# DMFX-1_v1_2.net
KiCad netlist of a schematic drawn in EAGLE
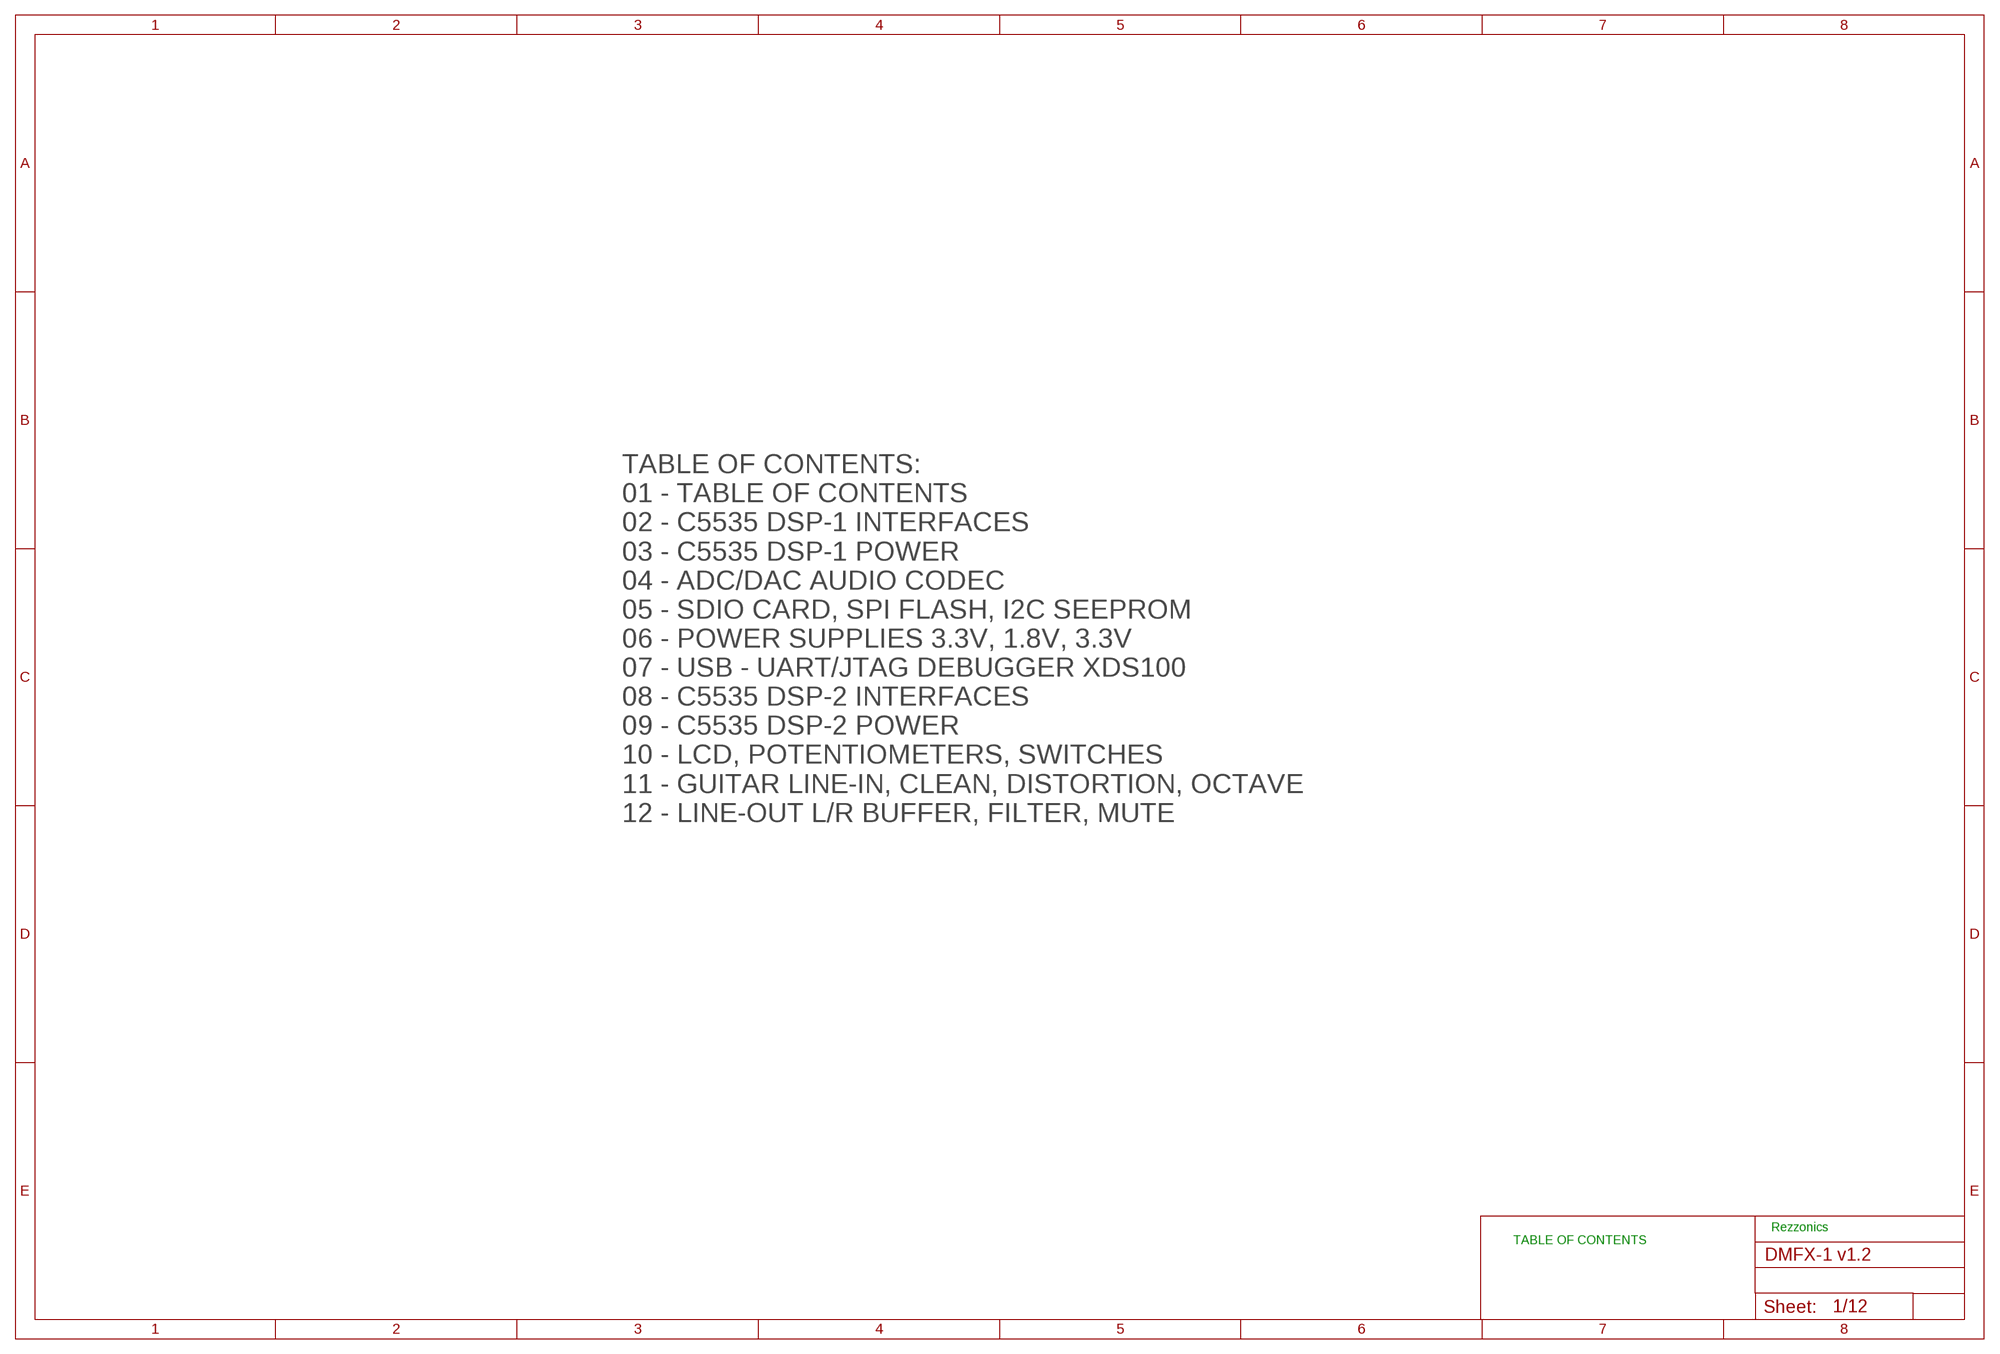
[diagram p0: schematic, sheet 1]
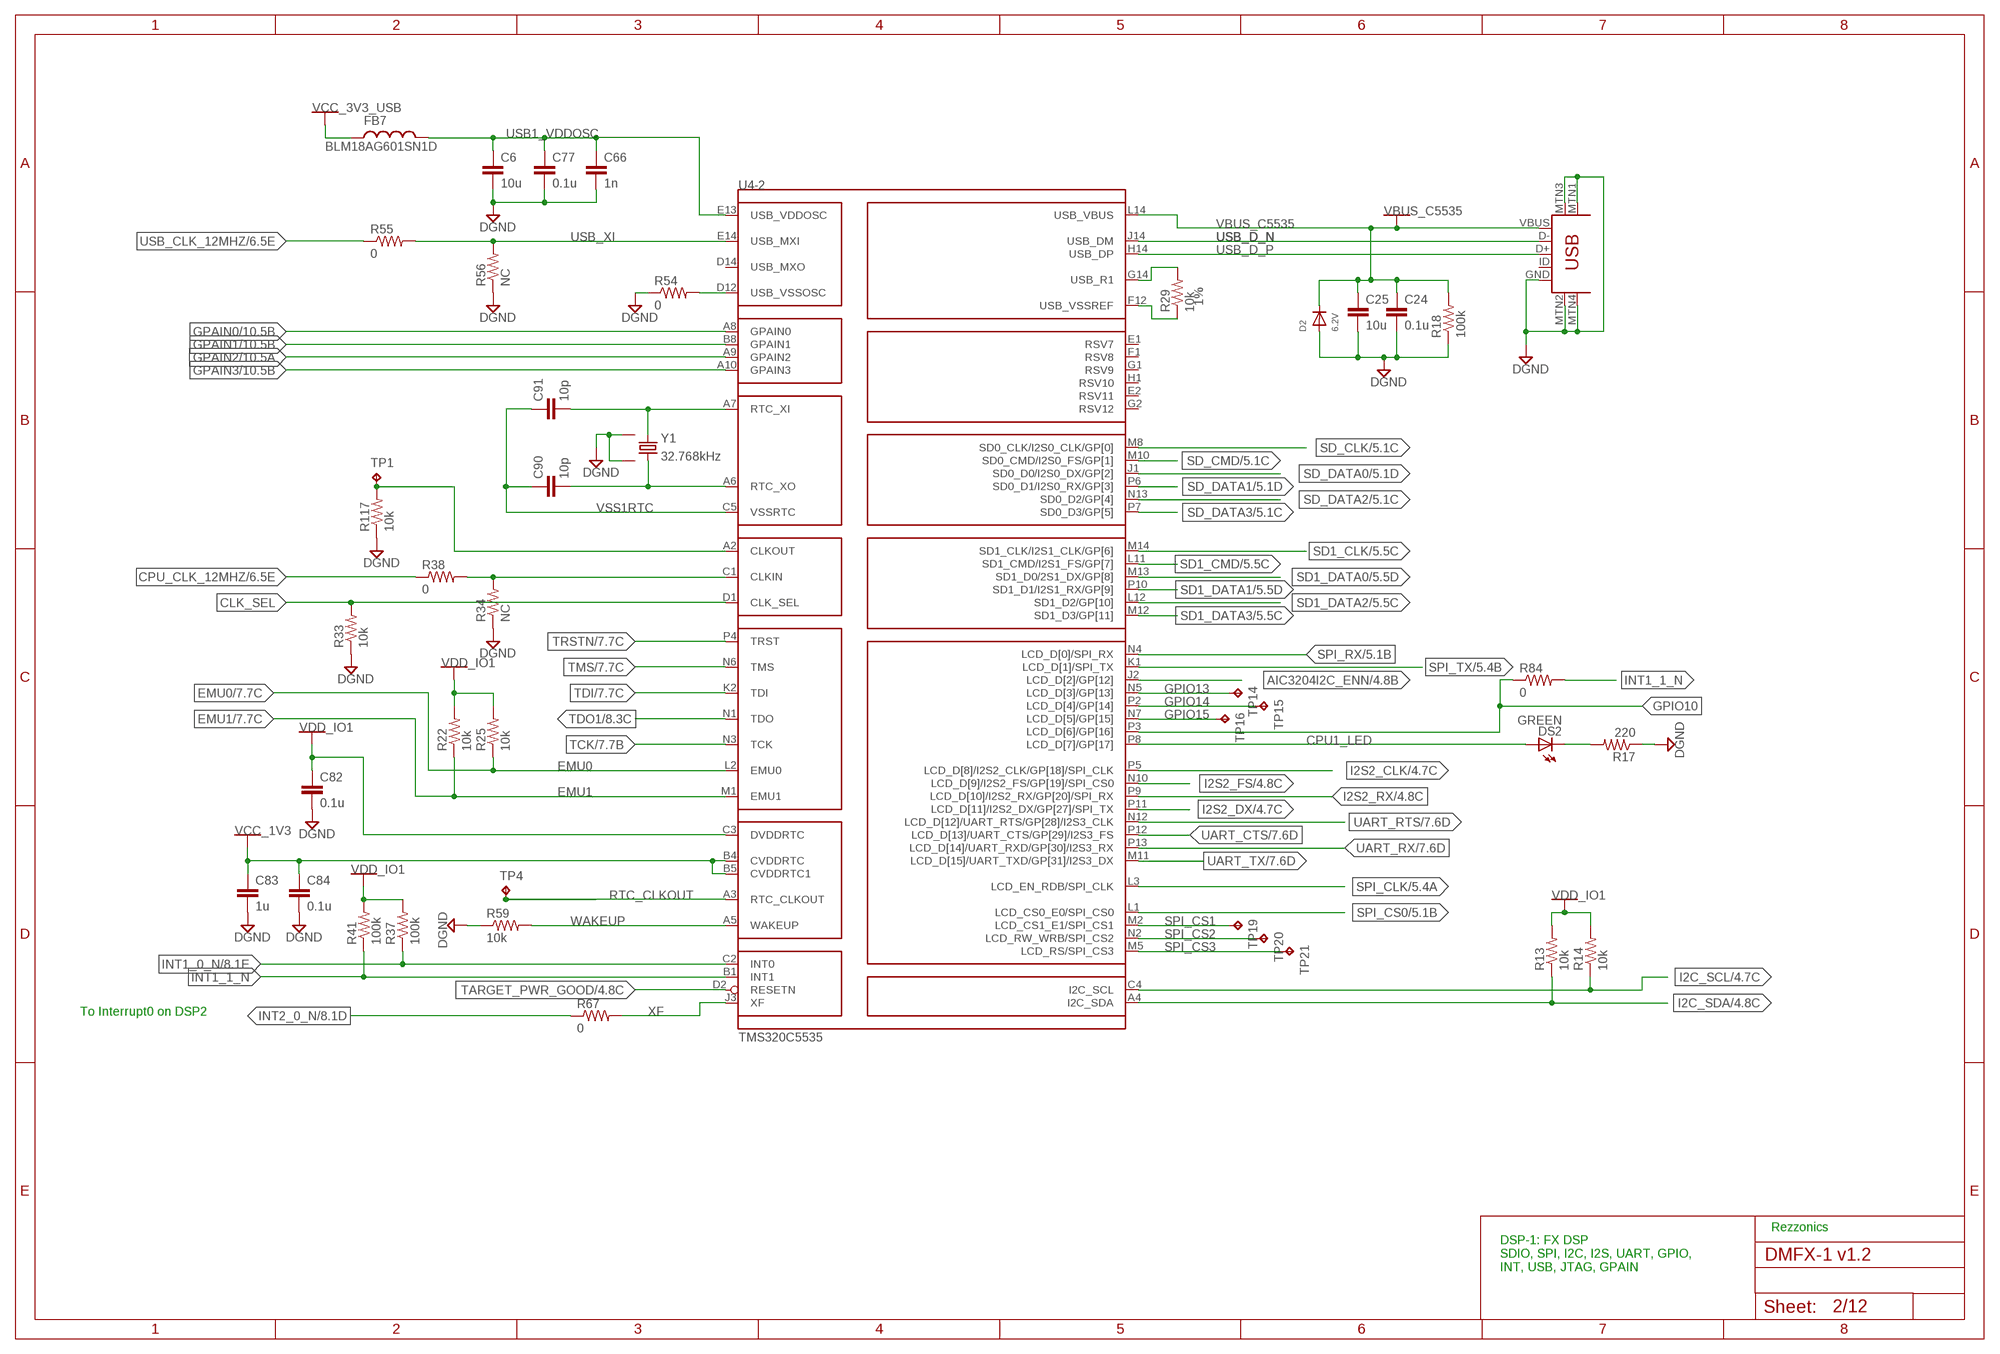
[diagram p1: schematic, sheet 2]
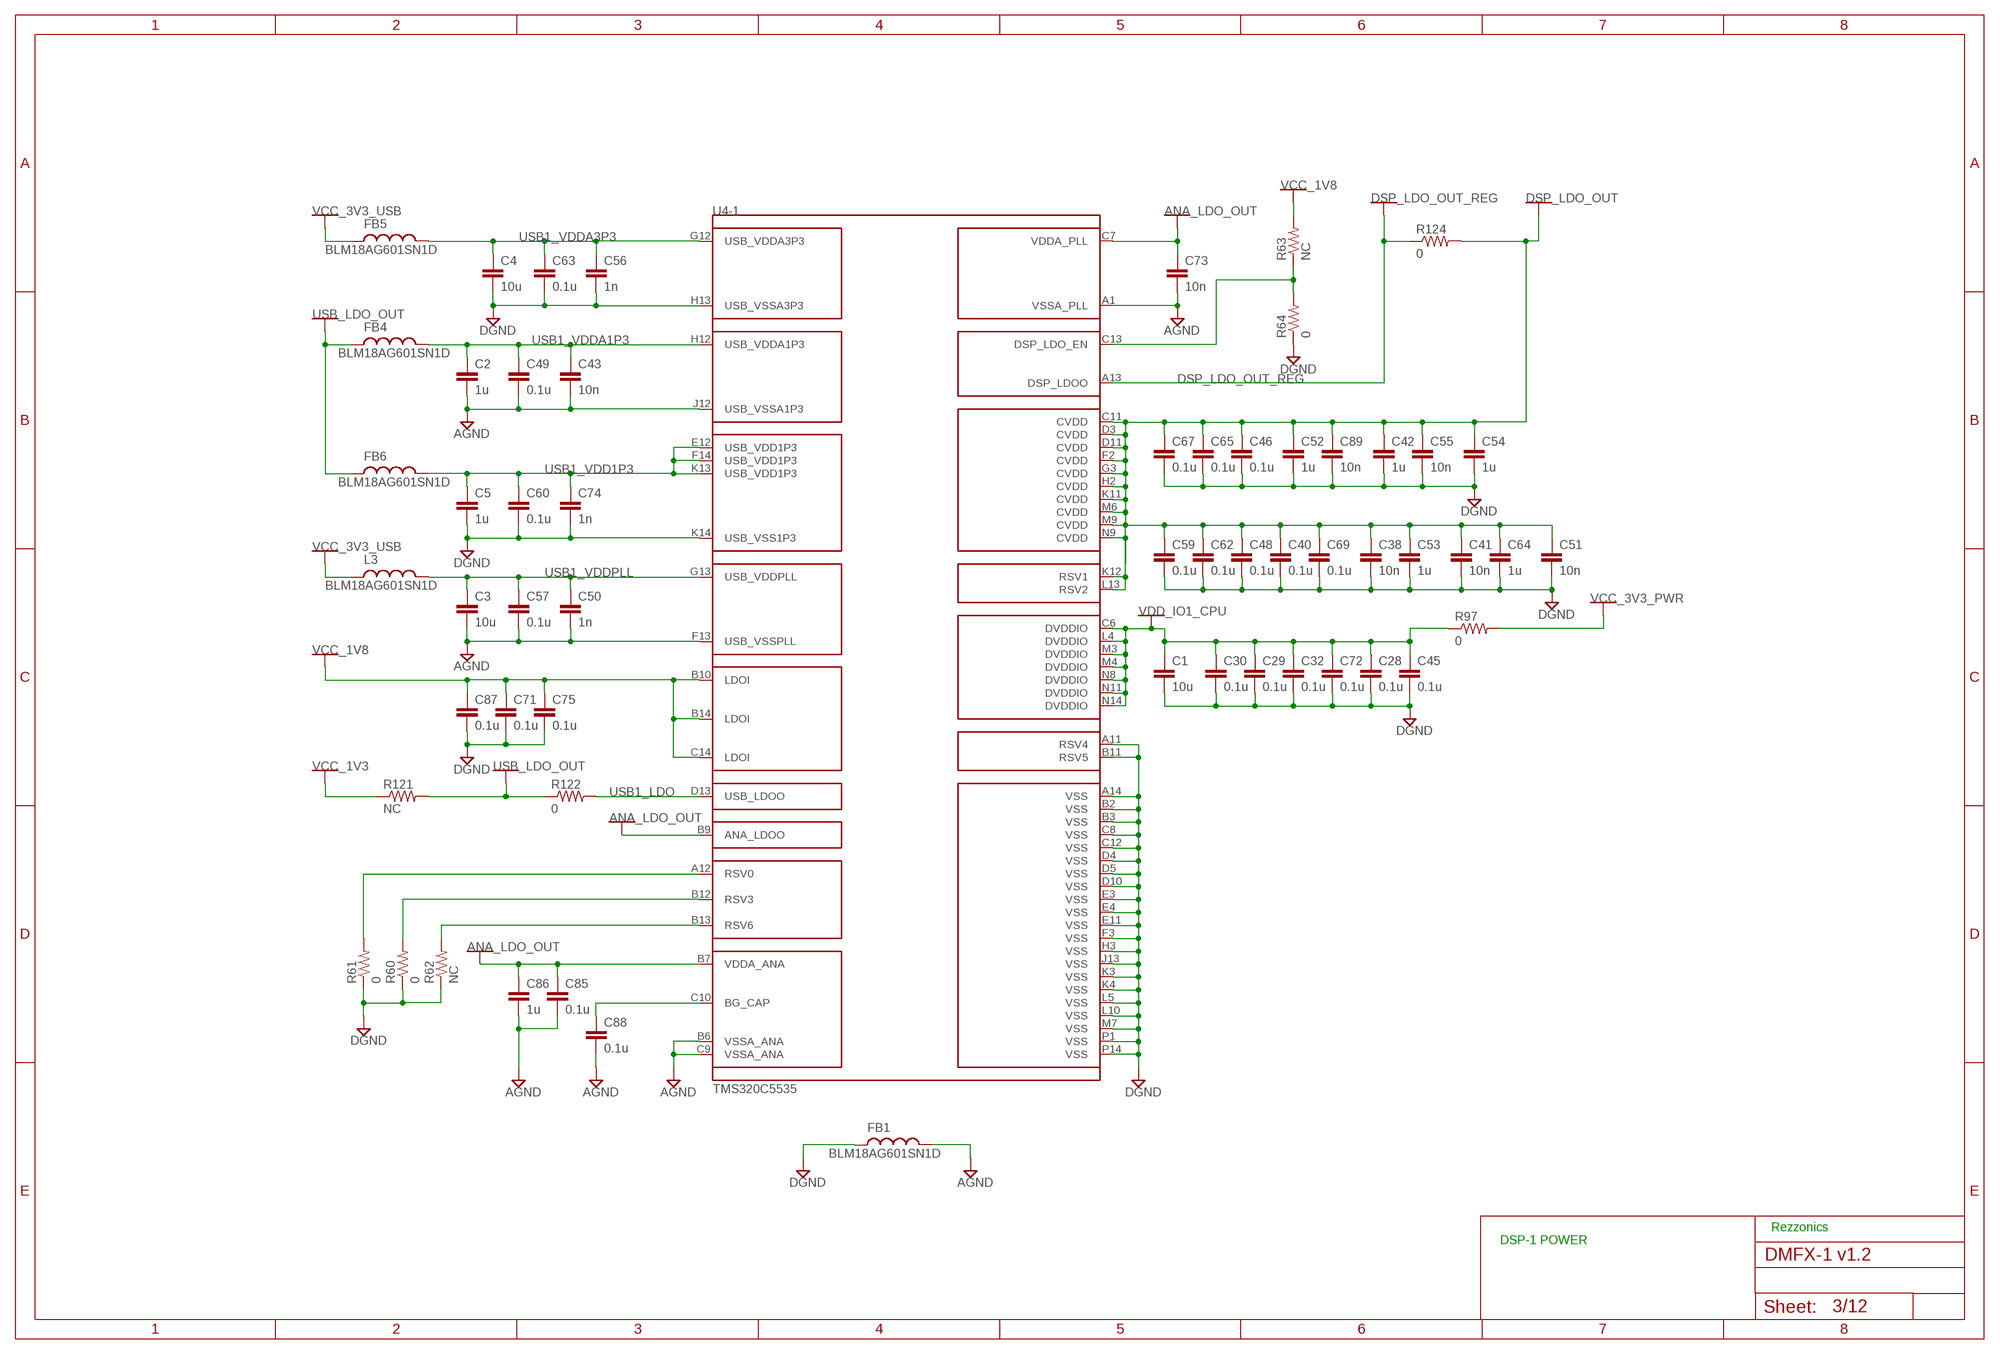
[diagram p2: schematic, sheet 3]
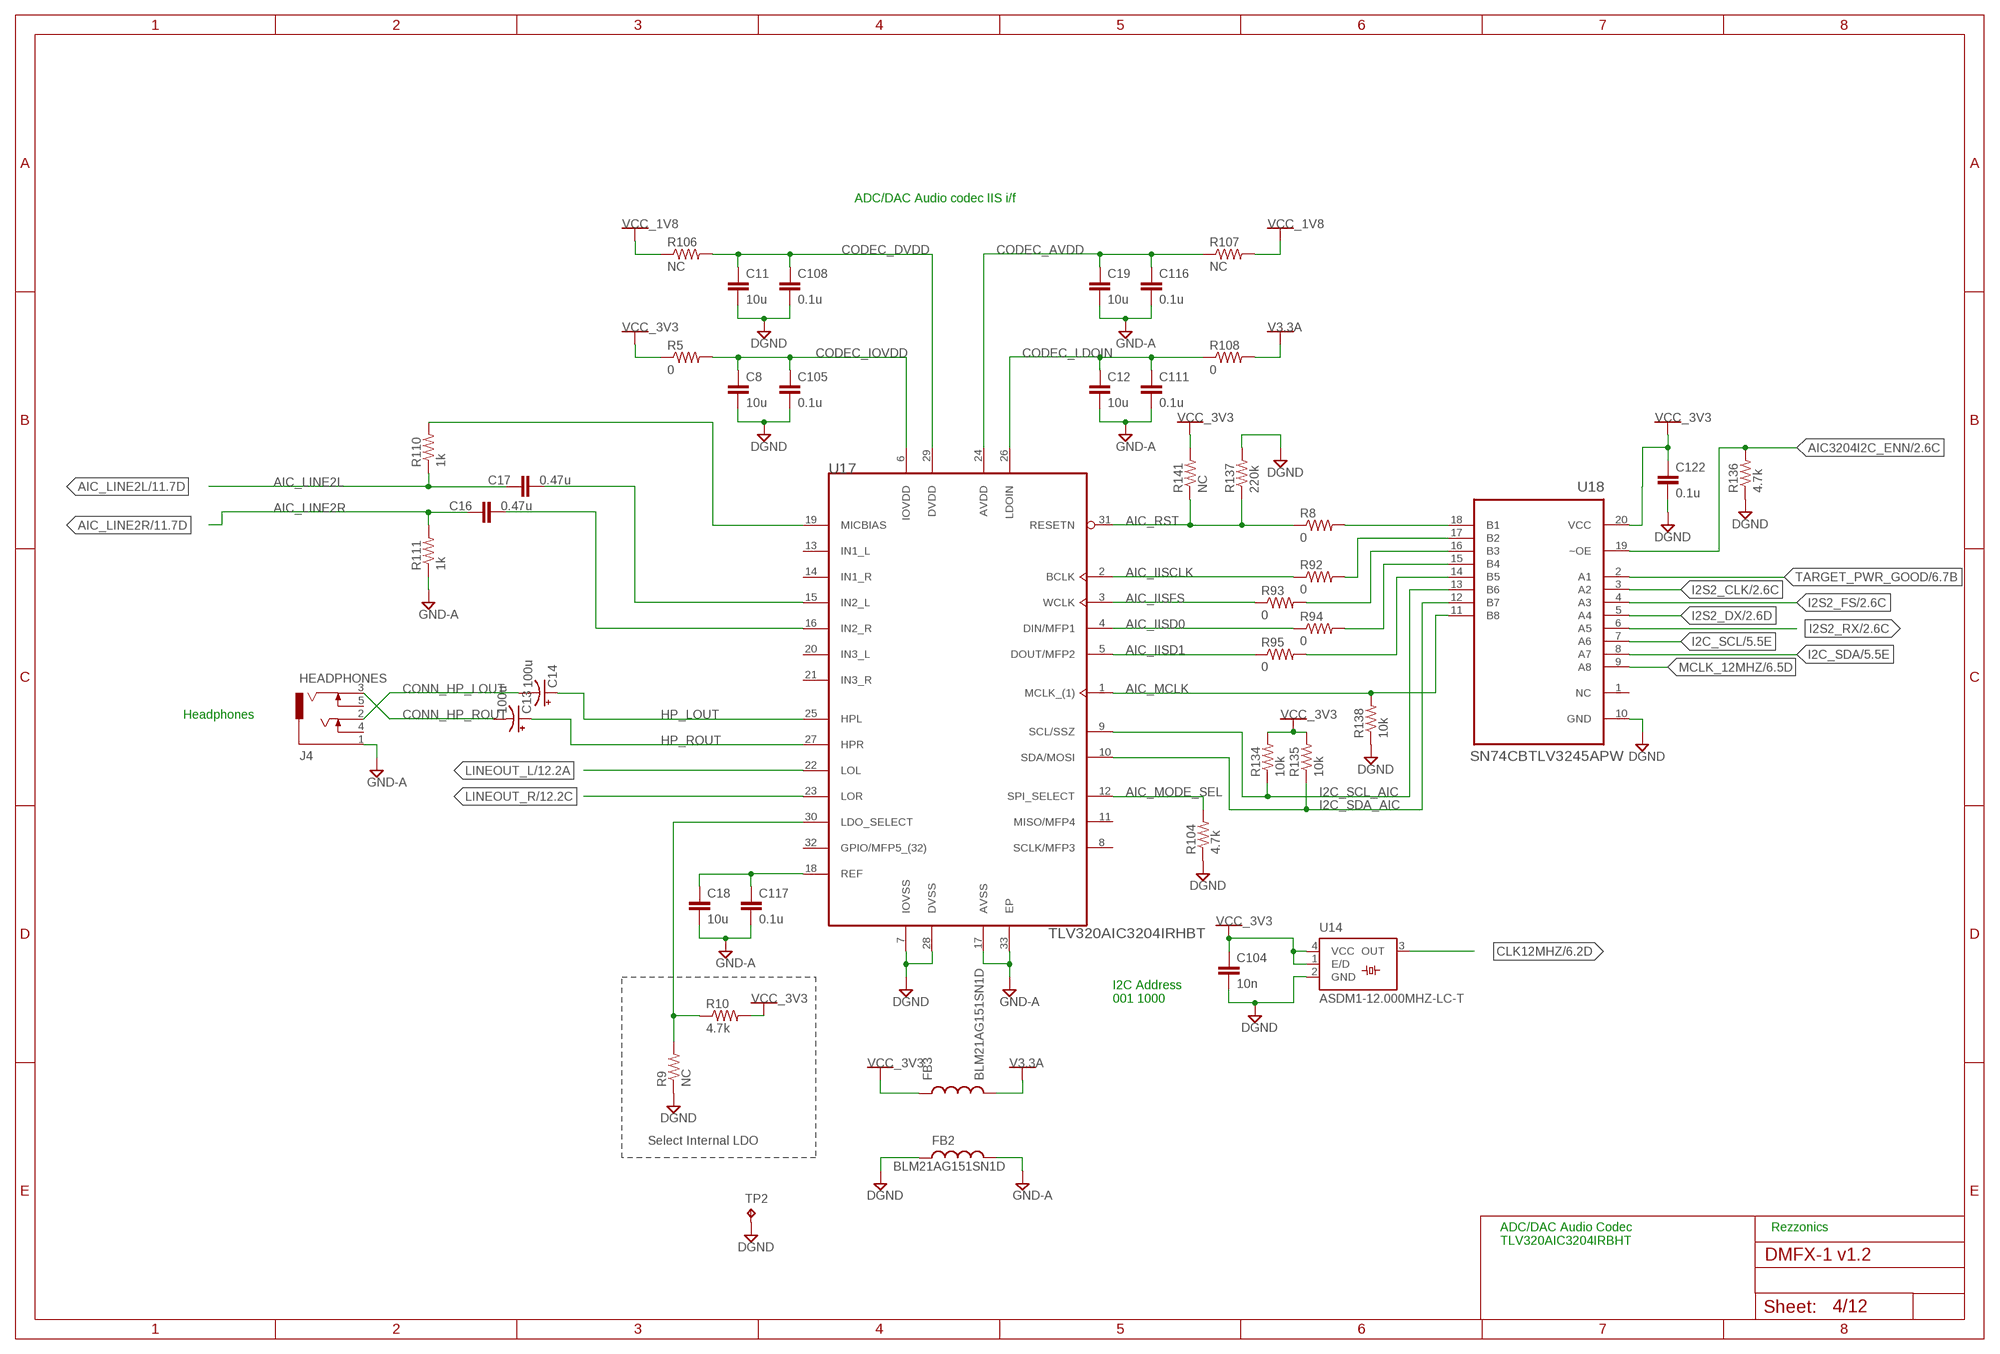
[diagram p3: schematic, sheet 4]
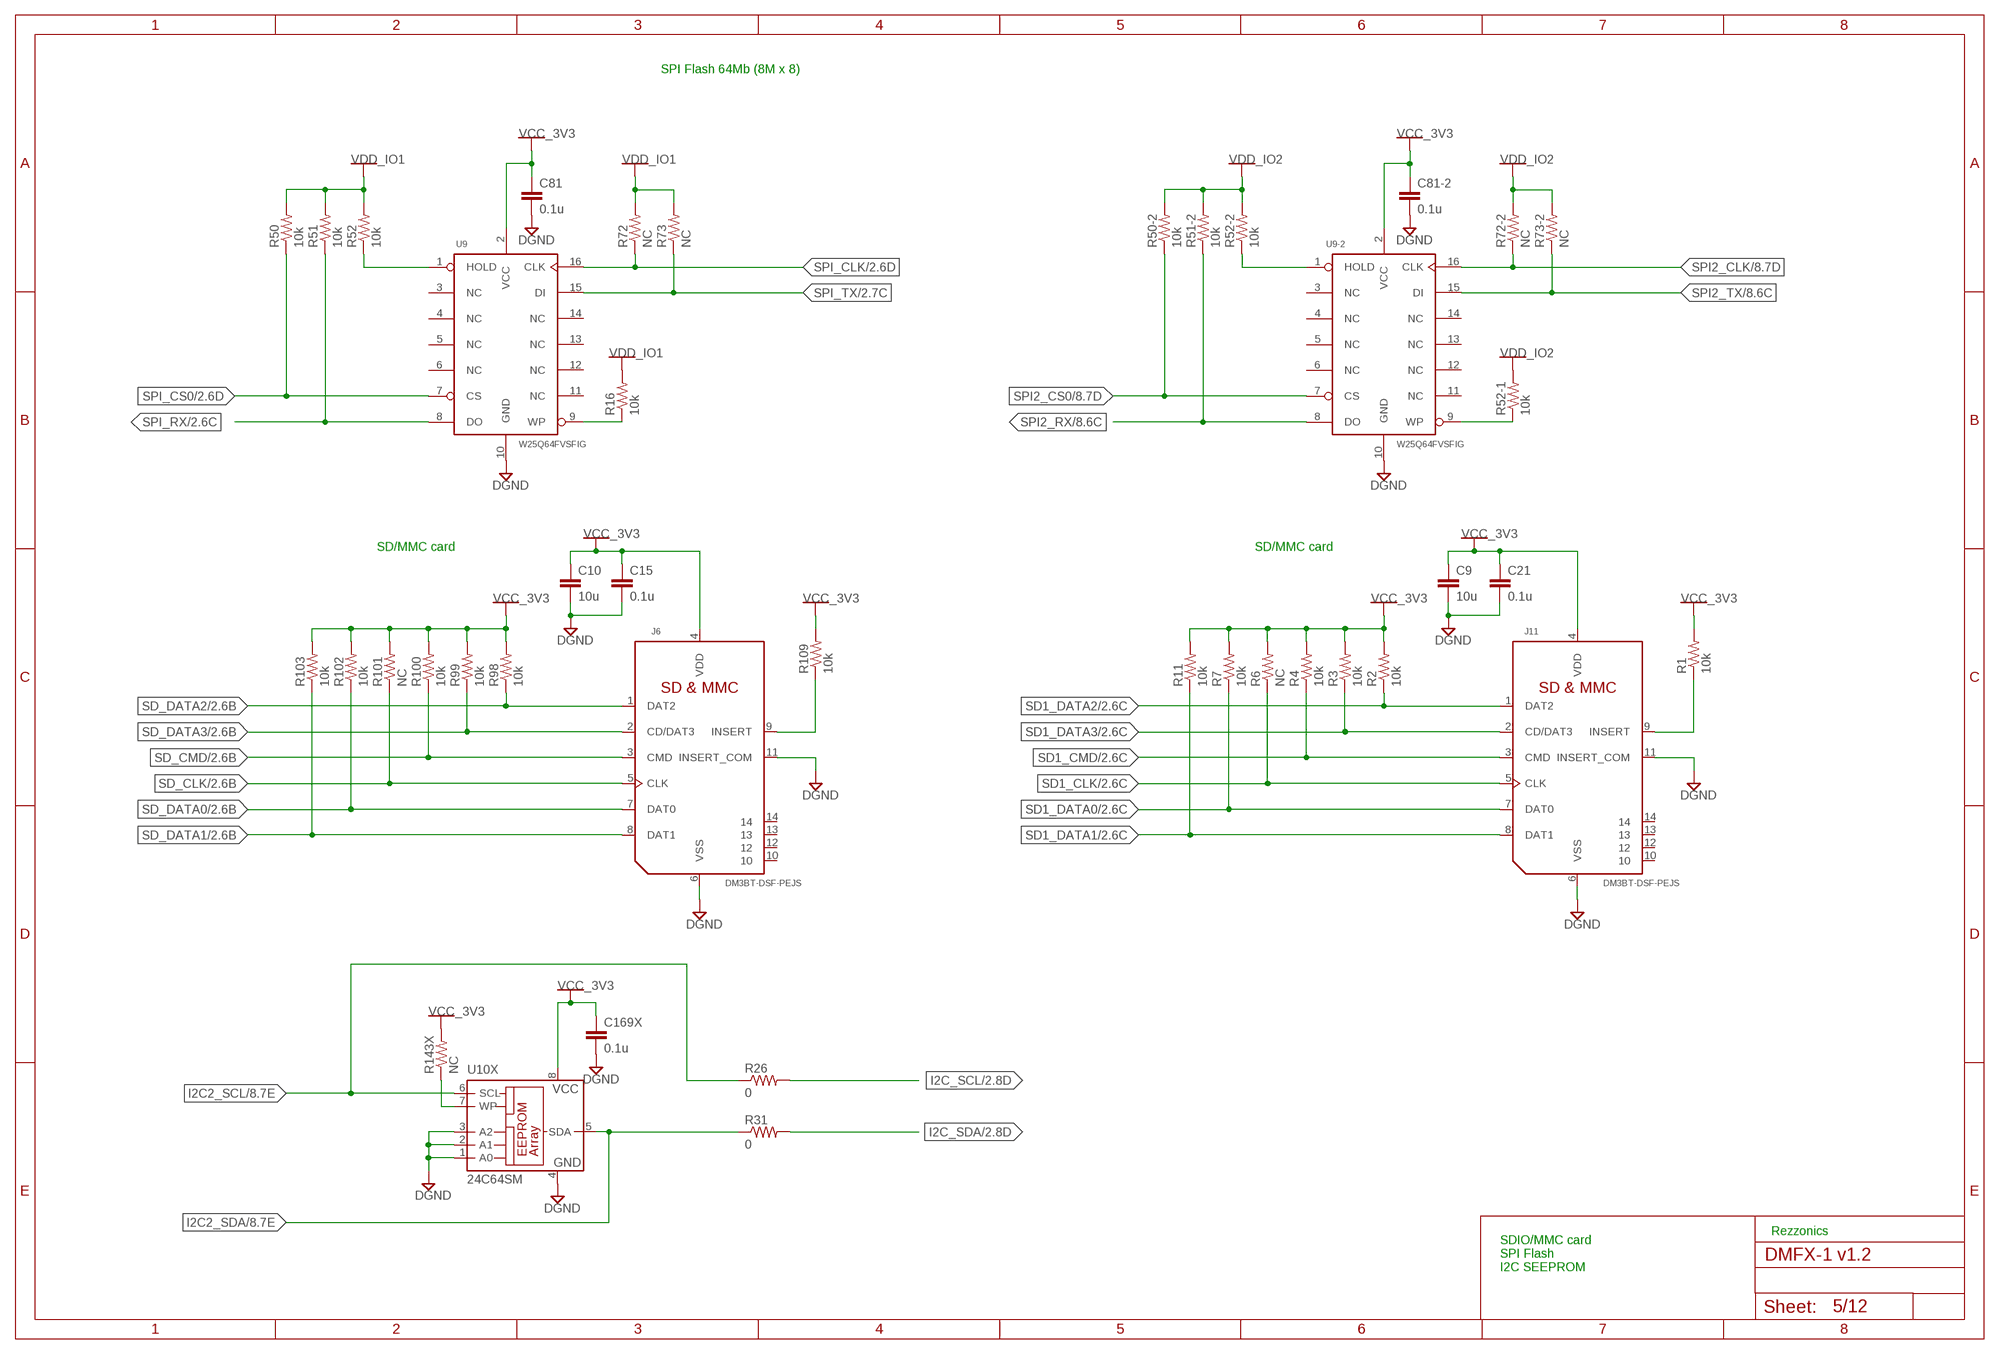
[diagram p4: schematic, sheet 5]
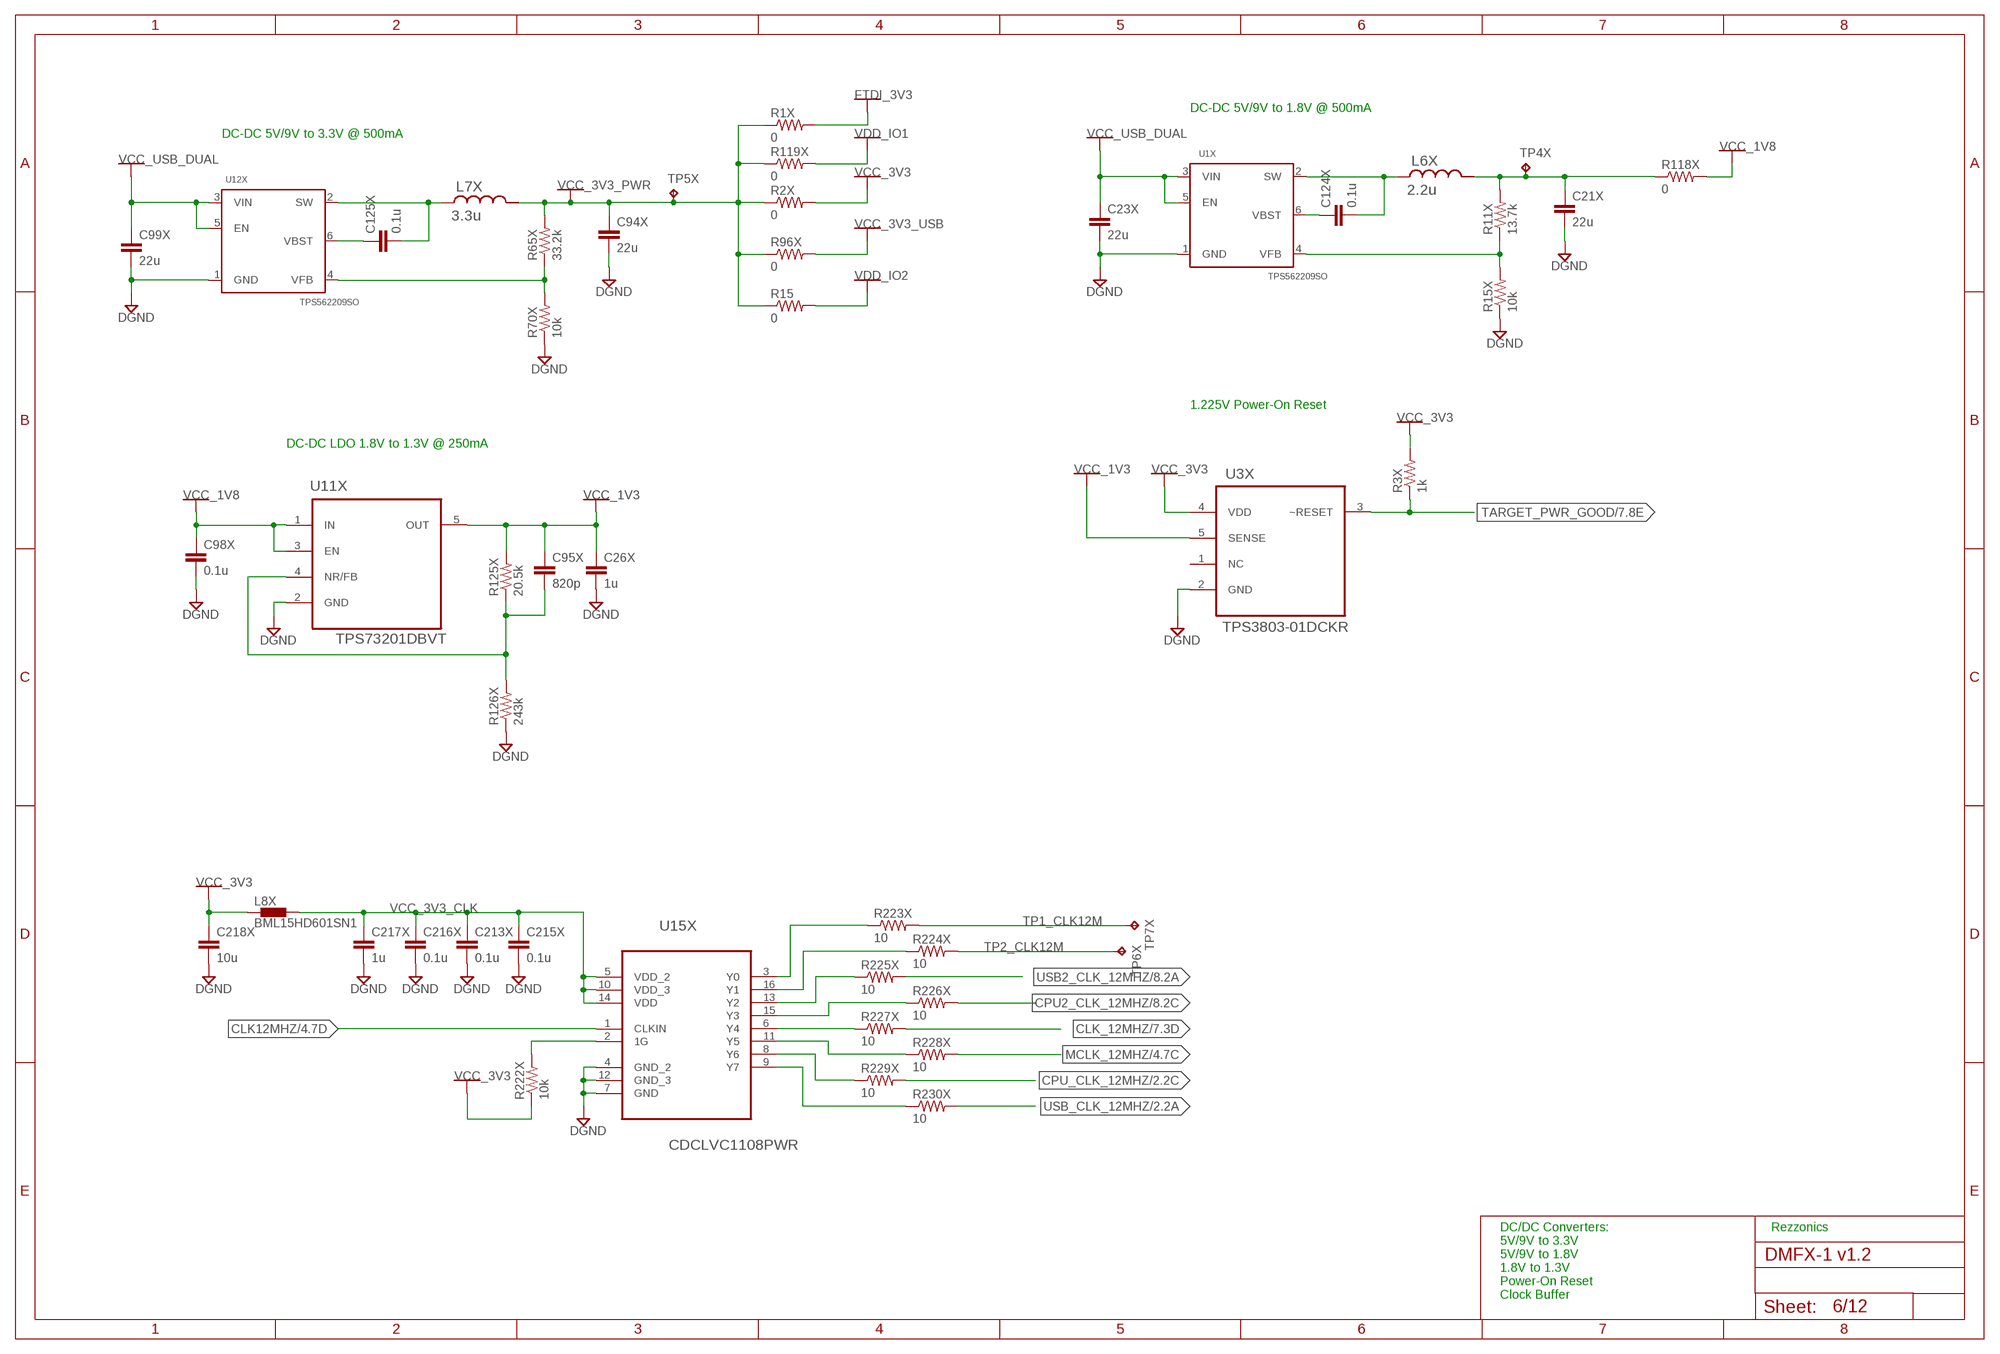
[diagram p5: schematic, sheet 6]
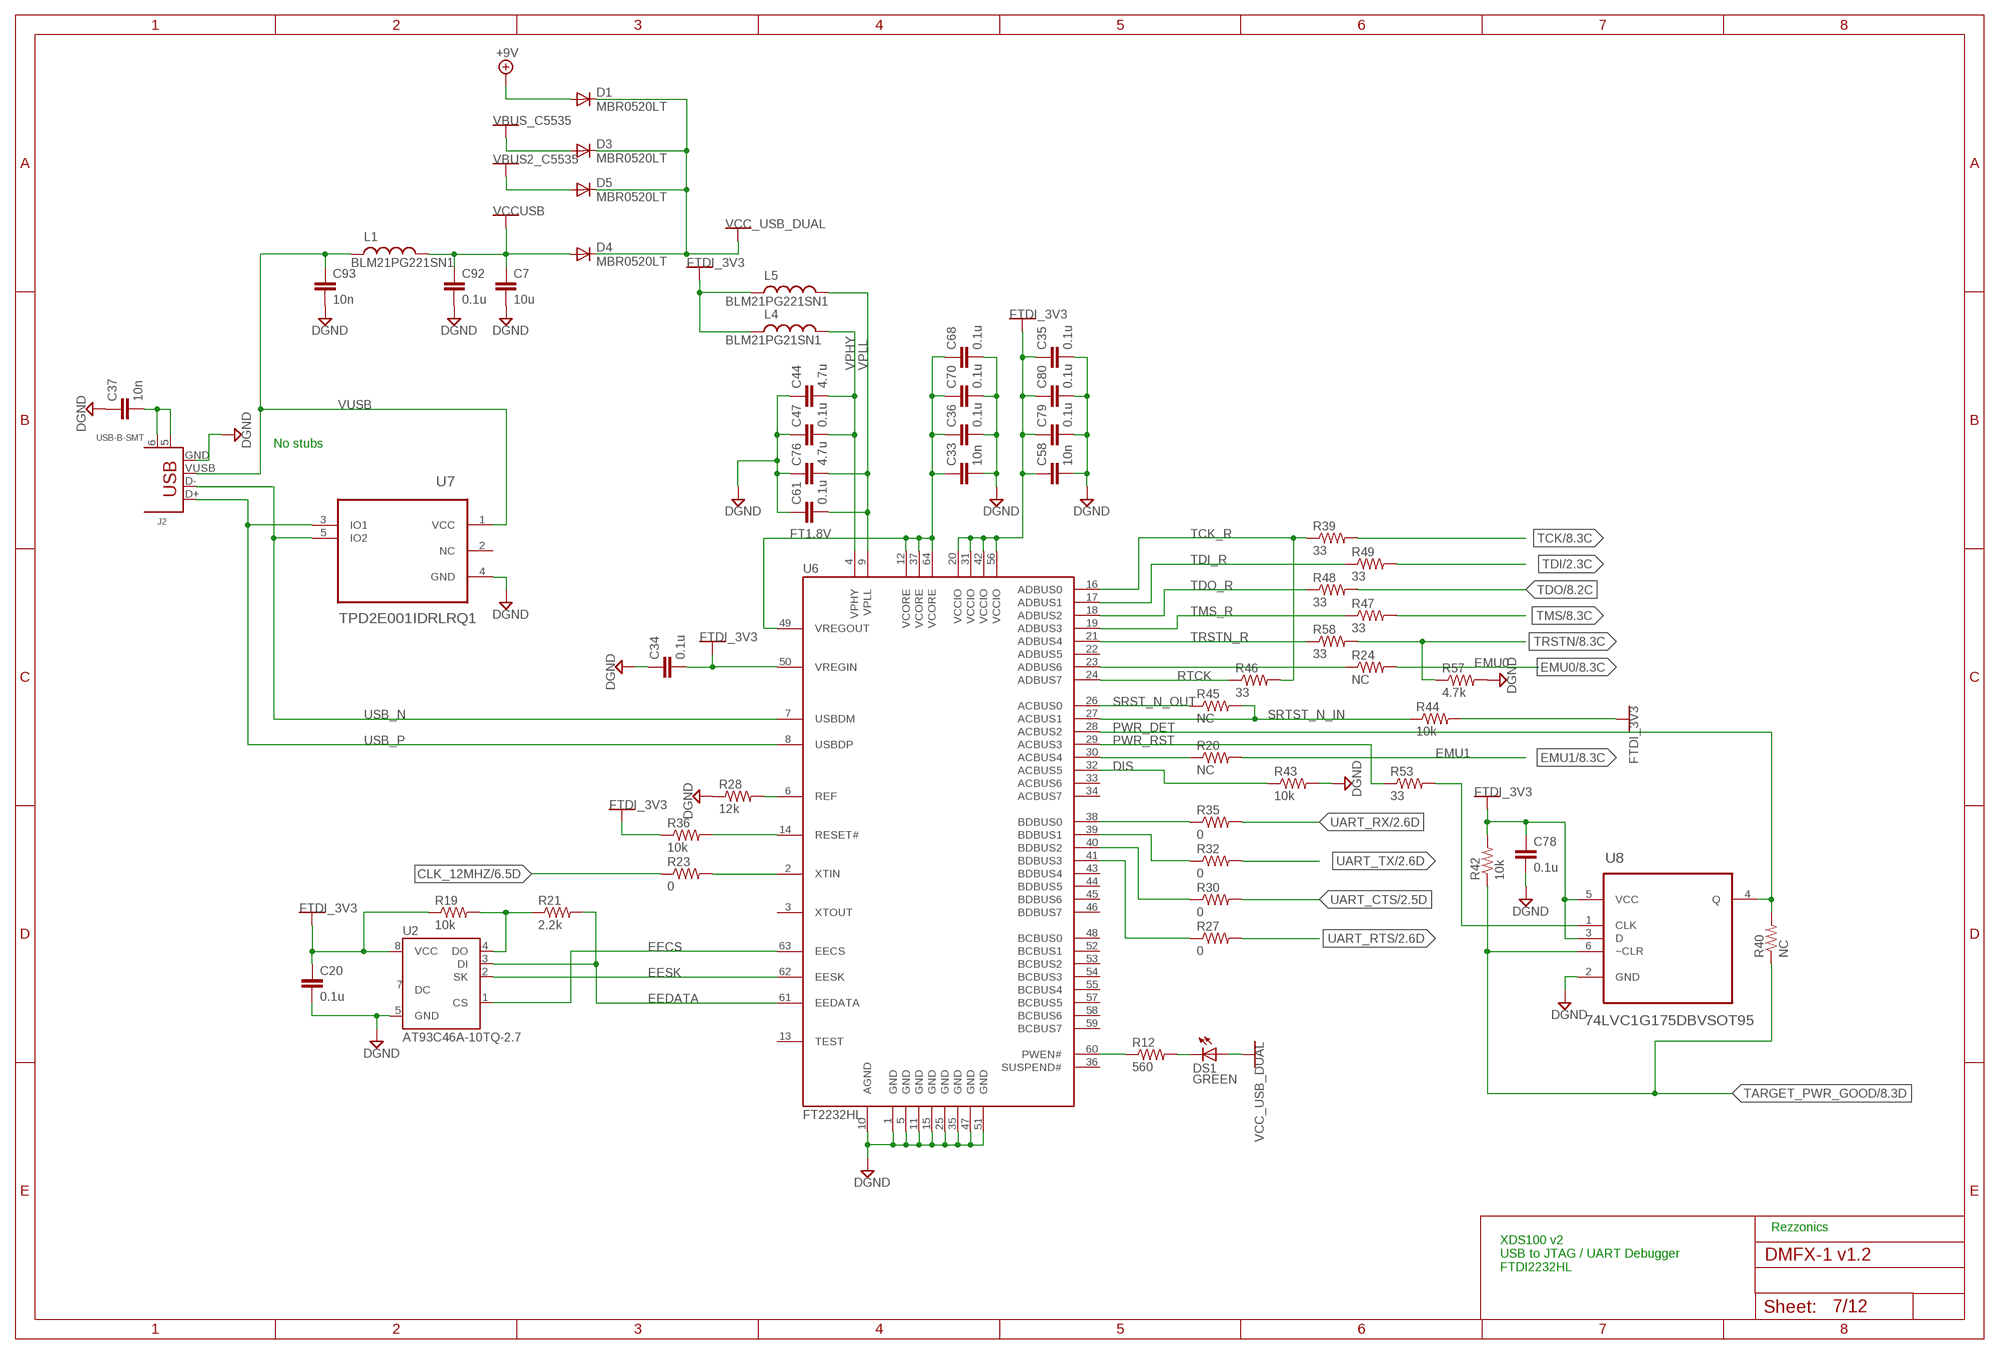
[diagram p6: schematic, sheet 7]
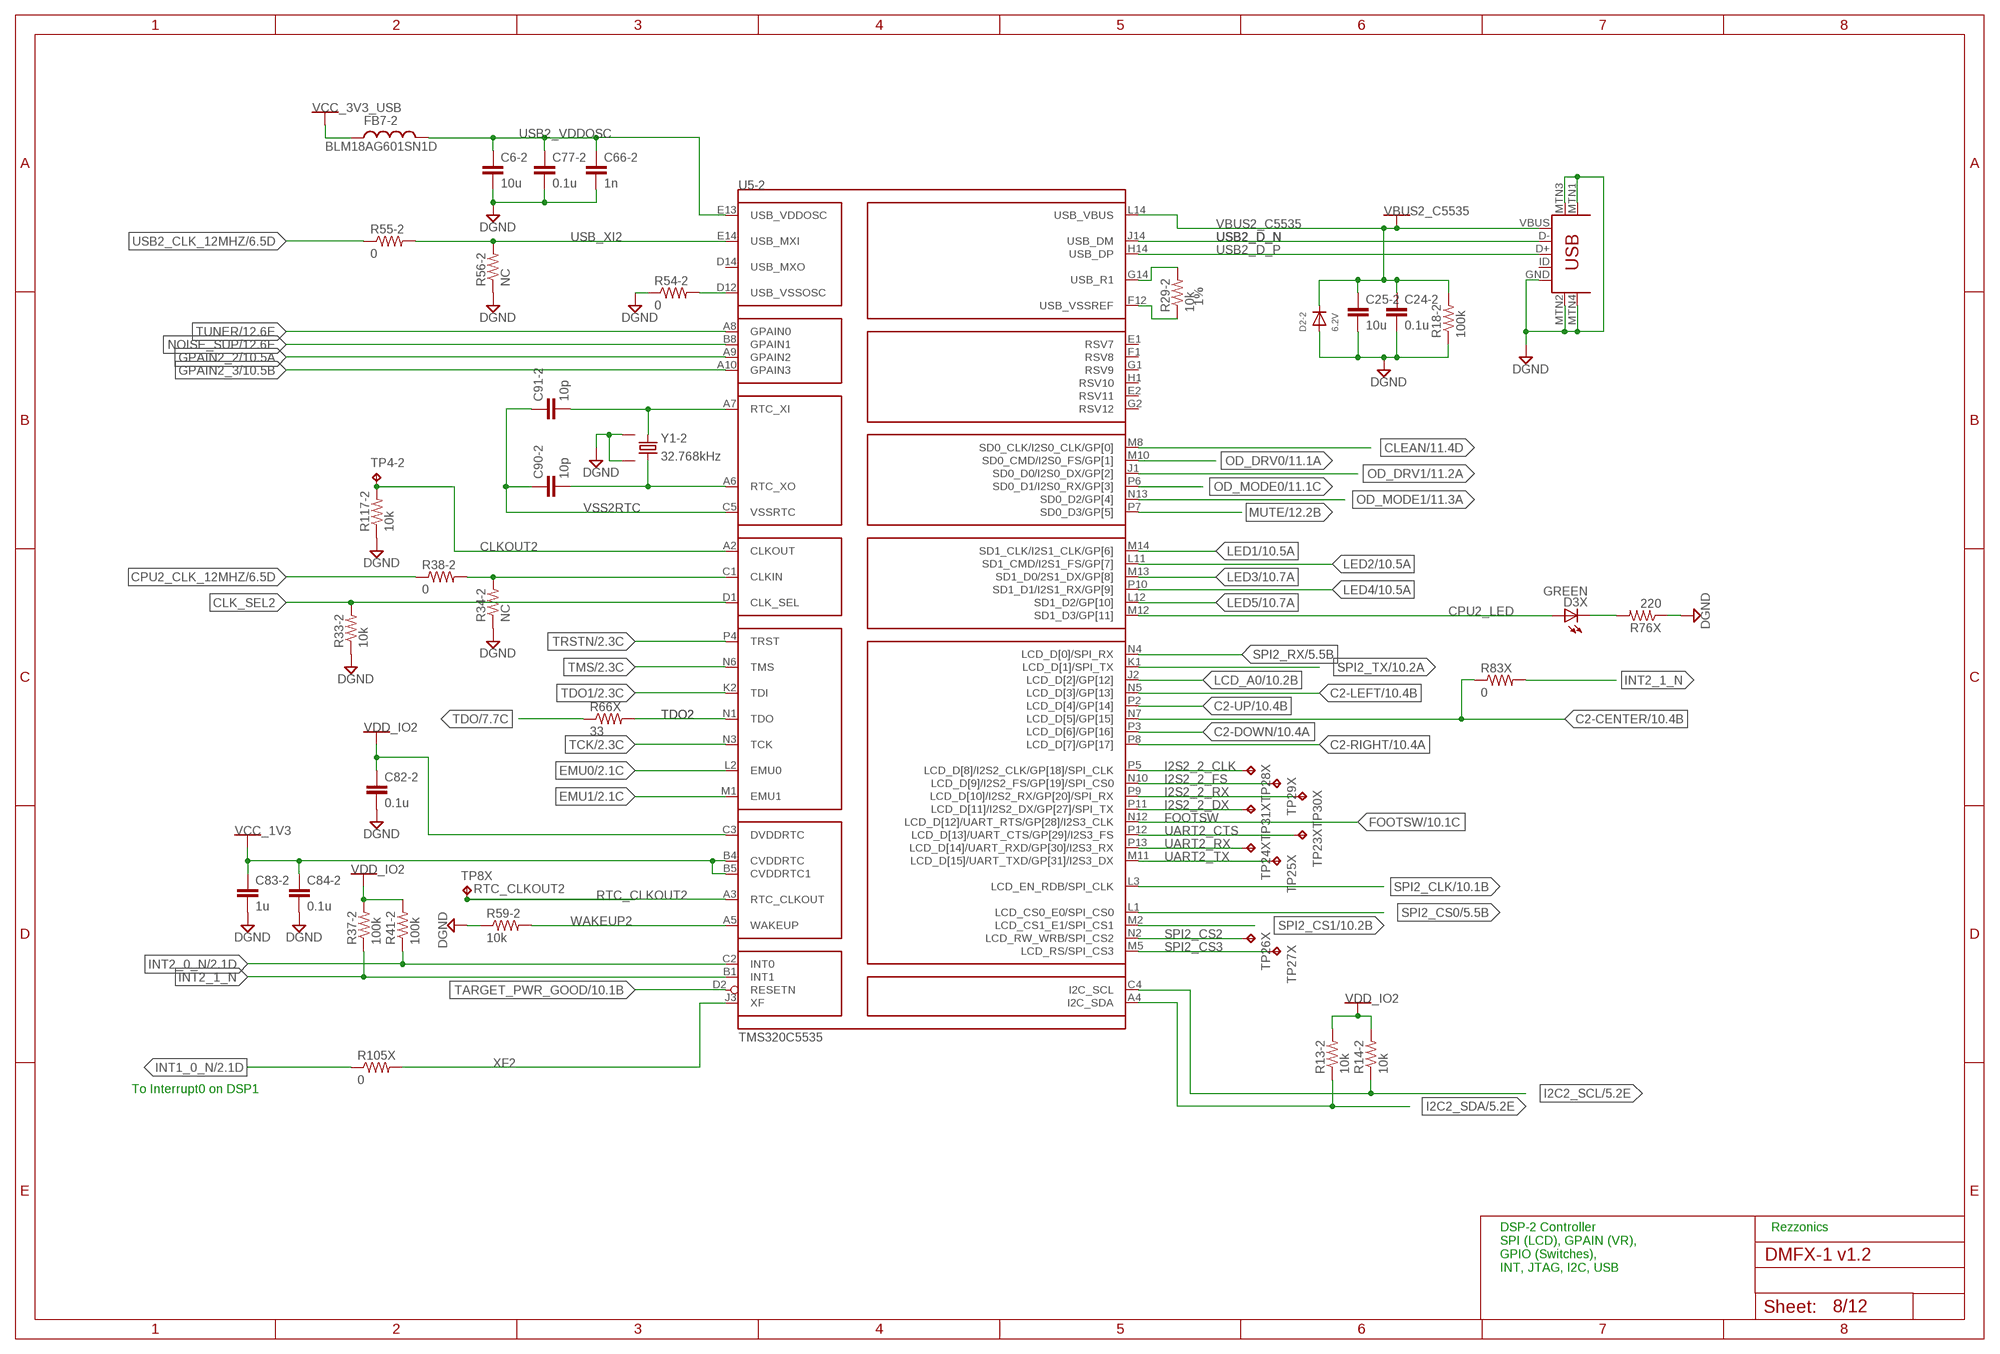
[diagram p7: schematic, sheet 8]
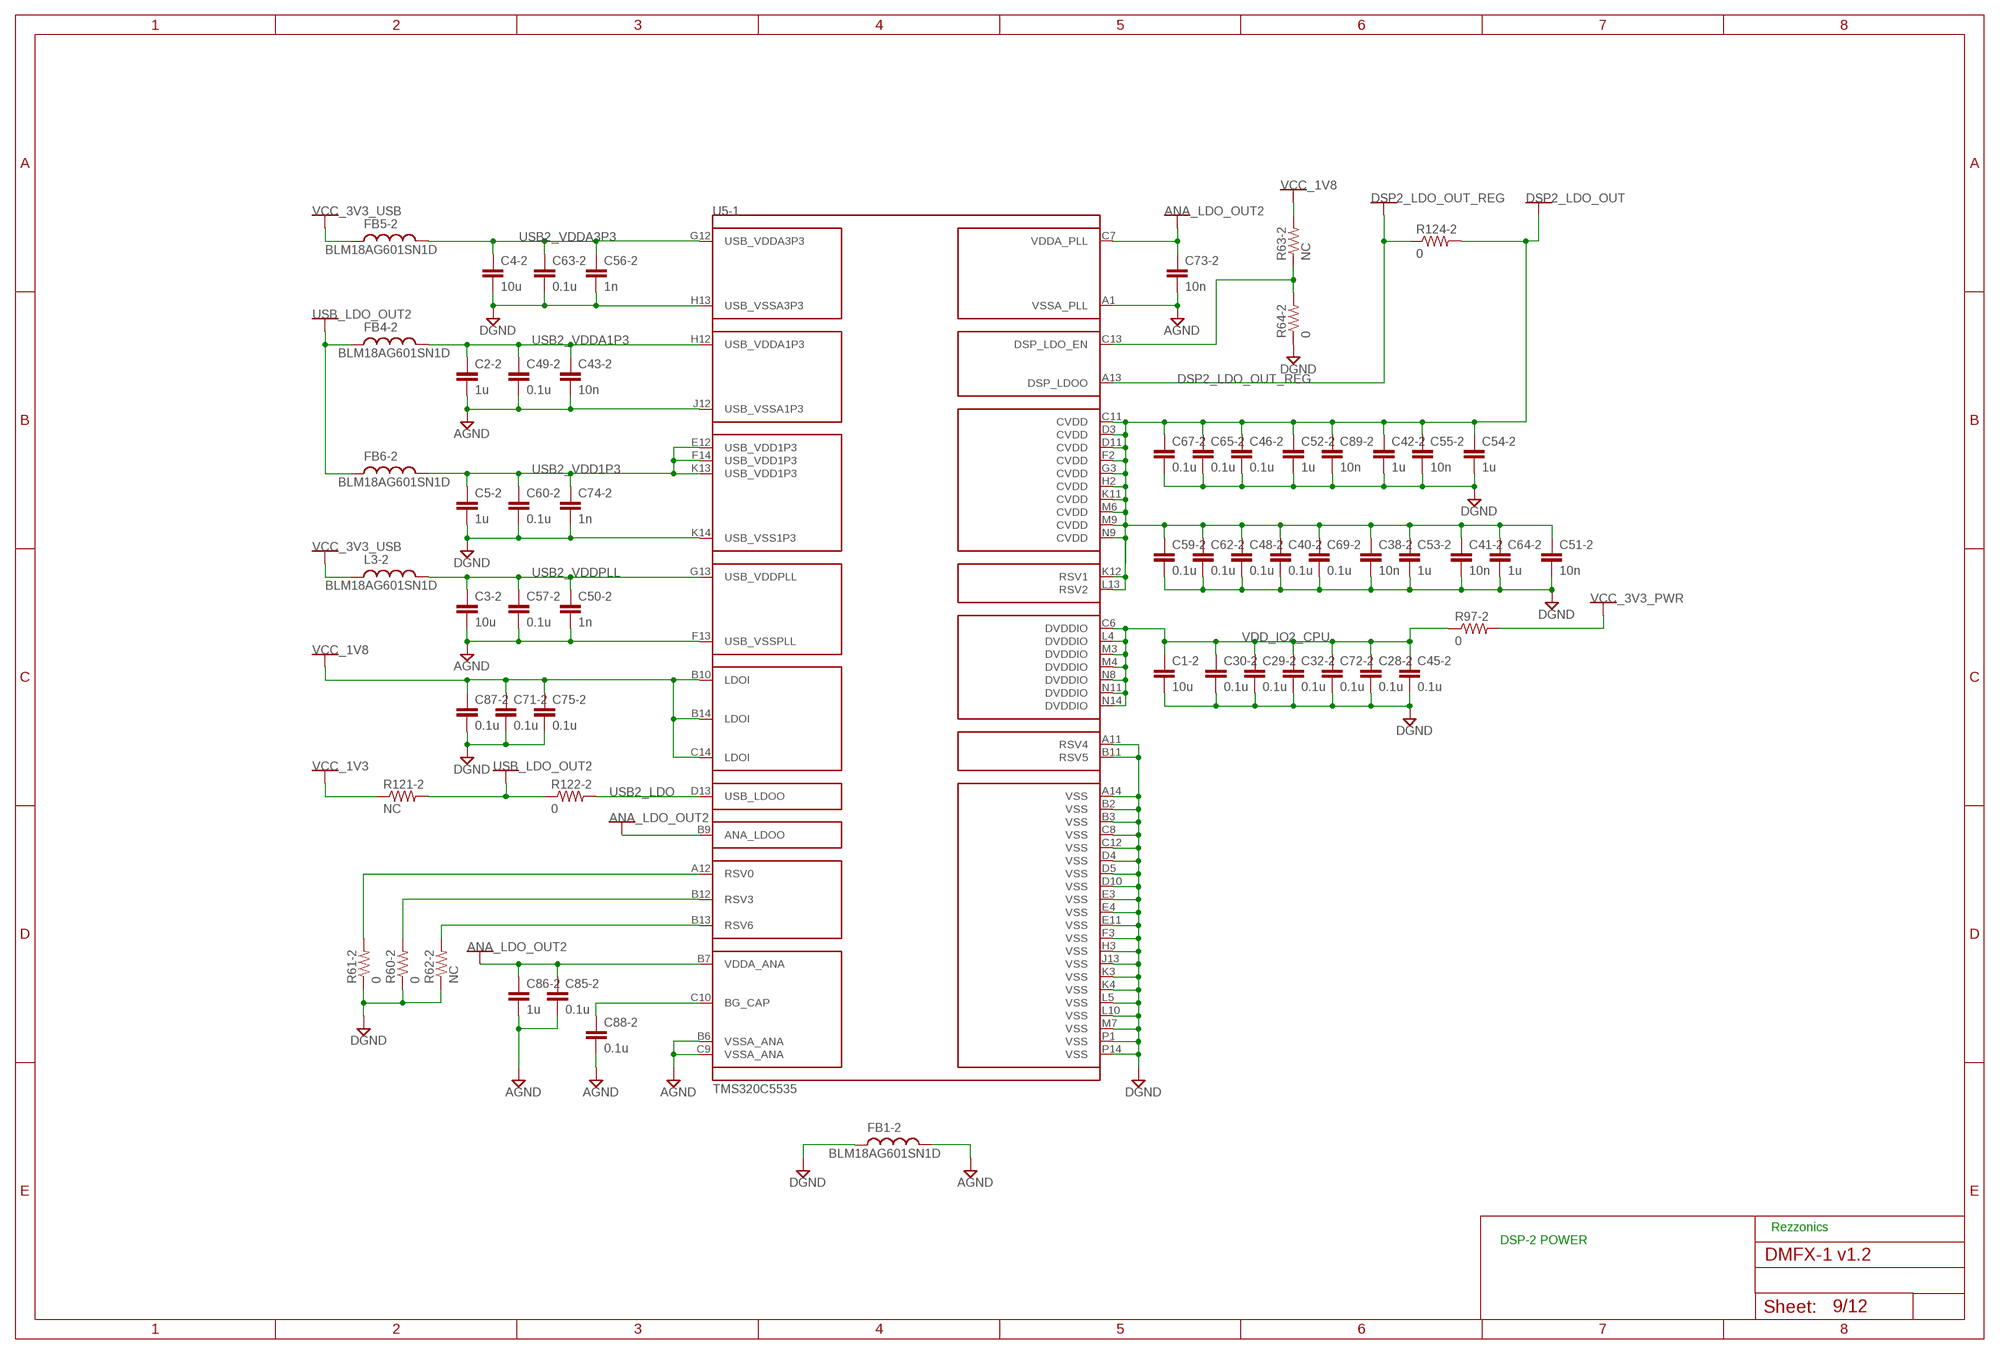
[diagram p8: schematic, sheet 9]
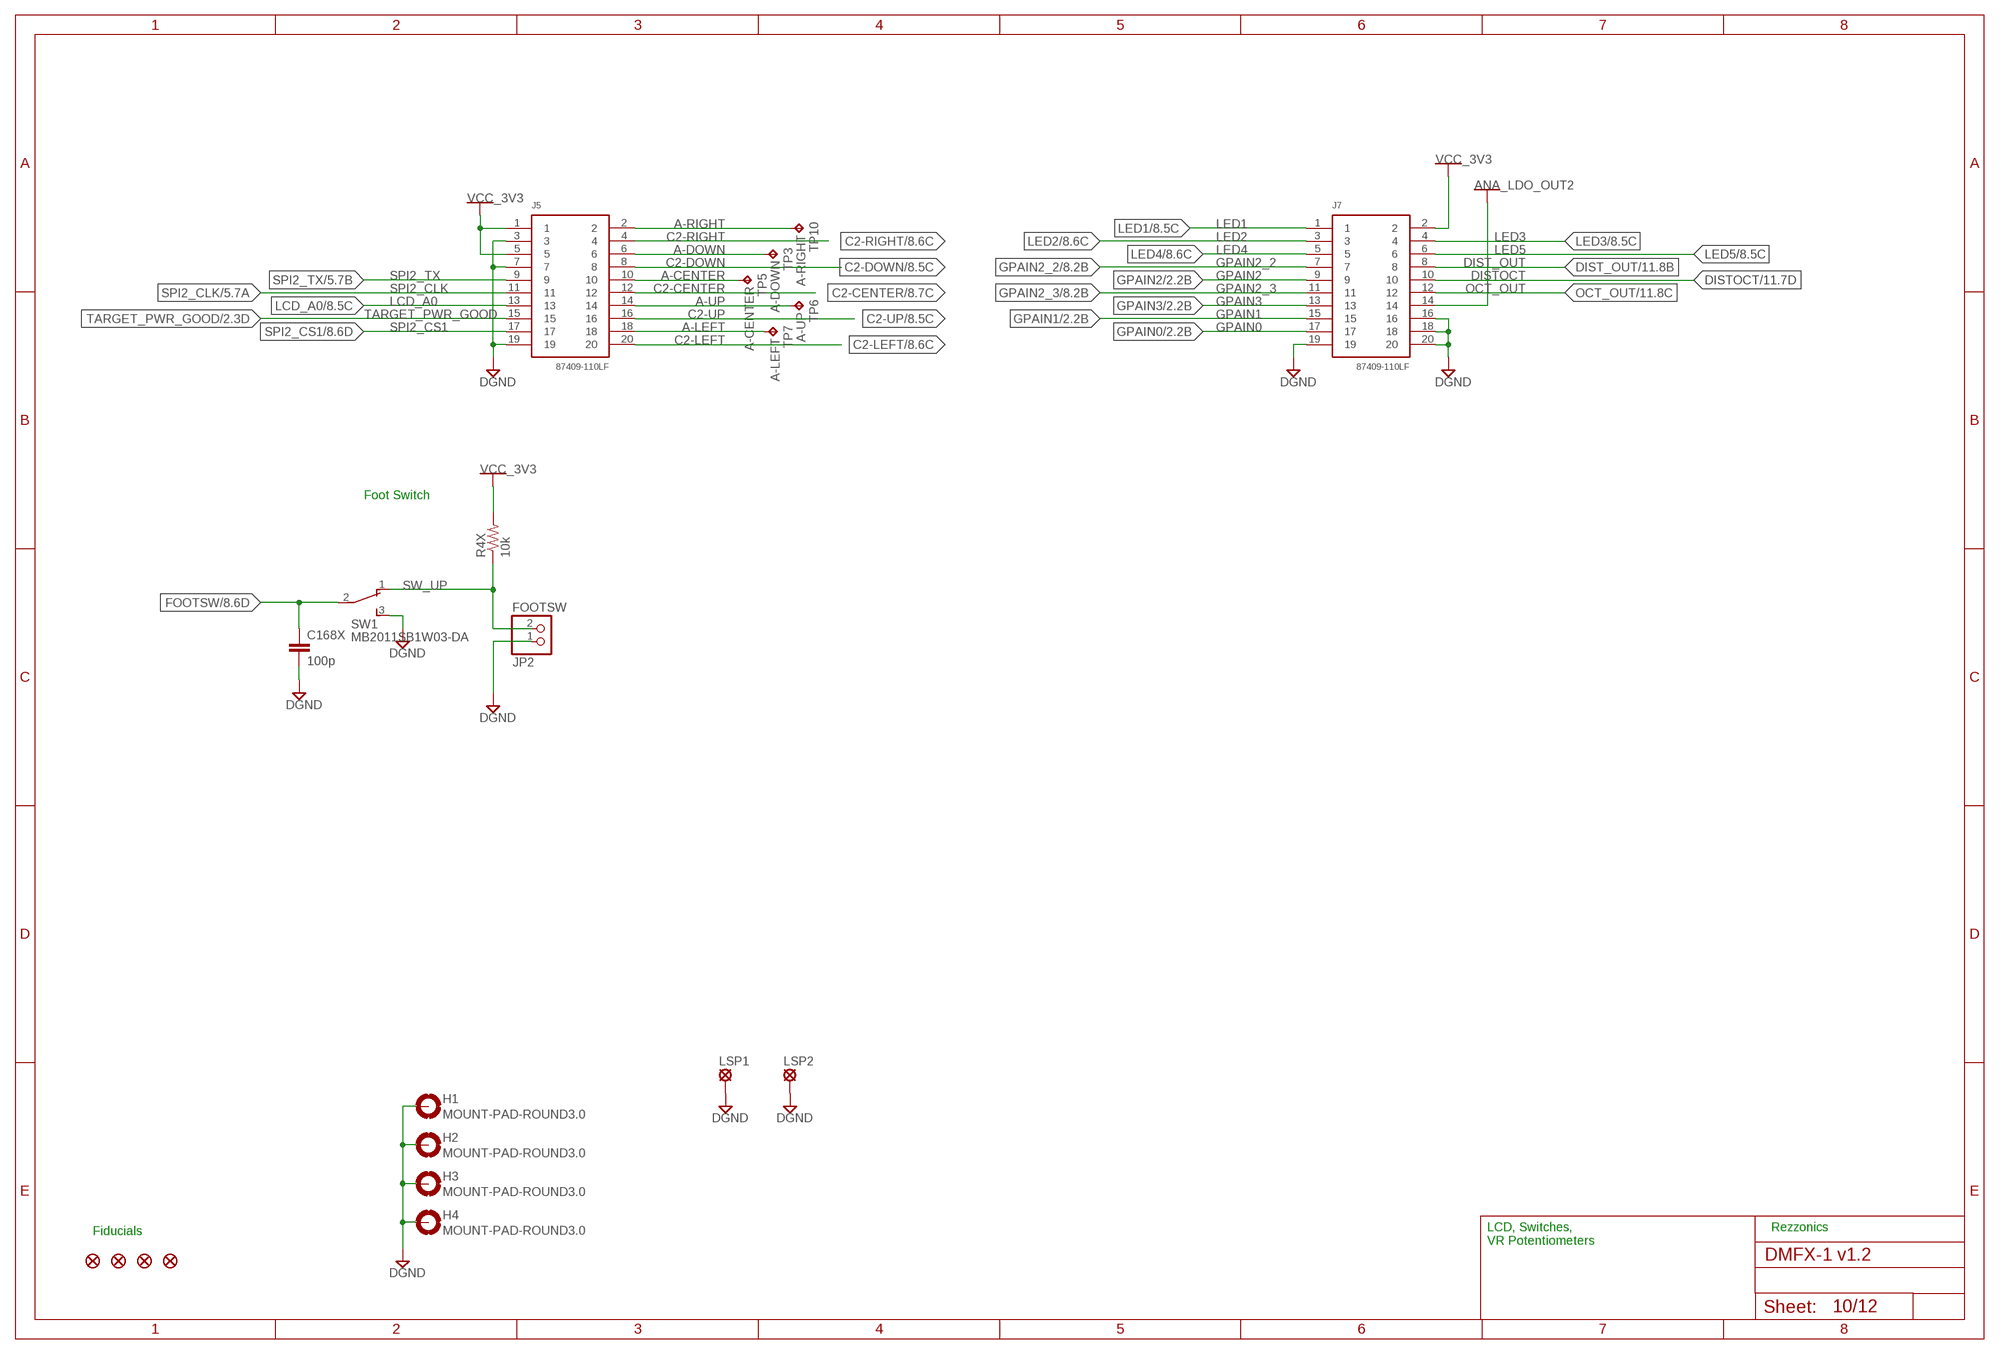
[diagram p9: schematic, sheet 10]
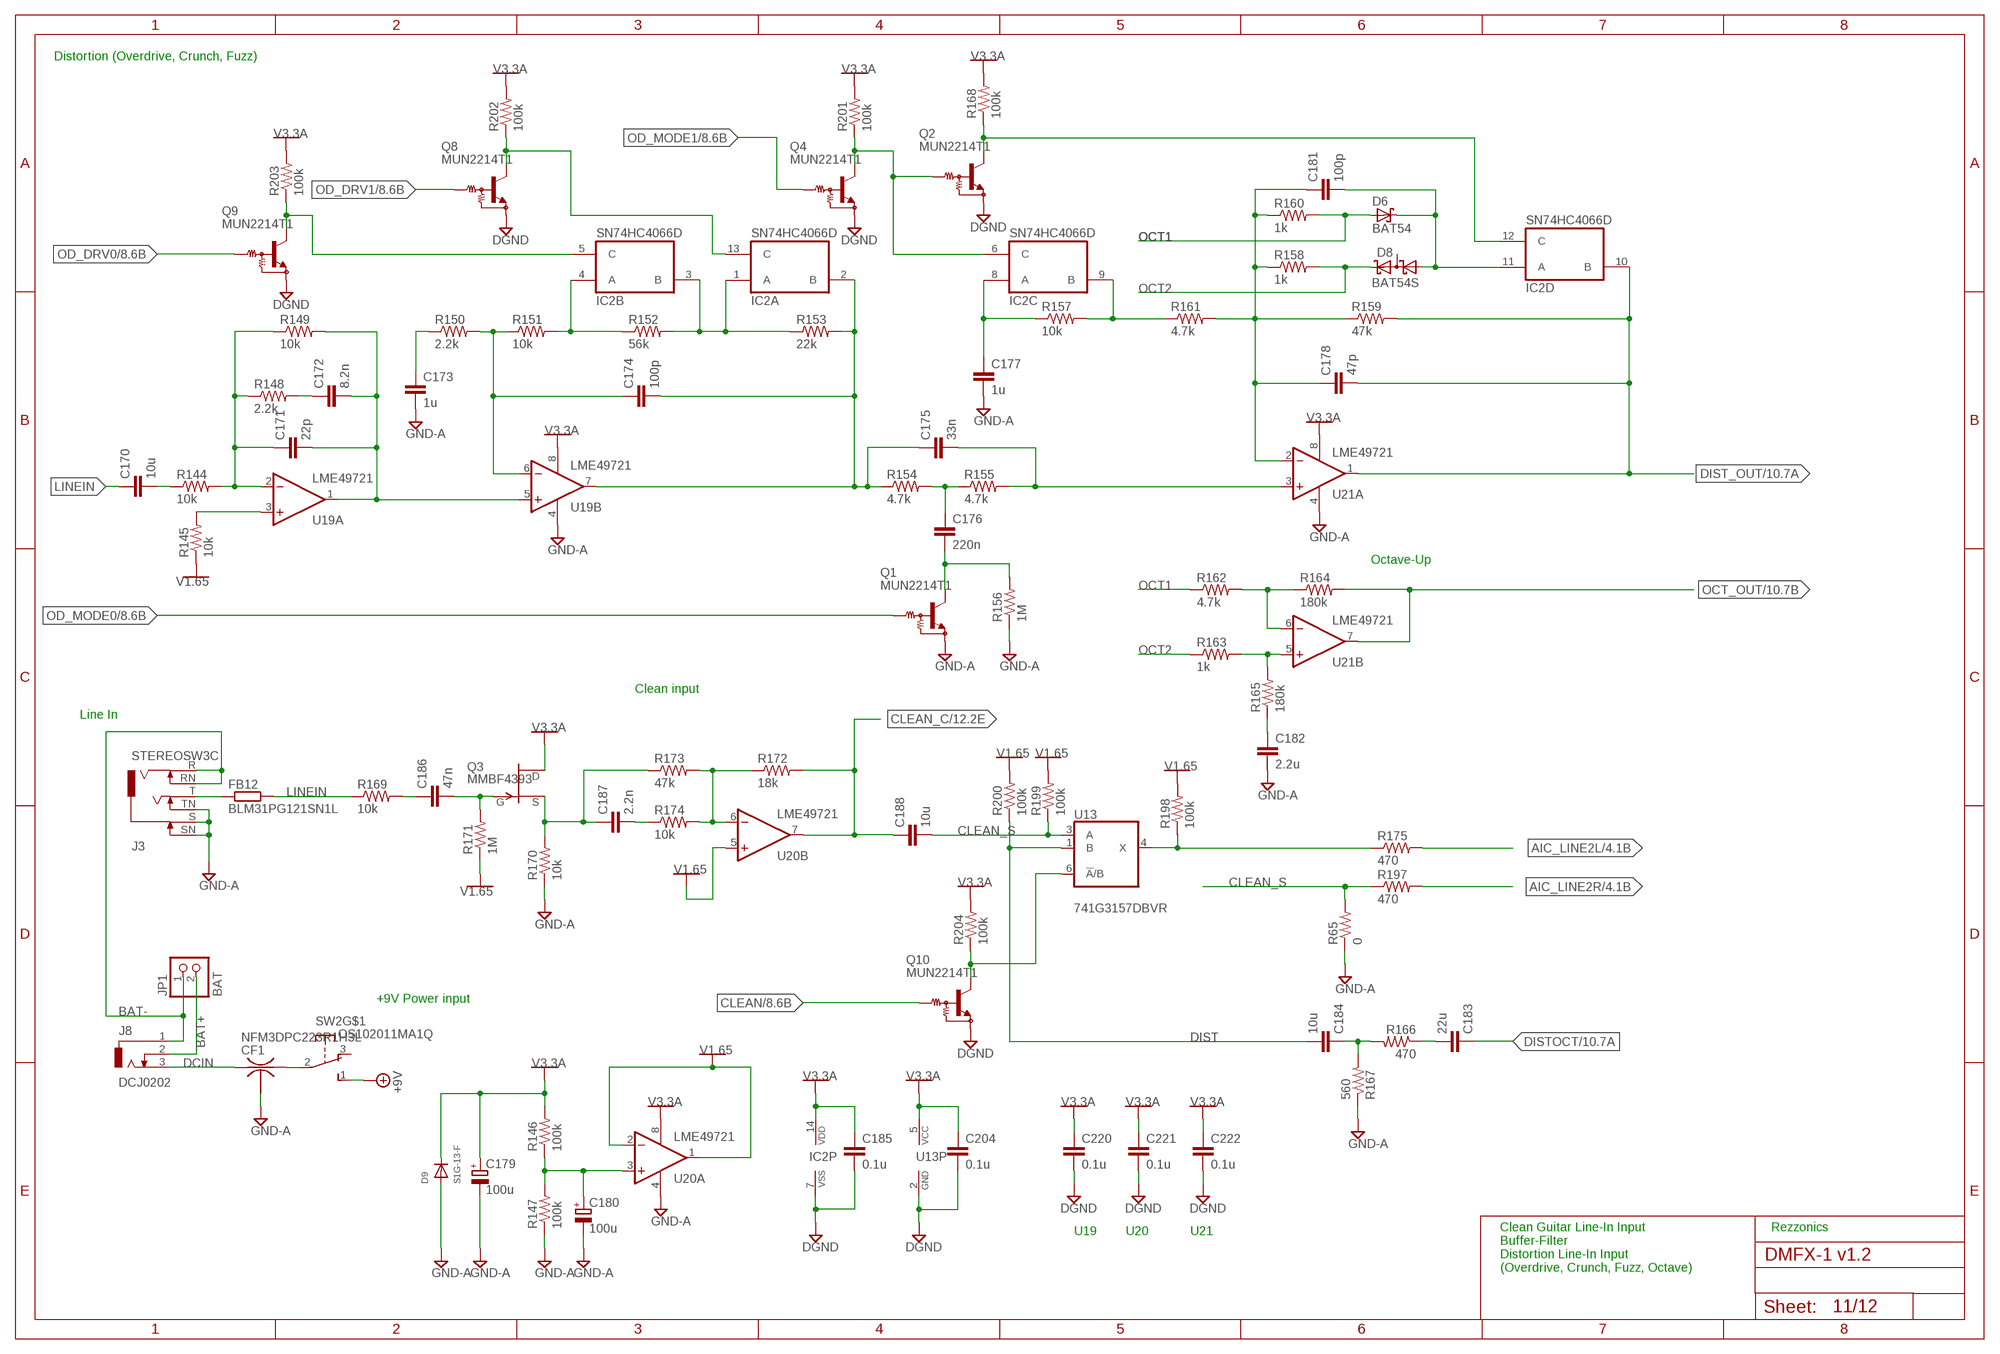
[diagram p10: schematic, sheet 11]
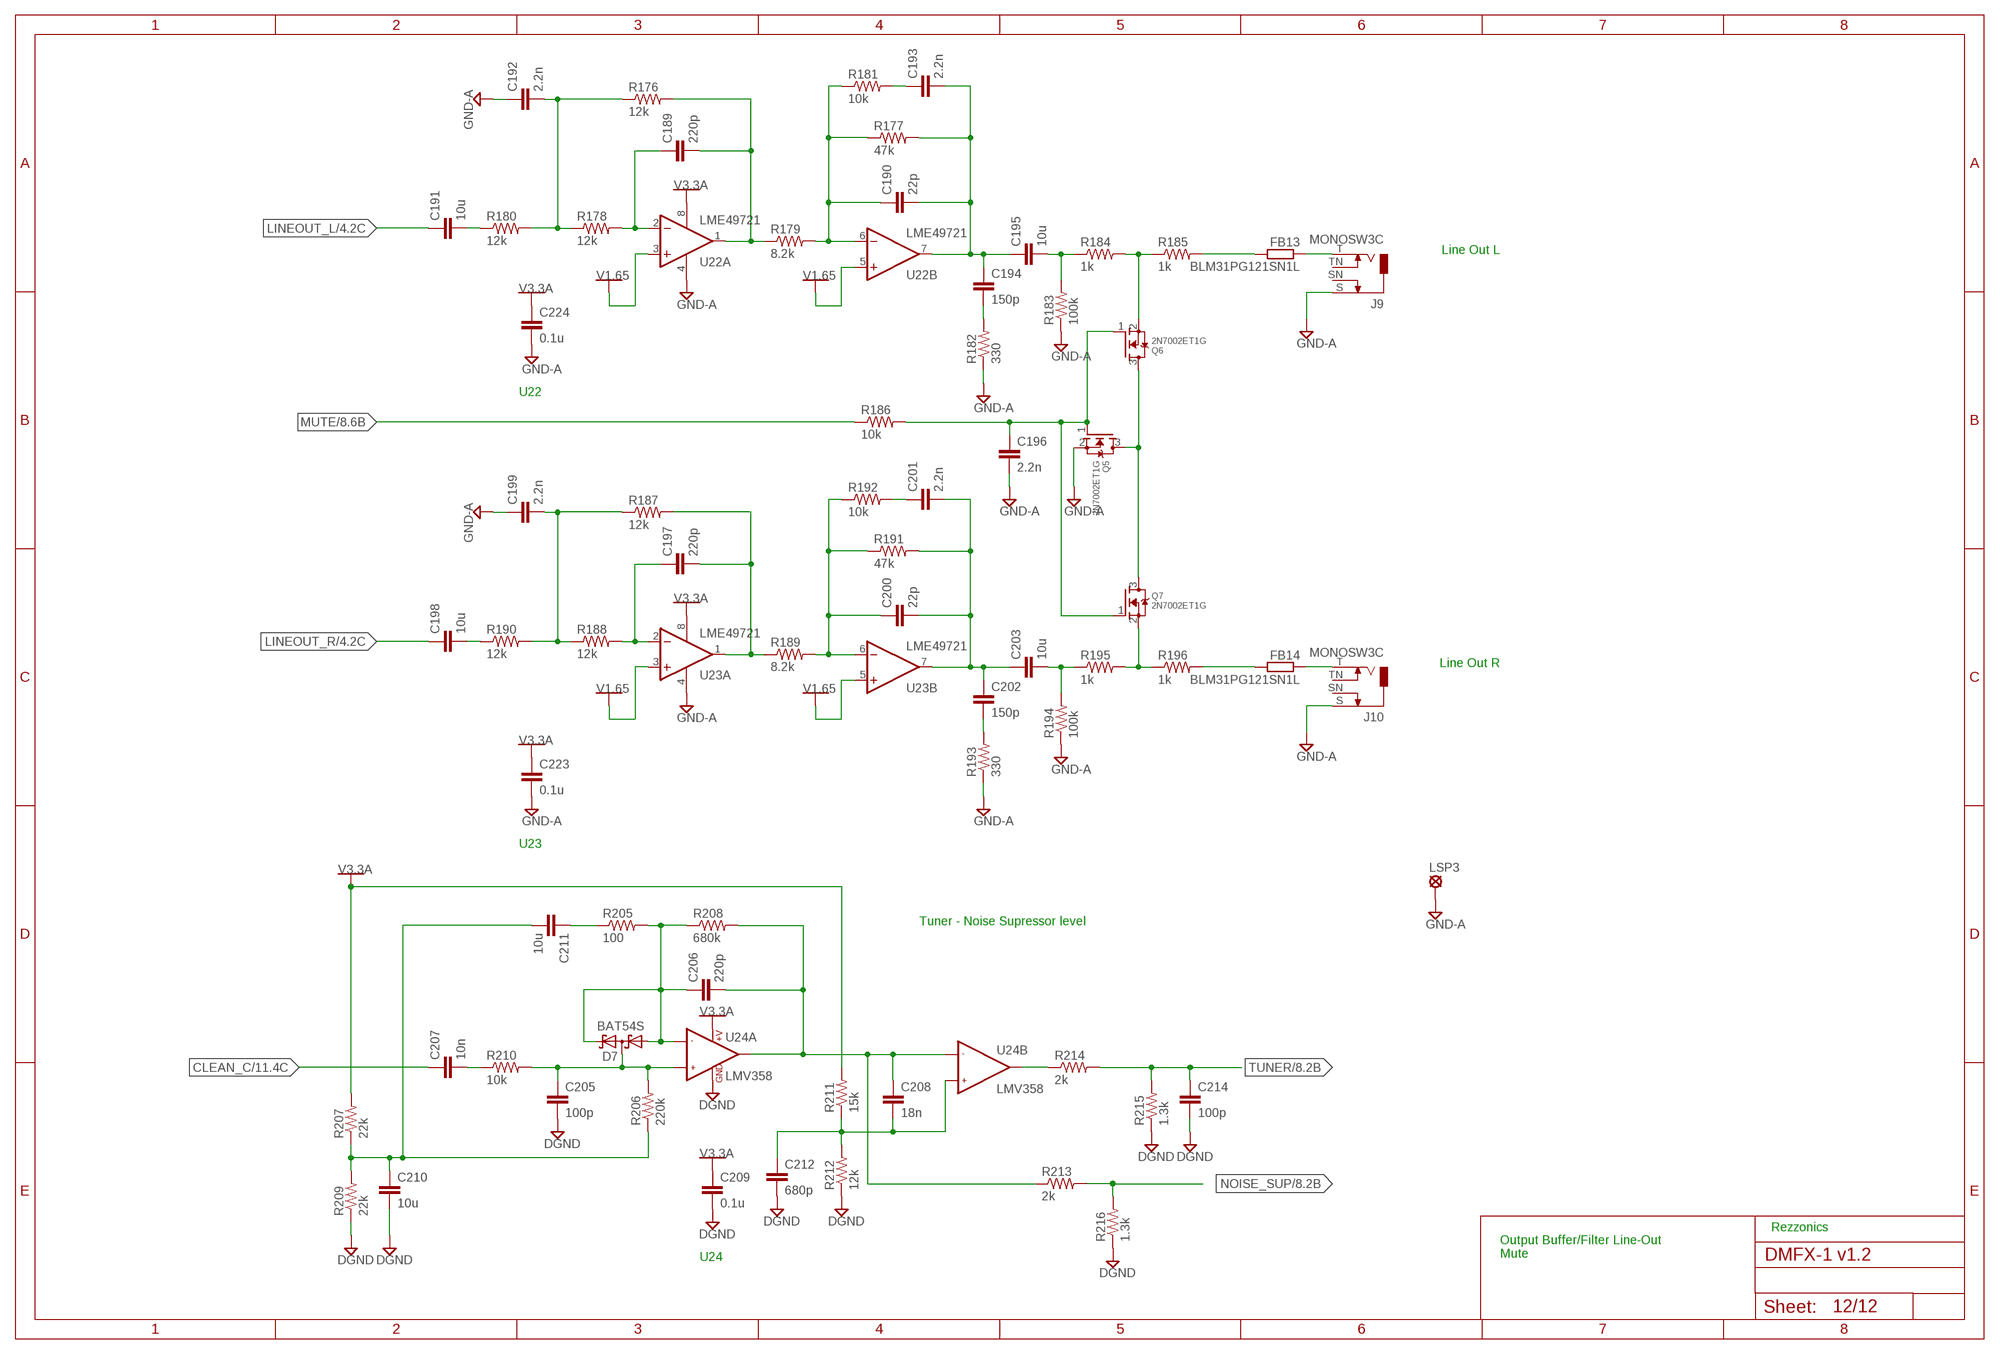
[diagram p11: schematic, sheet 12]

(export (version "E")
  (design (tool "Eeschema 10.0.6"))
  (components
    (comp (ref "C9")
      (value "10u")
      (footprint "eagle-import:C0603K")
      (fields (field (name "MPN") "GRM188R61C106MA73D"))
      (libsource (lib "eagle-import") (part "C-EUC0603K"))
    )
    (comp (ref "C10")
      (value "10u")
      (footprint "eagle-import:C0603K")
      (fields (field (name "MPN") "GRM188R61C106MA73D"))
      (libsource (lib "eagle-import") (part "C-EUC0603K"))
    )
    (comp (ref "C15")
      (value "0.1u")
      (footprint "eagle-import:C0402K")
      (fields (field (name "MPN") "GRM155R71C104JA88D"))
      (libsource (lib "eagle-import") (part "resistor_C-EUC0402K"))
    )
    (comp (ref "C21")
      (value "0.1u")
      (footprint "eagle-import:C0402K")
      (fields (field (name "MPN") "GRM155R71C104JA88D"))
      (libsource (lib "eagle-import") (part "resistor_C-EUC0402K"))
    )
    (comp (ref "C81")
      (value "0.1u")
      (footprint "eagle-import:C0402K")
      (fields (field (name "MPN") "GRM155R71C104JA88D"))
      (libsource (lib "eagle-import") (part "resistor_C-EUC0402K"))
    )
    (comp (ref "C81-2")
      (value "0.1u")
      (footprint "eagle-import:C0402K")
      (fields (field (name "MPN") "GRM155R71C104JA88D"))
      (libsource (lib "eagle-import") (part "resistor_C-EUC0402K"))
    )
    (comp (ref "C169X")
      (value "0.1u")
      (footprint "eagle-import:C0402K")
      (fields (field (name "MPN") "GRM155R71C104JA88D"))
      (libsource (lib "eagle-import") (part "resistor_C-EUC0402K"))
    )
    (comp (ref "J6")
      (value "DM3BT-DSF-PEJS")
      (footprint "eagle-import:MICROSD_RBT")
      (libsource (lib "eagle-import") (part "SDMMCRBT"))
    )
    (comp (ref "J11")
      (value "DM3BT-DSF-PEJS")
      (footprint "eagle-import:MICROSD_RBT")
      (libsource (lib "eagle-import") (part "SDMMCRBT"))
    )
    (comp (ref "R1")
      (value "10k")
      (footprint "eagle-import:0402-RES")
      (fields (field (name "MPN") "ERJ-2RKF1002X"))
      (libsource (lib "eagle-import") (part "RESISTOR0402-RES"))
    )
    (comp (ref "R2")
      (value "10k")
      (footprint "eagle-import:0402-RES")
      (fields (field (name "MPN") "ERJ-2RKF1002X"))
      (libsource (lib "eagle-import") (part "RESISTOR0402-RES"))
    )
    (comp (ref "R3")
      (value "10k")
      (footprint "eagle-import:0402-RES")
      (fields (field (name "MPN") "ERJ-2RKF1002X"))
      (libsource (lib "eagle-import") (part "RESISTOR0402-RES"))
    )
    (comp (ref "R4")
      (value "10k")
      (footprint "eagle-import:0402-RES")
      (fields (field (name "MPN") "ERJ-2RKF1002X"))
      (libsource (lib "eagle-import") (part "RESISTOR0402-RES"))
    )
    (comp (ref "R6")
      (value "NC")
      (footprint "eagle-import:0402-RES")
      (libsource (lib "eagle-import") (part "RESISTOR0402-RES"))
    )
    (comp (ref "R7")
      (value "10k")
      (footprint "eagle-import:0402-RES")
      (fields (field (name "MPN") "ERJ-2RKF1002X"))
      (libsource (lib "eagle-import") (part "RESISTOR0402-RES"))
    )
    (comp (ref "R11")
      (value "10k")
      (footprint "eagle-import:0402-RES")
      (fields (field (name "MPN") "ERJ-2RKF1002X"))
      (libsource (lib "eagle-import") (part "RESISTOR0402-RES"))
    )
    (comp (ref "R16")
      (value "10k")
      (footprint "eagle-import:0402-RES")
      (fields (field (name "MPN") "ERJ-2RKF1002X"))
      (libsource (lib "eagle-import") (part "RESISTOR0402-RES"))
    )
    (comp (ref "R26")
      (value "0")
      (footprint "eagle-import:0402-RES")
      (fields (field (name "MPN") "ERJ-2GE0R00X"))
      (libsource (lib "eagle-import") (part "RESISTOR0402-RES"))
    )
    (comp (ref "R31")
      (value "0")
      (footprint "eagle-import:0402-RES")
      (fields (field (name "MPN") "ERJ-2GE0R00X"))
      (libsource (lib "eagle-import") (part "RESISTOR0402-RES"))
    )
    (comp (ref "R50")
      (value "10k")
      (footprint "eagle-import:0402-RES")
      (fields (field (name "MPN") "ERJ-2RKF1002X"))
      (libsource (lib "eagle-import") (part "RESISTOR0402-RES"))
    )
    (comp (ref "R50-2")
      (value "10k")
      (footprint "eagle-import:0402-RES")
      (fields (field (name "MPN") "ERJ-2RKF1002X"))
      (libsource (lib "eagle-import") (part "RESISTOR0402-RES"))
    )
    (comp (ref "R51")
      (value "10k")
      (footprint "eagle-import:0402-RES")
      (fields (field (name "MPN") "ERJ-2RKF1002X"))
      (libsource (lib "eagle-import") (part "RESISTOR0402-RES"))
    )
    (comp (ref "R51-2")
      (value "10k")
      (footprint "eagle-import:0402-RES")
      (fields (field (name "MPN") "ERJ-2RKF1002X"))
      (libsource (lib "eagle-import") (part "RESISTOR0402-RES"))
    )
    (comp (ref "R52")
      (value "10k")
      (footprint "eagle-import:0402-RES")
      (fields (field (name "MPN") "ERJ-2RKF1002X"))
      (libsource (lib "eagle-import") (part "RESISTOR0402-RES"))
    )
    (comp (ref "R52-1")
      (value "10k")
      (footprint "eagle-import:0402-RES")
      (fields (field (name "MPN") "ERJ-2RKF1002X"))
      (libsource (lib "eagle-import") (part "RESISTOR0402-RES"))
    )
    (comp (ref "R52-2")
      (value "10k")
      (footprint "eagle-import:0402-RES")
      (fields (field (name "MPN") "ERJ-2RKF1002X"))
      (libsource (lib "eagle-import") (part "RESISTOR0402-RES"))
    )
    (comp (ref "R72")
      (value "NC")
      (footprint "eagle-import:0402-RES")
      (libsource (lib "eagle-import") (part "RESISTOR0402-RES"))
    )
    (comp (ref "R72-2")
      (value "NC")
      (footprint "eagle-import:0402-RES")
      (libsource (lib "eagle-import") (part "RESISTOR0402-RES"))
    )
    (comp (ref "R73")
      (value "NC")
      (footprint "eagle-import:0402-RES")
      (libsource (lib "eagle-import") (part "RESISTOR0402-RES"))
    )
    (comp (ref "R73-2")
      (value "NC")
      (footprint "eagle-import:0402-RES")
      (libsource (lib "eagle-import") (part "RESISTOR0402-RES"))
    )
    (comp (ref "R98")
      (value "10k")
      (footprint "eagle-import:0402-RES")
      (fields (field (name "MPN") "ERJ-2RKF1002X"))
      (libsource (lib "eagle-import") (part "RESISTOR0402-RES"))
    )
    (comp (ref "R99")
      (value "10k")
      (footprint "eagle-import:0402-RES")
      (fields (field (name "MPN") "ERJ-2RKF1002X"))
      (libsource (lib "eagle-import") (part "RESISTOR0402-RES"))
    )
    (comp (ref "R100")
      (value "10k")
      (footprint "eagle-import:0402-RES")
      (fields (field (name "MPN") "ERJ-2RKF1002X"))
      (libsource (lib "eagle-import") (part "RESISTOR0402-RES"))
    )
    (comp (ref "R101")
      (value "NC")
      (footprint "eagle-import:0402-RES")
      (libsource (lib "eagle-import") (part "RESISTOR0402-RES"))
    )
    (comp (ref "R102")
      (value "10k")
      (footprint "eagle-import:0402-RES")
      (fields (field (name "MPN") "ERJ-2RKF1002X"))
      (libsource (lib "eagle-import") (part "RESISTOR0402-RES"))
    )
    (comp (ref "R103")
      (value "10k")
      (footprint "eagle-import:0402-RES")
      (fields (field (name "MPN") "ERJ-2RKF1002X"))
      (libsource (lib "eagle-import") (part "RESISTOR0402-RES"))
    )
    (comp (ref "R109")
      (value "10k")
      (footprint "eagle-import:0402-RES")
      (fields (field (name "MPN") "ERJ-2RKF1002X"))
      (libsource (lib "eagle-import") (part "RESISTOR0402-RES"))
    )
    (comp (ref "R143X")
      (value "NC")
      (footprint "eagle-import:0402-RES")
      (libsource (lib "eagle-import") (part "RESISTOR0402-RES"))
    )
    (comp (ref "U9")
      (value "W25Q64FVSFIG")
      (footprint "eagle-import:SO16L")
      (libsource (lib "eagle-import") (part "SPI_FLASH-X25XX"))
    )
    (comp (ref "U9-2")
      (value "W25Q64FVSFIG")
      (footprint "eagle-import:SO16L")
      (libsource (lib "eagle-import") (part "SPI_FLASH-X25XX"))
    )
    (comp (ref "U10X")
      (value "24C64SM")
      (footprint "eagle-import:SO-08M")
      (fields
        (field (name "MF") "RAMTRON INTERNATIONAL CORP")
        (field (name "MPN") "FM24C64-S")
        (field (name "MPN_1") "AT24C64D-SSHM-T")
      )
      (libsource (lib "eagle-import") (part "24SMC64"))
    )
    (comp (ref "C1")
      (value "10u")
      (footprint "eagle-import:C0603K")
      (fields (field (name "MPN") "GRM188R61C106MA73D"))
      (libsource (lib "eagle-import") (part "C-EUC0603K"))
    )
    (comp (ref "C2")
      (value "1u")
      (footprint "eagle-import:C0402K")
      (fields (field (name "MPN") "GRM155R70J105KA12D"))
      (libsource (lib "eagle-import") (part "resistor_C-EUC0402K"))
    )
    (comp (ref "C3")
      (value "10u")
      (footprint "eagle-import:C0603K")
      (fields (field (name "MPN") "GRM188R61C106MA73D"))
      (libsource (lib "eagle-import") (part "C-EUC0603K"))
    )
    (comp (ref "C4")
      (value "10u")
      (footprint "eagle-import:C0603K")
      (fields (field (name "MPN") "GRM188R61C106MA73D"))
      (libsource (lib "eagle-import") (part "C-EUC0603K"))
    )
    (comp (ref "C5")
      (value "1u")
      (footprint "eagle-import:C0402K")
      (fields (field (name "MPN") "GRM155R70J105KA12D"))
      (libsource (lib "eagle-import") (part "resistor_C-EUC0402K"))
    )
    (comp (ref "C28")
      (value "0.1u")
      (footprint "eagle-import:C0402K")
      (fields (field (name "MPN") "GRM155R71C104JA88D"))
      (libsource (lib "eagle-import") (part "resistor_C-EUC0402K"))
    )
    (comp (ref "C29")
      (value "0.1u")
      (footprint "eagle-import:C0402K")
      (fields (field (name "MPN") "GRM155R71C104JA88D"))
      (libsource (lib "eagle-import") (part "resistor_C-EUC0402K"))
    )
    (comp (ref "C30")
      (value "0.1u")
      (footprint "eagle-import:C0402K")
      (fields (field (name "MPN") "GRM155R71C104JA88D"))
      (libsource (lib "eagle-import") (part "resistor_C-EUC0402K"))
    )
    (comp (ref "C32")
      (value "0.1u")
      (footprint "eagle-import:0402")
      (fields (field (name "MPN") "GRM155R71C104JA88D"))
      (libsource (lib "eagle-import") (part "C0402_BGA"))
    )
    (comp (ref "C38")
      (value "10n")
      (footprint "eagle-import:0402")
      (fields (field (name "MPN") "GRM155R71E103KA01D"))
      (libsource (lib "eagle-import") (part "C0402_BGA"))
    )
    (comp (ref "C40")
      (value "0.1u")
      (footprint "eagle-import:0402")
      (fields (field (name "MPN") "GRM155R71C104JA88D"))
      (libsource (lib "eagle-import") (part "C0402_BGA"))
    )
    (comp (ref "C41")
      (value "10n")
      (footprint "eagle-import:0402")
      (fields (field (name "MPN") "GRM155R71E103KA01D"))
      (libsource (lib "eagle-import") (part "C0402_BGA"))
    )
    (comp (ref "C42")
      (value "1u")
      (footprint "eagle-import:0402")
      (fields (field (name "MPN") "GRM155R70J105KA12D"))
      (libsource (lib "eagle-import") (part "C0402_BGA"))
    )
    (comp (ref "C43")
      (value "10n")
      (footprint "eagle-import:0402")
      (fields (field (name "MPN") "GRM155R71E103KA01D"))
      (libsource (lib "eagle-import") (part "C0402_BGA"))
    )
    (comp (ref "C45")
      (value "0.1u")
      (footprint "eagle-import:0402")
      (fields (field (name "MPN") "GRM155R71C104JA88D"))
      (libsource (lib "eagle-import") (part "C0402_BGA"))
    )
    (comp (ref "C46")
      (value "0.1u")
      (footprint "eagle-import:0402")
      (fields (field (name "MPN") "GRM155R71C104JA88D"))
      (libsource (lib "eagle-import") (part "C0402_BGA"))
    )
    (comp (ref "C48")
      (value "0.1u")
      (footprint "eagle-import:0402")
      (fields (field (name "MPN") "GRM155R71C104JA88D"))
      (libsource (lib "eagle-import") (part "C0402_BGA"))
    )
    (comp (ref "C49")
      (value "0.1u")
      (footprint "eagle-import:0402")
      (fields (field (name "MPN") "GRM155R71C104JA88D"))
      (libsource (lib "eagle-import") (part "C0402_BGA"))
    )
    (comp (ref "C50")
      (value "1n")
      (footprint "eagle-import:0402")
      (fields (field (name "MPN") "GRM155R71H102JA01J"))
      (libsource (lib "eagle-import") (part "C0402_BGA"))
    )
    (comp (ref "C51")
      (value "10n")
      (footprint "eagle-import:0402")
      (fields (field (name "MPN") "GRM155R71E103KA01D"))
      (libsource (lib "eagle-import") (part "C0402_BGA"))
    )
    (comp (ref "C52")
      (value "1u")
      (footprint "eagle-import:0402")
      (fields (field (name "MPN") "GRM155R70J105KA12D"))
      (libsource (lib "eagle-import") (part "C0402_BGA"))
    )
    (comp (ref "C53")
      (value "1u")
      (footprint "eagle-import:0402")
      (fields (field (name "MPN") "GRM155R70J105KA12D"))
      (libsource (lib "eagle-import") (part "C0402_BGA"))
    )
    (comp (ref "C54")
      (value "1u")
      (footprint "eagle-import:0402")
      (fields (field (name "MPN") "GRM155R70J105KA12D"))
      (libsource (lib "eagle-import") (part "C0402_BGA"))
    )
    (comp (ref "C55")
      (value "10n")
      (footprint "eagle-import:0402")
      (fields (field (name "MPN") "GRM155R71E103KA01D"))
      (libsource (lib "eagle-import") (part "C0402_BGA"))
    )
    (comp (ref "C56")
      (value "1n")
      (footprint "eagle-import:0402")
      (fields (field (name "MPN") "GRM155R71H102JA01J"))
      (libsource (lib "eagle-import") (part "C0402_BGA"))
    )
    (comp (ref "C57")
      (value "0.1u")
      (footprint "eagle-import:0402")
      (fields (field (name "MPN") "GRM155R71C104JA88D"))
      (libsource (lib "eagle-import") (part "C0402_BGA"))
    )
    (comp (ref "C59")
      (value "0.1u")
      (footprint "eagle-import:0402")
      (fields (field (name "MPN") "GRM155R71C104JA88D"))
      (libsource (lib "eagle-import") (part "C0402_BGA"))
    )
    (comp (ref "C60")
      (value "0.1u")
      (footprint "eagle-import:0402")
      (fields (field (name "MPN") "GRM155R71C104JA88D"))
      (libsource (lib "eagle-import") (part "C0402_BGA"))
    )
    (comp (ref "C62")
      (value "0.1u")
      (footprint "eagle-import:0402")
      (fields (field (name "MPN") "GRM155R71C104JA88D"))
      (libsource (lib "eagle-import") (part "C0402_BGA"))
    )
    (comp (ref "C63")
      (value "0.1u")
      (footprint "eagle-import:0402")
      (fields (field (name "MPN") "GRM155R71C104JA88D"))
      (libsource (lib "eagle-import") (part "C0402_BGA"))
    )
    (comp (ref "C64")
      (value "1u")
      (footprint "eagle-import:0402")
      (fields (field (name "MPN") "GRM155R70J105KA12D"))
      (libsource (lib "eagle-import") (part "C0402_BGA"))
    )
    (comp (ref "C65")
      (value "0.1u")
      (footprint "eagle-import:0402")
      (fields (field (name "MPN") "GRM155R71C104JA88D"))
      (libsource (lib "eagle-import") (part "C0402_BGA"))
    )
    (comp (ref "C67")
      (value "0.1u")
      (footprint "eagle-import:0402")
      (fields (field (name "MPN") "GRM155R71C104JA88D"))
      (libsource (lib "eagle-import") (part "C0402_BGA"))
    )
    (comp (ref "C69")
      (value "0.1u")
      (footprint "eagle-import:0402")
      (fields (field (name "MPN") "GRM155R71C104JA88D"))
      (libsource (lib "eagle-import") (part "C0402_BGA"))
    )
    (comp (ref "C71")
      (value "0.1u")
      (footprint "eagle-import:0402")
      (fields (field (name "MPN") "GRM155R71C104JA88D"))
      (libsource (lib "eagle-import") (part "C0402_BGA"))
    )
    (comp (ref "C72")
      (value "0.1u")
      (footprint "eagle-import:0402")
      (fields (field (name "MPN") "GRM155R71C104JA88D"))
      (libsource (lib "eagle-import") (part "C0402_BGA"))
    )
    (comp (ref "C73")
      (value "10n")
      (footprint "eagle-import:0402")
      (fields (field (name "MPN") "GRM155R71E103KA01D"))
      (libsource (lib "eagle-import") (part "C0402_BGA"))
    )
    (comp (ref "C74")
      (value "1n")
      (footprint "eagle-import:C0402K")
      (fields (field (name "MPN") "GRM155R71H102JA01J"))
      (libsource (lib "eagle-import") (part "resistor_C-EUC0402K"))
    )
    (comp (ref "C75")
      (value "0.1u")
      (footprint "eagle-import:0402")
      (fields (field (name "MPN") "GRM155R71C104JA88D"))
      (libsource (lib "eagle-import") (part "C0402_BGA"))
    )
    (comp (ref "C85")
      (value "0.1u")
      (footprint "eagle-import:0402")
      (fields (field (name "MPN") "GRM155R71C104JA88D"))
      (libsource (lib "eagle-import") (part "C0402_BGA"))
    )
    (comp (ref "C86")
      (value "1u")
      (footprint "eagle-import:0402")
      (fields (field (name "MPN") "GRM155R70J105KA12D"))
      (libsource (lib "eagle-import") (part "C0402_BGA"))
    )
    (comp (ref "C87")
      (value "0.1u")
      (footprint "eagle-import:0402")
      (fields (field (name "MPN") "GRM155R71C104JA88D"))
      (libsource (lib "eagle-import") (part "C0402_BGA"))
    )
    (comp (ref "C88")
      (value "0.1u")
      (footprint "eagle-import:0402")
      (fields (field (name "MPN") "GRM155R71C104JA88D"))
      (libsource (lib "eagle-import") (part "C0402_BGA"))
    )
    (comp (ref "C89")
      (value "10n")
      (footprint "eagle-import:C0402K")
      (fields (field (name "MPN") "GRM155R71E103KA01D"))
      (libsource (lib "eagle-import") (part "resistor_C-EUC0402K"))
    )
    (comp (ref "FB1")
      (value "BLM18AG601SN1D")
      (footprint "eagle-import:0603")
      (libsource (lib "eagle-import") (part "INDUCTOR0603"))
    )
    (comp (ref "FB4")
      (value "BLM18AG601SN1D")
      (footprint "eagle-import:0603")
      (libsource (lib "eagle-import") (part "INDUCTOR0603"))
    )
    (comp (ref "FB5")
      (value "BLM18AG601SN1D")
      (footprint "eagle-import:0603")
      (libsource (lib "eagle-import") (part "INDUCTOR0603"))
    )
    (comp (ref "FB6")
      (value "BLM18AG601SN1D")
      (footprint "eagle-import:0603")
      (libsource (lib "eagle-import") (part "INDUCTOR0603"))
    )
    (comp (ref "L3")
      (value "BLM18AG601SN1D")
      (footprint "eagle-import:0603")
      (libsource (lib "eagle-import") (part "INDUCTOR0603"))
    )
    (comp (ref "R60")
      (value "0")
      (footprint "eagle-import:0402-RES")
      (fields (field (name "MPN") "ERJ-2GE0R00X"))
      (libsource (lib "eagle-import") (part "RESISTOR0402-RES"))
    )
    (comp (ref "R61")
      (value "0")
      (footprint "eagle-import:0402-RES")
      (fields (field (name "MPN") "ERJ-2GE0R00X"))
      (libsource (lib "eagle-import") (part "RESISTOR0402-RES"))
    )
    (comp (ref "R62")
      (value "NC")
      (footprint "eagle-import:0402-RES")
      (libsource (lib "eagle-import") (part "RESISTOR0402-RES"))
    )
    (comp (ref "R63")
      (value "NC")
      (footprint "eagle-import:0402-RES")
      (libsource (lib "eagle-import") (part "RESISTOR0402-RES"))
    )
    (comp (ref "R64")
      (value "0")
      (footprint "eagle-import:0402-RES")
      (fields (field (name "MPN") "ERJ-2GE0R00X"))
      (libsource (lib "eagle-import") (part "RESISTOR0402-RES"))
    )
    (comp (ref "R97")
      (value "0")
      (footprint "eagle-import:0805")
      (fields (field (name "MPN") "ERJ-2GE0R00X"))
      (libsource (lib "eagle-import") (part "RESISTOR0805-RES"))
    )
    (comp (ref "R121")
      (value "NC")
      (footprint "eagle-import:0805")
      (libsource (lib "eagle-import") (part "RESISTOR0805-RES"))
    )
    (comp (ref "R122")
      (value "0")
      (footprint "eagle-import:0805")
      (fields (field (name "MPN") "ERJ-6GEY0R00V"))
      (libsource (lib "eagle-import") (part "RESISTOR0805-RES"))
    )
    (comp (ref "R124")
      (value "0")
      (footprint "eagle-import:0805")
      (fields (field (name "MPN") "ERJ-6GEY0R00V"))
      (libsource (lib "eagle-import") (part "RESISTOR0805-RES"))
    )
    (comp (ref "U4")
      (value "TMS320C5535")
      (footprint "eagle-import:PBGA144")
      (fields (field (name "MPN") "TMS320C5535AZHH10"))
      (libsource (lib "eagle-import") (part "TMS320C5535S-PBGA-N144"))
    )
    (comp (ref "C6-2")
      (value "10u")
      (footprint "eagle-import:C0603K")
      (fields (field (name "MPN") "GRM188R61C106MA73D"))
      (libsource (lib "eagle-import") (part "C-EUC0603K"))
    )
    (comp (ref "C24-2")
      (value "0.1u")
      (footprint "eagle-import:C0402K")
      (fields (field (name "MPN") "GRM155R71C104JA88D"))
      (libsource (lib "eagle-import") (part "resistor_C-EUC0402K"))
    )
    (comp (ref "C25-2")
      (value "10u")
      (footprint "eagle-import:C0603K")
      (fields (field (name "MPN") "GRM188R61C106MA73D"))
      (libsource (lib "eagle-import") (part "C-EUC0603K"))
    )
    (comp (ref "C66-2")
      (value "1n")
      (footprint "eagle-import:0402")
      (fields (field (name "MPN") "GRM155R71H102JA01J"))
      (libsource (lib "eagle-import") (part "C0402_BGA"))
    )
    (comp (ref "C77-2")
      (value "0.1u")
      (footprint "eagle-import:C0402K")
      (fields (field (name "MPN") "GRM155R71C104JA88D"))
      (libsource (lib "eagle-import") (part "resistor_C-EUC0402K"))
    )
    (comp (ref "C82-2")
      (value "0.1u")
      (footprint "eagle-import:0402")
      (fields (field (name "MPN") "GRM155R71C104JA88D"))
      (libsource (lib "eagle-import") (part "C0402_BGA"))
    )
    (comp (ref "C83-2")
      (value "1u")
      (footprint "eagle-import:0402")
      (fields (field (name "MPN") "GRM155R70J105KA12D"))
      (libsource (lib "eagle-import") (part "C0402_BGA"))
    )
    (comp (ref "C84-2")
      (value "0.1u")
      (footprint "eagle-import:0402")
      (fields (field (name "MPN") "GRM155R71C104JA88D"))
      (libsource (lib "eagle-import") (part "C0402_BGA"))
    )
    (comp (ref "C90-2")
      (value "10p")
      (footprint "eagle-import:C0402K")
      (fields (field (name "MPN") "GRM1555C1H100FA01D"))
      (libsource (lib "eagle-import") (part "resistor_C-EUC0402K"))
    )
    (comp (ref "C91-2")
      (value "10p")
      (footprint "eagle-import:C0402K")
      (fields (field (name "MPN") "GRM1555C1H100FA01D"))
      (libsource (lib "eagle-import") (part "resistor_C-EUC0402K"))
    )
    (comp (ref "D2-2")
      (value "6.2V")
      (footprint "eagle-import:SMADIODE")
      (fields (field (name "MPN") "1SMA5920BT3G") (field (name "PART_NUMBER") "SMAZ6V2-13-F"))
      (libsource (lib "eagle-import") (part "DIODESMA"))
    )
    (comp (ref "D3X")
      (value "GREEN")
      (footprint "eagle-import:CHIPLED_0603")
      (fields (field (name "MPN") "LTST-C190KGKT"))
      (libsource (lib "eagle-import") (part "LEDCHIPLED_0603"))
    )
    (comp (ref "FB7-2")
      (value "BLM18AG601SN1D")
      (footprint "eagle-import:0805")
      (fields (field (name "MPN") "BLM21AG151SN1D"))
      (libsource (lib "eagle-import") (part "INDUCTOR0805"))
    )
    (comp (ref "J1-2")
      (value "USB-MINIB-5PIN")
      (footprint "eagle-import:USB-MINIB")
      (fields (field (name "MPN") "10033526-N3212LF"))
      (libsource (lib "eagle-import") (part "USB-MINIB-5PIN"))
    )
    (comp (ref "R13-2")
      (value "10k")
      (footprint "eagle-import:0402-RES")
      (fields (field (name "MPN") "ERJ-2RKF1002X"))
      (libsource (lib "eagle-import") (part "RESISTOR0402-RES"))
    )
    (comp (ref "R14-2")
      (value "10k")
      (footprint "eagle-import:0402-RES")
      (fields (field (name "MPN") "ERJ-2RKF1002X"))
      (libsource (lib "eagle-import") (part "RESISTOR0402-RES"))
    )
    (comp (ref "R18-2")
      (value "100k")
      (footprint "eagle-import:0402-RES")
      (fields (field (name "MPN") "ERJ-2RKF1003X"))
      (libsource (lib "eagle-import") (part "RESISTOR0402-RES"))
    )
    (comp (ref "R29-2")
      (value "10k")
      (footprint "eagle-import:0402")
      (fields
        (field (name "MANUFACTURER_PART_NUMBER") "CRCW04021K00FKED")
        (field (name "POWER") "0.063")
        (field (name "TOLERANCE") "1.0")
        (field (name "MPN") "ERJ-2RKF1002X")
        (field (name "TOLERANCE_1") "1%")
      )
      (libsource (lib "eagle-import") (part "CRCW04021K00FKED"))
    )
    (comp (ref "R33-2")
      (value "10k")
      (footprint "eagle-import:0402-RES")
      (fields (field (name "MPN") "ERJ-2RKF1002X"))
      (libsource (lib "eagle-import") (part "RESISTOR0402-RES"))
    )
    (comp (ref "R34-2")
      (value "NC")
      (footprint "eagle-import:0402")
      (fields
        (field (name "MANUFACTURER_PART_NUMBER") "CRCW04021K00FKED")
        (field (name "POWER") "0.063")
        (field (name "TOLERANCE") "1.0")
      )
      (libsource (lib "eagle-import") (part "CRCW04021K00FKED"))
    )
    (comp (ref "R37-2")
      (value "100k")
      (footprint "eagle-import:0402-RES")
      (fields (field (name "MPN") "ERJ-2RKF1003X"))
      (libsource (lib "eagle-import") (part "RESISTOR0402-RES"))
    )
    (comp (ref "R38-2")
      (value "0")
      (footprint "eagle-import:0402")
      (fields
        (field (name "MANUFACTURER_PART_NUMBER") "CRCW04021K00FKED")
        (field (name "POWER") "0.063")
        (field (name "TOLERANCE") "1.0")
      )
      (libsource (lib "eagle-import") (part "CRCW04021K00FKED"))
    )
    (comp (ref "R41-2")
      (value "100k")
      (footprint "eagle-import:0402-RES")
      (fields (field (name "MPN") "ERJ-2RKF1003X"))
      (libsource (lib "eagle-import") (part "RESISTOR0402-RES"))
    )
    (comp (ref "R54-2")
      (value "0")
      (footprint "eagle-import:0402")
      (fields
        (field (name "MANUFACTURER_PART_NUMBER") "CRCW04021K00FKED")
        (field (name "POWER") "0.063")
        (field (name "TOLERANCE") "1.0")
      )
      (libsource (lib "eagle-import") (part "CRCW04021K00FKED"))
    )
    (comp (ref "R55-2")
      (value "0")
      (footprint "eagle-import:0402-RES")
      (fields (field (name "MPN") "ERJ-2GE0R00X"))
      (libsource (lib "eagle-import") (part "RESISTOR0402-RES"))
    )
    (comp (ref "R56-2")
      (value "NC")
      (footprint "eagle-import:0402-RES")
      (libsource (lib "eagle-import") (part "RESISTOR0402-RES"))
    )
    (comp (ref "R59-2")
      (value "10k")
      (footprint "eagle-import:0402-RES")
      (fields (field (name "MPN") "ERJ-2RKF1002X"))
      (libsource (lib "eagle-import") (part "RESISTOR0402-RES"))
    )
    (comp (ref "R66X")
      (value "33")
      (footprint "eagle-import:0402-RES")
      (fields (field (name "MPN") "ERJ-2RKF33R0X"))
      (libsource (lib "eagle-import") (part "RESISTOR0402-RES"))
    )
    (comp (ref "R76X")
      (value "220")
      (footprint "eagle-import:0402-RES")
      (fields (field (name "MPN") "ERJ-2RKF2200X"))
      (libsource (lib "eagle-import") (part "RESISTOR0402-RES"))
    )
    (comp (ref "R83X")
      (value "0")
      (footprint "eagle-import:0402")
      (fields
        (field (name "MANUFACTURER_PART_NUMBER") "CRCW04021K00FKED")
        (field (name "POWER") "0.063")
        (field (name "TOLERANCE") "1.0")
      )
      (libsource (lib "eagle-import") (part "CRCW04021K00FKED"))
    )
    (comp (ref "R105X")
      (value "0")
      (footprint "eagle-import:0402-RES")
      (fields (field (name "MPN") "ERJ-2GE0R00X"))
      (libsource (lib "eagle-import") (part "RESISTOR0402-RES"))
    )
    (comp (ref "R117-2")
      (value "10k")
      (footprint "eagle-import:0402-RES")
      (fields (field (name "MPN") "ERJ-2RKF1002X"))
      (libsource (lib "eagle-import") (part "RESISTOR0402-RES"))
    )
    (comp (ref "TP4-2")
      (value "TPTP06R")
      (footprint "eagle-import:TP06R")
      (fields (field (name "TP_SIGNAL_NAME") "CLKOUT2"))
      (libsource (lib "eagle-import") (part "TPTP06R"))
    )
    (comp (ref "TP8X")
      (value "TPTP06R")
      (footprint "eagle-import:TP06R")
      (fields (field (name "TP_SIGNAL_NAME") "RTC_CLKOUT2"))
      (libsource (lib "eagle-import") (part "TPTP06R"))
    )
    (comp (ref "TP23X")
      (value "TPTP06R")
      (footprint "eagle-import:TP06R")
      (libsource (lib "eagle-import") (part "TPTP06R"))
    )
    (comp (ref "TP24X")
      (value "TPTP06R")
      (footprint "eagle-import:TP06R")
      (libsource (lib "eagle-import") (part "TPTP06R"))
    )
    (comp (ref "TP25X")
      (value "TPTP06R")
      (footprint "eagle-import:TP06R")
      (libsource (lib "eagle-import") (part "TPTP06R"))
    )
    (comp (ref "TP26X")
      (value "TPTP06R")
      (footprint "eagle-import:TP06R")
      (libsource (lib "eagle-import") (part "TPTP06R"))
    )
    (comp (ref "TP27X")
      (value "TPTP06R")
      (footprint "eagle-import:TP06R")
      (libsource (lib "eagle-import") (part "TPTP06R"))
    )
    (comp (ref "TP28X")
      (value "TPTP06R")
      (footprint "eagle-import:TP06R")
      (libsource (lib "eagle-import") (part "TPTP06R"))
    )
    (comp (ref "TP29X")
      (value "TPTP06R")
      (footprint "eagle-import:TP06R")
      (libsource (lib "eagle-import") (part "TPTP06R"))
    )
    (comp (ref "TP30X")
      (value "TPTP06R")
      (footprint "eagle-import:TP06R")
      (libsource (lib "eagle-import") (part "TPTP06R"))
    )
    (comp (ref "TP31X")
      (value "TPTP06R")
      (footprint "eagle-import:TP06R")
      (libsource (lib "eagle-import") (part "TPTP06R"))
    )
    (comp (ref "U5")
      (value "TMS320C5535")
      (footprint "eagle-import:PBGA144")
      (fields (field (name "MPN") "TMS320C5535AZHH10"))
      (libsource (lib "eagle-import") (part "TMS320C5535S-PBGA-N144"))
    )
    (comp (ref "Y1-2")
      (value "32.768kHz")
      (footprint "eagle-import:CRYSTAL-32KHZ-SMD_EPSON_MC146")
      (fields (field (name "MPN") "SSPT7F-12.5PF20-R"))
      (libsource (lib "eagle-import") (part "CRYSTAL"))
    )
    (comp (ref "C6")
      (value "10u")
      (footprint "eagle-import:C0603K")
      (fields (field (name "MPN") "GRM188R61C106MA73D"))
      (libsource (lib "eagle-import") (part "C-EUC0603K"))
    )
    (comp (ref "C24")
      (value "0.1u")
      (footprint "eagle-import:C0402K")
      (fields (field (name "MPN") "GRM155R71C104JA88D"))
      (libsource (lib "eagle-import") (part "resistor_C-EUC0402K"))
    )
    (comp (ref "C25")
      (value "10u")
      (footprint "eagle-import:C0603K")
      (fields (field (name "MPN") "GRM188R61C106MA73D"))
      (libsource (lib "eagle-import") (part "C-EUC0603K"))
    )
    (comp (ref "C66")
      (value "1n")
      (footprint "eagle-import:0402")
      (fields (field (name "MPN") "GRM155R71H102JA01J"))
      (libsource (lib "eagle-import") (part "C0402_BGA"))
    )
    (comp (ref "C77")
      (value "0.1u")
      (footprint "eagle-import:C0402K")
      (fields (field (name "MPN") "GRM155R71C104JA88D"))
      (libsource (lib "eagle-import") (part "resistor_C-EUC0402K"))
    )
    (comp (ref "C82")
      (value "0.1u")
      (footprint "eagle-import:0402")
      (fields (field (name "MPN") "GRM155R71C104JA88D"))
      (libsource (lib "eagle-import") (part "C0402_BGA"))
    )
    (comp (ref "C83")
      (value "1u")
      (footprint "eagle-import:0402")
      (fields (field (name "MPN") "GRM155R70J105KA12D"))
      (libsource (lib "eagle-import") (part "C0402_BGA"))
    )
    (comp (ref "C84")
      (value "0.1u")
      (footprint "eagle-import:0402")
      (fields (field (name "MPN") "GRM155R71C104JA88D"))
      (libsource (lib "eagle-import") (part "C0402_BGA"))
    )
    (comp (ref "C90")
      (value "10p")
      (footprint "eagle-import:C0402K")
      (fields (field (name "MPN") "GRM1555C1H100FA01D"))
      (libsource (lib "eagle-import") (part "resistor_C-EUC0402K"))
    )
    (comp (ref "C91")
      (value "10p")
      (footprint "eagle-import:C0402K")
      (fields (field (name "MPN") "GRM1555C1H100FA01D"))
      (libsource (lib "eagle-import") (part "resistor_C-EUC0402K"))
    )
    (comp (ref "D2")
      (value "6.2V")
      (footprint "eagle-import:SMADIODE")
      (fields (field (name "MPN") "1SMA5920BT3G") (field (name "PART_NUMBER") "SMAZ6V2-13-F"))
      (libsource (lib "eagle-import") (part "DIODESMA"))
    )
    (comp (ref "DS2")
      (value "GREEN")
      (footprint "eagle-import:CHIPLED_0603")
      (fields (field (name "MPN") "LTST-C190KGKT"))
      (libsource (lib "eagle-import") (part "LEDCHIPLED_0603"))
    )
    (comp (ref "FB7")
      (value "BLM18AG601SN1D")
      (footprint "eagle-import:0805")
      (fields (field (name "MPN") "BLM21AG151SN1D"))
      (libsource (lib "eagle-import") (part "INDUCTOR0805"))
    )
    (comp (ref "J1")
      (value "USB-MINIB-5PIN")
      (footprint "eagle-import:USB-MINIB")
      (fields (field (name "MPN") "10033526-N3212LF"))
      (libsource (lib "eagle-import") (part "USB-MINIB-5PIN"))
    )
    (comp (ref "R13")
      (value "10k")
      (footprint "eagle-import:0402-RES")
      (fields (field (name "MPN") "ERJ-2RKF1002X"))
      (libsource (lib "eagle-import") (part "RESISTOR0402-RES"))
    )
    (comp (ref "R14")
      (value "10k")
      (footprint "eagle-import:0402-RES")
      (fields (field (name "MPN") "ERJ-2RKF1002X"))
      (libsource (lib "eagle-import") (part "RESISTOR0402-RES"))
    )
    (comp (ref "R17")
      (value "220")
      (footprint "eagle-import:0402-RES")
      (fields (field (name "MPN") "ERJ-2RKF2200X"))
      (libsource (lib "eagle-import") (part "RESISTOR0402-RES"))
    )
    (comp (ref "R18")
      (value "100k")
      (footprint "eagle-import:0402-RES")
      (fields (field (name "MPN") "ERJ-2RKF1003X"))
      (libsource (lib "eagle-import") (part "RESISTOR0402-RES"))
    )
    (comp (ref "R22")
      (value "10k")
      (footprint "eagle-import:0402-RES")
      (fields (field (name "MPN") "ERJ-2RKF1002X"))
      (libsource (lib "eagle-import") (part "RESISTOR0402-RES"))
    )
    (comp (ref "R25")
      (value "10k")
      (footprint "eagle-import:0402-RES")
      (fields (field (name "MPN") "ERJ-2RKF1002X"))
      (libsource (lib "eagle-import") (part "RESISTOR0402-RES"))
    )
    (comp (ref "R29")
      (value "10k")
      (footprint "eagle-import:0402")
      (fields
        (field (name "MANUFACTURER_PART_NUMBER") "CRCW04021K00FKED")
        (field (name "POWER") "0.063")
        (field (name "TOLERANCE") "1.0")
        (field (name "MPN") "ERJ-2RKF1002X")
        (field (name "TOLERANCE_1") "1%")
      )
      (libsource (lib "eagle-import") (part "CRCW04021K00FKED"))
    )
    (comp (ref "R33")
      (value "10k")
      (footprint "eagle-import:0402-RES")
      (fields (field (name "MPN") "ERJ-2RKF1002X"))
      (libsource (lib "eagle-import") (part "RESISTOR0402-RES"))
    )
    (comp (ref "R34")
      (value "NC")
      (footprint "eagle-import:0402")
      (fields
        (field (name "MANUFACTURER_PART_NUMBER") "CRCW04021K00FKED")
        (field (name "POWER") "0.063")
        (field (name "TOLERANCE") "1.0")
      )
      (libsource (lib "eagle-import") (part "CRCW04021K00FKED"))
    )
    (comp (ref "R37")
      (value "100k")
      (footprint "eagle-import:0402-RES")
      (fields (field (name "MPN") "ERJ-2RKF1003X"))
      (libsource (lib "eagle-import") (part "RESISTOR0402-RES"))
    )
    (comp (ref "R38")
      (value "0")
      (footprint "eagle-import:0402")
      (fields
        (field (name "MANUFACTURER_PART_NUMBER") "CRCW04021K00FKED")
        (field (name "POWER") "0.063")
        (field (name "TOLERANCE") "1.0")
      )
      (libsource (lib "eagle-import") (part "CRCW04021K00FKED"))
    )
    (comp (ref "R41")
      (value "100k")
      (footprint "eagle-import:0402-RES")
      (fields (field (name "MPN") "ERJ-2RKF1003X"))
      (libsource (lib "eagle-import") (part "RESISTOR0402-RES"))
    )
    (comp (ref "R54")
      (value "0")
      (footprint "eagle-import:0402")
      (fields
        (field (name "MANUFACTURER_PART_NUMBER") "CRCW04021K00FKED")
        (field (name "POWER") "0.063")
        (field (name "TOLERANCE") "1.0")
      )
      (libsource (lib "eagle-import") (part "CRCW04021K00FKED"))
    )
    (comp (ref "R55")
      (value "0")
      (footprint "eagle-import:0402-RES")
      (fields (field (name "MPN") "ERJ-2GE0R00X"))
      (libsource (lib "eagle-import") (part "RESISTOR0402-RES"))
    )
    (comp (ref "R56")
      (value "NC")
      (footprint "eagle-import:0402-RES")
      (libsource (lib "eagle-import") (part "RESISTOR0402-RES"))
    )
    (comp (ref "R59")
      (value "10k")
      (footprint "eagle-import:0402-RES")
      (fields (field (name "MPN") "ERJ-2RKF1002X"))
      (libsource (lib "eagle-import") (part "RESISTOR0402-RES"))
    )
    (comp (ref "R67")
      (value "0")
      (footprint "eagle-import:0402")
      (fields
        (field (name "MANUFACTURER_PART_NUMBER") "CRCW04021K00FKED")
        (field (name "POWER") "0.063")
        (field (name "TOLERANCE") "1.0")
      )
      (libsource (lib "eagle-import") (part "CRCW04021K00FKED"))
    )
    (comp (ref "R84")
      (value "0")
      (footprint "eagle-import:0402-RES")
      (fields (field (name "MPN") "ERJ-2GE0R00X"))
      (libsource (lib "eagle-import") (part "RESISTOR0402-RES"))
    )
    (comp (ref "R117")
      (value "10k")
      (footprint "eagle-import:0402-RES")
      (fields (field (name "MPN") "ERJ-2RKF1002X"))
      (libsource (lib "eagle-import") (part "RESISTOR0402-RES"))
    )
    (comp (ref "TP1")
      (value "TPTP06R")
      (footprint "eagle-import:TP06R")
      (fields (field (name "TP_SIGNAL_NAME") "CLKOUT"))
      (libsource (lib "eagle-import") (part "TPTP06R"))
    )
    (comp (ref "TP4")
      (value "TPTP06R")
      (footprint "eagle-import:TP06R")
      (fields (field (name "TP_SIGNAL_NAME") "RTC_CLKOUT"))
      (libsource (lib "eagle-import") (part "TPTP06R"))
    )
    (comp (ref "TP14")
      (value "TPTP06R")
      (footprint "eagle-import:TP06R")
      (libsource (lib "eagle-import") (part "TPTP06R"))
    )
    (comp (ref "TP15")
      (value "TPTP06R")
      (footprint "eagle-import:TP06R")
      (libsource (lib "eagle-import") (part "TPTP06R"))
    )
    (comp (ref "TP16")
      (value "TPTP06R")
      (footprint "eagle-import:TP06R")
      (libsource (lib "eagle-import") (part "TPTP06R"))
    )
    (comp (ref "TP19")
      (value "TPTP06R")
      (footprint "eagle-import:TP06R")
      (libsource (lib "eagle-import") (part "TPTP06R"))
    )
    (comp (ref "TP20")
      (value "TPTP06R")
      (footprint "eagle-import:TP06R")
      (libsource (lib "eagle-import") (part "TPTP06R"))
    )
    (comp (ref "TP21")
      (value "TPTP06R")
      (footprint "eagle-import:TP06R")
      (libsource (lib "eagle-import") (part "TPTP06R"))
    )
    (comp (ref "Y1")
      (value "32.768kHz")
      (footprint "eagle-import:CRYSTAL-32KHZ-SMD_EPSON_MC146")
      (fields (field (name "MPN") "SSPT7F-12.5PF20-R"))
      (libsource (lib "eagle-import") (part "CRYSTAL"))
    )
    (comp (ref "C8")
      (value "10u")
      (footprint "eagle-import:C0603K")
      (fields (field (name "MPN") "GRM188R61C106MA73D"))
      (libsource (lib "eagle-import") (part "C-EUC0603K"))
    )
    (comp (ref "C11")
      (value "10u")
      (footprint "eagle-import:C0603K")
      (fields (field (name "MPN") "GRM188R61C106MA73D"))
      (libsource (lib "eagle-import") (part "C-EUC0603K"))
    )
    (comp (ref "C12")
      (value "10u")
      (footprint "eagle-import:C0603K")
      (fields (field (name "MPN") "GRM188R61C106MA73D"))
      (libsource (lib "eagle-import") (part "C-EUC0603K"))
    )
    (comp (ref "C13")
      (value "100u")
      (footprint "eagle-import:1411")
      (fields (field (name "MPN") "ATCC-211B-010-107M-T"))
      (libsource (lib "eagle-import") (part "CPOL-US1411"))
    )
    (comp (ref "C14")
      (value "100u")
      (footprint "eagle-import:1411")
      (fields (field (name "MPN") "ATCC-211B-010-107M-T"))
      (libsource (lib "eagle-import") (part "CPOL-US1411"))
    )
    (comp (ref "C16")
      (value "0.47u")
      (footprint "eagle-import:C0603K")
      (fields (field (name "MPN") "GRM188R71C474KA88D"))
      (libsource (lib "eagle-import") (part "C-EUC0603K"))
    )
    (comp (ref "C17")
      (value "0.47u")
      (footprint "eagle-import:C0603K")
      (fields (field (name "MPN") "GRM188R71C474KA88D"))
      (libsource (lib "eagle-import") (part "C-EUC0603K"))
    )
    (comp (ref "C18")
      (value "10u")
      (footprint "eagle-import:C0603K")
      (fields (field (name "MPN") "GRM188R61C106MA73D"))
      (libsource (lib "eagle-import") (part "C-EUC0603K"))
    )
    (comp (ref "C19")
      (value "10u")
      (footprint "eagle-import:C0603K")
      (fields (field (name "MPN") "GRM188R61C106MA73D"))
      (libsource (lib "eagle-import") (part "C-EUC0603K"))
    )
    (comp (ref "C104")
      (value "10n")
      (footprint "eagle-import:C0402K")
      (fields (field (name "MPN") "GRM155R71E103KA01D"))
      (libsource (lib "eagle-import") (part "resistor_C-EUC0402K"))
    )
    (comp (ref "C105")
      (value "0.1u")
      (footprint "eagle-import:C0402K")
      (fields (field (name "MPN") "GRM155R71C104JA88D"))
      (libsource (lib "eagle-import") (part "resistor_C-EUC0402K"))
    )
    (comp (ref "C108")
      (value "0.1u")
      (footprint "eagle-import:C0402K")
      (fields (field (name "MPN") "GRM155R71C104JA88D"))
      (libsource (lib "eagle-import") (part "resistor_C-EUC0402K"))
    )
    (comp (ref "C111")
      (value "0.1u")
      (footprint "eagle-import:C0402K")
      (fields (field (name "MPN") "GRM155R71C104JA88D"))
      (libsource (lib "eagle-import") (part "resistor_C-EUC0402K"))
    )
    (comp (ref "C116")
      (value "0.1u")
      (footprint "eagle-import:C0402K")
      (fields (field (name "MPN") "GRM155R71C104JA88D"))
      (libsource (lib "eagle-import") (part "resistor_C-EUC0402K"))
    )
    (comp (ref "C117")
      (value "0.1u")
      (footprint "eagle-import:C0402K")
      (fields (field (name "MPN") "GRM155R71C104JA88D"))
      (libsource (lib "eagle-import") (part "resistor_C-EUC0402K"))
    )
    (comp (ref "C122")
      (value "0.1u")
      (footprint "eagle-import:C0402K")
      (fields (field (name "MPN") "GRM155R71C104JA88D"))
      (libsource (lib "eagle-import") (part "resistor_C-EUC0402K"))
    )
    (comp (ref "FB2")
      (value "BLM21AG151SN1D")
      (footprint "eagle-import:0805")
      (libsource (lib "eagle-import") (part "INDUCTOR0805"))
    )
    (comp (ref "FB3")
      (value "BLM21AG151SN1D")
      (footprint "eagle-import:0805")
      (libsource (lib "eagle-import") (part "INDUCTOR0805"))
    )
    (comp (ref "J4")
      (value "HEADPHONES")
      (footprint "eagle-import:AUDIO-JACK-3.5MM-SMD")
      (fields (field (name "MPN") "SJ1-3515-SMT-TR"))
      (libsource (lib "eagle-import") (part "AUDIOJACK3_5SMD"))
    )
    (comp (ref "R5")
      (value "0")
      (footprint "eagle-import:0402-RES")
      (fields (field (name "MPN") "ERJ-2GE0R00X"))
      (libsource (lib "eagle-import") (part "RESISTOR0402-RES"))
    )
    (comp (ref "R8")
      (value "0")
      (footprint "eagle-import:0402-RES")
      (fields (field (name "MPN") "ERJ-2GE0R00X"))
      (libsource (lib "eagle-import") (part "RESISTOR0402-RES"))
    )
    (comp (ref "R9")
      (value "NC")
      (footprint "eagle-import:0603-RES")
      (libsource (lib "eagle-import") (part "RESISTOR0603-RES"))
    )
    (comp (ref "R10")
      (value "4.7k")
      (footprint "eagle-import:0603-RES")
      (fields (field (name "MPN") "ERJ-3EKF4701V"))
      (libsource (lib "eagle-import") (part "RESISTOR0603-RES"))
    )
    (comp (ref "R92")
      (value "0")
      (footprint "eagle-import:0402-RES")
      (fields (field (name "MPN") "ERJ-2GE0R00X"))
      (libsource (lib "eagle-import") (part "RESISTOR0402-RES"))
    )
    (comp (ref "R93")
      (value "0")
      (footprint "eagle-import:0402-RES")
      (fields (field (name "MPN") "ERJ-2GE0R00X"))
      (libsource (lib "eagle-import") (part "RESISTOR0402-RES"))
    )
    (comp (ref "R94")
      (value "0")
      (footprint "eagle-import:0402-RES")
      (fields (field (name "MPN") "ERJ-2GE0R00X"))
      (libsource (lib "eagle-import") (part "RESISTOR0402-RES"))
    )
    (comp (ref "R95")
      (value "0")
      (footprint "eagle-import:0402-RES")
      (fields (field (name "MPN") "ERJ-2GE0R00X"))
      (libsource (lib "eagle-import") (part "RESISTOR0402-RES"))
    )
    (comp (ref "R104")
      (value "4.7k")
      (footprint "eagle-import:0402-RES")
      (fields (field (name "MPN") "ERJ-2RKF4701X"))
      (libsource (lib "eagle-import") (part "RESISTOR0402-RES"))
    )
    (comp (ref "R106")
      (value "NC")
      (footprint "eagle-import:0402-RES")
      (libsource (lib "eagle-import") (part "RESISTOR0402-RES"))
    )
    (comp (ref "R107")
      (value "NC")
      (footprint "eagle-import:0402-RES")
      (libsource (lib "eagle-import") (part "RESISTOR0402-RES"))
    )
    (comp (ref "R108")
      (value "0")
      (footprint "eagle-import:0402-RES")
      (fields (field (name "MPN") "ERJ-2GE0R00X"))
      (libsource (lib "eagle-import") (part "RESISTOR0402-RES"))
    )
    (comp (ref "R110")
      (value "1k")
      (footprint "eagle-import:0402-RES")
      (fields (field (name "MPN") "ERJ-2RKF1001X"))
      (libsource (lib "eagle-import") (part "RESISTOR0402-RES"))
    )
    (comp (ref "R111")
      (value "1k")
      (footprint "eagle-import:0402-RES")
      (fields (field (name "MPN") "ERJ-2RKF1001X"))
      (libsource (lib "eagle-import") (part "RESISTOR0402-RES"))
    )
    (comp (ref "R134")
      (value "10k")
      (footprint "eagle-import:0402-RES")
      (fields (field (name "MPN") "ERJ-2RKF1002X"))
      (libsource (lib "eagle-import") (part "RESISTOR0402-RES"))
    )
    (comp (ref "R135")
      (value "10k")
      (footprint "eagle-import:0402-RES")
      (fields (field (name "MPN") "ERJ-2RKF1002X"))
      (libsource (lib "eagle-import") (part "RESISTOR0402-RES"))
    )
    (comp (ref "R136")
      (value "4.7k")
      (footprint "eagle-import:0402-RES")
      (fields (field (name "MPN") "ERJ-2RKF4701X"))
      (libsource (lib "eagle-import") (part "RESISTOR0402-RES"))
    )
    (comp (ref "R137")
      (value "220k")
      (footprint "eagle-import:0402-RES")
      (fields (field (name "MPN") "ERJ-2RKF2203X"))
      (libsource (lib "eagle-import") (part "RESISTOR0402-RES"))
    )
    (comp (ref "R138")
      (value "10k")
      (footprint "eagle-import:0402-RES")
      (fields (field (name "MPN") "ERJ-2RKF1002X"))
      (libsource (lib "eagle-import") (part "RESISTOR0402-RES"))
    )
    (comp (ref "R141")
      (value "NC")
      (footprint "eagle-import:0402-RES")
      (libsource (lib "eagle-import") (part "RESISTOR0402-RES"))
    )
    (comp (ref "TP2")
      (value "TPTP06R")
      (footprint "eagle-import:TP06R")
      (fields (field (name "TP_SIGNAL_NAME") "GND"))
      (libsource (lib "eagle-import") (part "TPTP06R"))
    )
    (comp (ref "U14")
      (value "ASDM1-12.000MHZ-LC-T")
      (footprint "eagle-import:ASDM1")
      (fields
        (field (name "MF") "Abracon")
        (field (name "MPN") "ASDM")
        (field (name "MPN_1") "ASDM1-12.000MHZ-LC-T")
      )
      (libsource (lib "eagle-import") (part "ASDM"))
    )
    (comp (ref "U17")
      (value "TLV320AIC3204IRHBT")
      (footprint "eagle-import:QFN50P500X500X100-33N")
      (fields (field (name "MPN") "TLV320AIC3204IRHBT"))
      (libsource (lib "eagle-import") (part "TLV320AIC3204IRHBT"))
    )
    (comp (ref "U18")
      (value "SN74CBTLV3245APW")
      (footprint "eagle-import:SOP65P640X120-20N")
      (fields (field (name "MPN") "SN74CBTLV3245APWR"))
      (libsource (lib "eagle-import") (part "SN74CBTLV3245APW"))
    )
    (comp (ref "C21X")
      (value "22u")
      (footprint "eagle-import:C1206K")
      (fields (field (name "MPN") "GRM31CR71A226KE15L"))
      (libsource (lib "eagle-import") (part "C-EUC1206K"))
    )
    (comp (ref "C23X")
      (value "22u")
      (footprint "eagle-import:C1210K")
      (fields (field (name "MPN") "GRM32ER71E226ME15L"))
      (libsource (lib "eagle-import") (part "C-EUC1210K"))
    )
    (comp (ref "C26X")
      (value "1u")
      (footprint "eagle-import:C0402K")
      (fields (field (name "MPN") "GRM155R70J105KA12D"))
      (libsource (lib "eagle-import") (part "resistor_C-EUC0402K"))
    )
    (comp (ref "C94X")
      (value "22u")
      (footprint "eagle-import:C1206K")
      (fields (field (name "MPN") "GRM31CR71A226KE15L"))
      (libsource (lib "eagle-import") (part "C-EUC1206K"))
    )
    (comp (ref "C95X")
      (value "820p")
      (footprint "eagle-import:C0402K")
      (fields (field (name "MPN") "GRM1555C1H821JA01D"))
      (libsource (lib "eagle-import") (part "resistor_C-EUC0402K"))
    )
    (comp (ref "C98X")
      (value "0.1u")
      (footprint "eagle-import:C0402K")
      (fields (field (name "MPN") "GRM155R71C104JA88D"))
      (libsource (lib "eagle-import") (part "resistor_C-EUC0402K"))
    )
    (comp (ref "C99X")
      (value "22u")
      (footprint "eagle-import:C1210K")
      (fields (field (name "MPN") "GRM32ER71E226ME15L"))
      (libsource (lib "eagle-import") (part "C-EUC1210K"))
    )
    (comp (ref "C124X")
      (value "0.1u")
      (footprint "eagle-import:C0402K")
      (fields (field (name "MPN") "GRM155R71C104JA88D"))
      (libsource (lib "eagle-import") (part "resistor_C-EUC0402K"))
    )
    (comp (ref "C125X")
      (value "0.1u")
      (footprint "eagle-import:C0402K")
      (fields (field (name "MPN") "GRM155R71C104JA88D"))
      (libsource (lib "eagle-import") (part "resistor_C-EUC0402K"))
    )
    (comp (ref "C213X")
      (value "0.1u")
      (footprint "eagle-import:C0402K")
      (fields (field (name "MPN") "GRM155R71C104JA88D"))
      (libsource (lib "eagle-import") (part "resistor_C-EUC0402K"))
    )
    (comp (ref "C215X")
      (value "0.1u")
      (footprint "eagle-import:C0402K")
      (fields (field (name "MPN") "GRM155R71C104JA88D"))
      (libsource (lib "eagle-import") (part "resistor_C-EUC0402K"))
    )
    (comp (ref "C216X")
      (value "0.1u")
      (footprint "eagle-import:C0402K")
      (fields (field (name "MPN") "GRM155R71C104JA88D"))
      (libsource (lib "eagle-import") (part "resistor_C-EUC0402K"))
    )
    (comp (ref "C217X")
      (value "1u")
      (footprint "eagle-import:C0402K")
      (fields (field (name "MPN") "GRM155R70J105KA12D"))
      (libsource (lib "eagle-import") (part "resistor_C-EUC0402K"))
    )
    (comp (ref "C218X")
      (value "10u")
      (footprint "eagle-import:C0603K")
      (fields (field (name "MPN") "GRM188R61C106MA73D"))
      (libsource (lib "eagle-import") (part "resistor_C-EUC0603K"))
    )
    (comp (ref "L6X")
      (value "2.2u")
      (footprint "eagle-import:SRN3015")
      (fields (field (name "MPN") "SRN3015-2R2M"))
      (libsource (lib "eagle-import") (part "SRN3015"))
    )
    (comp (ref "L7X")
      (value "3.3u")
      (footprint "eagle-import:SRN3015")
      (fields (field (name "MPN") "SRN3015-3R3M"))
      (libsource (lib "eagle-import") (part "SRN3015"))
    )
    (comp (ref "L8X")
      (value "BML15HD601SN1")
      (footprint "eagle-import:0402")
      (fields (field (name "MPN") "BLM15HD601SN1D"))
      (libsource (lib "eagle-import") (part "BML15HD601SN1"))
    )
    (comp (ref "R1X")
      (value "0")
      (footprint "eagle-import:0402-RES")
      (fields (field (name "MPN") "ERJ-2GE0R00X"))
      (libsource (lib "eagle-import") (part "RESISTOR0402-RES"))
    )
    (comp (ref "R2X")
      (value "0")
      (footprint "eagle-import:0402-RES")
      (fields (field (name "MPN") "ERJ-2GE0R00X"))
      (libsource (lib "eagle-import") (part "RESISTOR0402-RES"))
    )
    (comp (ref "R3X")
      (value "1k")
      (footprint "eagle-import:0402-RES")
      (fields (field (name "MPN") "ERJ-2RKF1001X"))
      (libsource (lib "eagle-import") (part "RESISTOR0402-RES"))
    )
    (comp (ref "R11X")
      (value "13.7k")
      (footprint "eagle-import:0402-RES")
      (fields (field (name "MPN") "ERJ-2RKF1372X"))
      (libsource (lib "eagle-import") (part "RESISTOR0402-RES"))
    )
    (comp (ref "R15")
      (value "0")
      (footprint "eagle-import:0402-RES")
      (fields (field (name "MPN") "ERJ-2GE0R00X"))
      (libsource (lib "eagle-import") (part "RESISTOR0402-RES"))
    )
    (comp (ref "R15X")
      (value "10k")
      (footprint "eagle-import:0402-RES")
      (fields (field (name "MPN") "ERJ-2RKF1002X"))
      (libsource (lib "eagle-import") (part "RESISTOR0402-RES"))
    )
    (comp (ref "R65X")
      (value "33.2k")
      (footprint "eagle-import:0402-RES")
      (fields (field (name "MPN") "ERJ-2RKF3322X"))
      (libsource (lib "eagle-import") (part "RESISTOR0402-RES"))
    )
    (comp (ref "R70X")
      (value "10k")
      (footprint "eagle-import:0402-RES")
      (fields (field (name "MPN") "ERJ-2RKF1002X"))
      (libsource (lib "eagle-import") (part "RESISTOR0402-RES"))
    )
    (comp (ref "R96X")
      (value "0")
      (footprint "eagle-import:0402-RES")
      (fields (field (name "MPN") "ERJ-2GE0R00X"))
      (libsource (lib "eagle-import") (part "RESISTOR0402-RES"))
    )
    (comp (ref "R118X")
      (value "0")
      (footprint "eagle-import:0402-RES")
      (fields (field (name "MPN") "ERJ-2GE0R00X"))
      (libsource (lib "eagle-import") (part "RESISTOR0402-RES"))
    )
    (comp (ref "R119X")
      (value "0")
      (footprint "eagle-import:0402-RES")
      (fields (field (name "MPN") "ERJ-2GE0R00X"))
      (libsource (lib "eagle-import") (part "RESISTOR0402-RES"))
    )
    (comp (ref "R125X")
      (value "20.5k")
      (footprint "eagle-import:0402-RES")
      (fields (field (name "MPN") "ERJ-2RKF2052X"))
      (libsource (lib "eagle-import") (part "RESISTOR0402-RES"))
    )
    (comp (ref "R126X")
      (value "243k")
      (footprint "eagle-import:0402-RES")
      (fields (field (name "MPN") "ERJ-2RKF2433X"))
      (libsource (lib "eagle-import") (part "RESISTOR0402-RES"))
    )
    (comp (ref "R222X")
      (value "10k")
      (footprint "eagle-import:0402-RES")
      (fields (field (name "MPN") "ERJ-2RKF1002X"))
      (libsource (lib "eagle-import") (part "RESISTOR0402-RES"))
    )
    (comp (ref "R223X")
      (value "10")
      (footprint "eagle-import:0402-RES")
      (fields (field (name "MPN") "ERJ-2RKF10R0X"))
      (libsource (lib "eagle-import") (part "RESISTOR0402-RES"))
    )
    (comp (ref "R224X")
      (value "10")
      (footprint "eagle-import:0402-RES")
      (fields (field (name "MPN") "ERJ-2RKF10R0X"))
      (libsource (lib "eagle-import") (part "RESISTOR0402-RES"))
    )
    (comp (ref "R225X")
      (value "10")
      (footprint "eagle-import:0402-RES")
      (fields (field (name "MPN") "ERJ-2RKF10R0X"))
      (libsource (lib "eagle-import") (part "RESISTOR0402-RES"))
    )
    (comp (ref "R226X")
      (value "10")
      (footprint "eagle-import:0402-RES")
      (fields (field (name "MPN") "ERJ-2RKF10R0X"))
      (libsource (lib "eagle-import") (part "RESISTOR0402-RES"))
    )
    (comp (ref "R227X")
      (value "10")
      (footprint "eagle-import:0402-RES")
      (fields (field (name "MPN") "ERJ-2RKF10R0X"))
      (libsource (lib "eagle-import") (part "RESISTOR0402-RES"))
    )
    (comp (ref "R228X")
      (value "10")
      (footprint "eagle-import:0402-RES")
      (fields (field (name "MPN") "ERJ-2RKF10R0X"))
      (libsource (lib "eagle-import") (part "RESISTOR0402-RES"))
    )
    (comp (ref "R229X")
      (value "10")
      (footprint "eagle-import:0402-RES")
      (fields (field (name "MPN") "ERJ-2RKF10R0X"))
      (libsource (lib "eagle-import") (part "RESISTOR0402-RES"))
    )
    (comp (ref "R230X")
      (value "10")
      (footprint "eagle-import:0402-RES")
      (fields (field (name "MPN") "ERJ-2RKF10R0X"))
      (libsource (lib "eagle-import") (part "RESISTOR0402-RES"))
    )
    (comp (ref "TP4X")
      (value "TPTP06R")
      (footprint "eagle-import:TP06R")
      (fields (field (name "TP_SIGNAL_NAME") "VCC_1V8_TP"))
      (libsource (lib "eagle-import") (part "TPTP06R"))
    )
    (comp (ref "TP5X")
      (value "TPTP06R")
      (footprint "eagle-import:TP06R")
      (fields (field (name "TP_SIGNAL_NAME") "VCC_3V3_TP"))
      (libsource (lib "eagle-import") (part "TPTP06R"))
    )
    (comp (ref "TP6X")
      (value "TPTP06R")
      (footprint "eagle-import:TP06R")
      (libsource (lib "eagle-import") (part "TPTP06R"))
    )
    (comp (ref "TP7X")
      (value "TPTP06R")
      (footprint "eagle-import:TP06R")
      (libsource (lib "eagle-import") (part "TPTP06R"))
    )
    (comp (ref "U1X")
      (value "TPS562209SO")
      (footprint "eagle-import:SOT95P280X145-6N")
      (fields (field (name "MPN") "TPS562209DDCT"))
      (libsource (lib "eagle-import") (part "TPS562209SO"))
    )
    (comp (ref "U3X")
      (value "TPS3803-01DCKR")
      (footprint "eagle-import:SOT65P210X110-5N")
      (fields (field (name "MPN") "TPS3803-01DCKR"))
      (libsource (lib "eagle-import") (part "TPS3803-01DCKR"))
    )
    (comp (ref "U11X")
      (value "TPS73201DBVT")
      (footprint "eagle-import:SOT95P280X145-5N")
      (fields (field (name "MPN") "TPS73201DBVT"))
      (libsource (lib "eagle-import") (part "TPS73201DBVT"))
    )
    (comp (ref "U12X")
      (value "TPS562209SO")
      (footprint "eagle-import:SOT95P280X145-6N")
      (fields (field (name "MPN") "TPS562209DDCT"))
      (libsource (lib "eagle-import") (part "TPS562209SO"))
    )
    (comp (ref "U15X")
      (value "CDCLVC1108PWR")
      (footprint "eagle-import:SOP65P640X120-16N")
      (fields (field (name "MPN") "CDCLVC1108PWR"))
      (libsource (lib "eagle-import") (part "CDCLVC1108PWR"))
    )
    (comp (ref "C1-2")
      (value "10u")
      (footprint "eagle-import:C0603K")
      (fields (field (name "MPN") "GRM188R61C106MA73D"))
      (libsource (lib "eagle-import") (part "C-EUC0603K"))
    )
    (comp (ref "C2-2")
      (value "1u")
      (footprint "eagle-import:C0402K")
      (fields (field (name "MPN") "GRM155R70J105KA12D"))
      (libsource (lib "eagle-import") (part "resistor_C-EUC0402K"))
    )
    (comp (ref "C3-2")
      (value "10u")
      (footprint "eagle-import:C0603K")
      (fields (field (name "MPN") "GRM188R61C106MA73D"))
      (libsource (lib "eagle-import") (part "C-EUC0603K"))
    )
    (comp (ref "C4-2")
      (value "10u")
      (footprint "eagle-import:C0603K")
      (fields (field (name "MPN") "GRM188R61C106MA73D"))
      (libsource (lib "eagle-import") (part "C-EUC0603K"))
    )
    (comp (ref "C5-2")
      (value "1u")
      (footprint "eagle-import:C0402K")
      (fields (field (name "MPN") "GRM155R70J105KA12D"))
      (libsource (lib "eagle-import") (part "resistor_C-EUC0402K"))
    )
    (comp (ref "C28-2")
      (value "0.1u")
      (footprint "eagle-import:0402")
      (fields (field (name "MPN") "GRM155R71C104JA88D"))
      (libsource (lib "eagle-import") (part "C0402_BGA"))
    )
    (comp (ref "C29-2")
      (value "0.1u")
      (footprint "eagle-import:0402")
      (fields (field (name "MPN") "GRM155R71C104JA88D"))
      (libsource (lib "eagle-import") (part "C0402_BGA"))
    )
    (comp (ref "C30-2")
      (value "0.1u")
      (footprint "eagle-import:0402")
      (fields (field (name "MPN") "GRM155R71C104JA88D"))
      (libsource (lib "eagle-import") (part "C0402_BGA"))
    )
    (comp (ref "C32-2")
      (value "0.1u")
      (footprint "eagle-import:0402")
      (fields (field (name "MPN") "GRM155R71C104JA88D"))
      (libsource (lib "eagle-import") (part "C0402_BGA"))
    )
    (comp (ref "C38-2")
      (value "10n")
      (footprint "eagle-import:0402")
      (fields (field (name "MPN") "GRM155R71E103KA01D"))
      (libsource (lib "eagle-import") (part "C0402_BGA"))
    )
    (comp (ref "C40-2")
      (value "0.1u")
      (footprint "eagle-import:0402")
      (fields (field (name "MPN") "GRM155R71C104JA88D"))
      (libsource (lib "eagle-import") (part "C0402_BGA"))
    )
    (comp (ref "C41-2")
      (value "10n")
      (footprint "eagle-import:0402")
      (fields (field (name "MPN") "GRM155R71E103KA01D"))
      (libsource (lib "eagle-import") (part "C0402_BGA"))
    )
    (comp (ref "C42-2")
      (value "1u")
      (footprint "eagle-import:0402")
      (fields (field (name "MPN") "GRM155R70J105KA12D"))
      (libsource (lib "eagle-import") (part "C0402_BGA"))
    )
    (comp (ref "C43-2")
      (value "10n")
      (footprint "eagle-import:0402")
      (fields (field (name "MPN") "GRM155R71E103KA01D"))
      (libsource (lib "eagle-import") (part "C0402_BGA"))
    )
    (comp (ref "C45-2")
      (value "0.1u")
      (footprint "eagle-import:0402")
      (fields (field (name "MPN") "GRM155R71C104JA88D"))
      (libsource (lib "eagle-import") (part "C0402_BGA"))
    )
    (comp (ref "C46-2")
      (value "0.1u")
      (footprint "eagle-import:0402")
      (fields (field (name "MPN") "GRM155R71C104JA88D"))
      (libsource (lib "eagle-import") (part "C0402_BGA"))
    )
    (comp (ref "C48-2")
      (value "0.1u")
      (footprint "eagle-import:0402")
      (fields (field (name "MPN") "GRM155R71C104JA88D"))
      (libsource (lib "eagle-import") (part "C0402_BGA"))
    )
    (comp (ref "C49-2")
      (value "0.1u")
      (footprint "eagle-import:0402")
      (fields (field (name "MPN") "GRM155R71C104JA88D"))
      (libsource (lib "eagle-import") (part "C0402_BGA"))
    )
    (comp (ref "C50-2")
      (value "1n")
      (footprint "eagle-import:0402")
      (fields (field (name "MPN") "GRM155R71H102JA01J"))
      (libsource (lib "eagle-import") (part "C0402_BGA"))
    )
    (comp (ref "C51-2")
      (value "10n")
      (footprint "eagle-import:0402")
      (fields (field (name "MPN") "GRM155R71E103KA01D"))
      (libsource (lib "eagle-import") (part "C0402_BGA"))
    )
    (comp (ref "C52-2")
      (value "1u")
      (footprint "eagle-import:0402")
      (fields (field (name "MPN") "GRM155R70J105KA12D"))
      (libsource (lib "eagle-import") (part "C0402_BGA"))
    )
    (comp (ref "C53-2")
      (value "1u")
      (footprint "eagle-import:0402")
      (fields (field (name "MPN") "GRM155R70J105KA12D"))
      (libsource (lib "eagle-import") (part "C0402_BGA"))
    )
    (comp (ref "C54-2")
      (value "1u")
      (footprint "eagle-import:0402")
      (fields (field (name "MPN") "GRM155R70J105KA12D"))
      (libsource (lib "eagle-import") (part "C0402_BGA"))
    )
    (comp (ref "C55-2")
      (value "10n")
      (footprint "eagle-import:0402")
      (fields (field (name "MPN") "GRM155R71E103KA01D"))
      (libsource (lib "eagle-import") (part "C0402_BGA"))
    )
    (comp (ref "C56-2")
      (value "1n")
      (footprint "eagle-import:0402")
      (fields (field (name "MPN") "GRM155R71H102JA01J"))
      (libsource (lib "eagle-import") (part "C0402_BGA"))
    )
    (comp (ref "C57-2")
      (value "0.1u")
      (footprint "eagle-import:0402")
      (fields (field (name "MPN") "GRM155R71C104JA88D"))
      (libsource (lib "eagle-import") (part "C0402_BGA"))
    )
    (comp (ref "C59-2")
      (value "0.1u")
      (footprint "eagle-import:0402")
      (fields (field (name "MPN") "GRM155R71C104JA88D"))
      (libsource (lib "eagle-import") (part "C0402_BGA"))
    )
    (comp (ref "C60-2")
      (value "0.1u")
      (footprint "eagle-import:0402")
      (fields (field (name "MPN") "GRM155R71C104JA88D"))
      (libsource (lib "eagle-import") (part "C0402_BGA"))
    )
    (comp (ref "C62-2")
      (value "0.1u")
      (footprint "eagle-import:0402")
      (fields (field (name "MPN") "GRM155R71C104JA88D"))
      (libsource (lib "eagle-import") (part "C0402_BGA"))
    )
    (comp (ref "C63-2")
      (value "0.1u")
      (footprint "eagle-import:0402")
      (fields (field (name "MPN") "GRM155R71C104JA88D"))
      (libsource (lib "eagle-import") (part "C0402_BGA"))
    )
    (comp (ref "C64-2")
      (value "1u")
      (footprint "eagle-import:0402")
      (fields (field (name "MPN") "GRM155R70J105KA12D"))
      (libsource (lib "eagle-import") (part "C0402_BGA"))
    )
    (comp (ref "C65-2")
      (value "0.1u")
      (footprint "eagle-import:0402")
      (fields (field (name "MPN") "GRM155R71C104JA88D"))
      (libsource (lib "eagle-import") (part "C0402_BGA"))
    )
    (comp (ref "C67-2")
      (value "0.1u")
      (footprint "eagle-import:0402")
      (fields (field (name "MPN") "GRM155R71C104JA88D"))
      (libsource (lib "eagle-import") (part "C0402_BGA"))
    )
    (comp (ref "C69-2")
      (value "0.1u")
      (footprint "eagle-import:0402")
      (fields (field (name "MPN") "GRM155R71C104JA88D"))
      (libsource (lib "eagle-import") (part "C0402_BGA"))
    )
    (comp (ref "C71-2")
      (value "0.1u")
      (footprint "eagle-import:0402")
      (fields (field (name "MPN") "GRM155R71C104JA88D"))
      (libsource (lib "eagle-import") (part "C0402_BGA"))
    )
    (comp (ref "C72-2")
      (value "0.1u")
      (footprint "eagle-import:0402")
      (fields (field (name "MPN") "GRM155R71C104JA88D"))
      (libsource (lib "eagle-import") (part "C0402_BGA"))
    )
    (comp (ref "C73-2")
      (value "10n")
      (footprint "eagle-import:0402")
      (fields (field (name "MPN") "GRM155R71E103KA01D"))
      (libsource (lib "eagle-import") (part "C0402_BGA"))
    )
    (comp (ref "C74-2")
      (value "1n")
      (footprint "eagle-import:C0402K")
      (fields (field (name "MPN") "GRM155R71H102JA01J"))
      (libsource (lib "eagle-import") (part "resistor_C-EUC0402K"))
    )
    (comp (ref "C75-2")
      (value "0.1u")
      (footprint "eagle-import:0402")
      (fields (field (name "MPN") "GRM155R71C104JA88D"))
      (libsource (lib "eagle-import") (part "C0402_BGA"))
    )
    (comp (ref "C85-2")
      (value "0.1u")
      (footprint "eagle-import:0402")
      (fields (field (name "MPN") "GRM155R71C104JA88D"))
      (libsource (lib "eagle-import") (part "C0402_BGA"))
    )
    (comp (ref "C86-2")
      (value "1u")
      (footprint "eagle-import:0402")
      (fields (field (name "MPN") "GRM155R70J105KA12D"))
      (libsource (lib "eagle-import") (part "C0402_BGA"))
    )
    (comp (ref "C87-2")
      (value "0.1u")
      (footprint "eagle-import:0402")
      (fields (field (name "MPN") "GRM155R71C104JA88D"))
      (libsource (lib "eagle-import") (part "C0402_BGA"))
    )
    (comp (ref "C88-2")
      (value "0.1u")
      (footprint "eagle-import:0402")
      (fields (field (name "MPN") "GRM155R71C104JA88D"))
      (libsource (lib "eagle-import") (part "C0402_BGA"))
    )
    (comp (ref "C89-2")
      (value "10n")
      (footprint "eagle-import:C0402K")
      (fields (field (name "MPN") "GRM155R71E103KA01D"))
      (libsource (lib "eagle-import") (part "resistor_C-EUC0402K"))
    )
    (comp (ref "FB1-2")
      (value "BLM18AG601SN1D")
      (footprint "eagle-import:0603")
      (libsource (lib "eagle-import") (part "INDUCTOR0603"))
    )
    (comp (ref "FB4-2")
      (value "BLM18AG601SN1D")
      (footprint "eagle-import:0603")
      (libsource (lib "eagle-import") (part "INDUCTOR0603"))
    )
    (comp (ref "FB5-2")
      (value "BLM18AG601SN1D")
      (footprint "eagle-import:0603")
      (libsource (lib "eagle-import") (part "INDUCTOR0603"))
    )
    (comp (ref "FB6-2")
      (value "BLM18AG601SN1D")
      (footprint "eagle-import:0603")
      (libsource (lib "eagle-import") (part "INDUCTOR0603"))
    )
    (comp (ref "L3-2")
      (value "BLM18AG601SN1D")
      (footprint "eagle-import:0603")
      (libsource (lib "eagle-import") (part "INDUCTOR0603"))
    )
    (comp (ref "R60-2")
      (value "0")
      (footprint "eagle-import:0402-RES")
      (fields (field (name "MPN") "ERJ-2GE0R00X"))
      (libsource (lib "eagle-import") (part "RESISTOR0402-RES"))
    )
    (comp (ref "R61-2")
      (value "0")
      (footprint "eagle-import:0402-RES")
      (fields (field (name "MPN") "ERJ-2GE0R00X"))
      (libsource (lib "eagle-import") (part "RESISTOR0402-RES"))
    )
    (comp (ref "R62-2")
      (value "NC")
      (footprint "eagle-import:0402-RES")
      (libsource (lib "eagle-import") (part "RESISTOR0402-RES"))
    )
    (comp (ref "R63-2")
      (value "NC")
      (footprint "eagle-import:0402-RES")
      (libsource (lib "eagle-import") (part "RESISTOR0402-RES"))
    )
    (comp (ref "R64-2")
      (value "0")
      (footprint "eagle-import:0402-RES")
      (fields (field (name "MPN") "ERJ-2GE0R00X"))
      (libsource (lib "eagle-import") (part "RESISTOR0402-RES"))
    )
    (comp (ref "R97-2")
      (value "0")
      (footprint "eagle-import:0805")
      (fields (field (name "MPN") "ERJ-6GEY0R00V"))
      (libsource (lib "eagle-import") (part "RESISTOR0805-RES"))
    )
    (comp (ref "R121-2")
      (value "NC")
      (footprint "eagle-import:0805")
      (libsource (lib "eagle-import") (part "RESISTOR0805-RES"))
    )
    (comp (ref "R122-2")
      (value "0")
      (footprint "eagle-import:0805")
      (fields (field (name "MPN") "ERJ-6GEY0R00V"))
      (libsource (lib "eagle-import") (part "RESISTOR0805-RES"))
    )
    (comp (ref "R124-2")
      (value "0")
      (footprint "eagle-import:0805")
      (fields (field (name "MPN") "ERJ-6GEY0R00V"))
      (libsource (lib "eagle-import") (part "RESISTOR0805-RES"))
    )
    (comp (ref "C168X")
      (value "100p")
      (footprint "eagle-import:C0402K")
      (fields (field (name "MPN") "GRM1555C1H101FA01J"))
      (libsource (lib "eagle-import") (part "C-EUC0402K"))
    )
    (comp (ref "H1")
      (value "MOUNT-PAD-ROUND3.0")
      (footprint "eagle-import:3,0-PAD")
      (libsource (lib "eagle-import") (part "MOUNT-PAD-ROUND3.0"))
    )
    (comp (ref "H2")
      (value "MOUNT-PAD-ROUND3.0")
      (footprint "eagle-import:3,0-PAD")
      (libsource (lib "eagle-import") (part "MOUNT-PAD-ROUND3.0"))
    )
    (comp (ref "H3")
      (value "MOUNT-PAD-ROUND3.0")
      (footprint "eagle-import:3,0-PAD")
      (libsource (lib "eagle-import") (part "MOUNT-PAD-ROUND3.0"))
    )
    (comp (ref "H4")
      (value "MOUNT-PAD-ROUND3.0")
      (footprint "eagle-import:3,0-PAD")
      (libsource (lib "eagle-import") (part "MOUNT-PAD-ROUND3.0"))
    )
    (comp (ref "J5")
      (value "87409-110LF")
      (footprint "eagle-import:87409-110LF")
      (libsource (lib "eagle-import") (part "87409-110LF"))
    )
    (comp (ref "J7")
      (value "87409-110LF")
      (footprint "eagle-import:87409-110LF")
      (libsource (lib "eagle-import") (part "87409-110LF"))
    )
    (comp (ref "JP2")
      (value "FOOTSW")
      (footprint "eagle-import:1X02")
      (libsource (lib "eagle-import") (part "PINHD-1X2"))
    )
    (comp (ref "JP3")
      (value "FIDUCIAL1X2.5")
      (footprint "eagle-import:FIDUCIAL-1X2.5")
      (libsource (lib "eagle-import") (part "FIDUCIAL1X2.5"))
    )
    (comp (ref "JP6")
      (value "FIDUCIAL1X2.5")
      (footprint "eagle-import:FIDUCIAL-1X2.5")
      (libsource (lib "eagle-import") (part "FIDUCIAL1X2.5"))
    )
    (comp (ref "JP7")
      (value "FIDUCIAL1X2.5")
      (footprint "eagle-import:FIDUCIAL-1X2.5")
      (libsource (lib "eagle-import") (part "FIDUCIAL1X2.5"))
    )
    (comp (ref "JP8")
      (value "FIDUCIAL1X2.5")
      (footprint "eagle-import:FIDUCIAL-1X2.5")
      (libsource (lib "eagle-import") (part "FIDUCIAL1X2.5"))
    )
    (comp (ref "LSP1")
      (value "LSP13")
      (footprint "eagle-import:LSP13")
      (libsource (lib "eagle-import") (part "LSP13"))
    )
    (comp (ref "LSP2")
      (value "LSP13")
      (footprint "eagle-import:LSP13")
      (libsource (lib "eagle-import") (part "LSP13"))
    )
    (comp (ref "R4X")
      (value "10k")
      (footprint "eagle-import:0402-RES")
      (fields (field (name "MPN") "ERJ-2RKF1002X"))
      (libsource (lib "eagle-import") (part "RESISTOR0402-RES"))
    )
    (comp (ref "SW1")
      (value "MB2011SB1W03-DA")
      (footprint "eagle-import:MB2011")
      (libsource (lib "eagle-import") (part "MB2011"))
    )
    (comp (ref "TP3")
      (value "TPTP12R")
      (footprint "eagle-import:TP12R")
      (fields (field (name "TP_SIGNAL_NAME") "A-DOWN"))
      (libsource (lib "eagle-import") (part "TPTP12R"))
    )
    (comp (ref "TP5")
      (value "TPTP12R")
      (footprint "eagle-import:TP12R")
      (fields (field (name "TP_SIGNAL_NAME") "A-CENTER"))
      (libsource (lib "eagle-import") (part "TPTP12R"))
    )
    (comp (ref "TP6")
      (value "TPTP12R")
      (footprint "eagle-import:TP12R")
      (fields (field (name "TP_SIGNAL_NAME") "A-UP"))
      (libsource (lib "eagle-import") (part "TPTP12R"))
    )
    (comp (ref "TP7")
      (value "TPTP12R")
      (footprint "eagle-import:TP12R")
      (fields (field (name "TP_SIGNAL_NAME") "A-LEFT"))
      (libsource (lib "eagle-import") (part "TPTP12R"))
    )
    (comp (ref "TP10")
      (value "TPTP12R")
      (footprint "eagle-import:TP12R")
      (fields (field (name "TP_SIGNAL_NAME") "A-RIGHT"))
      (libsource (lib "eagle-import") (part "TPTP12R"))
    )
    (comp (ref "C170")
      (value "10u")
      (footprint "eagle-import:C0805K")
      (fields (field (name "MPN") "GRM21BR71A106KA73L"))
      (libsource (lib "eagle-import") (part "C-EUC0805K"))
    )
    (comp (ref "C171")
      (value "22p")
      (footprint "eagle-import:0402-CAP")
      (fields (field (name "MPN") "GRM1555C2A220JA01D"))
      (libsource (lib "eagle-import") (part "CAP0402-CAP"))
    )
    (comp (ref "C172")
      (value "8.2n")
      (footprint "eagle-import:0402-CAP")
      (fields (field (name "MPN") "GRM155R71H822KA88D"))
      (libsource (lib "eagle-import") (part "CAP0402-CAP"))
    )
    (comp (ref "C173")
      (value "1u")
      (footprint "eagle-import:0402-CAP")
      (fields (field (name "MPN") "GRM155R70J105KA12D"))
      (libsource (lib "eagle-import") (part "CAP0402-CAP"))
    )
    (comp (ref "C174")
      (value "100p")
      (footprint "eagle-import:0402-CAP")
      (fields (field (name "MPN") "GRM1555C1H101FA01J"))
      (libsource (lib "eagle-import") (part "CAP0402-CAP"))
    )
    (comp (ref "C175")
      (value "33n")
      (footprint "eagle-import:0402-CAP")
      (fields (field (name "MPN") "GRM155R71E333KA88J"))
      (libsource (lib "eagle-import") (part "CAP0402-CAP"))
    )
    (comp (ref "C176")
      (value "220n")
      (footprint "eagle-import:0402-CAP")
      (fields (field (name "MPN") "GRM155R71C224KA12D"))
      (libsource (lib "eagle-import") (part "CAP0402-CAP"))
    )
    (comp (ref "C177")
      (value "1u")
      (footprint "eagle-import:0402-CAP")
      (fields (field (name "MPN") "GRM155R70J105KA12D"))
      (libsource (lib "eagle-import") (part "CAP0402-CAP"))
    )
    (comp (ref "C178")
      (value "47p")
      (footprint "eagle-import:0402-CAP")
      (fields (field (name "MPN") "GRM1555C1H470FA01D"))
      (libsource (lib "eagle-import") (part "CAP0402-CAP"))
    )
    (comp (ref "C179")
      (value "100u")
      (footprint "eagle-import:PANASONIC_D")
      (fields (field (name "MF") "Cornell-Dubilier") (field (name "MPN") "AVE107M25X16T-F"))
      (libsource (lib "eagle-import") (part "CPOL-EUD"))
    )
    (comp (ref "C180")
      (value "100u")
      (footprint "eagle-import:PANASONIC_D")
      (fields (field (name "MF") "Cornell Dubilier") (field (name "MPN") "AVE107M25X16T-F"))
      (libsource (lib "eagle-import") (part "CPOL-EUD"))
    )
    (comp (ref "C181")
      (value "100p")
      (footprint "eagle-import:0402-CAP")
      (fields (field (name "MPN") "GRM1555C1H101FA01J"))
      (libsource (lib "eagle-import") (part "CAP0402-CAP"))
    )
    (comp (ref "C182")
      (value "2.2u")
      (footprint "eagle-import:0402-CAP")
      (fields (field (name "MPN") "GRM155R60J225ME15D"))
      (libsource (lib "eagle-import") (part "CAP0402-CAP"))
    )
    (comp (ref "C183")
      (value "22u")
      (footprint "eagle-import:C1206K")
      (fields (field (name "MPN") "GRM31CR71A226KE15L"))
      (libsource (lib "eagle-import") (part "C-EUC1206K"))
    )
    (comp (ref "C184")
      (value "10u")
      (footprint "eagle-import:C0805K")
      (fields (field (name "MPN") "GRM21BR71A106KA73L"))
      (libsource (lib "eagle-import") (part "C-EUC0805K"))
    )
    (comp (ref "C185")
      (value "0.1u")
      (footprint "eagle-import:C0402K")
      (fields (field (name "MPN") "GRM155R71C104JA88D"))
      (libsource (lib "eagle-import") (part "resistor_C-EUC0402K"))
    )
    (comp (ref "C186")
      (value "47n")
      (footprint "eagle-import:0402-CAP")
      (fields (field (name "MPN") "GRM155R71H473KE14D"))
      (libsource (lib "eagle-import") (part "CAP0402-CAP"))
    )
    (comp (ref "C187")
      (value "2.2n")
      (footprint "eagle-import:0402-CAP")
      (fields (field (name "MPN") "GRM155R71H222JA01J"))
      (libsource (lib "eagle-import") (part "CAP0402-CAP"))
    )
    (comp (ref "C188")
      (value "10u")
      (footprint "eagle-import:C0805K")
      (fields (field (name "MPN") "GRM21BR71A106KA73L"))
      (libsource (lib "eagle-import") (part "C-EUC0805K"))
    )
    (comp (ref "C204")
      (value "0.1u")
      (footprint "eagle-import:C0402K")
      (fields (field (name "MPN") "GRM155R71C104JA88D"))
      (libsource (lib "eagle-import") (part "resistor_C-EUC0402K"))
    )
    (comp (ref "C220")
      (value "0.1u")
      (footprint "eagle-import:C0402K")
      (fields (field (name "MPN") "GRM155R71C104JA88D"))
      (libsource (lib "eagle-import") (part "resistor_C-EUC0402K"))
    )
    (comp (ref "C221")
      (value "0.1u")
      (footprint "eagle-import:C0402K")
      (fields (field (name "MPN") "GRM155R71C104JA88D"))
      (libsource (lib "eagle-import") (part "resistor_C-EUC0402K"))
    )
    (comp (ref "C222")
      (value "0.1u")
      (footprint "eagle-import:C0402K")
      (fields (field (name "MPN") "GRM155R71C104JA88D"))
      (libsource (lib "eagle-import") (part "resistor_C-EUC0402K"))
    )
    (comp (ref "CF1")
      (value "NFM3DPC223R1H3L")
      (footprint "eagle-import:NFM3DC")
      (fields
        (field (name "MF") "FARNELL")
        (field (name "MPN") "NFM3DCC470U1H3L")
        (field (name "MPN_1") "NFM3DPC223R1H3L")
      )
      (libsource (lib "eagle-import") (part "NFM3DC"))
    )
    (comp (ref "D6")
      (value "BAT54")
      (footprint "eagle-import:SOT23")
      (fields (field (name "MPN") "BAT54LT1G"))
      (libsource (lib "eagle-import") (part "BAT54"))
    )
    (comp (ref "D8")
      (value "BAT54S")
      (footprint "eagle-import:SOT23")
      (fields (field (name "MPN") "BAT54SLT1G"))
      (libsource (lib "eagle-import") (part "BAT54S"))
    )
    (comp (ref "D9")
      (value "S1G-13-F")
      (footprint "eagle-import:SMADIODE")
      (libsource (lib "eagle-import") (part "DIODESMA"))
    )
    (comp (ref "FB12")
      (value "BLM31PG121SN1L")
      (footprint "eagle-import:R1206")
      (libsource (lib "eagle-import") (part "R-EU_R1206"))
    )
    (comp (ref "IC2")
      (value "SN74HC4066D")
      (footprint "eagle-import:SO14")
      (fields (field (name "MPN") "SN74HC4066DR"))
      (libsource (lib "eagle-import") (part "4066D"))
    )
    (comp (ref "J3")
      (value "STEREOSW3C")
      (footprint "eagle-import:NEUTRIK-NMJ6HCD2")
      (fields (field (name "MPN") "NMJ6HCD2"))
      (libsource (lib "eagle-import") (part "STEREOSW3C"))
    )
    (comp (ref "J8")
      (value "DCJ0202")
      (footprint "eagle-import:DCJ0202")
      (fields (field (name "MF") "Kobiconn") (field (name "MPN") "PJ-202A"))
      (libsource (lib "eagle-import") (part "DCJ0202"))
    )
    (comp (ref "JP1")
      (value "BAT")
      (footprint "eagle-import:1X02")
      (fields (field (name "MF") "3M") (field (name "MPN") "929834-01-02-RK"))
      (libsource (lib "eagle-import") (part "PINHD-1X2"))
    )
    (comp (ref "Q1")
      (value "MUN2214T1")
      (footprint "eagle-import:SC59-BEC")
      (fields (field (name "MPN") "MUN2214T1G"))
      (libsource (lib "eagle-import") (part "MUN2214T1"))
    )
    (comp (ref "Q2")
      (value "MUN2214T1")
      (footprint "eagle-import:SC59-BEC")
      (fields (field (name "MPN") "MUN2214T1G"))
      (libsource (lib "eagle-import") (part "MUN2214T1"))
    )
    (comp (ref "Q3")
      (value "MMBF4393")
      (footprint "eagle-import:SOT23")
      (libsource (lib "eagle-import") (part "?548SST6"))
    )
    (comp (ref "Q4")
      (value "MUN2214T1")
      (footprint "eagle-import:SC59-BEC")
      (fields (field (name "MPN") "MUN2214T1G"))
      (libsource (lib "eagle-import") (part "MUN2214T1"))
    )
    (comp (ref "Q8")
      (value "MUN2214T1")
      (footprint "eagle-import:SC59-BEC")
      (fields (field (name "MPN") "MUN2214T1G"))
      (libsource (lib "eagle-import") (part "MUN2214T1"))
    )
    (comp (ref "Q9")
      (value "MUN2214T1")
      (footprint "eagle-import:SC59-BEC")
      (fields (field (name "MPN") "MUN2214T1G"))
      (libsource (lib "eagle-import") (part "MUN2214T1"))
    )
    (comp (ref "Q10")
      (value "MUN2214T1")
      (footprint "eagle-import:SC59-BEC")
      (fields (field (name "MPN") "MUN2214T1G"))
      (libsource (lib "eagle-import") (part "MUN2214T1"))
    )
    (comp (ref "R65")
      (value "0")
      (footprint "eagle-import:0402-RES")
      (fields (field (name "MPN") "ERJ-2GE0R00X"))
      (libsource (lib "eagle-import") (part "RESISTOR0402-RES"))
    )
    (comp (ref "R144")
      (value "10k")
      (footprint "eagle-import:0402-RES")
      (fields (field (name "MPN") "ERJ-2RKF1002X"))
      (libsource (lib "eagle-import") (part "RESISTOR0402-RES"))
    )
    (comp (ref "R145")
      (value "10k")
      (footprint "eagle-import:0402-RES")
      (fields (field (name "MPN") "ERJ-2RKF1002X"))
      (libsource (lib "eagle-import") (part "RESISTOR0402-RES"))
    )
    (comp (ref "R146")
      (value "100k")
      (footprint "eagle-import:0402-RES")
      (fields (field (name "MPN") "ERJ-2RKF1003X"))
      (libsource (lib "eagle-import") (part "RESISTOR0402-RES"))
    )
    (comp (ref "R147")
      (value "100k")
      (footprint "eagle-import:0402-RES")
      (fields (field (name "MPN") "ERJ-2RKF1003X"))
      (libsource (lib "eagle-import") (part "RESISTOR0402-RES"))
    )
    (comp (ref "R148")
      (value "2.2k")
      (footprint "eagle-import:0402-RES")
      (fields (field (name "MPN") "ERJ-2RKF2201X"))
      (libsource (lib "eagle-import") (part "RESISTOR0402-RES"))
    )
    (comp (ref "R149")
      (value "10k")
      (footprint "eagle-import:0402-RES")
      (fields (field (name "MPN") "ERJ-2RKF1002X"))
      (libsource (lib "eagle-import") (part "RESISTOR0402-RES"))
    )
    (comp (ref "R150")
      (value "2.2k")
      (footprint "eagle-import:0402-RES")
      (fields (field (name "MPN") "ERJ-2RKF2201X"))
      (libsource (lib "eagle-import") (part "RESISTOR0402-RES"))
    )
    (comp (ref "R151")
      (value "10k")
      (footprint "eagle-import:0402-RES")
      (fields (field (name "MPN") "ERJ-2RKF3302X"))
      (libsource (lib "eagle-import") (part "RESISTOR0402-RES"))
    )
    (comp (ref "R152")
      (value "56k")
      (footprint "eagle-import:0402-RES")
      (fields (field (name "MPN") "ERJ-2RKF1803X"))
      (libsource (lib "eagle-import") (part "RESISTOR0402-RES"))
    )
    (comp (ref "R153")
      (value "22k")
      (footprint "eagle-import:0402-RES")
      (fields (field (name "MPN") "ERJ-2RKF5602X"))
      (libsource (lib "eagle-import") (part "RESISTOR0402-RES"))
    )
    (comp (ref "R154")
      (value "4.7k")
      (footprint "eagle-import:0402-RES")
      (fields (field (name "MPN") "ERJ-2RKF4701X"))
      (libsource (lib "eagle-import") (part "RESISTOR0402-RES"))
    )
    (comp (ref "R155")
      (value "4.7k")
      (footprint "eagle-import:0402-RES")
      (fields (field (name "MPN") "ERJ-2RKF4701X"))
      (libsource (lib "eagle-import") (part "RESISTOR0402-RES"))
    )
    (comp (ref "R156")
      (value "1M")
      (footprint "eagle-import:0402-RES")
      (fields (field (name "MPN") "ERJ-2RKF1004X"))
      (libsource (lib "eagle-import") (part "RESISTOR0402-RES"))
    )
    (comp (ref "R157")
      (value "10k")
      (footprint "eagle-import:0402-RES")
      (fields (field (name "MPN") "ERJ-2RKF1002X"))
      (libsource (lib "eagle-import") (part "RESISTOR0402-RES"))
    )
    (comp (ref "R158")
      (value "1k")
      (footprint "eagle-import:0402-RES")
      (fields (field (name "MPN") "ERJ-2RKF1001X"))
      (libsource (lib "eagle-import") (part "RESISTOR0402-RES"))
    )
    (comp (ref "R159")
      (value "47k")
      (footprint "eagle-import:0402-RES")
      (fields (field (name "MPN") "ERJ-2RKF4702X"))
      (libsource (lib "eagle-import") (part "RESISTOR0402-RES"))
    )
    (comp (ref "R160")
      (value "1k")
      (footprint "eagle-import:0402-RES")
      (fields (field (name "MPN") "ERJ-2RKF1001X"))
      (libsource (lib "eagle-import") (part "RESISTOR0402-RES"))
    )
    (comp (ref "R161")
      (value "4.7k")
      (footprint "eagle-import:0402-RES")
      (fields (field (name "MPN") "ERJ-2RKF4701X"))
      (libsource (lib "eagle-import") (part "RESISTOR0402-RES"))
    )
    (comp (ref "R162")
      (value "4.7k")
      (footprint "eagle-import:0402-RES")
      (fields (field (name "MPN") "ERJ-2RKF4701X"))
      (libsource (lib "eagle-import") (part "RESISTOR0402-RES"))
    )
    (comp (ref "R163")
      (value "1k")
      (footprint "eagle-import:0402-RES")
      (fields (field (name "MPN") "ERJ-2RKF1001X"))
      (libsource (lib "eagle-import") (part "RESISTOR0402-RES"))
    )
    (comp (ref "R164")
      (value "180k")
      (footprint "eagle-import:0402-RES")
      (fields (field (name "MPN") "ERJ-2RKF1803X"))
      (libsource (lib "eagle-import") (part "RESISTOR0402-RES"))
    )
    (comp (ref "R165")
      (value "180k")
      (footprint "eagle-import:0402-RES")
      (fields (field (name "MPN") "ERJ-2RKF1803X"))
      (libsource (lib "eagle-import") (part "RESISTOR0402-RES"))
    )
    (comp (ref "R166")
      (value "470")
      (footprint "eagle-import:0402-RES")
      (fields (field (name "MPN") "ERJ-2RKF4700X"))
      (libsource (lib "eagle-import") (part "RESISTOR0402-RES"))
    )
    (comp (ref "R167")
      (value "560")
      (footprint "eagle-import:0402-RES")
      (fields (field (name "MPN") "ERJ-2RKF5600X"))
      (libsource (lib "eagle-import") (part "RESISTOR0402-RES"))
    )
    (comp (ref "R168")
      (value "100k")
      (footprint "eagle-import:0402-RES")
      (fields (field (name "MPN") "ERJ-2RKF1003X"))
      (libsource (lib "eagle-import") (part "RESISTOR0402-RES"))
    )
    (comp (ref "R169")
      (value "10k")
      (footprint "eagle-import:0402-RES")
      (fields (field (name "MPN") "ERJ-2RKF1002X"))
      (libsource (lib "eagle-import") (part "RESISTOR0402-RES"))
    )
    (comp (ref "R170")
      (value "10k")
      (footprint "eagle-import:0402-RES")
      (fields (field (name "MPN") "ERJ-2RKF1002X"))
      (libsource (lib "eagle-import") (part "RESISTOR0402-RES"))
    )
    (comp (ref "R171")
      (value "1M")
      (footprint "eagle-import:0402-RES")
      (fields (field (name "MPN") "ERJ-2RKF1004X"))
      (libsource (lib "eagle-import") (part "RESISTOR0402-RES"))
    )
    (comp (ref "R172")
      (value "18k")
      (footprint "eagle-import:0402-RES")
      (fields (field (name "MPN") "ERJ-2RKF1802X"))
      (libsource (lib "eagle-import") (part "RESISTOR0402-RES"))
    )
    (comp (ref "R173")
      (value "47k")
      (footprint "eagle-import:0402-RES")
      (fields (field (name "MPN") "ERJ-2RKF4702X"))
      (libsource (lib "eagle-import") (part "RESISTOR0402-RES"))
    )
    (comp (ref "R174")
      (value "10k")
      (footprint "eagle-import:0402-RES")
      (fields (field (name "MPN") "ERJ-2RKF1002X"))
      (libsource (lib "eagle-import") (part "RESISTOR0402-RES"))
    )
    (comp (ref "R175")
      (value "470")
      (footprint "eagle-import:0402-RES")
      (fields (field (name "MPN") "ERJ-2RKF4700X"))
      (libsource (lib "eagle-import") (part "RESISTOR0402-RES"))
    )
    (comp (ref "R197")
      (value "470")
      (footprint "eagle-import:0402-RES")
      (fields (field (name "MPN") "ERJ-2GE0R00X"))
      (libsource (lib "eagle-import") (part "RESISTOR0402-RES"))
    )
    (comp (ref "R198")
      (value "100k")
      (footprint "eagle-import:0402-RES")
      (fields (field (name "MPN") "ERJ-2RKF1003X"))
      (libsource (lib "eagle-import") (part "RESISTOR0402-RES"))
    )
    (comp (ref "R199")
      (value "100k")
      (footprint "eagle-import:0402-RES")
      (fields (field (name "MPN") "ERJ-2RKF1003X"))
      (libsource (lib "eagle-import") (part "RESISTOR0402-RES"))
    )
    (comp (ref "R200")
      (value "100k")
      (footprint "eagle-import:0402-RES")
      (fields (field (name "MPN") "ERJ-2RKF1003X"))
      (libsource (lib "eagle-import") (part "RESISTOR0402-RES"))
    )
    (comp (ref "R201")
      (value "100k")
      (footprint "eagle-import:0402-RES")
      (fields (field (name "MPN") "ERJ-2RKF1003X"))
      (libsource (lib "eagle-import") (part "RESISTOR0402-RES"))
    )
    (comp (ref "R202")
      (value "100k")
      (footprint "eagle-import:0402-RES")
      (fields (field (name "MPN") "ERJ-2RKF1003X"))
      (libsource (lib "eagle-import") (part "RESISTOR0402-RES"))
    )
    (comp (ref "R203")
      (value "100k")
      (footprint "eagle-import:0402-RES")
      (fields (field (name "MPN") "ERJ-2RKF1003X"))
      (libsource (lib "eagle-import") (part "RESISTOR0402-RES"))
    )
    (comp (ref "R204")
      (value "100k")
      (footprint "eagle-import:0402-RES")
      (fields (field (name "MPN") "ERJ-2RKF1003X"))
      (libsource (lib "eagle-import") (part "RESISTOR0402-RES"))
    )
    (comp (ref "SW2")
      (value "OS102011MA1Q")
      (footprint "eagle-import:OS102011MA1Q")
      (fields (field (name "MPN") "OS102011MA1QN1"))
      (libsource (lib "eagle-import") (part "OS102011MA1Q"))
    )
    (comp (ref "U13")
      (value "741G3157DBVR")
      (footprint "eagle-import:DBV_R-PDSO-G6")
      (fields (field (name "MPN") "SN74LVC1G3157DBVR"))
      (libsource (lib "eagle-import") (part "741G3157DBVR"))
    )
    (comp (ref "U19")
      (value "LME49721")
      (footprint "eagle-import:SO08")
      (fields (field (name "MPN") "LME49721MAX/NOPB"))
      (libsource (lib "eagle-import") (part "RC4559D"))
    )
    (comp (ref "U20")
      (value "LME49721")
      (footprint "eagle-import:SO08")
      (fields (field (name "MPN") "LME49721MAX/NOPB"))
      (libsource (lib "eagle-import") (part "RC4559D"))
    )
    (comp (ref "U21")
      (value "LME49721")
      (footprint "eagle-import:SO08")
      (fields (field (name "MPN") "LME49721MAX/NOPB"))
      (libsource (lib "eagle-import") (part "RC4559D"))
    )
    (comp (ref "C189")
      (value "220p")
      (footprint "eagle-import:0402-CAP")
      (fields (field (name "MPN") "GRM1555C1H221FA01D"))
      (libsource (lib "eagle-import") (part "CAP0402-CAP"))
    )
    (comp (ref "C190")
      (value "22p")
      (footprint "eagle-import:0402-CAP")
      (fields (field (name "MPN") "GRM1555C2A220JA01D"))
      (libsource (lib "eagle-import") (part "CAP0402-CAP"))
    )
    (comp (ref "C191")
      (value "10u")
      (footprint "eagle-import:C0805K")
      (fields (field (name "MPN") "GRM21BR71A106KA73L"))
      (libsource (lib "eagle-import") (part "C-EUC0805K"))
    )
    (comp (ref "C192")
      (value "2.2n")
      (footprint "eagle-import:0402-CAP")
      (fields (field (name "MPN") "GRM155R71H222JA01J"))
      (libsource (lib "eagle-import") (part "CAP0402-CAP"))
    )
    (comp (ref "C193")
      (value "2.2n")
      (footprint "eagle-import:0402-CAP")
      (fields (field (name "MPN") "GRM155R71H222JA01J"))
      (libsource (lib "eagle-import") (part "CAP0402-CAP"))
    )
    (comp (ref "C194")
      (value "150p")
      (footprint "eagle-import:0402-CAP")
      (fields (field (name "MPN") "GRM1555C1H151GA01D"))
      (libsource (lib "eagle-import") (part "CAP0402-CAP"))
    )
    (comp (ref "C195")
      (value "10u")
      (footprint "eagle-import:C0805K")
      (fields (field (name "MPN") "GRM21BR71A106KA73L"))
      (libsource (lib "eagle-import") (part "C-EUC0805K"))
    )
    (comp (ref "C196")
      (value "2.2n")
      (footprint "eagle-import:0402-CAP")
      (fields (field (name "MPN") "GRM155R71H222JA01J"))
      (libsource (lib "eagle-import") (part "CAP0402-CAP"))
    )
    (comp (ref "C197")
      (value "220p")
      (footprint "eagle-import:0402-CAP")
      (fields (field (name "MPN") "GRM1555C1H221FA01D"))
      (libsource (lib "eagle-import") (part "CAP0402-CAP"))
    )
    (comp (ref "C198")
      (value "10u")
      (footprint "eagle-import:C0805K")
      (fields (field (name "MPN") "GRM21BR71A106KA73L"))
      (libsource (lib "eagle-import") (part "C-EUC0805K"))
    )
    (comp (ref "C199")
      (value "2.2n")
      (footprint "eagle-import:0402-CAP")
      (fields (field (name "MPN") "GRM155R71H222JA01J"))
      (libsource (lib "eagle-import") (part "CAP0402-CAP"))
    )
    (comp (ref "C200")
      (value "22p")
      (footprint "eagle-import:0402-CAP")
      (fields (field (name "MPN") "GRM1555C2A220JA01D"))
      (libsource (lib "eagle-import") (part "CAP0402-CAP"))
    )
    (comp (ref "C201")
      (value "2.2n")
      (footprint "eagle-import:0402-CAP")
      (fields (field (name "MPN") "GRM155R71H222JA01J"))
      (libsource (lib "eagle-import") (part "CAP0402-CAP"))
    )
    (comp (ref "C202")
      (value "150p")
      (footprint "eagle-import:0402-CAP")
      (fields (field (name "MPN") "GRM1555C1H151GA01D"))
      (libsource (lib "eagle-import") (part "CAP0402-CAP"))
    )
    (comp (ref "C203")
      (value "10u")
      (footprint "eagle-import:C0805K")
      (fields (field (name "MPN") "GRM21BR71A106KA73L"))
      (libsource (lib "eagle-import") (part "C-EUC0805K"))
    )
    (comp (ref "C205")
      (value "100p")
      (footprint "eagle-import:0402-CAP")
      (fields (field (name "MPN") "GRM1555C1H101FA01J"))
      (libsource (lib "eagle-import") (part "CAP0402-CAP"))
    )
    (comp (ref "C206")
      (value "220p")
      (footprint "eagle-import:0402-CAP")
      (fields (field (name "MPN") "GRM1555C1H221FA01D"))
      (libsource (lib "eagle-import") (part "CAP0402-CAP"))
    )
    (comp (ref "C207")
      (value "10n")
      (footprint "eagle-import:0402-CAP")
      (fields (field (name "MPN") "GRM155R71E103KA01D"))
      (libsource (lib "eagle-import") (part "CAP0402-CAP"))
    )
    (comp (ref "C208")
      (value "18n")
      (footprint "eagle-import:0402-CAP")
      (fields (field (name "MPN") "GRM155R71H183KA12D"))
      (libsource (lib "eagle-import") (part "CAP0402-CAP"))
    )
    (comp (ref "C209")
      (value "0.1u")
      (footprint "eagle-import:0402-CAP")
      (fields (field (name "MPN") "GRM155R71C104JA88D"))
      (libsource (lib "eagle-import") (part "CAP0402-CAP"))
    )
    (comp (ref "C210")
      (value "10u")
      (footprint "eagle-import:C0805K")
      (fields (field (name "MPN") "GRM21BR71A106KA73L"))
      (libsource (lib "eagle-import") (part "resistor_C-EUC0805K"))
    )
    (comp (ref "C211")
      (value "10u")
      (footprint "eagle-import:C0805K")
      (fields (field (name "MPN") "GRM21BR71A106KA73L"))
      (libsource (lib "eagle-import") (part "resistor_C-EUC0805K"))
    )
    (comp (ref "C212")
      (value "680p")
      (footprint "eagle-import:0402-CAP")
      (fields (field (name "MPN") "GRM155R72A681KA01D"))
      (libsource (lib "eagle-import") (part "CAP0402-CAP"))
    )
    (comp (ref "C214")
      (value "100p")
      (footprint "eagle-import:0402-CAP")
      (fields (field (name "MPN") "GRM1555C1H101FA01J"))
      (libsource (lib "eagle-import") (part "CAP0402-CAP"))
    )
    (comp (ref "C223")
      (value "0.1u")
      (footprint "eagle-import:0402-CAP")
      (fields (field (name "MPN") "GRM155R71C104JA88D"))
      (libsource (lib "eagle-import") (part "CAP0402-CAP"))
    )
    (comp (ref "C224")
      (value "0.1u")
      (footprint "eagle-import:0402-CAP")
      (fields (field (name "MPN") "GRM155R71C104JA88D"))
      (libsource (lib "eagle-import") (part "CAP0402-CAP"))
    )
    (comp (ref "D7")
      (value "BAT54S")
      (footprint "eagle-import:SOT23")
      (fields (field (name "MPN") "BAT54SLT1G"))
      (libsource (lib "eagle-import") (part "BAT54S"))
    )
    (comp (ref "FB13")
      (value "BLM31PG121SN1L")
      (footprint "eagle-import:R1206")
      (libsource (lib "eagle-import") (part "R-EU_R1206"))
    )
    (comp (ref "FB14")
      (value "BLM31PG121SN1L")
      (footprint "eagle-import:R1206")
      (libsource (lib "eagle-import") (part "R-EU_R1206"))
    )
    (comp (ref "J9")
      (value "MONOSW3C")
      (footprint "eagle-import:NEUTRIK-NMJ4HCD2")
      (fields (field (name "MPN") "NMJ4HCD2"))
      (libsource (lib "eagle-import") (part "MONOSW3C"))
    )
    (comp (ref "J10")
      (value "MONOSW3C")
      (footprint "eagle-import:NEUTRIK-NMJ4HCD2")
      (fields (field (name "MPN") "NMJ4HCD2"))
      (libsource (lib "eagle-import") (part "MONOSW3C"))
    )
    (comp (ref "LSP3")
      (value "LSP13")
      (footprint "eagle-import:LSP13")
      (libsource (lib "eagle-import") (part "LSP13"))
    )
    (comp (ref "Q5")
      (value "2N7002ET1G")
      (footprint "eagle-import:SOT23")
      (libsource (lib "eagle-import") (part "MOSFET-NREFLOW"))
    )
    (comp (ref "Q6")
      (value "2N7002ET1G")
      (footprint "eagle-import:SOT23")
      (libsource (lib "eagle-import") (part "MOSFET-NREFLOW"))
    )
    (comp (ref "Q7")
      (value "2N7002ET1G")
      (footprint "eagle-import:SOT23")
      (libsource (lib "eagle-import") (part "MOSFET-NREFLOW"))
    )
    (comp (ref "R176")
      (value "12k")
      (footprint "eagle-import:0402-RES")
      (fields (field (name "MPN") "ERJ-2RKF1202X"))
      (libsource (lib "eagle-import") (part "RESISTOR0402-RES"))
    )
    (comp (ref "R177")
      (value "47k")
      (footprint "eagle-import:0402-RES")
      (fields (field (name "MPN") "ERJ-2RKF4702X"))
      (libsource (lib "eagle-import") (part "RESISTOR0402-RES"))
    )
    (comp (ref "R178")
      (value "12k")
      (footprint "eagle-import:0402-RES")
      (fields (field (name "MPN") "ERJ-2RKF1202X"))
      (libsource (lib "eagle-import") (part "RESISTOR0402-RES"))
    )
    (comp (ref "R179")
      (value "8.2k")
      (footprint "eagle-import:0402-RES")
      (fields (field (name "MPN") "ERJ-2RKF8201X"))
      (libsource (lib "eagle-import") (part "RESISTOR0402-RES"))
    )
    (comp (ref "R180")
      (value "12k")
      (footprint "eagle-import:0402-RES")
      (fields (field (name "MPN") "ERJ-2RKF1202X"))
      (libsource (lib "eagle-import") (part "RESISTOR0402-RES"))
    )
    (comp (ref "R181")
      (value "10k")
      (footprint "eagle-import:0402-RES")
      (fields (field (name "MPN") "ERJ-2RKF1002X"))
      (libsource (lib "eagle-import") (part "RESISTOR0402-RES"))
    )
    (comp (ref "R182")
      (value "330")
      (footprint "eagle-import:0402-RES")
      (fields (field (name "MPN") "ERJ-2RKF3300X"))
      (libsource (lib "eagle-import") (part "RESISTOR0402-RES"))
    )
    (comp (ref "R183")
      (value "100k")
      (footprint "eagle-import:0402-RES")
      (fields (field (name "MPN") "ERJ-2RKF1003X"))
      (libsource (lib "eagle-import") (part "RESISTOR0402-RES"))
    )
    (comp (ref "R184")
      (value "1k")
      (footprint "eagle-import:0402-RES")
      (fields (field (name "MPN") "ERJ-2RKF1001X"))
      (libsource (lib "eagle-import") (part "RESISTOR0402-RES"))
    )
    (comp (ref "R185")
      (value "1k")
      (footprint "eagle-import:0402-RES")
      (fields (field (name "MPN") "ERJ-2RKF1001X"))
      (libsource (lib "eagle-import") (part "RESISTOR0402-RES"))
    )
    (comp (ref "R186")
      (value "10k")
      (footprint "eagle-import:0402-RES")
      (fields (field (name "MPN") "ERJ-2RKF1002X"))
      (libsource (lib "eagle-import") (part "RESISTOR0402-RES"))
    )
    (comp (ref "R187")
      (value "12k")
      (footprint "eagle-import:0402-RES")
      (fields (field (name "MPN") "ERJ-2RKF1202X"))
      (libsource (lib "eagle-import") (part "RESISTOR0402-RES"))
    )
    (comp (ref "R188")
      (value "12k")
      (footprint "eagle-import:0402-RES")
      (fields (field (name "MPN") "ERJ-2RKF1202X"))
      (libsource (lib "eagle-import") (part "RESISTOR0402-RES"))
    )
    (comp (ref "R189")
      (value "8.2k")
      (footprint "eagle-import:0402-RES")
      (fields (field (name "MPN") "ERJ-2RKF8201X"))
      (libsource (lib "eagle-import") (part "RESISTOR0402-RES"))
    )
    (comp (ref "R190")
      (value "12k")
      (footprint "eagle-import:0402-RES")
      (fields (field (name "MPN") "ERJ-2RKF1202X"))
      (libsource (lib "eagle-import") (part "RESISTOR0402-RES"))
    )
    (comp (ref "R191")
      (value "47k")
      (footprint "eagle-import:0402-RES")
      (fields (field (name "MPN") "ERJ-2RKF4702X"))
      (libsource (lib "eagle-import") (part "RESISTOR0402-RES"))
    )
    (comp (ref "R192")
      (value "10k")
      (footprint "eagle-import:0402-RES")
      (fields (field (name "MPN") "ERJ-2RKF1002X"))
      (libsource (lib "eagle-import") (part "RESISTOR0402-RES"))
    )
    (comp (ref "R193")
      (value "330")
      (footprint "eagle-import:0402-RES")
      (fields (field (name "MPN") "ERJ-2RKF3300X"))
      (libsource (lib "eagle-import") (part "RESISTOR0402-RES"))
    )
    (comp (ref "R194")
      (value "100k")
      (footprint "eagle-import:0402-RES")
      (fields (field (name "MPN") "ERJ-2RKF1003X"))
      (libsource (lib "eagle-import") (part "RESISTOR0402-RES"))
    )
    (comp (ref "R195")
      (value "1k")
      (footprint "eagle-import:0402-RES")
      (fields (field (name "MPN") "ERJ-2RKF1001X"))
      (libsource (lib "eagle-import") (part "RESISTOR0402-RES"))
    )
    (comp (ref "R196")
      (value "1k")
      (footprint "eagle-import:0402-RES")
      (fields (field (name "MPN") "ERJ-2RKF1001X"))
      (libsource (lib "eagle-import") (part "RESISTOR0402-RES"))
    )
    (comp (ref "R205")
      (value "100")
      (footprint "eagle-import:0402-RES")
      (fields (field (name "MPN") "ERJ-2RKF1000X"))
      (libsource (lib "eagle-import") (part "RESISTOR0402-RES"))
    )
    (comp (ref "R206")
      (value "220k")
      (footprint "eagle-import:0402-RES")
      (fields (field (name "MPN") "ERJ-2RKF2203X"))
      (libsource (lib "eagle-import") (part "RESISTOR0402-RES"))
    )
    (comp (ref "R207")
      (value "22k")
      (footprint "eagle-import:0402-RES")
      (fields (field (name "MPN") "ERJ-2RKF2202X"))
      (libsource (lib "eagle-import") (part "RESISTOR0402-RES"))
    )
    (comp (ref "R208")
      (value "680k")
      (footprint "eagle-import:0402-RES")
      (fields (field (name "MPN") "ERJ-2RKF6803X"))
      (libsource (lib "eagle-import") (part "RESISTOR0402-RES"))
    )
    (comp (ref "R209")
      (value "22k")
      (footprint "eagle-import:0402-RES")
      (fields (field (name "MPN") "ERJ-2RKF2202X"))
      (libsource (lib "eagle-import") (part "RESISTOR0402-RES"))
    )
    (comp (ref "R210")
      (value "10k")
      (footprint "eagle-import:0402-RES")
      (fields (field (name "MPN") "ERJ-2RKF1002X"))
      (libsource (lib "eagle-import") (part "RESISTOR0402-RES"))
    )
    (comp (ref "R211")
      (value "15k")
      (footprint "eagle-import:0402-RES")
      (fields (field (name "MPN") "ERJ-2RKF1502X"))
      (libsource (lib "eagle-import") (part "RESISTOR0402-RES"))
    )
    (comp (ref "R212")
      (value "12k")
      (footprint "eagle-import:0402-RES")
      (fields (field (name "MPN") "ERJ-2RKF1202X"))
      (libsource (lib "eagle-import") (part "RESISTOR0402-RES"))
    )
    (comp (ref "R213")
      (value "2k")
      (footprint "eagle-import:0402-RES")
      (fields (field (name "MPN") "ERJ-2RKF2001X"))
      (libsource (lib "eagle-import") (part "RESISTOR0402-RES"))
    )
    (comp (ref "R214")
      (value "2k")
      (footprint "eagle-import:0402-RES")
      (fields (field (name "MPN") "ERJ-2RKF2001X"))
      (libsource (lib "eagle-import") (part "RESISTOR0402-RES"))
    )
    (comp (ref "R215")
      (value "1.3k")
      (footprint "eagle-import:0402-RES")
      (fields (field (name "MPN") "ERJ-2RKF1301X"))
      (libsource (lib "eagle-import") (part "RESISTOR0402-RES"))
    )
    (comp (ref "R216")
      (value "1.3k")
      (footprint "eagle-import:0402-RES")
      (fields (field (name "MPN") "ERJ-2RKF1301X"))
      (libsource (lib "eagle-import") (part "RESISTOR0402-RES"))
    )
    (comp (ref "U22")
      (value "LME49721")
      (footprint "eagle-import:SO08")
      (fields (field (name "MPN") "LME49721MAX/NOPB"))
      (libsource (lib "eagle-import") (part "RC4559D"))
    )
    (comp (ref "U23")
      (value "LME49721")
      (footprint "eagle-import:SO08")
      (fields (field (name "MPN") "LME49721MAX/NOPB"))
      (libsource (lib "eagle-import") (part "RC4559D"))
    )
    (comp (ref "U24")
      (value "LMV358")
      (footprint "eagle-import:SO08")
      (fields (field (name "MPN") "LMV358IDR"))
      (libsource (lib "eagle-import") (part "LMV358"))
    )
    (comp (ref "C7")
      (value "10u")
      (footprint "eagle-import:C0603K")
      (fields (field (name "MPN") "GRM188R61C106MA73D"))
      (libsource (lib "eagle-import") (part "C-EUC0603K"))
    )
    (comp (ref "C20")
      (value "0.1u")
      (footprint "eagle-import:C0402K")
      (fields (field (name "MPN") "GRM155R71C104JA88D"))
      (libsource (lib "eagle-import") (part "resistor_C-EUC0402K"))
    )
    (comp (ref "C33")
      (value "10n")
      (footprint "eagle-import:C0402K")
      (fields (field (name "MPN") "GRM155R71E103KA01D"))
      (libsource (lib "eagle-import") (part "resistor_C-EUC0402K"))
    )
    (comp (ref "C34")
      (value "0.1u")
      (footprint "eagle-import:C0402K")
      (fields (field (name "MPN") "GRM155R71C104JA88D"))
      (libsource (lib "eagle-import") (part "resistor_C-EUC0402K"))
    )
    (comp (ref "C35")
      (value "0.1u")
      (footprint "eagle-import:C0402K")
      (fields (field (name "MPN") "GRM155R71C104JA88D"))
      (libsource (lib "eagle-import") (part "resistor_C-EUC0402K"))
    )
    (comp (ref "C36")
      (value "0.1u")
      (footprint "eagle-import:C0402K")
      (fields (field (name "MPN") "GRM155R71C104JA88D"))
      (libsource (lib "eagle-import") (part "resistor_C-EUC0402K"))
    )
    (comp (ref "C37")
      (value "10n")
      (footprint "eagle-import:C0402K")
      (fields (field (name "MPN") "GRM155R71E103KA01D"))
      (libsource (lib "eagle-import") (part "resistor_C-EUC0402K"))
    )
    (comp (ref "C44")
      (value "4.7u")
      (footprint "eagle-import:C0603K")
      (fields (field (name "MPN") "GRM188R60J475KE19D"))
      (libsource (lib "eagle-import") (part "C-EUC0603K"))
    )
    (comp (ref "C47")
      (value "0.1u")
      (footprint "eagle-import:C0402K")
      (fields (field (name "MPN") "GRM155R71C104JA88D"))
      (libsource (lib "eagle-import") (part "resistor_C-EUC0402K"))
    )
    (comp (ref "C58")
      (value "10n")
      (footprint "eagle-import:C0402K")
      (fields (field (name "MPN") "GRM155R71E103KA01D"))
      (libsource (lib "eagle-import") (part "resistor_C-EUC0402K"))
    )
    (comp (ref "C61")
      (value "0.1u")
      (footprint "eagle-import:C0402K")
      (fields (field (name "MPN") "GRM155R71C104JA88D"))
      (libsource (lib "eagle-import") (part "resistor_C-EUC0402K"))
    )
    (comp (ref "C68")
      (value "0.1u")
      (footprint "eagle-import:C0402K")
      (fields (field (name "MPN") "GRM155R71C104JA88D"))
      (libsource (lib "eagle-import") (part "resistor_C-EUC0402K"))
    )
    (comp (ref "C70")
      (value "0.1u")
      (footprint "eagle-import:C0402K")
      (fields (field (name "MPN") "GRM155R71C104JA88D"))
      (libsource (lib "eagle-import") (part "resistor_C-EUC0402K"))
    )
    (comp (ref "C76")
      (value "4.7u")
      (footprint "eagle-import:C0603K")
      (fields (field (name "MPN") "GRM188R60J475KE19D"))
      (libsource (lib "eagle-import") (part "C-EUC0603K"))
    )
    (comp (ref "C78")
      (value "0.1u")
      (footprint "eagle-import:C0402K")
      (fields (field (name "MPN") "GRM155R71C104JA88D"))
      (libsource (lib "eagle-import") (part "resistor_C-EUC0402K"))
    )
    (comp (ref "C79")
      (value "0.1u")
      (footprint "eagle-import:C0402K")
      (fields (field (name "MPN") "GRM155R71C104JA88D"))
      (libsource (lib "eagle-import") (part "resistor_C-EUC0402K"))
    )
    (comp (ref "C80")
      (value "0.1u")
      (footprint "eagle-import:C0402K")
      (fields (field (name "MPN") "GRM155R71C104JA88D"))
      (libsource (lib "eagle-import") (part "resistor_C-EUC0402K"))
    )
    (comp (ref "C92")
      (value "0.1u")
      (footprint "eagle-import:C0402K")
      (fields (field (name "MPN") "GRM155R71C104JA88D"))
      (libsource (lib "eagle-import") (part "resistor_C-EUC0402K"))
    )
    (comp (ref "C93")
      (value "10n")
      (footprint "eagle-import:C0402K")
      (fields (field (name "MPN") "GRM155R71E103KA01D"))
      (libsource (lib "eagle-import") (part "resistor_C-EUC0402K"))
    )
    (comp (ref "D1")
      (value "MBR0520LT")
      (footprint "eagle-import:SOD123")
      (fields (field (name "MPN") "MBR0520LT1G"))
      (libsource (lib "eagle-import") (part "MBR0520LT"))
    )
    (comp (ref "D3")
      (value "MBR0520LT")
      (footprint "eagle-import:SOD123")
      (fields (field (name "MPN") "MBR0520LT1G"))
      (libsource (lib "eagle-import") (part "MBR0520LT"))
    )
    (comp (ref "D4")
      (value "MBR0520LT")
      (footprint "eagle-import:SOD123")
      (fields (field (name "MPN") "MBR0520LT1G"))
      (libsource (lib "eagle-import") (part "MBR0520LT"))
    )
    (comp (ref "D5")
      (value "MBR0520LT")
      (footprint "eagle-import:SOD123")
      (fields (field (name "MPN") "MBR0520LT1G"))
      (libsource (lib "eagle-import") (part "MBR0520LT"))
    )
    (comp (ref "DS1")
      (value "GREEN")
      (footprint "eagle-import:CHIPLED_1206")
      (fields (field (name "MPN") "LTST-C230KGKT"))
      (libsource (lib "eagle-import") (part "LEDCHIPLED_1206"))
    )
    (comp (ref "J2")
      (value "USB-B-SMT")
      (footprint "eagle-import:USB-B-SMT")
      (fields (field (name "MPN") "M701-370442"))
      (libsource (lib "eagle-import") (part "USB-B-SMT"))
    )
    (comp (ref "L1")
      (value "BLM21PG221SN1")
      (footprint "eagle-import:0805")
      (fields (field (name "MPN") "BLM21PG221SN1D"))
      (libsource (lib "eagle-import") (part "INDUCTOR0805"))
    )
    (comp (ref "L4")
      (value "BLM21PG21SN1")
      (footprint "eagle-import:0805")
      (fields (field (name "MPN") "BLM21PG221SN1D"))
      (libsource (lib "eagle-import") (part "INDUCTOR0805"))
    )
    (comp (ref "L5")
      (value "BLM21PG221SN1")
      (footprint "eagle-import:0805")
      (fields (field (name "MPN") "BLM21PG221SN1D"))
      (libsource (lib "eagle-import") (part "INDUCTOR0805"))
    )
    (comp (ref "R12")
      (value "560")
      (footprint "eagle-import:0402-RES")
      (fields (field (name "MPN") "ERJ-2RKF2200X"))
      (libsource (lib "eagle-import") (part "RESISTOR0402-RES"))
    )
    (comp (ref "R19")
      (value "10k")
      (footprint "eagle-import:0402-RES")
      (fields (field (name "MPN") "ERJ-2RKF1002X"))
      (libsource (lib "eagle-import") (part "RESISTOR0402-RES"))
    )
    (comp (ref "R20")
      (value "NC")
      (footprint "eagle-import:0402-RES")
      (libsource (lib "eagle-import") (part "RESISTOR0402-RES"))
    )
    (comp (ref "R21")
      (value "2.2k")
      (footprint "eagle-import:0402-RES")
      (fields (field (name "MPN") "ERJ-2RKF2201X"))
      (libsource (lib "eagle-import") (part "RESISTOR0402-RES"))
    )
    (comp (ref "R23")
      (value "0")
      (footprint "eagle-import:0402-RES")
      (fields (field (name "MPN") "ERJ-2GE0R00X"))
      (libsource (lib "eagle-import") (part "RESISTOR0402-RES"))
    )
    (comp (ref "R24")
      (value "NC")
      (footprint "eagle-import:0402-RES")
      (libsource (lib "eagle-import") (part "RESISTOR0402-RES"))
    )
    (comp (ref "R27")
      (value "0")
      (footprint "eagle-import:0402-RES")
      (fields (field (name "MPN") "ERJ-2GE0R00X"))
      (libsource (lib "eagle-import") (part "RESISTOR0402-RES"))
    )
    (comp (ref "R28")
      (value "12k")
      (footprint "eagle-import:0402-RES")
      (fields (field (name "MPN") "ERJ-2RKF1202X"))
      (libsource (lib "eagle-import") (part "RESISTOR0402-RES"))
    )
    (comp (ref "R30")
      (value "0")
      (footprint "eagle-import:0402-RES")
      (fields (field (name "MPN") "ERJ-2GE0R00X"))
      (libsource (lib "eagle-import") (part "RESISTOR0402-RES"))
    )
    (comp (ref "R32")
      (value "0")
      (footprint "eagle-import:0402-RES")
      (fields (field (name "MPN") "ERJ-2GE0R00X"))
      (libsource (lib "eagle-import") (part "RESISTOR0402-RES"))
    )
    (comp (ref "R35")
      (value "0")
      (footprint "eagle-import:0402-RES")
      (fields (field (name "MPN") "ERJ-2GE0R00X"))
      (libsource (lib "eagle-import") (part "RESISTOR0402-RES"))
    )
    (comp (ref "R36")
      (value "10k")
      (footprint "eagle-import:0402-RES")
      (fields (field (name "MPN") "ERJ-2RKF1002X"))
      (libsource (lib "eagle-import") (part "RESISTOR0402-RES"))
    )
    (comp (ref "R39")
      (value "33")
      (footprint "eagle-import:0402-RES")
      (fields (field (name "MPN") "ERJ-2RKF33R0X"))
      (libsource (lib "eagle-import") (part "RESISTOR0402-RES"))
    )
    (comp (ref "R40")
      (value "NC")
      (footprint "eagle-import:0402-RES")
      (libsource (lib "eagle-import") (part "RESISTOR0402-RES"))
    )
    (comp (ref "R42")
      (value "10k")
      (footprint "eagle-import:0402-RES")
      (fields (field (name "MPN") "ERJ-2RKF1002X"))
      (libsource (lib "eagle-import") (part "RESISTOR0402-RES"))
    )
    (comp (ref "R43")
      (value "10k")
      (footprint "eagle-import:0402-RES")
      (fields (field (name "MPN") "ERJ-2RKF1002X"))
      (libsource (lib "eagle-import") (part "RESISTOR0402-RES"))
    )
    (comp (ref "R44")
      (value "10k")
      (footprint "eagle-import:0402-RES")
      (fields (field (name "MPN") "ERJ-2RKF1002X"))
      (libsource (lib "eagle-import") (part "RESISTOR0402-RES"))
    )
    (comp (ref "R45")
      (value "NC")
      (footprint "eagle-import:0402-RES")
      (libsource (lib "eagle-import") (part "RESISTOR0402-RES"))
    )
    (comp (ref "R46")
      (value "33")
      (footprint "eagle-import:0402-RES")
      (fields (field (name "MPN") "ERJ-2RKF33R0X"))
      (libsource (lib "eagle-import") (part "RESISTOR0402-RES"))
    )
    (comp (ref "R47")
      (value "33")
      (footprint "eagle-import:0402-RES")
      (fields (field (name "MPN") "ERJ-2RKF33R0X"))
      (libsource (lib "eagle-import") (part "RESISTOR0402-RES"))
    )
    (comp (ref "R48")
      (value "33")
      (footprint "eagle-import:0402-RES")
      (fields (field (name "MPN") "ERJ-2RKF33R0X"))
      (libsource (lib "eagle-import") (part "RESISTOR0402-RES"))
    )
    (comp (ref "R49")
      (value "33")
      (footprint "eagle-import:0402-RES")
      (fields (field (name "MPN") "ERJ-2RKF33R0X"))
      (libsource (lib "eagle-import") (part "RESISTOR0402-RES"))
    )
    (comp (ref "R53")
      (value "33")
      (footprint "eagle-import:0402-RES")
      (fields (field (name "MPN") "ERJ-2RKF33R0X"))
      (libsource (lib "eagle-import") (part "RESISTOR0402-RES"))
    )
    (comp (ref "R57")
      (value "4.7k")
      (footprint "eagle-import:0402-RES")
      (fields (field (name "MPN") "ERJ-2RKF4701X"))
      (libsource (lib "eagle-import") (part "RESISTOR0402-RES"))
    )
    (comp (ref "R58")
      (value "33")
      (footprint "eagle-import:0402-RES")
      (fields (field (name "MPN") "ERJ-2RKF33R0X"))
      (libsource (lib "eagle-import") (part "RESISTOR0402-RES"))
    )
    (comp (ref "U2")
      (value "AT93C46A-10TQ-2.7")
      (footprint "eagle-import:TSSOP8")
      (fields (field (name "MPN") "AT93C46D-TH-T"))
      (libsource (lib "eagle-import") (part "AT93C46A-10?Q-2.7T"))
    )
    (comp (ref "U6")
      (value "FT2232HL")
      (footprint "eagle-import:LQFP-10X10-64")
      (fields (field (name "MPN") "FT2232HL-REEL"))
      (libsource (lib "eagle-import") (part "FT2232H"))
    )
    (comp (ref "U7")
      (value "TPD2E001IDRLRQ1")
      (footprint "eagle-import:SOT50P160X60-5N")
      (fields (field (name "MPN") "TPD2E001DRLR"))
      (libsource (lib "eagle-import") (part "TPD2E001IDRLRQ1"))
    )
    (comp (ref "U8")
      (value "74LVC1G175DBVSOT95")
      (footprint "eagle-import:SOT95P280X145-6N")
      (fields (field (name "MPN") "SN74LVC1G175DBVT"))
      (libsource (lib "eagle-import") (part "74LVC1G175SOT95DBV"))
    )
  )
  (nets
    (net (code "1") (name "+9V") (class "Default")
      (node (ref "D1") (pin "A") (pinfunction "A_A") (pintype "passive"))
      (node (ref "SW2") (pin "1") (pinfunction "S_1") (pintype "passive"))
    )
    (net (code "2") (name "A-CENTER") (class "Default")
      (node (ref "J5") (pin "10") (pinfunction "10_10") (pintype "passive"))
      (node (ref "TP5") (pin "TP") (pinfunction "TP_TP") (pintype "input"))
    )
    (net (code "3") (name "A-DOWN") (class "Default")
      (node (ref "J5") (pin "6") (pinfunction "6_6") (pintype "passive"))
      (node (ref "TP3") (pin "TP") (pinfunction "TP_TP") (pintype "input"))
    )
    (net (code "4") (name "A-LEFT") (class "Default")
      (node (ref "J5") (pin "18") (pinfunction "18_18") (pintype "passive"))
      (node (ref "TP7") (pin "TP") (pinfunction "TP_TP") (pintype "input"))
    )
    (net (code "5") (name "A-RIGHT") (class "Default")
      (node (ref "J5") (pin "2") (pinfunction "2_2") (pintype "passive"))
      (node (ref "TP10") (pin "TP") (pinfunction "TP_TP") (pintype "input"))
    )
    (net (code "6") (name "A-UP") (class "Default")
      (node (ref "J5") (pin "14") (pinfunction "14_14") (pintype "passive"))
      (node (ref "TP6") (pin "TP") (pinfunction "TP_TP") (pintype "input"))
    )
    (net (code "7") (name "AGND") (class "Default")
      (node (ref "C2") (pin "2") (pinfunction "2_2") (pintype "passive"))
      (node (ref "C2-2") (pin "2") (pinfunction "2_2") (pintype "passive"))
      (node (ref "C3") (pin "2") (pinfunction "2_2") (pintype "passive"))
      (node (ref "C3-2") (pin "2") (pinfunction "2_2") (pintype "passive"))
      (node (ref "C43") (pin "2") (pinfunction "2_2") (pintype "passive"))
      (node (ref "C43-2") (pin "2") (pinfunction "2_2") (pintype "passive"))
      (node (ref "C49") (pin "2") (pinfunction "2_2") (pintype "passive"))
      (node (ref "C49-2") (pin "2") (pinfunction "2_2") (pintype "passive"))
      (node (ref "C50") (pin "2") (pinfunction "2_2") (pintype "passive"))
      (node (ref "C50-2") (pin "2") (pinfunction "2_2") (pintype "passive"))
      (node (ref "C57") (pin "2") (pinfunction "2_2") (pintype "passive"))
      (node (ref "C57-2") (pin "2") (pinfunction "2_2") (pintype "passive"))
      (node (ref "C73") (pin "2") (pinfunction "2_2") (pintype "passive"))
      (node (ref "C73-2") (pin "2") (pinfunction "2_2") (pintype "passive"))
      (node (ref "C85") (pin "2") (pinfunction "2_2") (pintype "passive"))
      (node (ref "C85-2") (pin "2") (pinfunction "2_2") (pintype "passive"))
      (node (ref "C86") (pin "2") (pinfunction "2_2") (pintype "passive"))
      (node (ref "C86-2") (pin "2") (pinfunction "2_2") (pintype "passive"))
      (node (ref "C88") (pin "2") (pinfunction "2_2") (pintype "passive"))
      (node (ref "C88-2") (pin "2") (pinfunction "2_2") (pintype "passive"))
      (node (ref "FB1") (pin "2") (pinfunction "2_2") (pintype "passive"))
      (node (ref "FB1-2") (pin "2") (pinfunction "2_2") (pintype "passive"))
      (node (ref "U4") (pin "A1") (pinfunction "VSSA_PLL_A1") (pintype "power_in"))
      (node (ref "U4") (pin "B6") (pinfunction "VSSA_ANA_B6") (pintype "power_in"))
      (node (ref "U4") (pin "C9") (pinfunction "VSSA_ANA_C9") (pintype "power_in"))
      (node (ref "U4") (pin "F13") (pinfunction "USB_VSSPLL_F13") (pintype "power_in"))
      (node (ref "U4") (pin "J12") (pinfunction "USB_VSSA1P3_J12") (pintype "power_in"))
      (node (ref "U5") (pin "A1") (pinfunction "VSSA_PLL_A1") (pintype "power_in"))
      (node (ref "U5") (pin "B6") (pinfunction "VSSA_ANA_B6") (pintype "power_in"))
      (node (ref "U5") (pin "C9") (pinfunction "VSSA_ANA_C9") (pintype "power_in"))
      (node (ref "U5") (pin "F13") (pinfunction "USB_VSSPLL_F13") (pintype "power_in"))
      (node (ref "U5") (pin "J12") (pinfunction "USB_VSSA1P3_J12") (pintype "power_in"))
    )
    (net (code "8") (name "AIC3204I2C_ENN") (class "Default")
      (node (ref "R136") (pin "2") (pinfunction "2_2") (pintype "passive"))
      (node (ref "U18") (pin "19") (pinfunction "~{OE}_19") (pintype "input"))
      (node (ref "U4") (pin "J2") (pinfunction "LCD_D[2]/GP[12]_J2") (pintype "tri_state"))
    )
    (net (code "9") (name "AIC_IISCLK") (class "Default")
      (node (ref "R92") (pin "1") (pinfunction "1_1") (pintype "passive"))
      (node (ref "U17") (pin "2") (pinfunction "BCLK_2") (pintype "bidirectional"))
    )
    (net (code "10") (name "AIC_IISD0") (class "Default")
      (node (ref "R94") (pin "1") (pinfunction "1_1") (pintype "passive"))
      (node (ref "U17") (pin "4") (pinfunction "DIN/MFP1_4") (pintype "input"))
    )
    (net (code "11") (name "AIC_IISD1") (class "Default")
      (node (ref "R95") (pin "1") (pinfunction "1_1") (pintype "passive"))
      (node (ref "U17") (pin "5") (pinfunction "DOUT/MFP2_5") (pintype "output"))
    )
    (net (code "12") (name "AIC_IISFS") (class "Default")
      (node (ref "R93") (pin "1") (pinfunction "1_1") (pintype "passive"))
      (node (ref "U17") (pin "3") (pinfunction "WCLK_3") (pintype "bidirectional"))
    )
    (net (code "13") (name "AIC_LINE2L") (class "Default")
      (node (ref "C17") (pin "1") (pinfunction "1_1") (pintype "passive"))
      (node (ref "R110") (pin "1") (pinfunction "1_1") (pintype "passive"))
      (node (ref "R175") (pin "2") (pinfunction "2_2") (pintype "passive"))
    )
    (net (code "14") (name "AIC_LINE2R") (class "Default")
      (node (ref "C16") (pin "1") (pinfunction "1_1") (pintype "passive"))
      (node (ref "R111") (pin "2") (pinfunction "2_2") (pintype "passive"))
      (node (ref "R197") (pin "2") (pinfunction "2_2") (pintype "passive"))
    )
    (net (code "15") (name "AIC_MCLK") (class "Default")
      (node (ref "R138") (pin "2") (pinfunction "2_2") (pintype "passive"))
      (node (ref "U17") (pin "1") (pinfunction "MCLK_(1)_1") (pintype "input"))
      (node (ref "U18") (pin "11") (pinfunction "B8_11") (pintype "bidirectional"))
    )
    (net (code "16") (name "AIC_MODE_SEL") (class "Default")
      (node (ref "R104") (pin "2") (pinfunction "2_2") (pintype "passive"))
      (node (ref "U17") (pin "12") (pinfunction "SPI_SELECT_12") (pintype "input"))
    )
    (net (code "17") (name "AIC_RST") (class "Default")
      (node (ref "R137") (pin "1") (pinfunction "1_1") (pintype "passive"))
      (node (ref "R141") (pin "1") (pinfunction "1_1") (pintype "passive"))
      (node (ref "R8") (pin "1") (pinfunction "1_1") (pintype "passive"))
      (node (ref "U17") (pin "31") (pinfunction "RESETN_31") (pintype "input"))
    )
    (net (code "18") (name "ANA_LDO_OUT") (class "Default")
      (node (ref "C73") (pin "1") (pinfunction "1_1") (pintype "passive"))
      (node (ref "C85") (pin "1") (pinfunction "1_1") (pintype "passive"))
      (node (ref "C86") (pin "1") (pinfunction "1_1") (pintype "passive"))
      (node (ref "U4") (pin "B7") (pinfunction "VDDA_ANA_B7") (pintype "power_in"))
      (node (ref "U4") (pin "B9") (pinfunction "ANA_LDOO_B9") (pintype "power_in"))
      (node (ref "U4") (pin "C7") (pinfunction "VDDA_PLL_C7") (pintype "power_in"))
    )
    (net (code "19") (name "ANA_LDO_OUT2") (class "Default")
      (node (ref "C73-2") (pin "1") (pinfunction "1_1") (pintype "passive"))
      (node (ref "C85-2") (pin "1") (pinfunction "1_1") (pintype "passive"))
      (node (ref "C86-2") (pin "1") (pinfunction "1_1") (pintype "passive"))
      (node (ref "J7") (pin "14") (pinfunction "14_14") (pintype "passive"))
      (node (ref "U5") (pin "B7") (pinfunction "VDDA_ANA_B7") (pintype "power_in"))
      (node (ref "U5") (pin "B9") (pinfunction "ANA_LDOO_B9") (pintype "power_in"))
      (node (ref "U5") (pin "C7") (pinfunction "VDDA_PLL_C7") (pintype "power_in"))
    )
    (net (code "20") (name "BAT+") (class "Default")
      (node (ref "J8") (pin "2") (pinfunction "2_2") (pintype "passive"))
      (node (ref "JP1") (pin "2") (pinfunction "2_2") (pintype "passive"))
    )
    (net (code "21") (name "BAT-") (class "Default")
      (node (ref "J3") (pin "R") (pinfunction "R_R") (pintype "passive"))
      (node (ref "J3") (pin "RN") (pinfunction "RN_RN") (pintype "passive"))
      (node (ref "J8") (pin "1") (pinfunction "1_1") (pintype "passive"))
      (node (ref "JP1") (pin "1") (pinfunction "1_1") (pintype "passive"))
    )
    (net (code "22") (name "C2-CENTER") (class "Default")
      (node (ref "J5") (pin "12") (pinfunction "12_12") (pintype "passive"))
      (node (ref "R83X") (pin "1") (pinfunction "1_1") (pintype "passive"))
      (node (ref "U5") (pin "N7") (pinfunction "LCD_D[5]/GP[15]_N7") (pintype "tri_state"))
    )
    (net (code "23") (name "C2-DOWN") (class "Default")
      (node (ref "J5") (pin "8") (pinfunction "8_8") (pintype "passive"))
      (node (ref "U5") (pin "P3") (pinfunction "LCD_D[6]/GP[16]_P3") (pintype "tri_state"))
    )
    (net (code "24") (name "C2-LEFT") (class "Default")
      (node (ref "J5") (pin "20") (pinfunction "20_20") (pintype "passive"))
      (node (ref "U5") (pin "N5") (pinfunction "LCD_D[3]/GP[13]_N5") (pintype "tri_state"))
    )
    (net (code "25") (name "C2-RIGHT") (class "Default")
      (node (ref "J5") (pin "4") (pinfunction "4_4") (pintype "passive"))
      (node (ref "U5") (pin "P8") (pinfunction "LCD_D[7]/GP[17]_P8") (pintype "tri_state"))
    )
    (net (code "26") (name "C2-UP") (class "Default")
      (node (ref "J5") (pin "16") (pinfunction "16_16") (pintype "passive"))
      (node (ref "U5") (pin "P2") (pinfunction "LCD_D[4]/GP[14]_P2") (pintype "tri_state"))
    )
    (net (code "27") (name "CLEAN") (class "Default")
      (node (ref "Q10") (pin "B") (pinfunction "B_B") (pintype "passive"))
      (node (ref "U5") (pin "M8") (pinfunction "SD0_CLK/I2S0_CLK/GP[0]_M8") (pintype "bidirectional"))
    )
    (net (code "28") (name "CLEAN_C") (class "Default")
      (node (ref "C188") (pin "1") (pinfunction "1_1") (pintype "passive"))
      (node (ref "C207") (pin "1") (pinfunction "1_1") (pintype "passive"))
      (node (ref "R172") (pin "2") (pinfunction "2_2") (pintype "passive"))
      (node (ref "U20") (pin "7") (pinfunction "OUT_7") (pintype "output"))
    )
    (net (code "29") (name "CLEAN_S") (class "Default")
      (node (ref "C188") (pin "2") (pinfunction "2_2") (pintype "passive"))
      (node (ref "R197") (pin "1") (pinfunction "1_1") (pintype "passive"))
      (node (ref "R199") (pin "1") (pinfunction "1_1") (pintype "passive"))
      (node (ref "R65") (pin "2") (pinfunction "2_2") (pintype "passive"))
      (node (ref "U13") (pin "3") (pinfunction "A_3") (pintype "bidirectional"))
    )
    (net (code "30") (name "CLK12MHZ") (class "Default")
      (node (ref "U14") (pin "3") (pinfunction "OUT_3") (pintype "output"))
      (node (ref "U15X") (pin "1") (pinfunction "CLKIN_1") (pintype "input"))
    )
    (net (code "31") (name "CLKOUT2") (class "Default")
      (node (ref "R117-2") (pin "2") (pinfunction "2_2") (pintype "passive"))
      (node (ref "TP4-2") (pin "TP") (pinfunction "TP_TP") (pintype "input"))
      (node (ref "U5") (pin "A2") (pinfunction "CLKOUT_A2") (pintype "output"))
    )
    (net (code "32") (name "CLK_12MHZ") (class "Default")
      (node (ref "R227X") (pin "2") (pinfunction "2_2") (pintype "passive"))
      (node (ref "R23") (pin "1") (pinfunction "1_1") (pintype "passive"))
    )
    (net (code "33") (name "CLK_SEL") (class "Default")
      (node (ref "R33") (pin "2") (pinfunction "2_2") (pintype "passive"))
      (node (ref "U4") (pin "D1") (pinfunction "CLK_SEL_D1") (pintype "input"))
    )
    (net (code "34") (name "CLK_SEL2") (class "Default")
      (node (ref "R33-2") (pin "2") (pinfunction "2_2") (pintype "passive"))
      (node (ref "U5") (pin "D1") (pinfunction "CLK_SEL_D1") (pintype "input"))
    )
    (net (code "35") (name "CODEC_AVDD") (class "Default")
      (node (ref "C116") (pin "1") (pinfunction "1_1") (pintype "passive"))
      (node (ref "C19") (pin "1") (pinfunction "1_1") (pintype "passive"))
      (node (ref "R107") (pin "1") (pinfunction "1_1") (pintype "passive"))
      (node (ref "U17") (pin "24") (pinfunction "AVDD_24") (pintype "power_in"))
    )
    (net (code "36") (name "CODEC_DVDD") (class "Default")
      (node (ref "C108") (pin "1") (pinfunction "1_1") (pintype "passive"))
      (node (ref "C11") (pin "1") (pinfunction "1_1") (pintype "passive"))
      (node (ref "R106") (pin "2") (pinfunction "2_2") (pintype "passive"))
      (node (ref "U17") (pin "29") (pinfunction "DVDD_29") (pintype "power_in"))
    )
    (net (code "37") (name "CODEC_IOVDD") (class "Default")
      (node (ref "C105") (pin "1") (pinfunction "1_1") (pintype "passive"))
      (node (ref "C8") (pin "1") (pinfunction "1_1") (pintype "passive"))
      (node (ref "R5") (pin "2") (pinfunction "2_2") (pintype "passive"))
      (node (ref "U17") (pin "6") (pinfunction "IOVDD_6") (pintype "power_in"))
    )
    (net (code "38") (name "CODEC_LDOIN") (class "Default")
      (node (ref "C111") (pin "1") (pinfunction "1_1") (pintype "passive"))
      (node (ref "C12") (pin "1") (pinfunction "1_1") (pintype "passive"))
      (node (ref "R108") (pin "1") (pinfunction "1_1") (pintype "passive"))
      (node (ref "U17") (pin "26") (pinfunction "LDOIN_26") (pintype "power_in"))
    )
    (net (code "39") (name "CONN_HP_LOUT") (class "Default")
      (node (ref "C14") (pin "-") (pinfunction "-_-") (pintype "passive"))
      (node (ref "J4") (pin "2") (pinfunction "T_2") (pintype "passive"))
    )
    (net (code "40") (name "CONN_HP_ROUT") (class "Default")
      (node (ref "C13") (pin "-") (pinfunction "-_-") (pintype "passive"))
      (node (ref "J4") (pin "3") (pinfunction "R_3") (pintype "passive"))
    )
    (net (code "41") (name "CPU1_LED") (class "Default")
      (node (ref "DS2") (pin "A") (pinfunction "A_A") (pintype "passive"))
      (node (ref "U4") (pin "P8") (pinfunction "LCD_D[7]/GP[17]_P8") (pintype "tri_state"))
    )
    (net (code "42") (name "CPU2_CLK_12MHZ") (class "Default")
      (node (ref "R226X") (pin "2") (pinfunction "2_2") (pintype "passive"))
      (node (ref "R38-2") (pin "1") (pinfunction "1_1") (pintype "passive"))
    )
    (net (code "43") (name "CPU2_LED") (class "Default")
      (node (ref "D3X") (pin "A") (pinfunction "A_A") (pintype "passive"))
      (node (ref "U5") (pin "M12") (pinfunction "SD1_D3/GP[11]_M12") (pintype "bidirectional"))
    )
    (net (code "44") (name "CPU_CLK_12MHZ") (class "Default")
      (node (ref "R229X") (pin "2") (pinfunction "2_2") (pintype "passive"))
      (node (ref "R38") (pin "1") (pinfunction "1_1") (pintype "passive"))
    )
    (net (code "45") (name "DCIN") (class "Default")
      (node (ref "CF1") (pin "1") (pinfunction "1_1") (pintype "passive"))
      (node (ref "J8") (pin "3") (pinfunction "3_3") (pintype "passive"))
    )
    (net (code "46") (name "DGND") (class "Default")
      (node (ref "C1") (pin "2") (pinfunction "2_2") (pintype "passive"))
      (node (ref "C1-2") (pin "2") (pinfunction "2_2") (pintype "passive"))
      (node (ref "C10") (pin "2") (pinfunction "2_2") (pintype "passive"))
      (node (ref "C104") (pin "2") (pinfunction "2_2") (pintype "passive"))
      (node (ref "C105") (pin "2") (pinfunction "2_2") (pintype "passive"))
      (node (ref "C108") (pin "2") (pinfunction "2_2") (pintype "passive"))
      (node (ref "C11") (pin "2") (pinfunction "2_2") (pintype "passive"))
      (node (ref "C122") (pin "2") (pinfunction "2_2") (pintype "passive"))
      (node (ref "C15") (pin "2") (pinfunction "2_2") (pintype "passive"))
      (node (ref "C168X") (pin "2") (pinfunction "2_2") (pintype "passive"))
      (node (ref "C169X") (pin "2") (pinfunction "2_2") (pintype "passive"))
      (node (ref "C185") (pin "2") (pinfunction "2_2") (pintype "passive"))
      (node (ref "C20") (pin "2") (pinfunction "2_2") (pintype "passive"))
      (node (ref "C204") (pin "2") (pinfunction "2_2") (pintype "passive"))
      (node (ref "C205") (pin "2") (pinfunction "2_2") (pintype "passive"))
      (node (ref "C209") (pin "2") (pinfunction "2_2") (pintype "passive"))
      (node (ref "C21") (pin "2") (pinfunction "2_2") (pintype "passive"))
      (node (ref "C210") (pin "2") (pinfunction "2_2") (pintype "passive"))
      (node (ref "C212") (pin "2") (pinfunction "2_2") (pintype "passive"))
      (node (ref "C213X") (pin "2") (pinfunction "2_2") (pintype "passive"))
      (node (ref "C214") (pin "2") (pinfunction "2_2") (pintype "passive"))
      (node (ref "C215X") (pin "2") (pinfunction "2_2") (pintype "passive"))
      (node (ref "C216X") (pin "2") (pinfunction "2_2") (pintype "passive"))
      (node (ref "C217X") (pin "2") (pinfunction "2_2") (pintype "passive"))
      (node (ref "C218X") (pin "2") (pinfunction "2_2") (pintype "passive"))
      (node (ref "C21X") (pin "2") (pinfunction "2_2") (pintype "passive"))
      (node (ref "C220") (pin "2") (pinfunction "2_2") (pintype "passive"))
      (node (ref "C221") (pin "2") (pinfunction "2_2") (pintype "passive"))
      (node (ref "C222") (pin "2") (pinfunction "2_2") (pintype "passive"))
      (node (ref "C23X") (pin "2") (pinfunction "2_2") (pintype "passive"))
      (node (ref "C24") (pin "2") (pinfunction "2_2") (pintype "passive"))
      (node (ref "C24-2") (pin "2") (pinfunction "2_2") (pintype "passive"))
      (node (ref "C25") (pin "2") (pinfunction "2_2") (pintype "passive"))
      (node (ref "C25-2") (pin "2") (pinfunction "2_2") (pintype "passive"))
      (node (ref "C26X") (pin "2") (pinfunction "2_2") (pintype "passive"))
      (node (ref "C28") (pin "2") (pinfunction "2_2") (pintype "passive"))
      (node (ref "C28-2") (pin "2") (pinfunction "2_2") (pintype "passive"))
      (node (ref "C29") (pin "2") (pinfunction "2_2") (pintype "passive"))
      (node (ref "C29-2") (pin "2") (pinfunction "2_2") (pintype "passive"))
      (node (ref "C30") (pin "2") (pinfunction "2_2") (pintype "passive"))
      (node (ref "C30-2") (pin "2") (pinfunction "2_2") (pintype "passive"))
      (node (ref "C32") (pin "2") (pinfunction "2_2") (pintype "passive"))
      (node (ref "C32-2") (pin "2") (pinfunction "2_2") (pintype "passive"))
      (node (ref "C33") (pin "2") (pinfunction "2_2") (pintype "passive"))
      (node (ref "C34") (pin "1") (pinfunction "1_1") (pintype "passive"))
      (node (ref "C35") (pin "2") (pinfunction "2_2") (pintype "passive"))
      (node (ref "C36") (pin "2") (pinfunction "2_2") (pintype "passive"))
      (node (ref "C37") (pin "1") (pinfunction "1_1") (pintype "passive"))
      (node (ref "C38") (pin "2") (pinfunction "2_2") (pintype "passive"))
      (node (ref "C38-2") (pin "2") (pinfunction "2_2") (pintype "passive"))
      (node (ref "C4") (pin "2") (pinfunction "2_2") (pintype "passive"))
      (node (ref "C4-2") (pin "2") (pinfunction "2_2") (pintype "passive"))
      (node (ref "C40") (pin "2") (pinfunction "2_2") (pintype "passive"))
      (node (ref "C40-2") (pin "2") (pinfunction "2_2") (pintype "passive"))
      (node (ref "C41") (pin "2") (pinfunction "2_2") (pintype "passive"))
      (node (ref "C41-2") (pin "2") (pinfunction "2_2") (pintype "passive"))
      (node (ref "C42") (pin "2") (pinfunction "2_2") (pintype "passive"))
      (node (ref "C42-2") (pin "2") (pinfunction "2_2") (pintype "passive"))
      (node (ref "C44") (pin "1") (pinfunction "1_1") (pintype "passive"))
      (node (ref "C45") (pin "2") (pinfunction "2_2") (pintype "passive"))
      (node (ref "C45-2") (pin "2") (pinfunction "2_2") (pintype "passive"))
      (node (ref "C46") (pin "2") (pinfunction "2_2") (pintype "passive"))
      (node (ref "C46-2") (pin "2") (pinfunction "2_2") (pintype "passive"))
      (node (ref "C47") (pin "1") (pinfunction "1_1") (pintype "passive"))
      (node (ref "C48") (pin "2") (pinfunction "2_2") (pintype "passive"))
      (node (ref "C48-2") (pin "2") (pinfunction "2_2") (pintype "passive"))
      (node (ref "C5") (pin "2") (pinfunction "2_2") (pintype "passive"))
      (node (ref "C5-2") (pin "2") (pinfunction "2_2") (pintype "passive"))
      (node (ref "C51") (pin "2") (pinfunction "2_2") (pintype "passive"))
      (node (ref "C51-2") (pin "2") (pinfunction "2_2") (pintype "passive"))
      (node (ref "C52") (pin "2") (pinfunction "2_2") (pintype "passive"))
      (node (ref "C52-2") (pin "2") (pinfunction "2_2") (pintype "passive"))
      (node (ref "C53") (pin "2") (pinfunction "2_2") (pintype "passive"))
      (node (ref "C53-2") (pin "2") (pinfunction "2_2") (pintype "passive"))
      (node (ref "C54") (pin "2") (pinfunction "2_2") (pintype "passive"))
      (node (ref "C54-2") (pin "2") (pinfunction "2_2") (pintype "passive"))
      (node (ref "C55") (pin "2") (pinfunction "2_2") (pintype "passive"))
      (node (ref "C55-2") (pin "2") (pinfunction "2_2") (pintype "passive"))
      (node (ref "C56") (pin "2") (pinfunction "2_2") (pintype "passive"))
      (node (ref "C56-2") (pin "2") (pinfunction "2_2") (pintype "passive"))
      (node (ref "C58") (pin "2") (pinfunction "2_2") (pintype "passive"))
      (node (ref "C59") (pin "2") (pinfunction "2_2") (pintype "passive"))
      (node (ref "C59-2") (pin "2") (pinfunction "2_2") (pintype "passive"))
      (node (ref "C6") (pin "2") (pinfunction "2_2") (pintype "passive"))
      (node (ref "C6-2") (pin "2") (pinfunction "2_2") (pintype "passive"))
      (node (ref "C60") (pin "2") (pinfunction "2_2") (pintype "passive"))
      (node (ref "C60-2") (pin "2") (pinfunction "2_2") (pintype "passive"))
      (node (ref "C61") (pin "1") (pinfunction "1_1") (pintype "passive"))
      (node (ref "C62") (pin "2") (pinfunction "2_2") (pintype "passive"))
      (node (ref "C62-2") (pin "2") (pinfunction "2_2") (pintype "passive"))
      (node (ref "C63") (pin "2") (pinfunction "2_2") (pintype "passive"))
      (node (ref "C63-2") (pin "2") (pinfunction "2_2") (pintype "passive"))
      (node (ref "C64") (pin "2") (pinfunction "2_2") (pintype "passive"))
      (node (ref "C64-2") (pin "2") (pinfunction "2_2") (pintype "passive"))
      (node (ref "C65") (pin "2") (pinfunction "2_2") (pintype "passive"))
      (node (ref "C65-2") (pin "2") (pinfunction "2_2") (pintype "passive"))
      (node (ref "C66") (pin "2") (pinfunction "2_2") (pintype "passive"))
      (node (ref "C66-2") (pin "2") (pinfunction "2_2") (pintype "passive"))
      (node (ref "C67") (pin "2") (pinfunction "2_2") (pintype "passive"))
      (node (ref "C67-2") (pin "2") (pinfunction "2_2") (pintype "passive"))
      (node (ref "C68") (pin "2") (pinfunction "2_2") (pintype "passive"))
      (node (ref "C69") (pin "2") (pinfunction "2_2") (pintype "passive"))
      (node (ref "C69-2") (pin "2") (pinfunction "2_2") (pintype "passive"))
      (node (ref "C7") (pin "2") (pinfunction "2_2") (pintype "passive"))
      (node (ref "C70") (pin "2") (pinfunction "2_2") (pintype "passive"))
      (node (ref "C71") (pin "2") (pinfunction "2_2") (pintype "passive"))
      (node (ref "C71-2") (pin "2") (pinfunction "2_2") (pintype "passive"))
      (node (ref "C72") (pin "2") (pinfunction "2_2") (pintype "passive"))
      (node (ref "C72-2") (pin "2") (pinfunction "2_2") (pintype "passive"))
      (node (ref "C74") (pin "2") (pinfunction "2_2") (pintype "passive"))
      (node (ref "C74-2") (pin "2") (pinfunction "2_2") (pintype "passive"))
      (node (ref "C75") (pin "2") (pinfunction "2_2") (pintype "passive"))
      (node (ref "C75-2") (pin "2") (pinfunction "2_2") (pintype "passive"))
      (node (ref "C76") (pin "1") (pinfunction "1_1") (pintype "passive"))
      (node (ref "C77") (pin "2") (pinfunction "2_2") (pintype "passive"))
      (node (ref "C77-2") (pin "2") (pinfunction "2_2") (pintype "passive"))
      (node (ref "C78") (pin "2") (pinfunction "2_2") (pintype "passive"))
      (node (ref "C79") (pin "2") (pinfunction "2_2") (pintype "passive"))
      (node (ref "C8") (pin "2") (pinfunction "2_2") (pintype "passive"))
      (node (ref "C80") (pin "2") (pinfunction "2_2") (pintype "passive"))
      (node (ref "C81") (pin "2") (pinfunction "2_2") (pintype "passive"))
      (node (ref "C81-2") (pin "2") (pinfunction "2_2") (pintype "passive"))
      (node (ref "C82") (pin "2") (pinfunction "2_2") (pintype "passive"))
      (node (ref "C82-2") (pin "2") (pinfunction "2_2") (pintype "passive"))
      (node (ref "C83") (pin "2") (pinfunction "2_2") (pintype "passive"))
      (node (ref "C83-2") (pin "2") (pinfunction "2_2") (pintype "passive"))
      (node (ref "C84") (pin "2") (pinfunction "2_2") (pintype "passive"))
      (node (ref "C84-2") (pin "2") (pinfunction "2_2") (pintype "passive"))
      (node (ref "C87") (pin "2") (pinfunction "2_2") (pintype "passive"))
      (node (ref "C87-2") (pin "2") (pinfunction "2_2") (pintype "passive"))
      (node (ref "C89") (pin "2") (pinfunction "2_2") (pintype "passive"))
      (node (ref "C89-2") (pin "2") (pinfunction "2_2") (pintype "passive"))
      (node (ref "C9") (pin "2") (pinfunction "2_2") (pintype "passive"))
      (node (ref "C92") (pin "2") (pinfunction "2_2") (pintype "passive"))
      (node (ref "C93") (pin "2") (pinfunction "2_2") (pintype "passive"))
      (node (ref "C94X") (pin "2") (pinfunction "2_2") (pintype "passive"))
      (node (ref "C98X") (pin "2") (pinfunction "2_2") (pintype "passive"))
      (node (ref "C99X") (pin "2") (pinfunction "2_2") (pintype "passive"))
      (node (ref "D2") (pin "A") (pinfunction "A_A") (pintype "passive"))
      (node (ref "D2-2") (pin "A") (pinfunction "A_A") (pintype "passive"))
      (node (ref "FB1") (pin "1") (pinfunction "1_1") (pintype "passive"))
      (node (ref "FB1-2") (pin "1") (pinfunction "1_1") (pintype "passive"))
      (node (ref "FB2") (pin "1") (pinfunction "1_1") (pintype "passive"))
      (node (ref "H1") (pin "B3,0") (pinfunction "MOUNT_B3,0") (pintype "passive"))
      (node (ref "H2") (pin "B3,0") (pinfunction "MOUNT_B3,0") (pintype "passive"))
      (node (ref "H3") (pin "B3,0") (pinfunction "MOUNT_B3,0") (pintype "passive"))
      (node (ref "H4") (pin "B3,0") (pinfunction "MOUNT_B3,0") (pintype "passive"))
      (node (ref "IC2") (pin "7") (pinfunction "VSS_7") (pintype "power_in"))
      (node (ref "J1") (pin "GND") (pinfunction "GND_GND") (pintype "bidirectional"))
      (node (ref "J1") (pin "MTN1") (pinfunction "MTN2_MTN1") (pintype "bidirectional"))
      (node (ref "J1") (pin "MTN2") (pinfunction "MTN3_MTN2") (pintype "bidirectional"))
      (node (ref "J1") (pin "MTN3") (pinfunction "MTN1_MTN3") (pintype "bidirectional"))
      (node (ref "J1") (pin "MTN4") (pinfunction "MTN4_MTN4") (pintype "bidirectional"))
      (node (ref "J1-2") (pin "GND") (pinfunction "GND_GND") (pintype "bidirectional"))
      (node (ref "J1-2") (pin "MTN1") (pinfunction "MTN2_MTN1") (pintype "bidirectional"))
      (node (ref "J1-2") (pin "MTN2") (pinfunction "MTN3_MTN2") (pintype "bidirectional"))
      (node (ref "J1-2") (pin "MTN3") (pinfunction "MTN1_MTN3") (pintype "bidirectional"))
      (node (ref "J1-2") (pin "MTN4") (pinfunction "MTN4_MTN4") (pintype "bidirectional"))
      (node (ref "J11") (pin "11") (pinfunction "INSERT_COM_11") (pintype "passive"))
      (node (ref "J11") (pin "6") (pinfunction "VSS_6") (pintype "power_in"))
      (node (ref "J2") (pin "GND") (pinfunction "GND_GND") (pintype "bidirectional"))
      (node (ref "J5") (pin "19") (pinfunction "19_19") (pintype "passive"))
      (node (ref "J5") (pin "3") (pinfunction "3_3") (pintype "passive"))
      (node (ref "J5") (pin "7") (pinfunction "7_7") (pintype "passive"))
      (node (ref "J6") (pin "11") (pinfunction "INSERT_COM_11") (pintype "passive"))
      (node (ref "J6") (pin "6") (pinfunction "VSS_6") (pintype "power_in"))
      (node (ref "J7") (pin "16") (pinfunction "16_16") (pintype "passive"))
      (node (ref "J7") (pin "18") (pinfunction "18_18") (pintype "passive"))
      (node (ref "J7") (pin "19") (pinfunction "19_19") (pintype "passive"))
      (node (ref "J7") (pin "20") (pinfunction "20_20") (pintype "passive"))
      (node (ref "JP2") (pin "1") (pinfunction "1_1") (pintype "passive"))
      (node (ref "LSP1") (pin "MP") (pinfunction "MP_MP") (pintype "passive"))
      (node (ref "LSP2") (pin "MP") (pinfunction "MP_MP") (pintype "passive"))
      (node (ref "Q10") (pin "E") (pinfunction "E_E") (pintype "passive"))
      (node (ref "Q2") (pin "E") (pinfunction "E_E") (pintype "passive"))
      (node (ref "Q4") (pin "E") (pinfunction "E_E") (pintype "passive"))
      (node (ref "Q8") (pin "E") (pinfunction "E_E") (pintype "passive"))
      (node (ref "Q9") (pin "E") (pinfunction "E_E") (pintype "passive"))
      (node (ref "R104") (pin "1") (pinfunction "1_1") (pintype "passive"))
      (node (ref "R117") (pin "1") (pinfunction "1_1") (pintype "passive"))
      (node (ref "R117-2") (pin "1") (pinfunction "1_1") (pintype "passive"))
      (node (ref "R126X") (pin "1") (pinfunction "1_1") (pintype "passive"))
      (node (ref "R136") (pin "1") (pinfunction "1_1") (pintype "passive"))
      (node (ref "R137") (pin "2") (pinfunction "2_2") (pintype "passive"))
      (node (ref "R138") (pin "1") (pinfunction "1_1") (pintype "passive"))
      (node (ref "R15X") (pin "1") (pinfunction "1_1") (pintype "passive"))
      (node (ref "R17") (pin "1") (pinfunction "1_1") (pintype "passive"))
      (node (ref "R18") (pin "1") (pinfunction "1_1") (pintype "passive"))
      (node (ref "R18-2") (pin "1") (pinfunction "1_1") (pintype "passive"))
      (node (ref "R209") (pin "1") (pinfunction "1_1") (pintype "passive"))
      (node (ref "R212") (pin "1") (pinfunction "1_1") (pintype "passive"))
      (node (ref "R215") (pin "1") (pinfunction "1_1") (pintype "passive"))
      (node (ref "R216") (pin "1") (pinfunction "1_1") (pintype "passive"))
      (node (ref "R28") (pin "1") (pinfunction "1_1") (pintype "passive"))
      (node (ref "R33") (pin "1") (pinfunction "1_1") (pintype "passive"))
      (node (ref "R33-2") (pin "1") (pinfunction "1_1") (pintype "passive"))
      (node (ref "R34") (pin "1") (pinfunction "1_1") (pintype "passive"))
      (node (ref "R34-2") (pin "1") (pinfunction "1_1") (pintype "passive"))
      (node (ref "R43") (pin "2") (pinfunction "2_2") (pintype "passive"))
      (node (ref "R54") (pin "1") (pinfunction "1_1") (pintype "passive"))
      (node (ref "R54-2") (pin "1") (pinfunction "1_1") (pintype "passive"))
      (node (ref "R56") (pin "1") (pinfunction "1_1") (pintype "passive"))
      (node (ref "R56-2") (pin "1") (pinfunction "1_1") (pintype "passive"))
      (node (ref "R57") (pin "2") (pinfunction "2_2") (pintype "passive"))
      (node (ref "R59") (pin "1") (pinfunction "1_1") (pintype "passive"))
      (node (ref "R59-2") (pin "1") (pinfunction "1_1") (pintype "passive"))
      (node (ref "R60") (pin "1") (pinfunction "1_1") (pintype "passive"))
      (node (ref "R60-2") (pin "1") (pinfunction "1_1") (pintype "passive"))
      (node (ref "R61") (pin "1") (pinfunction "1_1") (pintype "passive"))
      (node (ref "R61-2") (pin "1") (pinfunction "1_1") (pintype "passive"))
      (node (ref "R62") (pin "1") (pinfunction "1_1") (pintype "passive"))
      (node (ref "R62-2") (pin "1") (pinfunction "1_1") (pintype "passive"))
      (node (ref "R64") (pin "1") (pinfunction "1_1") (pintype "passive"))
      (node (ref "R64-2") (pin "1") (pinfunction "1_1") (pintype "passive"))
      (node (ref "R70X") (pin "1") (pinfunction "1_1") (pintype "passive"))
      (node (ref "R76X") (pin "1") (pinfunction "1_1") (pintype "passive"))
      (node (ref "R9") (pin "1") (pinfunction "1_1") (pintype "passive"))
      (node (ref "SW1") (pin "3") (pinfunction "S_3") (pintype "passive"))
      (node (ref "TP2") (pin "TP") (pinfunction "TP_TP") (pintype "input"))
      (node (ref "U10X") (pin "1") (pinfunction "A0_1") (pintype "input"))
      (node (ref "U10X") (pin "2") (pinfunction "A1_2") (pintype "input"))
      (node (ref "U10X") (pin "3") (pinfunction "A2_3") (pintype "input"))
      (node (ref "U10X") (pin "4") (pinfunction "GND_4") (pintype "power_in"))
      (node (ref "U11X") (pin "2") (pinfunction "GND_2") (pintype "passive"))
      (node (ref "U12X") (pin "1") (pinfunction "GND_1") (pintype "power_in"))
      (node (ref "U13") (pin "2") (pinfunction "GND_2") (pintype "power_in"))
      (node (ref "U14") (pin "2") (pinfunction "GND_2") (pintype "power_in"))
      (node (ref "U15X") (pin "12") (pinfunction "GND_3_12") (pintype "passive"))
      (node (ref "U15X") (pin "4") (pinfunction "GND_2_4") (pintype "passive"))
      (node (ref "U15X") (pin "7") (pinfunction "GND_7") (pintype "passive"))
      (node (ref "U17") (pin "28") (pinfunction "DVSS_28") (pintype "power_in"))
      (node (ref "U17") (pin "7") (pinfunction "IOVSS_7") (pintype "power_in"))
      (node (ref "U18") (pin "10") (pinfunction "GND_10") (pintype "passive"))
      (node (ref "U1X") (pin "1") (pinfunction "GND_1") (pintype "power_in"))
      (node (ref "U2") (pin "5") (pinfunction "GND_5") (pintype "power_in"))
      (node (ref "U24") (pin "4") (pinfunction "GND_4") (pintype "power_in"))
      (node (ref "U3X") (pin "2") (pinfunction "GND_2") (pintype "passive"))
      (node (ref "U4") (pin "A11") (pinfunction "RSV4_A11") (pintype "input"))
      (node (ref "U4") (pin "A14") (pinfunction "VSS_A14") (pintype "power_in"))
      (node (ref "U4") (pin "B11") (pinfunction "RSV5_B11") (pintype "input"))
      (node (ref "U4") (pin "B2") (pinfunction "VSS_B2") (pintype "power_in"))
      (node (ref "U4") (pin "B3") (pinfunction "VSS_B3") (pintype "power_in"))
      (node (ref "U4") (pin "C12") (pinfunction "VSS_C12") (pintype "power_in"))
      (node (ref "U4") (pin "C8") (pinfunction "VSS_C8") (pintype "power_in"))
      (node (ref "U4") (pin "D10") (pinfunction "VSS_D10") (pintype "power_in"))
      (node (ref "U4") (pin "D4") (pinfunction "VSS_D4") (pintype "power_in"))
      (node (ref "U4") (pin "D5") (pinfunction "VSS_D5") (pintype "power_in"))
      (node (ref "U4") (pin "E11") (pinfunction "VSS_E11") (pintype "power_in"))
      (node (ref "U4") (pin "E3") (pinfunction "VSS_E3") (pintype "power_in"))
      (node (ref "U4") (pin "E4") (pinfunction "VSS_E4") (pintype "power_in"))
      (node (ref "U4") (pin "F3") (pinfunction "VSS_F3") (pintype "power_in"))
      (node (ref "U4") (pin "H13") (pinfunction "USB_VSSA3P3_H13") (pintype "power_in"))
      (node (ref "U4") (pin "H3") (pinfunction "VSS_H3") (pintype "power_in"))
      (node (ref "U4") (pin "J13") (pinfunction "VSS_J13") (pintype "power_in"))
      (node (ref "U4") (pin "K14") (pinfunction "USB_VSS1P3_K14") (pintype "power_in"))
      (node (ref "U4") (pin "K3") (pinfunction "VSS_K3") (pintype "power_in"))
      (node (ref "U4") (pin "K4") (pinfunction "VSS_K4") (pintype "power_in"))
      (node (ref "U4") (pin "L10") (pinfunction "VSS_L10") (pintype "power_in"))
      (node (ref "U4") (pin "L5") (pinfunction "VSS_L5") (pintype "power_in"))
      (node (ref "U4") (pin "M7") (pinfunction "VSS_M7") (pintype "power_in"))
      (node (ref "U4") (pin "P1") (pinfunction "VSS_P1") (pintype "power_in"))
      (node (ref "U4") (pin "P14") (pinfunction "VSS_P14") (pintype "power_in"))
      (node (ref "U5") (pin "A11") (pinfunction "RSV4_A11") (pintype "input"))
      (node (ref "U5") (pin "A14") (pinfunction "VSS_A14") (pintype "power_in"))
      (node (ref "U5") (pin "B11") (pinfunction "RSV5_B11") (pintype "input"))
      (node (ref "U5") (pin "B2") (pinfunction "VSS_B2") (pintype "power_in"))
      (node (ref "U5") (pin "B3") (pinfunction "VSS_B3") (pintype "power_in"))
      (node (ref "U5") (pin "C12") (pinfunction "VSS_C12") (pintype "power_in"))
      (node (ref "U5") (pin "C8") (pinfunction "VSS_C8") (pintype "power_in"))
      (node (ref "U5") (pin "D10") (pinfunction "VSS_D10") (pintype "power_in"))
      (node (ref "U5") (pin "D4") (pinfunction "VSS_D4") (pintype "power_in"))
      (node (ref "U5") (pin "D5") (pinfunction "VSS_D5") (pintype "power_in"))
      (node (ref "U5") (pin "E11") (pinfunction "VSS_E11") (pintype "power_in"))
      (node (ref "U5") (pin "E3") (pinfunction "VSS_E3") (pintype "power_in"))
      (node (ref "U5") (pin "E4") (pinfunction "VSS_E4") (pintype "power_in"))
      (node (ref "U5") (pin "F3") (pinfunction "VSS_F3") (pintype "power_in"))
      (node (ref "U5") (pin "H13") (pinfunction "USB_VSSA3P3_H13") (pintype "power_in"))
      (node (ref "U5") (pin "H3") (pinfunction "VSS_H3") (pintype "power_in"))
      (node (ref "U5") (pin "J13") (pinfunction "VSS_J13") (pintype "power_in"))
      (node (ref "U5") (pin "K14") (pinfunction "USB_VSS1P3_K14") (pintype "power_in"))
      (node (ref "U5") (pin "K3") (pinfunction "VSS_K3") (pintype "power_in"))
      (node (ref "U5") (pin "K4") (pinfunction "VSS_K4") (pintype "power_in"))
      (node (ref "U5") (pin "L10") (pinfunction "VSS_L10") (pintype "power_in"))
      (node (ref "U5") (pin "L5") (pinfunction "VSS_L5") (pintype "power_in"))
      (node (ref "U5") (pin "M7") (pinfunction "VSS_M7") (pintype "power_in"))
      (node (ref "U5") (pin "P1") (pinfunction "VSS_P1") (pintype "power_in"))
      (node (ref "U5") (pin "P14") (pinfunction "VSS_P14") (pintype "power_in"))
      (node (ref "U6") (pin "1") (pinfunction "GND_1") (pintype "power_in"))
      (node (ref "U6") (pin "10") (pinfunction "AGND_10") (pintype "power_in"))
      (node (ref "U6") (pin "11") (pinfunction "GND_11") (pintype "power_in"))
      (node (ref "U6") (pin "15") (pinfunction "GND_15") (pintype "power_in"))
      (node (ref "U6") (pin "25") (pinfunction "GND_25") (pintype "power_in"))
      (node (ref "U6") (pin "35") (pinfunction "GND_35") (pintype "power_in"))
      (node (ref "U6") (pin "47") (pinfunction "GND_47") (pintype "power_in"))
      (node (ref "U6") (pin "5") (pinfunction "GND_5") (pintype "power_in"))
      (node (ref "U6") (pin "51") (pinfunction "GND_51") (pintype "power_in"))
      (node (ref "U7") (pin "4") (pinfunction "GND_4") (pintype "passive"))
      (node (ref "U8") (pin "2") (pinfunction "GND_2") (pintype "passive"))
      (node (ref "U9") (pin "10") (pinfunction "GND_10") (pintype "power_in"))
      (node (ref "U9-2") (pin "10") (pinfunction "GND_10") (pintype "power_in"))
      (node (ref "Y1") (pin "NC1") (pinfunction "3_NC1") (pintype "passive"))
      (node (ref "Y1") (pin "NC2") (pinfunction "4_NC2") (pintype "passive"))
      (node (ref "Y1-2") (pin "NC1") (pinfunction "3_NC1") (pintype "passive"))
      (node (ref "Y1-2") (pin "NC2") (pinfunction "4_NC2") (pintype "passive"))
    )
    (net (code "47") (name "DIS") (class "Default")
      (node (ref "R43") (pin "1") (pinfunction "1_1") (pintype "passive"))
      (node (ref "U6") (pin "32") (pinfunction "ACBUS5_32") (pintype "bidirectional"))
    )
    (net (code "48") (name "DIST") (class "Default")
      (node (ref "C184") (pin "2") (pinfunction "2_2") (pintype "passive"))
      (node (ref "R200") (pin "1") (pinfunction "1_1") (pintype "passive"))
      (node (ref "U13") (pin "1") (pinfunction "B_1") (pintype "bidirectional"))
    )
    (net (code "49") (name "DISTOCT") (class "Default")
      (node (ref "C183") (pin "1") (pinfunction "1_1") (pintype "passive"))
      (node (ref "J7") (pin "10") (pinfunction "10_10") (pintype "passive"))
    )
    (net (code "50") (name "DIST_OUT") (class "Default")
      (node (ref "C178") (pin "2") (pinfunction "2_2") (pintype "passive"))
      (node (ref "IC2") (pin "10") (pinfunction "B_10") (pintype "tri_state"))
      (node (ref "J7") (pin "8") (pinfunction "8_8") (pintype "passive"))
      (node (ref "R159") (pin "2") (pinfunction "2_2") (pintype "passive"))
      (node (ref "U21") (pin "1") (pinfunction "OUT_1") (pintype "output"))
    )
    (net (code "51") (name "DSP2_LDO_OUT") (class "Default")
      (node (ref "C38-2") (pin "1") (pinfunction "1_1") (pintype "passive"))
      (node (ref "C40-2") (pin "1") (pinfunction "1_1") (pintype "passive"))
      (node (ref "C41-2") (pin "1") (pinfunction "1_1") (pintype "passive"))
      (node (ref "C42-2") (pin "1") (pinfunction "1_1") (pintype "passive"))
      (node (ref "C46-2") (pin "1") (pinfunction "1_1") (pintype "passive"))
      (node (ref "C48-2") (pin "1") (pinfunction "1_1") (pintype "passive"))
      (node (ref "C51-2") (pin "1") (pinfunction "1_1") (pintype "passive"))
      (node (ref "C52-2") (pin "1") (pinfunction "1_1") (pintype "passive"))
      (node (ref "C53-2") (pin "1") (pinfunction "1_1") (pintype "passive"))
      (node (ref "C54-2") (pin "1") (pinfunction "1_1") (pintype "passive"))
      (node (ref "C55-2") (pin "1") (pinfunction "1_1") (pintype "passive"))
      (node (ref "C59-2") (pin "1") (pinfunction "1_1") (pintype "passive"))
      (node (ref "C62-2") (pin "1") (pinfunction "1_1") (pintype "passive"))
      (node (ref "C64-2") (pin "1") (pinfunction "1_1") (pintype "passive"))
      (node (ref "C65-2") (pin "1") (pinfunction "1_1") (pintype "passive"))
      (node (ref "C67-2") (pin "1") (pinfunction "1_1") (pintype "passive"))
      (node (ref "C69-2") (pin "1") (pinfunction "1_1") (pintype "passive"))
      (node (ref "C89-2") (pin "1") (pinfunction "1_1") (pintype "passive"))
      (node (ref "R124-2") (pin "2") (pinfunction "2_2") (pintype "passive"))
      (node (ref "U5") (pin "C11") (pinfunction "CVDD_C11") (pintype "power_in"))
      (node (ref "U5") (pin "D11") (pinfunction "CVDD_D11") (pintype "power_in"))
      (node (ref "U5") (pin "D3") (pinfunction "CVDD_D3") (pintype "power_in"))
      (node (ref "U5") (pin "F2") (pinfunction "CVDD_F2") (pintype "power_in"))
      (node (ref "U5") (pin "G3") (pinfunction "CVDD_G3") (pintype "power_in"))
      (node (ref "U5") (pin "H2") (pinfunction "CVDD_H2") (pintype "power_in"))
      (node (ref "U5") (pin "K11") (pinfunction "CVDD_K11") (pintype "power_in"))
      (node (ref "U5") (pin "K12") (pinfunction "RSV1_K12") (pintype "power_in"))
      (node (ref "U5") (pin "L13") (pinfunction "RSV2_L13") (pintype "power_in"))
      (node (ref "U5") (pin "M6") (pinfunction "CVDD_M6") (pintype "power_in"))
      (node (ref "U5") (pin "M9") (pinfunction "CVDD_M9") (pintype "power_in"))
      (node (ref "U5") (pin "N9") (pinfunction "CVDD_N9") (pintype "power_in"))
    )
    (net (code "52") (name "DSP2_LDO_OUT_REG") (class "Default")
      (node (ref "R124-2") (pin "1") (pinfunction "1_1") (pintype "passive"))
      (node (ref "U5") (pin "A13") (pinfunction "DSP_LDOO_A13") (pintype "power_in"))
    )
    (net (code "53") (name "DSP_LDO_OUT") (class "Default")
      (node (ref "C38") (pin "1") (pinfunction "1_1") (pintype "passive"))
      (node (ref "C40") (pin "1") (pinfunction "1_1") (pintype "passive"))
      (node (ref "C41") (pin "1") (pinfunction "1_1") (pintype "passive"))
      (node (ref "C42") (pin "1") (pinfunction "1_1") (pintype "passive"))
      (node (ref "C46") (pin "1") (pinfunction "1_1") (pintype "passive"))
      (node (ref "C48") (pin "1") (pinfunction "1_1") (pintype "passive"))
      (node (ref "C51") (pin "1") (pinfunction "1_1") (pintype "passive"))
      (node (ref "C52") (pin "1") (pinfunction "1_1") (pintype "passive"))
      (node (ref "C53") (pin "1") (pinfunction "1_1") (pintype "passive"))
      (node (ref "C54") (pin "1") (pinfunction "1_1") (pintype "passive"))
      (node (ref "C55") (pin "1") (pinfunction "1_1") (pintype "passive"))
      (node (ref "C59") (pin "1") (pinfunction "1_1") (pintype "passive"))
      (node (ref "C62") (pin "1") (pinfunction "1_1") (pintype "passive"))
      (node (ref "C64") (pin "1") (pinfunction "1_1") (pintype "passive"))
      (node (ref "C65") (pin "1") (pinfunction "1_1") (pintype "passive"))
      (node (ref "C67") (pin "1") (pinfunction "1_1") (pintype "passive"))
      (node (ref "C69") (pin "1") (pinfunction "1_1") (pintype "passive"))
      (node (ref "C89") (pin "1") (pinfunction "1_1") (pintype "passive"))
      (node (ref "R124") (pin "2") (pinfunction "2_2") (pintype "passive"))
      (node (ref "U4") (pin "C11") (pinfunction "CVDD_C11") (pintype "power_in"))
      (node (ref "U4") (pin "D11") (pinfunction "CVDD_D11") (pintype "power_in"))
      (node (ref "U4") (pin "D3") (pinfunction "CVDD_D3") (pintype "power_in"))
      (node (ref "U4") (pin "F2") (pinfunction "CVDD_F2") (pintype "power_in"))
      (node (ref "U4") (pin "G3") (pinfunction "CVDD_G3") (pintype "power_in"))
      (node (ref "U4") (pin "H2") (pinfunction "CVDD_H2") (pintype "power_in"))
      (node (ref "U4") (pin "K11") (pinfunction "CVDD_K11") (pintype "power_in"))
      (node (ref "U4") (pin "K12") (pinfunction "RSV1_K12") (pintype "power_in"))
      (node (ref "U4") (pin "L13") (pinfunction "RSV2_L13") (pintype "power_in"))
      (node (ref "U4") (pin "M6") (pinfunction "CVDD_M6") (pintype "power_in"))
      (node (ref "U4") (pin "M9") (pinfunction "CVDD_M9") (pintype "power_in"))
      (node (ref "U4") (pin "N9") (pinfunction "CVDD_N9") (pintype "power_in"))
    )
    (net (code "54") (name "DSP_LDO_OUT_REG") (class "Default")
      (node (ref "R124") (pin "1") (pinfunction "1_1") (pintype "passive"))
      (node (ref "U4") (pin "A13") (pinfunction "DSP_LDOO_A13") (pintype "power_in"))
    )
    (net (code "55") (name "EECS") (class "Default")
      (node (ref "U2") (pin "1") (pinfunction "CS_1") (pintype "input"))
      (node (ref "U6") (pin "63") (pinfunction "EECS_63") (pintype "bidirectional"))
    )
    (net (code "56") (name "EEDATA") (class "Default")
      (node (ref "R21") (pin "2") (pinfunction "2_2") (pintype "passive"))
      (node (ref "U2") (pin "3") (pinfunction "DI_3") (pintype "input"))
      (node (ref "U6") (pin "61") (pinfunction "EEDATA_61") (pintype "bidirectional"))
    )
    (net (code "57") (name "EESK") (class "Default")
      (node (ref "U2") (pin "2") (pinfunction "SK_2") (pintype "input"))
      (node (ref "U6") (pin "62") (pinfunction "EESK_62") (pintype "output"))
    )
    (net (code "58") (name "EMU0") (class "Default")
      (node (ref "R24") (pin "2") (pinfunction "2_2") (pintype "passive"))
      (node (ref "R25") (pin "1") (pinfunction "1_1") (pintype "passive"))
      (node (ref "U4") (pin "L2") (pinfunction "EMU0_L2") (pintype "bidirectional"))
      (node (ref "U5") (pin "L2") (pinfunction "EMU0_L2") (pintype "bidirectional"))
    )
    (net (code "59") (name "EMU1") (class "Default")
      (node (ref "R20") (pin "2") (pinfunction "2_2") (pintype "passive"))
      (node (ref "R22") (pin "1") (pinfunction "1_1") (pintype "passive"))
      (node (ref "U4") (pin "M1") (pinfunction "EMU1_M1") (pintype "bidirectional"))
      (node (ref "U5") (pin "M1") (pinfunction "EMU1_M1") (pintype "bidirectional"))
    )
    (net (code "60") (name "FOOTSW") (class "Default")
      (node (ref "C168X") (pin "1") (pinfunction "1_1") (pintype "passive"))
      (node (ref "SW1") (pin "2") (pinfunction "P_2") (pintype "passive"))
      (node (ref "U5") (pin "N12") (pinfunction "LCD_D[12]/UART_RTS/GP[28]/I2S3_CLK_N12") (pintype "bidirectional"))
    )
    (net (code "61") (name "FT1.8V") (class "Default")
      (node (ref "C33") (pin "1") (pinfunction "1_1") (pintype "passive"))
      (node (ref "C36") (pin "1") (pinfunction "1_1") (pintype "passive"))
      (node (ref "C68") (pin "1") (pinfunction "1_1") (pintype "passive"))
      (node (ref "C70") (pin "1") (pinfunction "1_1") (pintype "passive"))
      (node (ref "U6") (pin "12") (pinfunction "VCORE_12") (pintype "power_in"))
      (node (ref "U6") (pin "37") (pinfunction "VCORE_37") (pintype "power_in"))
      (node (ref "U6") (pin "49") (pinfunction "VREGOUT_49") (pintype "power_in"))
      (node (ref "U6") (pin "64") (pinfunction "VCORE_64") (pintype "power_in"))
    )
    (net (code "62") (name "FTDI_3V3") (class "Default")
      (node (ref "C20") (pin "1") (pinfunction "1_1") (pintype "passive"))
      (node (ref "C34") (pin "2") (pinfunction "2_2") (pintype "passive"))
      (node (ref "C35") (pin "1") (pinfunction "1_1") (pintype "passive"))
      (node (ref "C58") (pin "1") (pinfunction "1_1") (pintype "passive"))
      (node (ref "C78") (pin "1") (pinfunction "1_1") (pintype "passive"))
      (node (ref "C79") (pin "1") (pinfunction "1_1") (pintype "passive"))
      (node (ref "C80") (pin "1") (pinfunction "1_1") (pintype "passive"))
      (node (ref "L4") (pin "1") (pinfunction "1_1") (pintype "passive"))
      (node (ref "L5") (pin "1") (pinfunction "1_1") (pintype "passive"))
      (node (ref "R19") (pin "1") (pinfunction "1_1") (pintype "passive"))
      (node (ref "R1X") (pin "2") (pinfunction "2_2") (pintype "passive"))
      (node (ref "R36") (pin "1") (pinfunction "1_1") (pintype "passive"))
      (node (ref "R42") (pin "2") (pinfunction "2_2") (pintype "passive"))
      (node (ref "R44") (pin "2") (pinfunction "2_2") (pintype "passive"))
      (node (ref "U2") (pin "8") (pinfunction "VCC_8") (pintype "power_in"))
      (node (ref "U6") (pin "20") (pinfunction "VCCIO_20") (pintype "power_in"))
      (node (ref "U6") (pin "31") (pinfunction "VCCIO_31") (pintype "power_in"))
      (node (ref "U6") (pin "42") (pinfunction "VCCIO_42") (pintype "power_in"))
      (node (ref "U6") (pin "50") (pinfunction "VREGIN_50") (pintype "power_in"))
      (node (ref "U6") (pin "56") (pinfunction "VCCIO_56") (pintype "power_in"))
      (node (ref "U8") (pin "3") (pinfunction "D_3") (pintype "input"))
      (node (ref "U8") (pin "5") (pinfunction "VCC_5") (pintype "power_in"))
    )
    (net (code "63") (name "GND-A") (class "Default")
      (node (ref "C111") (pin "2") (pinfunction "2_2") (pintype "passive"))
      (node (ref "C116") (pin "2") (pinfunction "2_2") (pintype "passive"))
      (node (ref "C117") (pin "2") (pinfunction "2_2") (pintype "passive"))
      (node (ref "C12") (pin "2") (pinfunction "2_2") (pintype "passive"))
      (node (ref "C173") (pin "2") (pinfunction "2_2") (pintype "passive"))
      (node (ref "C177") (pin "2") (pinfunction "2_2") (pintype "passive"))
      (node (ref "C179") (pin "-") (pinfunction "-_-") (pintype "passive"))
      (node (ref "C18") (pin "2") (pinfunction "2_2") (pintype "passive"))
      (node (ref "C180") (pin "-") (pinfunction "-_-") (pintype "passive"))
      (node (ref "C182") (pin "2") (pinfunction "2_2") (pintype "passive"))
      (node (ref "C19") (pin "2") (pinfunction "2_2") (pintype "passive"))
      (node (ref "C192") (pin "1") (pinfunction "1_1") (pintype "passive"))
      (node (ref "C196") (pin "2") (pinfunction "2_2") (pintype "passive"))
      (node (ref "C199") (pin "1") (pinfunction "1_1") (pintype "passive"))
      (node (ref "C223") (pin "2") (pinfunction "2_2") (pintype "passive"))
      (node (ref "C224") (pin "2") (pinfunction "2_2") (pintype "passive"))
      (node (ref "CF1") (pin "2@1") (pinfunction "2_2@1") (pintype "passive"))
      (node (ref "D9") (pin "A") (pinfunction "A_A") (pintype "passive"))
      (node (ref "FB2") (pin "2") (pinfunction "2_2") (pintype "passive"))
      (node (ref "J10") (pin "S") (pinfunction "S_S") (pintype "passive"))
      (node (ref "J3") (pin "S") (pinfunction "S_S") (pintype "passive"))
      (node (ref "J3") (pin "SN") (pinfunction "SN_SN") (pintype "passive"))
      (node (ref "J3") (pin "TN") (pinfunction "TN_TN") (pintype "passive"))
      (node (ref "J4") (pin "1") (pinfunction "S_1") (pintype "passive"))
      (node (ref "J9") (pin "S") (pinfunction "S_S") (pintype "passive"))
      (node (ref "LSP3") (pin "MP") (pinfunction "MP_MP") (pintype "passive"))
      (node (ref "Q1") (pin "E") (pinfunction "E_E") (pintype "passive"))
      (node (ref "Q5") (pin "2") (pinfunction "S_2") (pintype "bidirectional"))
      (node (ref "R111") (pin "1") (pinfunction "1_1") (pintype "passive"))
      (node (ref "R147") (pin "1") (pinfunction "1_1") (pintype "passive"))
      (node (ref "R156") (pin "1") (pinfunction "1_1") (pintype "passive"))
      (node (ref "R167") (pin "1") (pinfunction "1_1") (pintype "passive"))
      (node (ref "R170") (pin "1") (pinfunction "1_1") (pintype "passive"))
      (node (ref "R182") (pin "1") (pinfunction "1_1") (pintype "passive"))
      (node (ref "R183") (pin "1") (pinfunction "1_1") (pintype "passive"))
      (node (ref "R193") (pin "1") (pinfunction "1_1") (pintype "passive"))
      (node (ref "R194") (pin "1") (pinfunction "1_1") (pintype "passive"))
      (node (ref "R65") (pin "1") (pinfunction "1_1") (pintype "passive"))
      (node (ref "U17") (pin "17") (pinfunction "AVSS_17") (pintype "power_in"))
      (node (ref "U17") (pin "33") (pinfunction "EP_33") (pintype "power_in"))
      (node (ref "U19") (pin "4") (pinfunction "V-_4") (pintype "power_in"))
      (node (ref "U20") (pin "4") (pinfunction "V-_4") (pintype "power_in"))
      (node (ref "U21") (pin "4") (pinfunction "V-_4") (pintype "power_in"))
      (node (ref "U22") (pin "4") (pinfunction "V-_4") (pintype "power_in"))
      (node (ref "U23") (pin "4") (pinfunction "V-_4") (pintype "power_in"))
    )
    (net (code "64") (name "GPAIN0") (class "Default")
      (node (ref "J7") (pin "17") (pinfunction "17_17") (pintype "passive"))
      (node (ref "U4") (pin "A8") (pinfunction "GPAIN0_A8") (pintype "bidirectional"))
    )
    (net (code "65") (name "GPAIN1") (class "Default")
      (node (ref "J7") (pin "15") (pinfunction "15_15") (pintype "passive"))
      (node (ref "U4") (pin "B8") (pinfunction "GPAIN1_B8") (pintype "bidirectional"))
    )
    (net (code "66") (name "GPAIN2") (class "Default")
      (node (ref "J7") (pin "9") (pinfunction "9_9") (pintype "passive"))
      (node (ref "U4") (pin "A9") (pinfunction "GPAIN2_A9") (pintype "bidirectional"))
    )
    (net (code "67") (name "GPAIN2_2") (class "Default")
      (node (ref "J7") (pin "7") (pinfunction "7_7") (pintype "passive"))
      (node (ref "U5") (pin "A9") (pinfunction "GPAIN2_A9") (pintype "bidirectional"))
    )
    (net (code "68") (name "GPAIN2_3") (class "Default")
      (node (ref "J7") (pin "11") (pinfunction "11_11") (pintype "passive"))
      (node (ref "U5") (pin "A10") (pinfunction "GPAIN3_A10") (pintype "bidirectional"))
    )
    (net (code "69") (name "GPAIN3") (class "Default")
      (node (ref "J7") (pin "13") (pinfunction "13_13") (pintype "passive"))
      (node (ref "U4") (pin "A10") (pinfunction "GPAIN3_A10") (pintype "bidirectional"))
    )
    (net (code "70") (name "GPIO10") (class "Default")
      (node (ref "R84") (pin "1") (pinfunction "1_1") (pintype "passive"))
      (node (ref "U4") (pin "P3") (pinfunction "LCD_D[6]/GP[16]_P3") (pintype "tri_state"))
    )
    (net (code "71") (name "GPIO13") (class "Default")
      (node (ref "TP14") (pin "TP") (pinfunction "TP_TP") (pintype "input"))
      (node (ref "U4") (pin "N5") (pinfunction "LCD_D[3]/GP[13]_N5") (pintype "tri_state"))
    )
    (net (code "72") (name "GPIO14") (class "Default")
      (node (ref "TP15") (pin "TP") (pinfunction "TP_TP") (pintype "input"))
      (node (ref "U4") (pin "P2") (pinfunction "LCD_D[4]/GP[14]_P2") (pintype "tri_state"))
    )
    (net (code "73") (name "GPIO15") (class "Default")
      (node (ref "TP16") (pin "TP") (pinfunction "TP_TP") (pintype "input"))
      (node (ref "U4") (pin "N7") (pinfunction "LCD_D[5]/GP[15]_N7") (pintype "tri_state"))
    )
    (net (code "74") (name "HP_LOUT") (class "Default")
      (node (ref "C14") (pin "+") (pinfunction "+_+") (pintype "passive"))
      (node (ref "U17") (pin "25") (pinfunction "HPL_25") (pintype "output"))
    )
    (net (code "75") (name "HP_ROUT") (class "Default")
      (node (ref "C13") (pin "+") (pinfunction "+_+") (pintype "passive"))
      (node (ref "U17") (pin "27") (pinfunction "HPR_27") (pintype "output"))
    )
    (net (code "76") (name "I2C2_SCL") (class "Default")
      (node (ref "R14-2") (pin "1") (pinfunction "1_1") (pintype "passive"))
      (node (ref "R26") (pin "1") (pinfunction "1_1") (pintype "passive"))
      (node (ref "U10X") (pin "6") (pinfunction "SCL_6") (pintype "input"))
      (node (ref "U5") (pin "C4") (pinfunction "I2C_SCL_C4") (pintype "bidirectional"))
    )
    (net (code "77") (name "I2C2_SDA") (class "Default")
      (node (ref "R13-2") (pin "1") (pinfunction "1_1") (pintype "passive"))
      (node (ref "R31") (pin "1") (pinfunction "1_1") (pintype "passive"))
      (node (ref "U10X") (pin "5") (pinfunction "SDA_5") (pintype "bidirectional"))
      (node (ref "U5") (pin "A4") (pinfunction "I2C_SDA_A4") (pintype "bidirectional"))
    )
    (net (code "78") (name "I2C_SCL") (class "Default")
      (node (ref "R14") (pin "1") (pinfunction "1_1") (pintype "passive"))
      (node (ref "R26") (pin "2") (pinfunction "2_2") (pintype "passive"))
      (node (ref "U18") (pin "7") (pinfunction "A6_7") (pintype "bidirectional"))
      (node (ref "U4") (pin "C4") (pinfunction "I2C_SCL_C4") (pintype "bidirectional"))
    )
    (net (code "79") (name "I2C_SCL_AIC") (class "Default")
      (node (ref "R134") (pin "1") (pinfunction "1_1") (pintype "passive"))
      (node (ref "U17") (pin "9") (pinfunction "SCL/SSZ_9") (pintype "input"))
      (node (ref "U18") (pin "13") (pinfunction "B6_13") (pintype "bidirectional"))
    )
    (net (code "80") (name "I2C_SDA") (class "Default")
      (node (ref "R13") (pin "1") (pinfunction "1_1") (pintype "passive"))
      (node (ref "R31") (pin "2") (pinfunction "2_2") (pintype "passive"))
      (node (ref "U18") (pin "8") (pinfunction "A7_8") (pintype "bidirectional"))
      (node (ref "U4") (pin "A4") (pinfunction "I2C_SDA_A4") (pintype "bidirectional"))
    )
    (net (code "81") (name "I2C_SDA_AIC") (class "Default")
      (node (ref "R135") (pin "1") (pinfunction "1_1") (pintype "passive"))
      (node (ref "U17") (pin "10") (pinfunction "SDA/MOSI_10") (pintype "input"))
      (node (ref "U18") (pin "12") (pinfunction "B7_12") (pintype "bidirectional"))
    )
    (net (code "82") (name "I2S2_2_CLK") (class "Default")
      (node (ref "TP28X") (pin "TP") (pinfunction "TP_TP") (pintype "input"))
      (node (ref "U5") (pin "P5") (pinfunction "LCD_D[8]/I2S2_CLK/GP[18]/SPI_CLK_P5") (pintype "bidirectional"))
    )
    (net (code "83") (name "I2S2_2_DX") (class "Default")
      (node (ref "TP31X") (pin "TP") (pinfunction "TP_TP") (pintype "input"))
      (node (ref "U5") (pin "P11") (pinfunction "LCD_D[11]/I2S2_DX/GP[27]/SPI_TX_P11") (pintype "bidirectional"))
    )
    (net (code "84") (name "I2S2_2_FS") (class "Default")
      (node (ref "TP29X") (pin "TP") (pinfunction "TP_TP") (pintype "input"))
      (node (ref "U5") (pin "N10") (pinfunction "LCD_D[9]/I2S2_FS/GP[19]/SPI_CS0_N10") (pintype "bidirectional"))
    )
    (net (code "85") (name "I2S2_2_RX") (class "Default")
      (node (ref "TP30X") (pin "TP") (pinfunction "TP_TP") (pintype "input"))
      (node (ref "U5") (pin "P9") (pinfunction "LCD_D[10]/I2S2_RX/GP[20]/SPI_RX_P9") (pintype "bidirectional"))
    )
    (net (code "86") (name "I2S2_CLK") (class "Default")
      (node (ref "U18") (pin "3") (pinfunction "A2_3") (pintype "bidirectional"))
      (node (ref "U4") (pin "P5") (pinfunction "LCD_D[8]/I2S2_CLK/GP[18]/SPI_CLK_P5") (pintype "bidirectional"))
    )
    (net (code "87") (name "I2S2_DX") (class "Default")
      (node (ref "U18") (pin "5") (pinfunction "A4_5") (pintype "bidirectional"))
      (node (ref "U4") (pin "P11") (pinfunction "LCD_D[11]/I2S2_DX/GP[27]/SPI_TX_P11") (pintype "bidirectional"))
    )
    (net (code "88") (name "I2S2_FS") (class "Default")
      (node (ref "U18") (pin "4") (pinfunction "A3_4") (pintype "bidirectional"))
      (node (ref "U4") (pin "N10") (pinfunction "LCD_D[9]/I2S2_FS/GP[19]/SPI_CS0_N10") (pintype "bidirectional"))
    )
    (net (code "89") (name "I2S2_RX") (class "Default")
      (node (ref "U18") (pin "6") (pinfunction "A5_6") (pintype "bidirectional"))
      (node (ref "U4") (pin "P9") (pinfunction "LCD_D[10]/I2S2_RX/GP[20]/SPI_RX_P9") (pintype "bidirectional"))
    )
    (net (code "90") (name "INT1_0_N") (class "Default")
      (node (ref "R105X") (pin "1") (pinfunction "1_1") (pintype "passive"))
      (node (ref "R37") (pin "1") (pinfunction "1_1") (pintype "passive"))
      (node (ref "U4") (pin "C2") (pinfunction "INT0_C2") (pintype "input"))
    )
    (net (code "91") (name "INT1_1_N") (class "Default")
      (node (ref "R41") (pin "1") (pinfunction "1_1") (pintype "passive"))
      (node (ref "R84") (pin "2") (pinfunction "2_2") (pintype "passive"))
      (node (ref "U4") (pin "B1") (pinfunction "INT1_B1") (pintype "input"))
    )
    (net (code "92") (name "INT2_0_N") (class "Default")
      (node (ref "R41-2") (pin "1") (pinfunction "1_1") (pintype "passive"))
      (node (ref "R67") (pin "1") (pinfunction "1_1") (pintype "passive"))
      (node (ref "U5") (pin "C2") (pinfunction "INT0_C2") (pintype "input"))
    )
    (net (code "93") (name "INT2_1_N") (class "Default")
      (node (ref "R37-2") (pin "1") (pinfunction "1_1") (pintype "passive"))
      (node (ref "R83X") (pin "2") (pinfunction "2_2") (pintype "passive"))
      (node (ref "U5") (pin "B1") (pinfunction "INT1_B1") (pintype "input"))
    )
    (net (code "94") (name "LCD_A0") (class "Default")
      (node (ref "J5") (pin "13") (pinfunction "13_13") (pintype "passive"))
      (node (ref "U5") (pin "J2") (pinfunction "LCD_D[2]/GP[12]_J2") (pintype "tri_state"))
    )
    (net (code "95") (name "LED1") (class "Default")
      (node (ref "J7") (pin "1") (pinfunction "1_1") (pintype "passive"))
      (node (ref "U5") (pin "M14") (pinfunction "SD1_CLK/I2S1_CLK/GP[6]_M14") (pintype "bidirectional"))
    )
    (net (code "96") (name "LED2") (class "Default")
      (node (ref "J7") (pin "3") (pinfunction "3_3") (pintype "passive"))
      (node (ref "U5") (pin "L11") (pinfunction "SD1_CMD/I2S1_FS/GP[7]_L11") (pintype "bidirectional"))
    )
    (net (code "97") (name "LED3") (class "Default")
      (node (ref "J7") (pin "4") (pinfunction "4_4") (pintype "passive"))
      (node (ref "U5") (pin "M13") (pinfunction "SD1_D0/2S1_DX/GP[8]_M13") (pintype "bidirectional"))
    )
    (net (code "98") (name "LED4") (class "Default")
      (node (ref "J7") (pin "5") (pinfunction "5_5") (pintype "passive"))
      (node (ref "U5") (pin "P10") (pinfunction "SD1_D1/I2S1_RX/GP[9]_P10") (pintype "bidirectional"))
    )
    (net (code "99") (name "LED5") (class "Default")
      (node (ref "J7") (pin "6") (pinfunction "6_6") (pintype "passive"))
      (node (ref "U5") (pin "L12") (pinfunction "SD1_D2/GP[10]_L12") (pintype "bidirectional"))
    )
    (net (code "100") (name "LINEIN") (class "Default")
      (node (ref "C170") (pin "1") (pinfunction "1_1") (pintype "passive"))
      (node (ref "FB12") (pin "2") (pinfunction "2_2") (pintype "passive"))
      (node (ref "R169") (pin "1") (pinfunction "1_1") (pintype "passive"))
    )
    (net (code "101") (name "LINEOUT_L") (class "Default")
      (node (ref "C191") (pin "1") (pinfunction "1_1") (pintype "passive"))
      (node (ref "U17") (pin "22") (pinfunction "LOL_22") (pintype "output"))
    )
    (net (code "102") (name "LINEOUT_R") (class "Default")
      (node (ref "C198") (pin "1") (pinfunction "1_1") (pintype "passive"))
      (node (ref "U17") (pin "23") (pinfunction "LOR_23") (pintype "output"))
    )
    (net (code "103") (name "MCLK_12MHZ") (class "Default")
      (node (ref "R228X") (pin "2") (pinfunction "2_2") (pintype "passive"))
      (node (ref "U18") (pin "9") (pinfunction "A8_9") (pintype "bidirectional"))
    )
    (net (code "104") (name "MUTE") (class "Default")
      (node (ref "R186") (pin "1") (pinfunction "1_1") (pintype "passive"))
      (node (ref "U5") (pin "P7") (pinfunction "SD0_D3/GP[5]_P7") (pintype "bidirectional"))
    )
    (net (code "105") (name "NOISE_SUP") (class "Default")
      (node (ref "R213") (pin "2") (pinfunction "2_2") (pintype "passive"))
      (node (ref "R216") (pin "2") (pinfunction "2_2") (pintype "passive"))
      (node (ref "U5") (pin "B8") (pinfunction "GPAIN1_B8") (pintype "bidirectional"))
    )
    (net (code "106") (name "Net-(C21X-Pad1)") (class "Default")
      (node (ref "C21X") (pin "1") (pinfunction "1_1") (pintype "passive"))
      (node (ref "L6X") (pin "1") (pinfunction "1_1") (pintype "passive"))
      (node (ref "R118X") (pin "1") (pinfunction "1_1") (pintype "passive"))
      (node (ref "R11X") (pin "2") (pinfunction "2_2") (pintype "passive"))
      (node (ref "TP4X") (pin "TP") (pinfunction "TP_TP") (pintype "input"))
    )
    (net (code "107") (name "Net-(C170-Pad2)") (class "Default")
      (node (ref "C170") (pin "2") (pinfunction "2_2") (pintype "passive"))
      (node (ref "R144") (pin "1") (pinfunction "1_1") (pintype "passive"))
    )
    (net (code "108") (name "Net-(C172-Pad1)") (class "Default")
      (node (ref "C172") (pin "1") (pinfunction "1_1") (pintype "passive"))
      (node (ref "R148") (pin "2") (pinfunction "2_2") (pintype "passive"))
    )
    (net (code "109") (name "Net-(C173-Pad1)") (class "Default")
      (node (ref "C173") (pin "1") (pinfunction "1_1") (pintype "passive"))
      (node (ref "R150") (pin "1") (pinfunction "1_1") (pintype "passive"))
    )
    (net (code "110") (name "Net-(C176-Pad1)") (class "Default")
      (node (ref "C176") (pin "1") (pinfunction "1_1") (pintype "passive"))
      (node (ref "R154") (pin "2") (pinfunction "2_2") (pintype "passive"))
      (node (ref "R155") (pin "1") (pinfunction "1_1") (pintype "passive"))
    )
    (net (code "111") (name "Net-(C176-Pad2)") (class "Default")
      (node (ref "C176") (pin "2") (pinfunction "2_2") (pintype "passive"))
      (node (ref "Q1") (pin "C") (pinfunction "C_C") (pintype "passive"))
      (node (ref "R156") (pin "2") (pinfunction "2_2") (pintype "passive"))
    )
    (net (code "112") (name "Net-(C182-Pad1)") (class "Default")
      (node (ref "C182") (pin "1") (pinfunction "1_1") (pintype "passive"))
      (node (ref "R165") (pin "1") (pinfunction "1_1") (pintype "passive"))
    )
    (net (code "113") (name "Net-(C183-Pad2)") (class "Default")
      (node (ref "C183") (pin "2") (pinfunction "2_2") (pintype "passive"))
      (node (ref "R166") (pin "1") (pinfunction "1_1") (pintype "passive"))
    )
    (net (code "114") (name "Net-(C184-Pad1)") (class "Default")
      (node (ref "C184") (pin "1") (pinfunction "1_1") (pintype "passive"))
      (node (ref "R166") (pin "2") (pinfunction "2_2") (pintype "passive"))
      (node (ref "R167") (pin "2") (pinfunction "2_2") (pintype "passive"))
    )
    (net (code "115") (name "Net-(C186-Pad1)") (class "Default")
      (node (ref "C186") (pin "1") (pinfunction "1_1") (pintype "passive"))
      (node (ref "R169") (pin "2") (pinfunction "2_2") (pintype "passive"))
    )
    (net (code "116") (name "Net-(C187-Pad2)") (class "Default")
      (node (ref "C187") (pin "2") (pinfunction "2_2") (pintype "passive"))
      (node (ref "R174") (pin "1") (pinfunction "1_1") (pintype "passive"))
    )
    (net (code "117") (name "Net-(C191-Pad2)") (class "Default")
      (node (ref "C191") (pin "2") (pinfunction "2_2") (pintype "passive"))
      (node (ref "R180") (pin "1") (pinfunction "1_1") (pintype "passive"))
    )
    (net (code "118") (name "Net-(C192-Pad2)") (class "Default")
      (node (ref "C192") (pin "2") (pinfunction "2_2") (pintype "passive"))
      (node (ref "R176") (pin "1") (pinfunction "1_1") (pintype "passive"))
      (node (ref "R178") (pin "1") (pinfunction "1_1") (pintype "passive"))
      (node (ref "R180") (pin "2") (pinfunction "2_2") (pintype "passive"))
    )
    (net (code "119") (name "Net-(C193-Pad1)") (class "Default")
      (node (ref "C193") (pin "1") (pinfunction "1_1") (pintype "passive"))
      (node (ref "R181") (pin "2") (pinfunction "2_2") (pintype "passive"))
    )
    (net (code "120") (name "Net-(C194-Pad2)") (class "Default")
      (node (ref "C194") (pin "2") (pinfunction "2_2") (pintype "passive"))
      (node (ref "R182") (pin "2") (pinfunction "2_2") (pintype "passive"))
    )
    (net (code "121") (name "Net-(C195-Pad2)") (class "Default")
      (node (ref "C195") (pin "2") (pinfunction "2_2") (pintype "passive"))
      (node (ref "R183") (pin "2") (pinfunction "2_2") (pintype "passive"))
      (node (ref "R184") (pin "1") (pinfunction "1_1") (pintype "passive"))
    )
    (net (code "122") (name "Net-(C198-Pad2)") (class "Default")
      (node (ref "C198") (pin "2") (pinfunction "2_2") (pintype "passive"))
      (node (ref "R190") (pin "1") (pinfunction "1_1") (pintype "passive"))
    )
    (net (code "123") (name "Net-(C199-Pad2)") (class "Default")
      (node (ref "C199") (pin "2") (pinfunction "2_2") (pintype "passive"))
      (node (ref "R187") (pin "1") (pinfunction "1_1") (pintype "passive"))
      (node (ref "R188") (pin "1") (pinfunction "1_1") (pintype "passive"))
      (node (ref "R190") (pin "2") (pinfunction "2_2") (pintype "passive"))
    )
    (net (code "124") (name "Net-(C201-Pad1)") (class "Default")
      (node (ref "C201") (pin "1") (pinfunction "1_1") (pintype "passive"))
      (node (ref "R192") (pin "2") (pinfunction "2_2") (pintype "passive"))
    )
    (net (code "125") (name "Net-(C202-Pad2)") (class "Default")
      (node (ref "C202") (pin "2") (pinfunction "2_2") (pintype "passive"))
      (node (ref "R193") (pin "2") (pinfunction "2_2") (pintype "passive"))
    )
    (net (code "126") (name "Net-(C203-Pad2)") (class "Default")
      (node (ref "C203") (pin "2") (pinfunction "2_2") (pintype "passive"))
      (node (ref "R194") (pin "2") (pinfunction "2_2") (pintype "passive"))
      (node (ref "R195") (pin "1") (pinfunction "1_1") (pintype "passive"))
    )
    (net (code "127") (name "Net-(C207-Pad2)") (class "Default")
      (node (ref "C207") (pin "2") (pinfunction "2_2") (pintype "passive"))
      (node (ref "R210") (pin "1") (pinfunction "1_1") (pintype "passive"))
    )
    (net (code "128") (name "Net-(C210-Pad1)") (class "Default")
      (node (ref "C210") (pin "1") (pinfunction "1_1") (pintype "passive"))
      (node (ref "C211") (pin "2") (pinfunction "2_2") (pintype "passive"))
      (node (ref "R206") (pin "1") (pinfunction "1_1") (pintype "passive"))
      (node (ref "R207") (pin "1") (pinfunction "1_1") (pintype "passive"))
      (node (ref "R209") (pin "2") (pinfunction "2_2") (pintype "passive"))
    )
    (net (code "129") (name "Net-(C211-Pad1)") (class "Default")
      (node (ref "C211") (pin "1") (pinfunction "1_1") (pintype "passive"))
      (node (ref "R205") (pin "1") (pinfunction "1_1") (pintype "passive"))
    )
    (net (code "130") (name "Net-(D3X-PadC)") (class "Default")
      (node (ref "D3X") (pin "C") (pinfunction "C_C") (pintype "passive"))
      (node (ref "R76X") (pin "2") (pinfunction "2_2") (pintype "passive"))
    )
    (net (code "131") (name "Net-(D6-C)") (class "Default")
      (node (ref "C181") (pin "2") (pinfunction "2_2") (pintype "passive"))
      (node (ref "D6") (pin "3") (pinfunction "C_3") (pintype "passive"))
      (node (ref "D8") (pin "1") (pinfunction "A1_1") (pintype "passive"))
      (node (ref "IC2") (pin "11") (pinfunction "A_11") (pintype "tri_state"))
    )
    (net (code "132") (name "Net-(D7-A1)") (class "Default")
      (node (ref "C206") (pin "1") (pinfunction "1_1") (pintype "passive"))
      (node (ref "D7") (pin "1") (pinfunction "A1_1") (pintype "passive"))
      (node (ref "D7") (pin "2") (pinfunction "C2_2") (pintype "passive"))
      (node (ref "R205") (pin "2") (pinfunction "2_2") (pintype "passive"))
      (node (ref "R208") (pin "1") (pinfunction "1_1") (pintype "passive"))
      (node (ref "U24") (pin "2") (pinfunction "-IN1_2") (pintype "input"))
    )
    (net (code "133") (name "Net-(D7-C1A2)") (class "Default")
      (node (ref "C205") (pin "1") (pinfunction "1_1") (pintype "passive"))
      (node (ref "D7") (pin "3") (pinfunction "C1A2_3") (pintype "passive"))
      (node (ref "R206") (pin "2") (pinfunction "2_2") (pintype "passive"))
      (node (ref "R210") (pin "2") (pinfunction "2_2") (pintype "passive"))
      (node (ref "U24") (pin "3") (pinfunction "+IN1_3") (pintype "input"))
    )
    (net (code "134") (name "Net-(DS1-PadC)") (class "Default")
      (node (ref "DS1") (pin "C") (pinfunction "C_C") (pintype "passive"))
      (node (ref "R12") (pin "2") (pinfunction "2_2") (pintype "passive"))
    )
    (net (code "135") (name "Net-(DS2-PadC)") (class "Default")
      (node (ref "DS2") (pin "C") (pinfunction "C_C") (pintype "passive"))
      (node (ref "R17") (pin "2") (pinfunction "2_2") (pintype "passive"))
    )
    (net (code "136") (name "Net-(FB12-Pad1)") (class "Default")
      (node (ref "FB12") (pin "1") (pinfunction "1_1") (pintype "passive"))
      (node (ref "J3") (pin "T") (pinfunction "T_T") (pintype "passive"))
    )
    (net (code "137") (name "Net-(FB13-Pad1)") (class "Default")
      (node (ref "FB13") (pin "1") (pinfunction "1_1") (pintype "passive"))
      (node (ref "J9") (pin "T") (pinfunction "T_T") (pintype "passive"))
    )
    (net (code "138") (name "Net-(FB13-Pad2)") (class "Default")
      (node (ref "FB13") (pin "2") (pinfunction "2_2") (pintype "passive"))
      (node (ref "R185") (pin "2") (pinfunction "2_2") (pintype "passive"))
    )
    (net (code "139") (name "Net-(FB14-Pad1)") (class "Default")
      (node (ref "FB14") (pin "1") (pinfunction "1_1") (pintype "passive"))
      (node (ref "J10") (pin "T") (pinfunction "T_T") (pintype "passive"))
    )
    (net (code "140") (name "Net-(FB14-Pad2)") (class "Default")
      (node (ref "FB14") (pin "2") (pinfunction "2_2") (pintype "passive"))
      (node (ref "R196") (pin "2") (pinfunction "2_2") (pintype "passive"))
    )
    (net (code "141") (name "Net-(IC2A-A)") (class "Default")
      (node (ref "IC2") (pin "1") (pinfunction "A_1") (pintype "tri_state"))
      (node (ref "IC2") (pin "3") (pinfunction "B_3") (pintype "tri_state"))
      (node (ref "R152") (pin "2") (pinfunction "2_2") (pintype "passive"))
      (node (ref "R153") (pin "1") (pinfunction "1_1") (pintype "passive"))
    )
    (net (code "142") (name "Net-(IC2A-B)") (class "Default")
      (node (ref "C174") (pin "2") (pinfunction "2_2") (pintype "passive"))
      (node (ref "C175") (pin "1") (pinfunction "1_1") (pintype "passive"))
      (node (ref "IC2") (pin "2") (pinfunction "B_2") (pintype "tri_state"))
      (node (ref "R153") (pin "2") (pinfunction "2_2") (pintype "passive"))
      (node (ref "R154") (pin "1") (pinfunction "1_1") (pintype "passive"))
      (node (ref "U19") (pin "7") (pinfunction "OUT_7") (pintype "output"))
    )
    (net (code "143") (name "Net-(IC2A-C)") (class "Default")
      (node (ref "IC2") (pin "13") (pinfunction "C_13") (pintype "input"))
      (node (ref "Q8") (pin "C") (pinfunction "C_C") (pintype "passive"))
      (node (ref "R202") (pin "1") (pinfunction "1_1") (pintype "passive"))
    )
    (net (code "144") (name "Net-(IC2B-A)") (class "Default")
      (node (ref "IC2") (pin "4") (pinfunction "A_4") (pintype "tri_state"))
      (node (ref "R151") (pin "2") (pinfunction "2_2") (pintype "passive"))
      (node (ref "R152") (pin "1") (pinfunction "1_1") (pintype "passive"))
    )
    (net (code "145") (name "Net-(IC2B-C)") (class "Default")
      (node (ref "IC2") (pin "5") (pinfunction "C_5") (pintype "input"))
      (node (ref "Q9") (pin "C") (pinfunction "C_C") (pintype "passive"))
      (node (ref "R203") (pin "1") (pinfunction "1_1") (pintype "passive"))
    )
    (net (code "146") (name "Net-(IC2C-A)") (class "Default")
      (node (ref "C177") (pin "1") (pinfunction "1_1") (pintype "passive"))
      (node (ref "IC2") (pin "8") (pinfunction "A_8") (pintype "tri_state"))
      (node (ref "R157") (pin "1") (pinfunction "1_1") (pintype "passive"))
    )
    (net (code "147") (name "Net-(IC2C-B)") (class "Default")
      (node (ref "IC2") (pin "9") (pinfunction "B_9") (pintype "tri_state"))
      (node (ref "R157") (pin "2") (pinfunction "2_2") (pintype "passive"))
      (node (ref "R161") (pin "1") (pinfunction "1_1") (pintype "passive"))
    )
    (net (code "148") (name "Net-(IC2C-C)") (class "Default")
      (node (ref "IC2") (pin "6") (pinfunction "C_6") (pintype "input"))
      (node (ref "Q2") (pin "B") (pinfunction "B_B") (pintype "passive"))
      (node (ref "Q4") (pin "C") (pinfunction "C_C") (pintype "passive"))
      (node (ref "R201") (pin "1") (pinfunction "1_1") (pintype "passive"))
    )
    (net (code "149") (name "Net-(IC2D-C)") (class "Default")
      (node (ref "IC2") (pin "12") (pinfunction "C_12") (pintype "input"))
      (node (ref "Q2") (pin "C") (pinfunction "C_C") (pintype "passive"))
      (node (ref "R168") (pin "1") (pinfunction "1_1") (pintype "passive"))
    )
    (net (code "150") (name "Net-(J2-P$1)") (class "Default")
      (node (ref "C37") (pin "2") (pinfunction "2_2") (pintype "passive"))
      (node (ref "J2") (pin "5") (pinfunction "P$1_5") (pintype "bidirectional"))
      (node (ref "J2") (pin "6") (pinfunction "P$2_6") (pintype "bidirectional"))
    )
    (net (code "151") (name "Net-(J6-INSERT)") (class "Default")
      (node (ref "J6") (pin "9") (pinfunction "INSERT_9") (pintype "passive"))
      (node (ref "R109") (pin "1") (pinfunction "1_1") (pintype "passive"))
    )
    (net (code "152") (name "Net-(J11-INSERT)") (class "Default")
      (node (ref "J11") (pin "9") (pinfunction "INSERT_9") (pintype "passive"))
      (node (ref "R1") (pin "1") (pinfunction "1_1") (pintype "passive"))
    )
    (net (code "153") (name "Net-(Q3-G)") (class "Default")
      (node (ref "C186") (pin "2") (pinfunction "2_2") (pintype "passive"))
      (node (ref "Q3") (pin "3") (pinfunction "G_3") (pintype "passive"))
      (node (ref "R171") (pin "2") (pinfunction "2_2") (pintype "passive"))
    )
    (net (code "154") (name "Net-(Q3-S)") (class "Default")
      (node (ref "C187") (pin "1") (pinfunction "1_1") (pintype "passive"))
      (node (ref "Q3") (pin "2") (pinfunction "S_2") (pintype "passive"))
      (node (ref "R170") (pin "2") (pinfunction "2_2") (pintype "passive"))
      (node (ref "R173") (pin "1") (pinfunction "1_1") (pintype "passive"))
    )
    (net (code "155") (name "Net-(Q5-D)") (class "Default")
      (node (ref "Q5") (pin "3") (pinfunction "D_3") (pintype "bidirectional"))
      (node (ref "Q6") (pin "3") (pinfunction "D_3") (pintype "bidirectional"))
      (node (ref "Q7") (pin "3") (pinfunction "D_3") (pintype "bidirectional"))
    )
    (net (code "156") (name "Net-(Q5-G)") (class "Default")
      (node (ref "C196") (pin "1") (pinfunction "1_1") (pintype "passive"))
      (node (ref "Q5") (pin "1") (pinfunction "G_1") (pintype "bidirectional"))
      (node (ref "Q6") (pin "1") (pinfunction "G_1") (pintype "bidirectional"))
      (node (ref "Q7") (pin "1") (pinfunction "G_1") (pintype "bidirectional"))
      (node (ref "R186") (pin "2") (pinfunction "2_2") (pintype "passive"))
    )
    (net (code "157") (name "Net-(Q6-S)") (class "Default")
      (node (ref "Q6") (pin "2") (pinfunction "S_2") (pintype "bidirectional"))
      (node (ref "R184") (pin "2") (pinfunction "2_2") (pintype "passive"))
      (node (ref "R185") (pin "1") (pinfunction "1_1") (pintype "passive"))
    )
    (net (code "158") (name "Net-(Q7-S)") (class "Default")
      (node (ref "Q7") (pin "2") (pinfunction "S_2") (pintype "bidirectional"))
      (node (ref "R195") (pin "2") (pinfunction "2_2") (pintype "passive"))
      (node (ref "R196") (pin "1") (pinfunction "1_1") (pintype "passive"))
    )
    (net (code "159") (name "Net-(SW2A-P)") (class "Default")
      (node (ref "CF1") (pin "3") (pinfunction "3_3") (pintype "passive"))
      (node (ref "SW2") (pin "2") (pinfunction "P_2") (pintype "passive"))
    )
    (net (code "160") (name "Net-(U1X-SW)") (class "Default")
      (node (ref "C124X") (pin "2") (pinfunction "2_2") (pintype "passive"))
      (node (ref "L6X") (pin "2") (pinfunction "2_2") (pintype "passive"))
      (node (ref "U1X") (pin "2") (pinfunction "SW_2") (pintype "output"))
    )
    (net (code "161") (name "Net-(U1X-VBST)") (class "Default")
      (node (ref "C124X") (pin "1") (pinfunction "1_1") (pintype "passive"))
      (node (ref "U1X") (pin "6") (pinfunction "VBST_6") (pintype "passive"))
    )
    (net (code "162") (name "Net-(U1X-VFB)") (class "Default")
      (node (ref "R11X") (pin "1") (pinfunction "1_1") (pintype "passive"))
      (node (ref "R15X") (pin "2") (pinfunction "2_2") (pintype "passive"))
      (node (ref "U1X") (pin "4") (pinfunction "VFB_4") (pintype "input"))
    )
    (net (code "163") (name "Net-(U2-DO)") (class "Default")
      (node (ref "R19") (pin "2") (pinfunction "2_2") (pintype "passive"))
      (node (ref "R21") (pin "1") (pinfunction "1_1") (pintype "passive"))
      (node (ref "U2") (pin "4") (pinfunction "DO_4") (pintype "output"))
    )
    (net (code "164") (name "Net-(U4A-BG_CAP)") (class "Default")
      (node (ref "C88") (pin "1") (pinfunction "1_1") (pintype "passive"))
      (node (ref "U4") (pin "C10") (pinfunction "BG_CAP_C10") (pintype "bidirectional"))
    )
    (net (code "165") (name "Net-(U4A-DSP_LDO_EN)") (class "Default")
      (node (ref "R63") (pin "1") (pinfunction "1_1") (pintype "passive"))
      (node (ref "R64") (pin "2") (pinfunction "2_2") (pintype "passive"))
      (node (ref "U4") (pin "C13") (pinfunction "DSP_LDO_EN_C13") (pintype "input"))
    )
    (net (code "166") (name "Net-(U4A-RSV0)") (class "Default")
      (node (ref "R61") (pin "2") (pinfunction "2_2") (pintype "passive"))
      (node (ref "U4") (pin "A12") (pinfunction "RSV0_A12") (pintype "input"))
    )
    (net (code "167") (name "Net-(U4A-RSV3)") (class "Default")
      (node (ref "R60") (pin "2") (pinfunction "2_2") (pintype "passive"))
      (node (ref "U4") (pin "B12") (pinfunction "RSV3_B12") (pintype "input"))
    )
    (net (code "168") (name "Net-(U4A-RSV6)") (class "Default")
      (node (ref "R62") (pin "2") (pinfunction "2_2") (pintype "passive"))
      (node (ref "U4") (pin "B13") (pinfunction "RSV6_B13") (pintype "input"))
    )
    (net (code "169") (name "Net-(U4B-CLKIN)") (class "Default")
      (node (ref "R34") (pin "2") (pinfunction "2_2") (pintype "passive"))
      (node (ref "R38") (pin "2") (pinfunction "2_2") (pintype "passive"))
      (node (ref "U4") (pin "C1") (pinfunction "CLKIN_C1") (pintype "input"))
    )
    (net (code "170") (name "Net-(U4B-CLKOUT)") (class "Default")
      (node (ref "R117") (pin "2") (pinfunction "2_2") (pintype "passive"))
      (node (ref "TP1") (pin "TP") (pinfunction "TP_TP") (pintype "input"))
      (node (ref "U4") (pin "A2") (pinfunction "CLKOUT_A2") (pintype "output"))
    )
    (net (code "171") (name "Net-(U4B-RTC_XI)") (class "Default")
      (node (ref "C91") (pin "2") (pinfunction "2_2") (pintype "passive"))
      (node (ref "U4") (pin "A7") (pinfunction "RTC_XI_A7") (pintype "input"))
      (node (ref "Y1") (pin "P$2") (pinfunction "2_P$2") (pintype "passive"))
    )
    (net (code "172") (name "Net-(U4B-RTC_XO)") (class "Default")
      (node (ref "C90") (pin "2") (pinfunction "2_2") (pintype "passive"))
      (node (ref "U4") (pin "A6") (pinfunction "RTC_XO_A6") (pintype "bidirectional"))
      (node (ref "Y1") (pin "P$1") (pinfunction "1_P$1") (pintype "passive"))
    )
    (net (code "173") (name "Net-(U4B-USB_R1)") (class "Default")
      (node (ref "R29") (pin "2") (pinfunction "2_2") (pintype "passive"))
      (node (ref "U4") (pin "G14") (pinfunction "USB_R1_G14") (pintype "bidirectional"))
    )
    (net (code "174") (name "Net-(U4B-USB_VSSOSC)") (class "Default")
      (node (ref "R54") (pin "2") (pinfunction "2_2") (pintype "passive"))
      (node (ref "U4") (pin "D12") (pinfunction "USB_VSSOSC_D12") (pintype "power_in"))
    )
    (net (code "175") (name "Net-(U4B-USB_VSSREF)") (class "Default")
      (node (ref "R29") (pin "1") (pinfunction "1_1") (pintype "passive"))
      (node (ref "U4") (pin "F12") (pinfunction "USB_VSSREF_F12") (pintype "power_in"))
    )
    (net (code "176") (name "Net-(U5A-BG_CAP)") (class "Default")
      (node (ref "C88-2") (pin "1") (pinfunction "1_1") (pintype "passive"))
      (node (ref "U5") (pin "C10") (pinfunction "BG_CAP_C10") (pintype "bidirectional"))
    )
    (net (code "177") (name "Net-(U5A-DSP_LDO_EN)") (class "Default")
      (node (ref "R63-2") (pin "1") (pinfunction "1_1") (pintype "passive"))
      (node (ref "R64-2") (pin "2") (pinfunction "2_2") (pintype "passive"))
      (node (ref "U5") (pin "C13") (pinfunction "DSP_LDO_EN_C13") (pintype "input"))
    )
    (net (code "178") (name "Net-(U5A-RSV0)") (class "Default")
      (node (ref "R61-2") (pin "2") (pinfunction "2_2") (pintype "passive"))
      (node (ref "U5") (pin "A12") (pinfunction "RSV0_A12") (pintype "input"))
    )
    (net (code "179") (name "Net-(U5A-RSV3)") (class "Default")
      (node (ref "R60-2") (pin "2") (pinfunction "2_2") (pintype "passive"))
      (node (ref "U5") (pin "B12") (pinfunction "RSV3_B12") (pintype "input"))
    )
    (net (code "180") (name "Net-(U5A-RSV6)") (class "Default")
      (node (ref "R62-2") (pin "2") (pinfunction "2_2") (pintype "passive"))
      (node (ref "U5") (pin "B13") (pinfunction "RSV6_B13") (pintype "input"))
    )
    (net (code "181") (name "Net-(U5B-CLKIN)") (class "Default")
      (node (ref "R34-2") (pin "2") (pinfunction "2_2") (pintype "passive"))
      (node (ref "R38-2") (pin "2") (pinfunction "2_2") (pintype "passive"))
      (node (ref "U5") (pin "C1") (pinfunction "CLKIN_C1") (pintype "input"))
    )
    (net (code "182") (name "Net-(U5B-RTC_XI)") (class "Default")
      (node (ref "C91-2") (pin "2") (pinfunction "2_2") (pintype "passive"))
      (node (ref "U5") (pin "A7") (pinfunction "RTC_XI_A7") (pintype "input"))
      (node (ref "Y1-2") (pin "P$2") (pinfunction "2_P$2") (pintype "passive"))
    )
    (net (code "183") (name "Net-(U5B-RTC_XO)") (class "Default")
      (node (ref "C90-2") (pin "2") (pinfunction "2_2") (pintype "passive"))
      (node (ref "U5") (pin "A6") (pinfunction "RTC_XO_A6") (pintype "bidirectional"))
      (node (ref "Y1-2") (pin "P$1") (pinfunction "1_P$1") (pintype "passive"))
    )
    (net (code "184") (name "Net-(U5B-USB_R1)") (class "Default")
      (node (ref "R29-2") (pin "2") (pinfunction "2_2") (pintype "passive"))
      (node (ref "U5") (pin "G14") (pinfunction "USB_R1_G14") (pintype "bidirectional"))
    )
    (net (code "185") (name "Net-(U5B-USB_VSSOSC)") (class "Default")
      (node (ref "R54-2") (pin "2") (pinfunction "2_2") (pintype "passive"))
      (node (ref "U5") (pin "D12") (pinfunction "USB_VSSOSC_D12") (pintype "power_in"))
    )
    (net (code "186") (name "Net-(U5B-USB_VSSREF)") (class "Default")
      (node (ref "R29-2") (pin "1") (pinfunction "1_1") (pintype "passive"))
      (node (ref "U5") (pin "F12") (pinfunction "USB_VSSREF_F12") (pintype "power_in"))
    )
    (net (code "187") (name "Net-(U6-ACBUS4)") (class "Default")
      (node (ref "R20") (pin "1") (pinfunction "1_1") (pintype "passive"))
      (node (ref "U6") (pin "30") (pinfunction "ACBUS4_30") (pintype "bidirectional"))
    )
    (net (code "188") (name "Net-(U6-ADBUS6)") (class "Default")
      (node (ref "R24") (pin "1") (pinfunction "1_1") (pintype "passive"))
      (node (ref "U6") (pin "23") (pinfunction "ADBUS6_23") (pintype "bidirectional"))
    )
    (net (code "189") (name "Net-(U6-BDBUS0)") (class "Default")
      (node (ref "R35") (pin "1") (pinfunction "1_1") (pintype "passive"))
      (node (ref "U6") (pin "38") (pinfunction "BDBUS0_38") (pintype "output"))
    )
    (net (code "190") (name "Net-(U6-BDBUS1)") (class "Default")
      (node (ref "R32") (pin "1") (pinfunction "1_1") (pintype "passive"))
      (node (ref "U6") (pin "39") (pinfunction "BDBUS1_39") (pintype "input"))
    )
    (net (code "191") (name "Net-(U6-BDBUS2)") (class "Default")
      (node (ref "R30") (pin "1") (pinfunction "1_1") (pintype "passive"))
      (node (ref "U6") (pin "40") (pinfunction "BDBUS2_40") (pintype "output"))
    )
    (net (code "192") (name "Net-(U6-BDBUS3)") (class "Default")
      (node (ref "R27") (pin "1") (pinfunction "1_1") (pintype "passive"))
      (node (ref "U6") (pin "41") (pinfunction "BDBUS3_41") (pintype "input"))
    )
    (net (code "193") (name "Net-(U6-PWEN#)") (class "Default")
      (node (ref "R12") (pin "1") (pinfunction "1_1") (pintype "passive"))
      (node (ref "U6") (pin "60") (pinfunction "PWEN#_60") (pintype "output"))
    )
    (net (code "194") (name "Net-(U6-REF)") (class "Default")
      (node (ref "R28") (pin "2") (pinfunction "2_2") (pintype "passive"))
      (node (ref "U6") (pin "6") (pinfunction "REF_6") (pintype "passive"))
    )
    (net (code "195") (name "Net-(U6-RESET#)") (class "Default")
      (node (ref "R36") (pin "2") (pinfunction "2_2") (pintype "passive"))
      (node (ref "U6") (pin "14") (pinfunction "RESET#_14") (pintype "input"))
    )
    (net (code "196") (name "Net-(U6-XTIN)") (class "Default")
      (node (ref "R23") (pin "2") (pinfunction "2_2") (pintype "passive"))
      (node (ref "U6") (pin "2") (pinfunction "XTIN_2") (pintype "input"))
    )
    (net (code "197") (name "Net-(U8-CLK)") (class "Default")
      (node (ref "R53") (pin "2") (pinfunction "2_2") (pintype "passive"))
      (node (ref "U8") (pin "1") (pinfunction "CLK_1") (pintype "input"))
    )
    (net (code "198") (name "Net-(U9-2-HOLD)") (class "Default")
      (node (ref "R52-2") (pin "1") (pinfunction "1_1") (pintype "passive"))
      (node (ref "U9-2") (pin "1") (pinfunction "HOLD_1") (pintype "bidirectional"))
    )
    (net (code "199") (name "Net-(U9-2-WP)") (class "Default")
      (node (ref "R52-1") (pin "1") (pinfunction "1_1") (pintype "passive"))
      (node (ref "U9-2") (pin "9") (pinfunction "WP_9") (pintype "bidirectional"))
    )
    (net (code "200") (name "Net-(U9-HOLD)") (class "Default")
      (node (ref "R52") (pin "1") (pinfunction "1_1") (pintype "passive"))
      (node (ref "U9") (pin "1") (pinfunction "HOLD_1") (pintype "bidirectional"))
    )
    (net (code "201") (name "Net-(U9-WP)") (class "Default")
      (node (ref "R16") (pin "1") (pinfunction "1_1") (pintype "passive"))
      (node (ref "U9") (pin "9") (pinfunction "WP_9") (pintype "bidirectional"))
    )
    (net (code "202") (name "Net-(U10X-WP)") (class "Default")
      (node (ref "R143X") (pin "1") (pinfunction "1_1") (pintype "passive"))
      (node (ref "U10X") (pin "7") (pinfunction "WP_7") (pintype "input"))
    )
    (net (code "203") (name "Net-(U11X-NR{slash}FB)") (class "Default")
      (node (ref "C95X") (pin "2") (pinfunction "2_2") (pintype "passive"))
      (node (ref "R125X") (pin "1") (pinfunction "1_1") (pintype "passive"))
      (node (ref "R126X") (pin "2") (pinfunction "2_2") (pintype "passive"))
      (node (ref "U11X") (pin "4") (pinfunction "NR/FB_4") (pintype "passive"))
    )
    (net (code "204") (name "Net-(U12X-SW)") (class "Default")
      (node (ref "C125X") (pin "2") (pinfunction "2_2") (pintype "passive"))
      (node (ref "L7X") (pin "2") (pinfunction "2_2") (pintype "passive"))
      (node (ref "U12X") (pin "2") (pinfunction "SW_2") (pintype "output"))
    )
    (net (code "205") (name "Net-(U12X-VBST)") (class "Default")
      (node (ref "C125X") (pin "1") (pinfunction "1_1") (pintype "passive"))
      (node (ref "U12X") (pin "6") (pinfunction "VBST_6") (pintype "passive"))
    )
    (net (code "206") (name "Net-(U12X-VFB)") (class "Default")
      (node (ref "R65X") (pin "1") (pinfunction "1_1") (pintype "passive"))
      (node (ref "R70X") (pin "2") (pinfunction "2_2") (pintype "passive"))
      (node (ref "U12X") (pin "4") (pinfunction "VFB_4") (pintype "input"))
    )
    (net (code "207") (name "Net-(U13A-X)") (class "Default")
      (node (ref "R175") (pin "1") (pinfunction "1_1") (pintype "passive"))
      (node (ref "R198") (pin "1") (pinfunction "1_1") (pintype "passive"))
      (node (ref "U13") (pin "4") (pinfunction "X_4") (pintype "bidirectional"))
    )
    (net (code "208") (name "Net-(U13A-~{A}{slash}B)") (class "Default")
      (node (ref "Q10") (pin "C") (pinfunction "C_C") (pintype "passive"))
      (node (ref "R204") (pin "1") (pinfunction "1_1") (pintype "passive"))
      (node (ref "U13") (pin "6") (pinfunction "~{A}/B_6") (pintype "input"))
    )
    (net (code "209") (name "Net-(U15X-1G)") (class "Default")
      (node (ref "R222X") (pin "2") (pinfunction "2_2") (pintype "passive"))
      (node (ref "U15X") (pin "2") (pinfunction "1G_2") (pintype "input"))
    )
    (net (code "210") (name "Net-(U15X-Y0)") (class "Default")
      (node (ref "R223X") (pin "1") (pinfunction "1_1") (pintype "passive"))
      (node (ref "U15X") (pin "3") (pinfunction "Y0_3") (pintype "output"))
    )
    (net (code "211") (name "Net-(U15X-Y1)") (class "Default")
      (node (ref "R224X") (pin "1") (pinfunction "1_1") (pintype "passive"))
      (node (ref "U15X") (pin "16") (pinfunction "Y1_16") (pintype "output"))
    )
    (net (code "212") (name "Net-(U15X-Y2)") (class "Default")
      (node (ref "R225X") (pin "1") (pinfunction "1_1") (pintype "passive"))
      (node (ref "U15X") (pin "13") (pinfunction "Y2_13") (pintype "output"))
    )
    (net (code "213") (name "Net-(U15X-Y3)") (class "Default")
      (node (ref "R226X") (pin "1") (pinfunction "1_1") (pintype "passive"))
      (node (ref "U15X") (pin "15") (pinfunction "Y3_15") (pintype "output"))
    )
    (net (code "214") (name "Net-(U15X-Y4)") (class "Default")
      (node (ref "R227X") (pin "1") (pinfunction "1_1") (pintype "passive"))
      (node (ref "U15X") (pin "6") (pinfunction "Y4_6") (pintype "output"))
    )
    (net (code "215") (name "Net-(U15X-Y5)") (class "Default")
      (node (ref "R228X") (pin "1") (pinfunction "1_1") (pintype "passive"))
      (node (ref "U15X") (pin "11") (pinfunction "Y5_11") (pintype "output"))
    )
    (net (code "216") (name "Net-(U15X-Y6)") (class "Default")
      (node (ref "R229X") (pin "1") (pinfunction "1_1") (pintype "passive"))
      (node (ref "U15X") (pin "8") (pinfunction "Y6_8") (pintype "output"))
    )
    (net (code "217") (name "Net-(U15X-Y7)") (class "Default")
      (node (ref "R230X") (pin "1") (pinfunction "1_1") (pintype "passive"))
      (node (ref "U15X") (pin "9") (pinfunction "Y7_9") (pintype "output"))
    )
    (net (code "218") (name "Net-(U17-IN2_L)") (class "Default")
      (node (ref "C17") (pin "2") (pinfunction "2_2") (pintype "passive"))
      (node (ref "U17") (pin "15") (pinfunction "IN2_L_15") (pintype "input"))
    )
    (net (code "219") (name "Net-(U17-IN2_R)") (class "Default")
      (node (ref "C16") (pin "2") (pinfunction "2_2") (pintype "passive"))
      (node (ref "U17") (pin "16") (pinfunction "IN2_R_16") (pintype "input"))
    )
    (net (code "220") (name "Net-(U17-LDO_SELECT)") (class "Default")
      (node (ref "R10") (pin "1") (pinfunction "1_1") (pintype "passive"))
      (node (ref "R9") (pin "2") (pinfunction "2_2") (pintype "passive"))
      (node (ref "U17") (pin "30") (pinfunction "LDO_SELECT_30") (pintype "input"))
    )
    (net (code "221") (name "Net-(U17-MICBIAS)") (class "Default")
      (node (ref "R110") (pin "2") (pinfunction "2_2") (pintype "passive"))
      (node (ref "U17") (pin "19") (pinfunction "MICBIAS_19") (pintype "output"))
    )
    (net (code "222") (name "Net-(U17-REF)") (class "Default")
      (node (ref "C117") (pin "1") (pinfunction "1_1") (pintype "passive"))
      (node (ref "C18") (pin "1") (pinfunction "1_1") (pintype "passive"))
      (node (ref "U17") (pin "18") (pinfunction "REF_18") (pintype "output"))
    )
    (net (code "223") (name "Net-(U18-B1)") (class "Default")
      (node (ref "R8") (pin "2") (pinfunction "2_2") (pintype "passive"))
      (node (ref "U18") (pin "18") (pinfunction "B1_18") (pintype "bidirectional"))
    )
    (net (code "224") (name "Net-(U18-B2)") (class "Default")
      (node (ref "R92") (pin "2") (pinfunction "2_2") (pintype "passive"))
      (node (ref "U18") (pin "17") (pinfunction "B2_17") (pintype "bidirectional"))
    )
    (net (code "225") (name "Net-(U18-B3)") (class "Default")
      (node (ref "R93") (pin "2") (pinfunction "2_2") (pintype "passive"))
      (node (ref "U18") (pin "16") (pinfunction "B3_16") (pintype "bidirectional"))
    )
    (net (code "226") (name "Net-(U18-B4)") (class "Default")
      (node (ref "R94") (pin "2") (pinfunction "2_2") (pintype "passive"))
      (node (ref "U18") (pin "15") (pinfunction "B4_15") (pintype "bidirectional"))
    )
    (net (code "227") (name "Net-(U18-B5)") (class "Default")
      (node (ref "R95") (pin "2") (pinfunction "2_2") (pintype "passive"))
      (node (ref "U18") (pin "14") (pinfunction "B5_14") (pintype "bidirectional"))
    )
    (net (code "228") (name "Net-(U19A-+IN)") (class "Default")
      (node (ref "R145") (pin "2") (pinfunction "2_2") (pintype "passive"))
      (node (ref "U19") (pin "3") (pinfunction "+IN_3") (pintype "input"))
    )
    (net (code "229") (name "Net-(U19A--IN)") (class "Default")
      (node (ref "C171") (pin "1") (pinfunction "1_1") (pintype "passive"))
      (node (ref "R144") (pin "2") (pinfunction "2_2") (pintype "passive"))
      (node (ref "R148") (pin "1") (pinfunction "1_1") (pintype "passive"))
      (node (ref "R149") (pin "1") (pinfunction "1_1") (pintype "passive"))
      (node (ref "U19") (pin "2") (pinfunction "-IN_2") (pintype "input"))
    )
    (net (code "230") (name "Net-(U19A-OUT)") (class "Default")
      (node (ref "C171") (pin "2") (pinfunction "2_2") (pintype "passive"))
      (node (ref "C172") (pin "2") (pinfunction "2_2") (pintype "passive"))
      (node (ref "R149") (pin "2") (pinfunction "2_2") (pintype "passive"))
      (node (ref "U19") (pin "1") (pinfunction "OUT_1") (pintype "output"))
      (node (ref "U19") (pin "5") (pinfunction "+IN_5") (pintype "input"))
    )
    (net (code "231") (name "Net-(U19B--IN)") (class "Default")
      (node (ref "C174") (pin "1") (pinfunction "1_1") (pintype "passive"))
      (node (ref "R150") (pin "2") (pinfunction "2_2") (pintype "passive"))
      (node (ref "R151") (pin "1") (pinfunction "1_1") (pintype "passive"))
      (node (ref "U19") (pin "6") (pinfunction "-IN_6") (pintype "input"))
    )
    (net (code "232") (name "Net-(U20A-+IN)") (class "Default")
      (node (ref "C180") (pin "+") (pinfunction "+_+") (pintype "passive"))
      (node (ref "R146") (pin "1") (pinfunction "1_1") (pintype "passive"))
      (node (ref "R147") (pin "2") (pinfunction "2_2") (pintype "passive"))
      (node (ref "U20") (pin "3") (pinfunction "+IN_3") (pintype "input"))
    )
    (net (code "233") (name "Net-(U20B--IN)") (class "Default")
      (node (ref "R172") (pin "1") (pinfunction "1_1") (pintype "passive"))
      (node (ref "R173") (pin "2") (pinfunction "2_2") (pintype "passive"))
      (node (ref "R174") (pin "2") (pinfunction "2_2") (pintype "passive"))
      (node (ref "U20") (pin "6") (pinfunction "-IN_6") (pintype "input"))
    )
    (net (code "234") (name "Net-(U21A-+IN)") (class "Default")
      (node (ref "C175") (pin "2") (pinfunction "2_2") (pintype "passive"))
      (node (ref "R155") (pin "2") (pinfunction "2_2") (pintype "passive"))
      (node (ref "U21") (pin "3") (pinfunction "+IN_3") (pintype "input"))
    )
    (net (code "235") (name "Net-(U21A--IN)") (class "Default")
      (node (ref "C178") (pin "1") (pinfunction "1_1") (pintype "passive"))
      (node (ref "C181") (pin "1") (pinfunction "1_1") (pintype "passive"))
      (node (ref "R158") (pin "1") (pinfunction "1_1") (pintype "passive"))
      (node (ref "R159") (pin "1") (pinfunction "1_1") (pintype "passive"))
      (node (ref "R160") (pin "1") (pinfunction "1_1") (pintype "passive"))
      (node (ref "R161") (pin "2") (pinfunction "2_2") (pintype "passive"))
      (node (ref "U21") (pin "2") (pinfunction "-IN_2") (pintype "input"))
    )
    (net (code "236") (name "Net-(U21B-+IN)") (class "Default")
      (node (ref "R163") (pin "2") (pinfunction "2_2") (pintype "passive"))
      (node (ref "R165") (pin "2") (pinfunction "2_2") (pintype "passive"))
      (node (ref "U21") (pin "5") (pinfunction "+IN_5") (pintype "input"))
    )
    (net (code "237") (name "Net-(U21B--IN)") (class "Default")
      (node (ref "R162") (pin "2") (pinfunction "2_2") (pintype "passive"))
      (node (ref "R164") (pin "1") (pinfunction "1_1") (pintype "passive"))
      (node (ref "U21") (pin "6") (pinfunction "-IN_6") (pintype "input"))
    )
    (net (code "238") (name "Net-(U22A--IN)") (class "Default")
      (node (ref "C189") (pin "1") (pinfunction "1_1") (pintype "passive"))
      (node (ref "R178") (pin "2") (pinfunction "2_2") (pintype "passive"))
      (node (ref "U22") (pin "2") (pinfunction "-IN_2") (pintype "input"))
    )
    (net (code "239") (name "Net-(U22A-OUT)") (class "Default")
      (node (ref "C189") (pin "2") (pinfunction "2_2") (pintype "passive"))
      (node (ref "R176") (pin "2") (pinfunction "2_2") (pintype "passive"))
      (node (ref "R179") (pin "1") (pinfunction "1_1") (pintype "passive"))
      (node (ref "U22") (pin "1") (pinfunction "OUT_1") (pintype "output"))
    )
    (net (code "240") (name "Net-(U22B--IN)") (class "Default")
      (node (ref "C190") (pin "1") (pinfunction "1_1") (pintype "passive"))
      (node (ref "R177") (pin "1") (pinfunction "1_1") (pintype "passive"))
      (node (ref "R179") (pin "2") (pinfunction "2_2") (pintype "passive"))
      (node (ref "R181") (pin "1") (pinfunction "1_1") (pintype "passive"))
      (node (ref "U22") (pin "6") (pinfunction "-IN_6") (pintype "input"))
    )
    (net (code "241") (name "Net-(U22B-OUT)") (class "Default")
      (node (ref "C190") (pin "2") (pinfunction "2_2") (pintype "passive"))
      (node (ref "C193") (pin "2") (pinfunction "2_2") (pintype "passive"))
      (node (ref "C194") (pin "1") (pinfunction "1_1") (pintype "passive"))
      (node (ref "C195") (pin "1") (pinfunction "1_1") (pintype "passive"))
      (node (ref "R177") (pin "2") (pinfunction "2_2") (pintype "passive"))
      (node (ref "U22") (pin "7") (pinfunction "OUT_7") (pintype "output"))
    )
    (net (code "242") (name "Net-(U23A--IN)") (class "Default")
      (node (ref "C197") (pin "1") (pinfunction "1_1") (pintype "passive"))
      (node (ref "R188") (pin "2") (pinfunction "2_2") (pintype "passive"))
      (node (ref "U23") (pin "2") (pinfunction "-IN_2") (pintype "input"))
    )
    (net (code "243") (name "Net-(U23A-OUT)") (class "Default")
      (node (ref "C197") (pin "2") (pinfunction "2_2") (pintype "passive"))
      (node (ref "R187") (pin "2") (pinfunction "2_2") (pintype "passive"))
      (node (ref "R189") (pin "1") (pinfunction "1_1") (pintype "passive"))
      (node (ref "U23") (pin "1") (pinfunction "OUT_1") (pintype "output"))
    )
    (net (code "244") (name "Net-(U23B--IN)") (class "Default")
      (node (ref "C200") (pin "1") (pinfunction "1_1") (pintype "passive"))
      (node (ref "R189") (pin "2") (pinfunction "2_2") (pintype "passive"))
      (node (ref "R191") (pin "1") (pinfunction "1_1") (pintype "passive"))
      (node (ref "R192") (pin "1") (pinfunction "1_1") (pintype "passive"))
      (node (ref "U23") (pin "6") (pinfunction "-IN_6") (pintype "input"))
    )
    (net (code "245") (name "Net-(U23B-OUT)") (class "Default")
      (node (ref "C200") (pin "2") (pinfunction "2_2") (pintype "passive"))
      (node (ref "C201") (pin "2") (pinfunction "2_2") (pintype "passive"))
      (node (ref "C202") (pin "1") (pinfunction "1_1") (pintype "passive"))
      (node (ref "C203") (pin "1") (pinfunction "1_1") (pintype "passive"))
      (node (ref "R191") (pin "2") (pinfunction "2_2") (pintype "passive"))
      (node (ref "U23") (pin "7") (pinfunction "OUT_7") (pintype "output"))
    )
    (net (code "246") (name "Net-(U24A-OUT1)") (class "Default")
      (node (ref "C206") (pin "2") (pinfunction "2_2") (pintype "passive"))
      (node (ref "C208") (pin "1") (pinfunction "1_1") (pintype "passive"))
      (node (ref "R208") (pin "2") (pinfunction "2_2") (pintype "passive"))
      (node (ref "R213") (pin "1") (pinfunction "1_1") (pintype "passive"))
      (node (ref "U24") (pin "1") (pinfunction "OUT1_1") (pintype "output"))
      (node (ref "U24") (pin "6") (pinfunction "-IN2_6") (pintype "input"))
    )
    (net (code "247") (name "Net-(U24B-+IN2)") (class "Default")
      (node (ref "C208") (pin "2") (pinfunction "2_2") (pintype "passive"))
      (node (ref "C212") (pin "1") (pinfunction "1_1") (pintype "passive"))
      (node (ref "R211") (pin "1") (pinfunction "1_1") (pintype "passive"))
      (node (ref "R212") (pin "2") (pinfunction "2_2") (pintype "passive"))
      (node (ref "U24") (pin "5") (pinfunction "+IN2_5") (pintype "input"))
    )
    (net (code "248") (name "Net-(U24B-OUT2)") (class "Default")
      (node (ref "R214") (pin "1") (pinfunction "1_1") (pintype "passive"))
      (node (ref "U24") (pin "7") (pinfunction "OUT2_7") (pintype "output"))
    )
    (net (code "249") (name "OCT1") (class "Default")
      (node (ref "D6") (pin "1") (pinfunction "A_1") (pintype "passive"))
      (node (ref "R160") (pin "2") (pinfunction "2_2") (pintype "passive"))
      (node (ref "R162") (pin "1") (pinfunction "1_1") (pintype "passive"))
    )
    (net (code "250") (name "OCT2") (class "Default")
      (node (ref "D8") (pin "2") (pinfunction "C2_2") (pintype "passive"))
      (node (ref "R158") (pin "2") (pinfunction "2_2") (pintype "passive"))
      (node (ref "R163") (pin "1") (pinfunction "1_1") (pintype "passive"))
    )
    (net (code "251") (name "OCT_OUT") (class "Default")
      (node (ref "J7") (pin "12") (pinfunction "12_12") (pintype "passive"))
      (node (ref "R164") (pin "2") (pinfunction "2_2") (pintype "passive"))
      (node (ref "U21") (pin "7") (pinfunction "OUT_7") (pintype "output"))
    )
    (net (code "252") (name "OD_DRV0") (class "Default")
      (node (ref "Q9") (pin "B") (pinfunction "B_B") (pintype "passive"))
      (node (ref "U5") (pin "M10") (pinfunction "SD0_CMD/I2S0_FS/GP[1]_M10") (pintype "bidirectional"))
    )
    (net (code "253") (name "OD_DRV1") (class "Default")
      (node (ref "Q8") (pin "B") (pinfunction "B_B") (pintype "passive"))
      (node (ref "U5") (pin "J1") (pinfunction "SD0_D0/I2S0_DX/GP[2]_J1") (pintype "bidirectional"))
    )
    (net (code "254") (name "OD_MODE0") (class "Default")
      (node (ref "Q1") (pin "B") (pinfunction "B_B") (pintype "passive"))
      (node (ref "U5") (pin "P6") (pinfunction "SD0_D1/I2S0_RX/GP[3]_P6") (pintype "bidirectional"))
    )
    (net (code "255") (name "OD_MODE1") (class "Default")
      (node (ref "Q4") (pin "B") (pinfunction "B_B") (pintype "passive"))
      (node (ref "U5") (pin "N13") (pinfunction "SD0_D2/GP[4]_N13") (pintype "bidirectional"))
    )
    (net (code "256") (name "PWR_DET") (class "Default")
      (node (ref "R40") (pin "2") (pinfunction "2_2") (pintype "passive"))
      (node (ref "U6") (pin "28") (pinfunction "ACBUS2_28") (pintype "bidirectional"))
      (node (ref "U8") (pin "4") (pinfunction "Q_4") (pintype "output"))
    )
    (net (code "257") (name "PWR_RST") (class "Default")
      (node (ref "R53") (pin "1") (pinfunction "1_1") (pintype "passive"))
      (node (ref "U6") (pin "29") (pinfunction "ACBUS3_29") (pintype "bidirectional"))
    )
    (net (code "258") (name "RTCK") (class "Default")
      (node (ref "R46") (pin "1") (pinfunction "1_1") (pintype "passive"))
      (node (ref "U6") (pin "24") (pinfunction "ADBUS7_24") (pintype "bidirectional"))
    )
    (net (code "259") (name "RTC_CLKOUT") (class "Default")
      (node (ref "TP4") (pin "TP") (pinfunction "TP_TP") (pintype "input"))
      (node (ref "U4") (pin "A3") (pinfunction "RTC_CLKOUT_A3") (pintype "output"))
    )
    (net (code "260") (name "RTC_CLKOUT2") (class "Default")
      (node (ref "TP8X") (pin "TP") (pinfunction "TP_TP") (pintype "input"))
      (node (ref "U5") (pin "A3") (pinfunction "RTC_CLKOUT_A3") (pintype "output"))
    )
    (net (code "261") (name "SD1_CLK") (class "Default")
      (node (ref "J11") (pin "5") (pinfunction "CLK_5") (pintype "input"))
      (node (ref "R6") (pin "1") (pinfunction "1_1") (pintype "passive"))
      (node (ref "U4") (pin "M14") (pinfunction "SD1_CLK/I2S1_CLK/GP[6]_M14") (pintype "bidirectional"))
    )
    (net (code "262") (name "SD1_CMD") (class "Default")
      (node (ref "J11") (pin "3") (pinfunction "CMD_3") (pintype "input"))
      (node (ref "R4") (pin "1") (pinfunction "1_1") (pintype "passive"))
      (node (ref "U4") (pin "L11") (pinfunction "SD1_CMD/I2S1_FS/GP[7]_L11") (pintype "bidirectional"))
    )
    (net (code "263") (name "SD1_DATA0") (class "Default")
      (node (ref "J11") (pin "7") (pinfunction "DAT0_7") (pintype "bidirectional"))
      (node (ref "R7") (pin "1") (pinfunction "1_1") (pintype "passive"))
      (node (ref "U4") (pin "M13") (pinfunction "SD1_D0/2S1_DX/GP[8]_M13") (pintype "bidirectional"))
    )
    (net (code "264") (name "SD1_DATA1") (class "Default")
      (node (ref "J11") (pin "8") (pinfunction "DAT1_8") (pintype "bidirectional"))
      (node (ref "R11") (pin "1") (pinfunction "1_1") (pintype "passive"))
      (node (ref "U4") (pin "P10") (pinfunction "SD1_D1/I2S1_RX/GP[9]_P10") (pintype "bidirectional"))
    )
    (net (code "265") (name "SD1_DATA2") (class "Default")
      (node (ref "J11") (pin "1") (pinfunction "DAT2_1") (pintype "bidirectional"))
      (node (ref "R2") (pin "1") (pinfunction "1_1") (pintype "passive"))
      (node (ref "U4") (pin "L12") (pinfunction "SD1_D2/GP[10]_L12") (pintype "bidirectional"))
    )
    (net (code "266") (name "SD1_DATA3") (class "Default")
      (node (ref "J11") (pin "2") (pinfunction "CD/DAT3_2") (pintype "bidirectional"))
      (node (ref "R3") (pin "1") (pinfunction "1_1") (pintype "passive"))
      (node (ref "U4") (pin "M12") (pinfunction "SD1_D3/GP[11]_M12") (pintype "bidirectional"))
    )
    (net (code "267") (name "SD_CLK") (class "Default")
      (node (ref "J6") (pin "5") (pinfunction "CLK_5") (pintype "input"))
      (node (ref "R101") (pin "1") (pinfunction "1_1") (pintype "passive"))
      (node (ref "U4") (pin "M8") (pinfunction "SD0_CLK/I2S0_CLK/GP[0]_M8") (pintype "bidirectional"))
    )
    (net (code "268") (name "SD_CMD") (class "Default")
      (node (ref "J6") (pin "3") (pinfunction "CMD_3") (pintype "input"))
      (node (ref "R100") (pin "1") (pinfunction "1_1") (pintype "passive"))
      (node (ref "U4") (pin "M10") (pinfunction "SD0_CMD/I2S0_FS/GP[1]_M10") (pintype "bidirectional"))
    )
    (net (code "269") (name "SD_DATA0") (class "Default")
      (node (ref "J6") (pin "7") (pinfunction "DAT0_7") (pintype "bidirectional"))
      (node (ref "R102") (pin "1") (pinfunction "1_1") (pintype "passive"))
      (node (ref "U4") (pin "J1") (pinfunction "SD0_D0/I2S0_DX/GP[2]_J1") (pintype "bidirectional"))
    )
    (net (code "270") (name "SD_DATA1") (class "Default")
      (node (ref "J6") (pin "8") (pinfunction "DAT1_8") (pintype "bidirectional"))
      (node (ref "R103") (pin "1") (pinfunction "1_1") (pintype "passive"))
      (node (ref "U4") (pin "P6") (pinfunction "SD0_D1/I2S0_RX/GP[3]_P6") (pintype "bidirectional"))
    )
    (net (code "271") (name "SD_DATA2") (class "Default")
      (node (ref "J6") (pin "1") (pinfunction "DAT2_1") (pintype "bidirectional"))
      (node (ref "R98") (pin "1") (pinfunction "1_1") (pintype "passive"))
      (node (ref "U4") (pin "N13") (pinfunction "SD0_D2/GP[4]_N13") (pintype "bidirectional"))
    )
    (net (code "272") (name "SD_DATA3") (class "Default")
      (node (ref "J6") (pin "2") (pinfunction "CD/DAT3_2") (pintype "bidirectional"))
      (node (ref "R99") (pin "1") (pinfunction "1_1") (pintype "passive"))
      (node (ref "U4") (pin "P7") (pinfunction "SD0_D3/GP[5]_P7") (pintype "bidirectional"))
    )
    (net (code "273") (name "SPI2_CLK") (class "Default")
      (node (ref "J5") (pin "11") (pinfunction "11_11") (pintype "passive"))
      (node (ref "R72-2") (pin "1") (pinfunction "1_1") (pintype "passive"))
      (node (ref "U5") (pin "L3") (pinfunction "LCD_EN_RDB/SPI_CLK_L3") (pintype "output"))
      (node (ref "U9-2") (pin "16") (pinfunction "CLK_16") (pintype "input"))
    )
    (net (code "274") (name "SPI2_CS0") (class "Default")
      (node (ref "R50-2") (pin "1") (pinfunction "1_1") (pintype "passive"))
      (node (ref "U5") (pin "L1") (pinfunction "LCD_CS0_E0/SPI_CS0_L1") (pintype "bidirectional"))
      (node (ref "U9-2") (pin "7") (pinfunction "CS_7") (pintype "input"))
    )
    (net (code "275") (name "SPI2_CS1") (class "Default")
      (node (ref "J5") (pin "17") (pinfunction "17_17") (pintype "passive"))
      (node (ref "U5") (pin "M2") (pinfunction "LCD_CS1_E1/SPI_CS1_M2") (pintype "bidirectional"))
    )
    (net (code "276") (name "SPI2_CS2") (class "Default")
      (node (ref "TP26X") (pin "TP") (pinfunction "TP_TP") (pintype "input"))
      (node (ref "U5") (pin "N2") (pinfunction "LCD_RW_WRB/SPI_CS2_N2") (pintype "bidirectional"))
    )
    (net (code "277") (name "SPI2_CS3") (class "Default")
      (node (ref "TP27X") (pin "TP") (pinfunction "TP_TP") (pintype "input"))
      (node (ref "U5") (pin "M5") (pinfunction "LCD_RS/SPI_CS3_M5") (pintype "bidirectional"))
    )
    (net (code "278") (name "SPI2_RX") (class "Default")
      (node (ref "R51-2") (pin "1") (pinfunction "1_1") (pintype "passive"))
      (node (ref "U5") (pin "N4") (pinfunction "LCD_D[0]/SPI_RX_N4") (pintype "tri_state"))
      (node (ref "U9-2") (pin "8") (pinfunction "DO_8") (pintype "bidirectional"))
    )
    (net (code "279") (name "SPI2_TX") (class "Default")
      (node (ref "J5") (pin "9") (pinfunction "9_9") (pintype "passive"))
      (node (ref "R73-2") (pin "1") (pinfunction "1_1") (pintype "passive"))
      (node (ref "U5") (pin "K1") (pinfunction "LCD_D[1]/SPI_TX_K1") (pintype "tri_state"))
      (node (ref "U9-2") (pin "15") (pinfunction "DI_15") (pintype "bidirectional"))
    )
    (net (code "280") (name "SPI_CLK") (class "Default")
      (node (ref "R72") (pin "1") (pinfunction "1_1") (pintype "passive"))
      (node (ref "U4") (pin "L3") (pinfunction "LCD_EN_RDB/SPI_CLK_L3") (pintype "output"))
      (node (ref "U9") (pin "16") (pinfunction "CLK_16") (pintype "input"))
    )
    (net (code "281") (name "SPI_CS0") (class "Default")
      (node (ref "R50") (pin "1") (pinfunction "1_1") (pintype "passive"))
      (node (ref "U4") (pin "L1") (pinfunction "LCD_CS0_E0/SPI_CS0_L1") (pintype "bidirectional"))
      (node (ref "U9") (pin "7") (pinfunction "CS_7") (pintype "input"))
    )
    (net (code "282") (name "SPI_CS1") (class "Default")
      (node (ref "TP19") (pin "TP") (pinfunction "TP_TP") (pintype "input"))
      (node (ref "U4") (pin "M2") (pinfunction "LCD_CS1_E1/SPI_CS1_M2") (pintype "bidirectional"))
    )
    (net (code "283") (name "SPI_CS2") (class "Default")
      (node (ref "TP20") (pin "TP") (pinfunction "TP_TP") (pintype "input"))
      (node (ref "U4") (pin "N2") (pinfunction "LCD_RW_WRB/SPI_CS2_N2") (pintype "bidirectional"))
    )
    (net (code "284") (name "SPI_CS3") (class "Default")
      (node (ref "TP21") (pin "TP") (pinfunction "TP_TP") (pintype "input"))
      (node (ref "U4") (pin "M5") (pinfunction "LCD_RS/SPI_CS3_M5") (pintype "bidirectional"))
    )
    (net (code "285") (name "SPI_RX") (class "Default")
      (node (ref "R51") (pin "1") (pinfunction "1_1") (pintype "passive"))
      (node (ref "U4") (pin "N4") (pinfunction "LCD_D[0]/SPI_RX_N4") (pintype "tri_state"))
      (node (ref "U9") (pin "8") (pinfunction "DO_8") (pintype "bidirectional"))
    )
    (net (code "286") (name "SPI_TX") (class "Default")
      (node (ref "R73") (pin "1") (pinfunction "1_1") (pintype "passive"))
      (node (ref "U4") (pin "K1") (pinfunction "LCD_D[1]/SPI_TX_K1") (pintype "tri_state"))
      (node (ref "U9") (pin "15") (pinfunction "DI_15") (pintype "bidirectional"))
    )
    (net (code "287") (name "SRST_N_OUT") (class "Default")
      (node (ref "R45") (pin "1") (pinfunction "1_1") (pintype "passive"))
      (node (ref "U6") (pin "26") (pinfunction "ACBUS0_26") (pintype "bidirectional"))
    )
    (net (code "288") (name "SRTST_N_IN") (class "Default")
      (node (ref "R44") (pin "1") (pinfunction "1_1") (pintype "passive"))
      (node (ref "R45") (pin "2") (pinfunction "2_2") (pintype "passive"))
      (node (ref "U6") (pin "27") (pinfunction "ACBUS1_27") (pintype "bidirectional"))
    )
    (net (code "289") (name "SW_UP") (class "Default")
      (node (ref "JP2") (pin "2") (pinfunction "2_2") (pintype "passive"))
      (node (ref "R4X") (pin "1") (pinfunction "1_1") (pintype "passive"))
      (node (ref "SW1") (pin "1") (pinfunction "O_1") (pintype "passive"))
    )
    (net (code "290") (name "TARGET_PWR_GOOD") (class "Default")
      (node (ref "J5") (pin "15") (pinfunction "15_15") (pintype "passive"))
      (node (ref "R3X") (pin "1") (pinfunction "1_1") (pintype "passive"))
      (node (ref "R40") (pin "1") (pinfunction "1_1") (pintype "passive"))
      (node (ref "R42") (pin "1") (pinfunction "1_1") (pintype "passive"))
      (node (ref "U18") (pin "2") (pinfunction "A1_2") (pintype "bidirectional"))
      (node (ref "U3X") (pin "3") (pinfunction "~{RESET}_3") (pintype "output"))
      (node (ref "U4") (pin "D2") (pinfunction "RESETN_D2") (pintype "input"))
      (node (ref "U5") (pin "D2") (pinfunction "RESETN_D2") (pintype "input"))
      (node (ref "U8") (pin "6") (pinfunction "~{CLR}_6") (pintype "input"))
    )
    (net (code "291") (name "TCK") (class "Default")
      (node (ref "R39") (pin "2") (pinfunction "2_2") (pintype "passive"))
      (node (ref "U4") (pin "N3") (pinfunction "TCK_N3") (pintype "input"))
      (node (ref "U5") (pin "N3") (pinfunction "TCK_N3") (pintype "input"))
    )
    (net (code "292") (name "TCK_R") (class "Default")
      (node (ref "R39") (pin "1") (pinfunction "1_1") (pintype "passive"))
      (node (ref "R46") (pin "2") (pinfunction "2_2") (pintype "passive"))
      (node (ref "U6") (pin "16") (pinfunction "ADBUS0_16") (pintype "bidirectional"))
    )
    (net (code "293") (name "TDI") (class "Default")
      (node (ref "R49") (pin "2") (pinfunction "2_2") (pintype "passive"))
      (node (ref "U4") (pin "K2") (pinfunction "TDI_K2") (pintype "input"))
    )
    (net (code "294") (name "TDI_R") (class "Default")
      (node (ref "R49") (pin "1") (pinfunction "1_1") (pintype "passive"))
      (node (ref "U6") (pin "17") (pinfunction "ADBUS1_17") (pintype "bidirectional"))
    )
    (net (code "295") (name "TDO") (class "Default")
      (node (ref "R48") (pin "2") (pinfunction "2_2") (pintype "passive"))
      (node (ref "R66X") (pin "1") (pinfunction "1_1") (pintype "passive"))
    )
    (net (code "296") (name "TDO1") (class "Default")
      (node (ref "U4") (pin "N1") (pinfunction "TDO_N1") (pintype "output"))
      (node (ref "U5") (pin "K2") (pinfunction "TDI_K2") (pintype "input"))
    )
    (net (code "297") (name "TDO2") (class "Default")
      (node (ref "R66X") (pin "2") (pinfunction "2_2") (pintype "passive"))
      (node (ref "U5") (pin "N1") (pinfunction "TDO_N1") (pintype "output"))
    )
    (net (code "298") (name "TDO_R") (class "Default")
      (node (ref "R48") (pin "1") (pinfunction "1_1") (pintype "passive"))
      (node (ref "U6") (pin "18") (pinfunction "ADBUS2_18") (pintype "bidirectional"))
    )
    (net (code "299") (name "TMS") (class "Default")
      (node (ref "R47") (pin "2") (pinfunction "2_2") (pintype "passive"))
      (node (ref "U4") (pin "N6") (pinfunction "TMS_N6") (pintype "input"))
      (node (ref "U5") (pin "N6") (pinfunction "TMS_N6") (pintype "input"))
    )
    (net (code "300") (name "TMS_R") (class "Default")
      (node (ref "R47") (pin "1") (pinfunction "1_1") (pintype "passive"))
      (node (ref "U6") (pin "19") (pinfunction "ADBUS3_19") (pintype "bidirectional"))
    )
    (net (code "301") (name "TP1_CLK12M") (class "Default")
      (node (ref "R223X") (pin "2") (pinfunction "2_2") (pintype "passive"))
      (node (ref "TP7X") (pin "TP") (pinfunction "TP_TP") (pintype "input"))
    )
    (net (code "302") (name "TP2_CLK12M") (class "Default")
      (node (ref "R224X") (pin "2") (pinfunction "2_2") (pintype "passive"))
      (node (ref "TP6X") (pin "TP") (pinfunction "TP_TP") (pintype "input"))
    )
    (net (code "303") (name "TRSTN") (class "Default")
      (node (ref "R57") (pin "1") (pinfunction "1_1") (pintype "passive"))
      (node (ref "R58") (pin "2") (pinfunction "2_2") (pintype "passive"))
      (node (ref "U4") (pin "P4") (pinfunction "TRST_P4") (pintype "input"))
      (node (ref "U5") (pin "P4") (pinfunction "TRST_P4") (pintype "input"))
    )
    (net (code "304") (name "TRSTN_R") (class "Default")
      (node (ref "R58") (pin "1") (pinfunction "1_1") (pintype "passive"))
      (node (ref "U6") (pin "21") (pinfunction "ADBUS4_21") (pintype "bidirectional"))
    )
    (net (code "305") (name "TUNER") (class "Default")
      (node (ref "C214") (pin "1") (pinfunction "1_1") (pintype "passive"))
      (node (ref "R214") (pin "2") (pinfunction "2_2") (pintype "passive"))
      (node (ref "R215") (pin "2") (pinfunction "2_2") (pintype "passive"))
      (node (ref "U5") (pin "A8") (pinfunction "GPAIN0_A8") (pintype "bidirectional"))
    )
    (net (code "306") (name "UART2_CTS") (class "Default")
      (node (ref "TP23X") (pin "TP") (pinfunction "TP_TP") (pintype "input"))
      (node (ref "U5") (pin "P12") (pinfunction "LCD_D[13]/UART_CTS/GP[29]/I2S3_FS_P12") (pintype "bidirectional"))
    )
    (net (code "307") (name "UART2_RX") (class "Default")
      (node (ref "TP24X") (pin "TP") (pinfunction "TP_TP") (pintype "input"))
      (node (ref "U5") (pin "P13") (pinfunction "LCD_D[14]/UART_RXD/GP[30]/I2S3_RX_P13") (pintype "bidirectional"))
    )
    (net (code "308") (name "UART2_TX") (class "Default")
      (node (ref "TP25X") (pin "TP") (pinfunction "TP_TP") (pintype "input"))
      (node (ref "U5") (pin "M11") (pinfunction "LCD_D[15]/UART_TXD/GP[31]/I2S3_DX_M11") (pintype "bidirectional"))
    )
    (net (code "309") (name "UART_CTS") (class "Default")
      (node (ref "R30") (pin "2") (pinfunction "2_2") (pintype "passive"))
      (node (ref "U4") (pin "P12") (pinfunction "LCD_D[13]/UART_CTS/GP[29]/I2S3_FS_P12") (pintype "bidirectional"))
    )
    (net (code "310") (name "UART_RTS") (class "Default")
      (node (ref "R27") (pin "2") (pinfunction "2_2") (pintype "passive"))
      (node (ref "U4") (pin "N12") (pinfunction "LCD_D[12]/UART_RTS/GP[28]/I2S3_CLK_N12") (pintype "bidirectional"))
    )
    (net (code "311") (name "UART_RX") (class "Default")
      (node (ref "R35") (pin "2") (pinfunction "2_2") (pintype "passive"))
      (node (ref "U4") (pin "P13") (pinfunction "LCD_D[14]/UART_RXD/GP[30]/I2S3_RX_P13") (pintype "bidirectional"))
    )
    (net (code "312") (name "UART_TX") (class "Default")
      (node (ref "R32") (pin "2") (pinfunction "2_2") (pintype "passive"))
      (node (ref "U4") (pin "M11") (pinfunction "LCD_D[15]/UART_TXD/GP[31]/I2S3_DX_M11") (pintype "bidirectional"))
    )
    (net (code "313") (name "USB1_LDO") (class "Default")
      (node (ref "R122") (pin "2") (pinfunction "2_2") (pintype "passive"))
      (node (ref "U4") (pin "D13") (pinfunction "USB_LDOO_D13") (pintype "power_in"))
    )
    (net (code "314") (name "USB1_VDD1P3") (class "Default")
      (node (ref "C5") (pin "1") (pinfunction "1_1") (pintype "passive"))
      (node (ref "C60") (pin "1") (pinfunction "1_1") (pintype "passive"))
      (node (ref "C74") (pin "1") (pinfunction "1_1") (pintype "passive"))
      (node (ref "FB6") (pin "2") (pinfunction "2_2") (pintype "passive"))
      (node (ref "U4") (pin "E12") (pinfunction "USB_VDD1P3_E12") (pintype "power_in"))
      (node (ref "U4") (pin "F14") (pinfunction "USB_VDD1P3_F14") (pintype "power_in"))
      (node (ref "U4") (pin "K13") (pinfunction "USB_VDD1P3_K13") (pintype "power_in"))
    )
    (net (code "315") (name "USB1_VDDA1P3") (class "Default")
      (node (ref "C2") (pin "1") (pinfunction "1_1") (pintype "passive"))
      (node (ref "C43") (pin "1") (pinfunction "1_1") (pintype "passive"))
      (node (ref "C49") (pin "1") (pinfunction "1_1") (pintype "passive"))
      (node (ref "FB4") (pin "2") (pinfunction "2_2") (pintype "passive"))
      (node (ref "U4") (pin "H12") (pinfunction "USB_VDDA1P3_H12") (pintype "power_in"))
    )
    (net (code "316") (name "USB1_VDDA3P3") (class "Default")
      (node (ref "C4") (pin "1") (pinfunction "1_1") (pintype "passive"))
      (node (ref "C56") (pin "1") (pinfunction "1_1") (pintype "passive"))
      (node (ref "C63") (pin "1") (pinfunction "1_1") (pintype "passive"))
      (node (ref "FB5") (pin "2") (pinfunction "2_2") (pintype "passive"))
      (node (ref "U4") (pin "G12") (pinfunction "USB_VDDA3P3_G12") (pintype "power_in"))
    )
    (net (code "317") (name "USB1_VDDOSC") (class "Default")
      (node (ref "C6") (pin "1") (pinfunction "1_1") (pintype "passive"))
      (node (ref "C66") (pin "1") (pinfunction "1_1") (pintype "passive"))
      (node (ref "C77") (pin "1") (pinfunction "1_1") (pintype "passive"))
      (node (ref "FB7") (pin "2") (pinfunction "2_2") (pintype "passive"))
      (node (ref "U4") (pin "E13") (pinfunction "USB_VDDOSC_E13") (pintype "power_in"))
    )
    (net (code "318") (name "USB1_VDDPLL") (class "Default")
      (node (ref "C3") (pin "1") (pinfunction "1_1") (pintype "passive"))
      (node (ref "C50") (pin "1") (pinfunction "1_1") (pintype "passive"))
      (node (ref "C57") (pin "1") (pinfunction "1_1") (pintype "passive"))
      (node (ref "L3") (pin "2") (pinfunction "2_2") (pintype "passive"))
      (node (ref "U4") (pin "G13") (pinfunction "USB_VDDPLL_G13") (pintype "power_in"))
    )
    (net (code "319") (name "USB2_CLK_12MHZ") (class "Default")
      (node (ref "R225X") (pin "2") (pinfunction "2_2") (pintype "passive"))
      (node (ref "R55-2") (pin "1") (pinfunction "1_1") (pintype "passive"))
    )
    (net (code "320") (name "USB2_D_N") (class "Default")
      (node (ref "J1-2") (pin "D-") (pinfunction "D-_D-") (pintype "bidirectional"))
      (node (ref "U5") (pin "J14") (pinfunction "USB_DM_J14") (pintype "bidirectional"))
    )
    (net (code "321") (name "USB2_D_P") (class "Default")
      (node (ref "J1-2") (pin "D+") (pinfunction "D+_D+") (pintype "bidirectional"))
      (node (ref "U5") (pin "H14") (pinfunction "USB_DP_H14") (pintype "bidirectional"))
    )
    (net (code "322") (name "USB2_LDO") (class "Default")
      (node (ref "R122-2") (pin "2") (pinfunction "2_2") (pintype "passive"))
      (node (ref "U5") (pin "D13") (pinfunction "USB_LDOO_D13") (pintype "power_in"))
    )
    (net (code "323") (name "USB2_VDD1P3") (class "Default")
      (node (ref "C5-2") (pin "1") (pinfunction "1_1") (pintype "passive"))
      (node (ref "C60-2") (pin "1") (pinfunction "1_1") (pintype "passive"))
      (node (ref "C74-2") (pin "1") (pinfunction "1_1") (pintype "passive"))
      (node (ref "FB6-2") (pin "2") (pinfunction "2_2") (pintype "passive"))
      (node (ref "U5") (pin "E12") (pinfunction "USB_VDD1P3_E12") (pintype "power_in"))
      (node (ref "U5") (pin "F14") (pinfunction "USB_VDD1P3_F14") (pintype "power_in"))
      (node (ref "U5") (pin "K13") (pinfunction "USB_VDD1P3_K13") (pintype "power_in"))
    )
    (net (code "324") (name "USB2_VDDA1P3") (class "Default")
      (node (ref "C2-2") (pin "1") (pinfunction "1_1") (pintype "passive"))
      (node (ref "C43-2") (pin "1") (pinfunction "1_1") (pintype "passive"))
      (node (ref "C49-2") (pin "1") (pinfunction "1_1") (pintype "passive"))
      (node (ref "FB4-2") (pin "2") (pinfunction "2_2") (pintype "passive"))
      (node (ref "U5") (pin "H12") (pinfunction "USB_VDDA1P3_H12") (pintype "power_in"))
    )
    (net (code "325") (name "USB2_VDDA3P3") (class "Default")
      (node (ref "C4-2") (pin "1") (pinfunction "1_1") (pintype "passive"))
      (node (ref "C56-2") (pin "1") (pinfunction "1_1") (pintype "passive"))
      (node (ref "C63-2") (pin "1") (pinfunction "1_1") (pintype "passive"))
      (node (ref "FB5-2") (pin "2") (pinfunction "2_2") (pintype "passive"))
      (node (ref "U5") (pin "G12") (pinfunction "USB_VDDA3P3_G12") (pintype "power_in"))
    )
    (net (code "326") (name "USB2_VDDOSC") (class "Default")
      (node (ref "C6-2") (pin "1") (pinfunction "1_1") (pintype "passive"))
      (node (ref "C66-2") (pin "1") (pinfunction "1_1") (pintype "passive"))
      (node (ref "C77-2") (pin "1") (pinfunction "1_1") (pintype "passive"))
      (node (ref "FB7-2") (pin "2") (pinfunction "2_2") (pintype "passive"))
      (node (ref "U5") (pin "E13") (pinfunction "USB_VDDOSC_E13") (pintype "power_in"))
    )
    (net (code "327") (name "USB2_VDDPLL") (class "Default")
      (node (ref "C3-2") (pin "1") (pinfunction "1_1") (pintype "passive"))
      (node (ref "C50-2") (pin "1") (pinfunction "1_1") (pintype "passive"))
      (node (ref "C57-2") (pin "1") (pinfunction "1_1") (pintype "passive"))
      (node (ref "L3-2") (pin "2") (pinfunction "2_2") (pintype "passive"))
      (node (ref "U5") (pin "G13") (pinfunction "USB_VDDPLL_G13") (pintype "power_in"))
    )
    (net (code "328") (name "USB_CLK_12MHZ") (class "Default")
      (node (ref "R230X") (pin "2") (pinfunction "2_2") (pintype "passive"))
      (node (ref "R55") (pin "1") (pinfunction "1_1") (pintype "passive"))
    )
    (net (code "329") (name "USB_D_N") (class "Default")
      (node (ref "J1") (pin "D-") (pinfunction "D-_D-") (pintype "bidirectional"))
      (node (ref "U4") (pin "J14") (pinfunction "USB_DM_J14") (pintype "bidirectional"))
    )
    (net (code "330") (name "USB_D_P") (class "Default")
      (node (ref "J1") (pin "D+") (pinfunction "D+_D+") (pintype "bidirectional"))
      (node (ref "U4") (pin "H14") (pinfunction "USB_DP_H14") (pintype "bidirectional"))
    )
    (net (code "331") (name "USB_LDO_OUT") (class "Default")
      (node (ref "FB4") (pin "1") (pinfunction "1_1") (pintype "passive"))
      (node (ref "FB6") (pin "1") (pinfunction "1_1") (pintype "passive"))
      (node (ref "R121") (pin "2") (pinfunction "2_2") (pintype "passive"))
      (node (ref "R122") (pin "1") (pinfunction "1_1") (pintype "passive"))
    )
    (net (code "332") (name "USB_LDO_OUT2") (class "Default")
      (node (ref "FB4-2") (pin "1") (pinfunction "1_1") (pintype "passive"))
      (node (ref "FB6-2") (pin "1") (pinfunction "1_1") (pintype "passive"))
      (node (ref "R121-2") (pin "2") (pinfunction "2_2") (pintype "passive"))
      (node (ref "R122-2") (pin "1") (pinfunction "1_1") (pintype "passive"))
    )
    (net (code "333") (name "USB_N") (class "Default")
      (node (ref "J2") (pin "D-") (pinfunction "D-_D-") (pintype "bidirectional"))
      (node (ref "U6") (pin "7") (pinfunction "USBDM_7") (pintype "bidirectional"))
      (node (ref "U7") (pin "5") (pinfunction "IO2_5") (pintype "bidirectional"))
    )
    (net (code "334") (name "USB_P") (class "Default")
      (node (ref "J2") (pin "D+") (pinfunction "D+_D+") (pintype "bidirectional"))
      (node (ref "U6") (pin "8") (pinfunction "USBDP_8") (pintype "bidirectional"))
      (node (ref "U7") (pin "3") (pinfunction "IO1_3") (pintype "bidirectional"))
    )
    (net (code "335") (name "USB_XI") (class "Default")
      (node (ref "R55") (pin "2") (pinfunction "2_2") (pintype "passive"))
      (node (ref "R56") (pin "2") (pinfunction "2_2") (pintype "passive"))
      (node (ref "U4") (pin "E14") (pinfunction "USB_MXI_E14") (pintype "input"))
    )
    (net (code "336") (name "USB_XI2") (class "Default")
      (node (ref "R55-2") (pin "2") (pinfunction "2_2") (pintype "passive"))
      (node (ref "R56-2") (pin "2") (pinfunction "2_2") (pintype "passive"))
      (node (ref "U5") (pin "E14") (pinfunction "USB_MXI_E14") (pintype "input"))
    )
    (net (code "337") (name "V1.65") (class "Default")
      (node (ref "R145") (pin "1") (pinfunction "1_1") (pintype "passive"))
      (node (ref "R171") (pin "1") (pinfunction "1_1") (pintype "passive"))
      (node (ref "R198") (pin "2") (pinfunction "2_2") (pintype "passive"))
      (node (ref "R199") (pin "2") (pinfunction "2_2") (pintype "passive"))
      (node (ref "R200") (pin "2") (pinfunction "2_2") (pintype "passive"))
      (node (ref "U20") (pin "1") (pinfunction "OUT_1") (pintype "output"))
      (node (ref "U20") (pin "2") (pinfunction "-IN_2") (pintype "input"))
      (node (ref "U20") (pin "5") (pinfunction "+IN_5") (pintype "input"))
      (node (ref "U22") (pin "3") (pinfunction "+IN_3") (pintype "input"))
      (node (ref "U22") (pin "5") (pinfunction "+IN_5") (pintype "input"))
      (node (ref "U23") (pin "3") (pinfunction "+IN_3") (pintype "input"))
      (node (ref "U23") (pin "5") (pinfunction "+IN_5") (pintype "input"))
    )
    (net (code "338") (name "V3.3A") (class "Default")
      (node (ref "C179") (pin "+") (pinfunction "+_+") (pintype "passive"))
      (node (ref "C185") (pin "1") (pinfunction "1_1") (pintype "passive"))
      (node (ref "C204") (pin "1") (pinfunction "1_1") (pintype "passive"))
      (node (ref "C209") (pin "1") (pinfunction "1_1") (pintype "passive"))
      (node (ref "C220") (pin "1") (pinfunction "1_1") (pintype "passive"))
      (node (ref "C221") (pin "1") (pinfunction "1_1") (pintype "passive"))
      (node (ref "C222") (pin "1") (pinfunction "1_1") (pintype "passive"))
      (node (ref "C223") (pin "1") (pinfunction "1_1") (pintype "passive"))
      (node (ref "C224") (pin "1") (pinfunction "1_1") (pintype "passive"))
      (node (ref "D9") (pin "C") (pinfunction "C_C") (pintype "passive"))
      (node (ref "FB3") (pin "2") (pinfunction "2_2") (pintype "passive"))
      (node (ref "IC2") (pin "14") (pinfunction "VDD_14") (pintype "power_in"))
      (node (ref "Q3") (pin "1") (pinfunction "D_1") (pintype "passive"))
      (node (ref "R108") (pin "2") (pinfunction "2_2") (pintype "passive"))
      (node (ref "R146") (pin "2") (pinfunction "2_2") (pintype "passive"))
      (node (ref "R168") (pin "2") (pinfunction "2_2") (pintype "passive"))
      (node (ref "R201") (pin "2") (pinfunction "2_2") (pintype "passive"))
      (node (ref "R202") (pin "2") (pinfunction "2_2") (pintype "passive"))
      (node (ref "R203") (pin "2") (pinfunction "2_2") (pintype "passive"))
      (node (ref "R204") (pin "2") (pinfunction "2_2") (pintype "passive"))
      (node (ref "R207") (pin "2") (pinfunction "2_2") (pintype "passive"))
      (node (ref "R211") (pin "2") (pinfunction "2_2") (pintype "passive"))
      (node (ref "U13") (pin "5") (pinfunction "VCC_5") (pintype "power_in"))
      (node (ref "U19") (pin "8") (pinfunction "V+_8") (pintype "power_in"))
      (node (ref "U20") (pin "8") (pinfunction "V+_8") (pintype "power_in"))
      (node (ref "U21") (pin "8") (pinfunction "V+_8") (pintype "power_in"))
      (node (ref "U22") (pin "8") (pinfunction "V+_8") (pintype "power_in"))
      (node (ref "U23") (pin "8") (pinfunction "V+_8") (pintype "power_in"))
      (node (ref "U24") (pin "8") (pinfunction "+V_8") (pintype "power_in"))
    )
    (net (code "339") (name "VBUS2_C5535") (class "Default")
      (node (ref "C24-2") (pin "1") (pinfunction "1_1") (pintype "passive"))
      (node (ref "C25-2") (pin "1") (pinfunction "1_1") (pintype "passive"))
      (node (ref "D2-2") (pin "C") (pinfunction "C_C") (pintype "passive"))
      (node (ref "D5") (pin "A") (pinfunction "A_A") (pintype "passive"))
      (node (ref "J1-2") (pin "VBUS") (pinfunction "VBUS_VBUS") (pintype "bidirectional"))
      (node (ref "R18-2") (pin "2") (pinfunction "2_2") (pintype "passive"))
      (node (ref "U5") (pin "L14") (pinfunction "USB_VBUS_L14") (pintype "bidirectional"))
    )
    (net (code "340") (name "VBUS_C5535") (class "Default")
      (node (ref "C24") (pin "1") (pinfunction "1_1") (pintype "passive"))
      (node (ref "C25") (pin "1") (pinfunction "1_1") (pintype "passive"))
      (node (ref "D2") (pin "C") (pinfunction "C_C") (pintype "passive"))
      (node (ref "D3") (pin "A") (pinfunction "A_A") (pintype "passive"))
      (node (ref "J1") (pin "VBUS") (pinfunction "VBUS_VBUS") (pintype "bidirectional"))
      (node (ref "R18") (pin "2") (pinfunction "2_2") (pintype "passive"))
      (node (ref "U4") (pin "L14") (pinfunction "USB_VBUS_L14") (pintype "bidirectional"))
    )
    (net (code "341") (name "VCCUSB") (class "Default")
      (node (ref "C7") (pin "1") (pinfunction "1_1") (pintype "passive"))
      (node (ref "C92") (pin "1") (pinfunction "1_1") (pintype "passive"))
      (node (ref "D4") (pin "A") (pinfunction "A_A") (pintype "passive"))
      (node (ref "L1") (pin "2") (pinfunction "2_2") (pintype "passive"))
    )
    (net (code "342") (name "VCC_1V3") (class "Default")
      (node (ref "C26X") (pin "1") (pinfunction "1_1") (pintype "passive"))
      (node (ref "C83") (pin "1") (pinfunction "1_1") (pintype "passive"))
      (node (ref "C83-2") (pin "1") (pinfunction "1_1") (pintype "passive"))
      (node (ref "C84") (pin "1") (pinfunction "1_1") (pintype "passive"))
      (node (ref "C84-2") (pin "1") (pinfunction "1_1") (pintype "passive"))
      (node (ref "C95X") (pin "1") (pinfunction "1_1") (pintype "passive"))
      (node (ref "R121") (pin "1") (pinfunction "1_1") (pintype "passive"))
      (node (ref "R121-2") (pin "1") (pinfunction "1_1") (pintype "passive"))
      (node (ref "R125X") (pin "2") (pinfunction "2_2") (pintype "passive"))
      (node (ref "U11X") (pin "5") (pinfunction "OUT_5") (pintype "power_in"))
      (node (ref "U3X") (pin "5") (pinfunction "SENSE_5") (pintype "input"))
      (node (ref "U4") (pin "B4") (pinfunction "CVDDRTC_B4") (pintype "power_in"))
      (node (ref "U4") (pin "B5") (pinfunction "CVDDRTC1_B5") (pintype "power_in"))
      (node (ref "U5") (pin "B4") (pinfunction "CVDDRTC_B4") (pintype "power_in"))
      (node (ref "U5") (pin "B5") (pinfunction "CVDDRTC1_B5") (pintype "power_in"))
    )
    (net (code "343") (name "VCC_1V8") (class "Default")
      (node (ref "C71") (pin "1") (pinfunction "1_1") (pintype "passive"))
      (node (ref "C71-2") (pin "1") (pinfunction "1_1") (pintype "passive"))
      (node (ref "C75") (pin "1") (pinfunction "1_1") (pintype "passive"))
      (node (ref "C75-2") (pin "1") (pinfunction "1_1") (pintype "passive"))
      (node (ref "C87") (pin "1") (pinfunction "1_1") (pintype "passive"))
      (node (ref "C87-2") (pin "1") (pinfunction "1_1") (pintype "passive"))
      (node (ref "C98X") (pin "1") (pinfunction "1_1") (pintype "passive"))
      (node (ref "R106") (pin "1") (pinfunction "1_1") (pintype "passive"))
      (node (ref "R107") (pin "2") (pinfunction "2_2") (pintype "passive"))
      (node (ref "R118X") (pin "2") (pinfunction "2_2") (pintype "passive"))
      (node (ref "R63") (pin "2") (pinfunction "2_2") (pintype "passive"))
      (node (ref "R63-2") (pin "2") (pinfunction "2_2") (pintype "passive"))
      (node (ref "U11X") (pin "1") (pinfunction "IN_1") (pintype "power_in"))
      (node (ref "U11X") (pin "3") (pinfunction "EN_3") (pintype "input"))
      (node (ref "U4") (pin "B10") (pinfunction "LDOI_B10") (pintype "power_in"))
      (node (ref "U4") (pin "B14") (pinfunction "LDOI_B14") (pintype "power_in"))
      (node (ref "U4") (pin "C14") (pinfunction "LDOI_C14") (pintype "power_in"))
      (node (ref "U5") (pin "B10") (pinfunction "LDOI_B10") (pintype "power_in"))
      (node (ref "U5") (pin "B14") (pinfunction "LDOI_B14") (pintype "power_in"))
      (node (ref "U5") (pin "C14") (pinfunction "LDOI_C14") (pintype "power_in"))
    )
    (net (code "344") (name "VCC_3V3") (class "Default")
      (node (ref "C10") (pin "1") (pinfunction "1_1") (pintype "passive"))
      (node (ref "C104") (pin "1") (pinfunction "1_1") (pintype "passive"))
      (node (ref "C122") (pin "1") (pinfunction "1_1") (pintype "passive"))
      (node (ref "C15") (pin "1") (pinfunction "1_1") (pintype "passive"))
      (node (ref "C169X") (pin "1") (pinfunction "1_1") (pintype "passive"))
      (node (ref "C21") (pin "1") (pinfunction "1_1") (pintype "passive"))
      (node (ref "C218X") (pin "1") (pinfunction "1_1") (pintype "passive"))
      (node (ref "C81") (pin "1") (pinfunction "1_1") (pintype "passive"))
      (node (ref "C81-2") (pin "1") (pinfunction "1_1") (pintype "passive"))
      (node (ref "C9") (pin "1") (pinfunction "1_1") (pintype "passive"))
      (node (ref "FB3") (pin "1") (pinfunction "1_1") (pintype "passive"))
      (node (ref "J11") (pin "4") (pinfunction "VDD_4") (pintype "power_in"))
      (node (ref "J5") (pin "1") (pinfunction "1_1") (pintype "passive"))
      (node (ref "J5") (pin "5") (pinfunction "5_5") (pintype "passive"))
      (node (ref "J6") (pin "4") (pinfunction "VDD_4") (pintype "power_in"))
      (node (ref "J7") (pin "2") (pinfunction "2_2") (pintype "passive"))
      (node (ref "L8X") (pin "1") (pinfunction "1_1") (pintype "passive"))
      (node (ref "R1") (pin "2") (pinfunction "2_2") (pintype "passive"))
      (node (ref "R10") (pin "2") (pinfunction "2_2") (pintype "passive"))
      (node (ref "R100") (pin "2") (pinfunction "2_2") (pintype "passive"))
      (node (ref "R101") (pin "2") (pinfunction "2_2") (pintype "passive"))
      (node (ref "R102") (pin "2") (pinfunction "2_2") (pintype "passive"))
      (node (ref "R103") (pin "2") (pinfunction "2_2") (pintype "passive"))
      (node (ref "R109") (pin "2") (pinfunction "2_2") (pintype "passive"))
      (node (ref "R11") (pin "2") (pinfunction "2_2") (pintype "passive"))
      (node (ref "R134") (pin "2") (pinfunction "2_2") (pintype "passive"))
      (node (ref "R135") (pin "2") (pinfunction "2_2") (pintype "passive"))
      (node (ref "R141") (pin "2") (pinfunction "2_2") (pintype "passive"))
      (node (ref "R143X") (pin "2") (pinfunction "2_2") (pintype "passive"))
      (node (ref "R2") (pin "2") (pinfunction "2_2") (pintype "passive"))
      (node (ref "R222X") (pin "1") (pinfunction "1_1") (pintype "passive"))
      (node (ref "R2X") (pin "2") (pinfunction "2_2") (pintype "passive"))
      (node (ref "R3") (pin "2") (pinfunction "2_2") (pintype "passive"))
      (node (ref "R3X") (pin "2") (pinfunction "2_2") (pintype "passive"))
      (node (ref "R4") (pin "2") (pinfunction "2_2") (pintype "passive"))
      (node (ref "R4X") (pin "2") (pinfunction "2_2") (pintype "passive"))
      (node (ref "R5") (pin "1") (pinfunction "1_1") (pintype "passive"))
      (node (ref "R6") (pin "2") (pinfunction "2_2") (pintype "passive"))
      (node (ref "R7") (pin "2") (pinfunction "2_2") (pintype "passive"))
      (node (ref "R98") (pin "2") (pinfunction "2_2") (pintype "passive"))
      (node (ref "R99") (pin "2") (pinfunction "2_2") (pintype "passive"))
      (node (ref "U10X") (pin "8") (pinfunction "VCC_8") (pintype "power_in"))
      (node (ref "U14") (pin "1") (pinfunction "E/D_1") (pintype "input"))
      (node (ref "U14") (pin "4") (pinfunction "VCC_4") (pintype "power_in"))
      (node (ref "U18") (pin "20") (pinfunction "VCC_20") (pintype "power_in"))
      (node (ref "U3X") (pin "4") (pinfunction "VDD_4") (pintype "power_in"))
      (node (ref "U9") (pin "2") (pinfunction "VCC_2") (pintype "power_in"))
      (node (ref "U9-2") (pin "2") (pinfunction "VCC_2") (pintype "power_in"))
    )
    (net (code "345") (name "VCC_3V3_CLK") (class "Default")
      (node (ref "C213X") (pin "1") (pinfunction "1_1") (pintype "passive"))
      (node (ref "C215X") (pin "1") (pinfunction "1_1") (pintype "passive"))
      (node (ref "C216X") (pin "1") (pinfunction "1_1") (pintype "passive"))
      (node (ref "C217X") (pin "1") (pinfunction "1_1") (pintype "passive"))
      (node (ref "L8X") (pin "2") (pinfunction "2_2") (pintype "passive"))
      (node (ref "U15X") (pin "10") (pinfunction "VDD_3_10") (pintype "power_in"))
      (node (ref "U15X") (pin "14") (pinfunction "VDD_14") (pintype "power_in"))
      (node (ref "U15X") (pin "5") (pinfunction "VDD_2_5") (pintype "power_in"))
    )
    (net (code "346") (name "VCC_3V3_PWR") (class "Default")
      (node (ref "C94X") (pin "1") (pinfunction "1_1") (pintype "passive"))
      (node (ref "L7X") (pin "1") (pinfunction "1_1") (pintype "passive"))
      (node (ref "R119X") (pin "1") (pinfunction "1_1") (pintype "passive"))
      (node (ref "R15") (pin "1") (pinfunction "1_1") (pintype "passive"))
      (node (ref "R1X") (pin "1") (pinfunction "1_1") (pintype "passive"))
      (node (ref "R2X") (pin "1") (pinfunction "1_1") (pintype "passive"))
      (node (ref "R65X") (pin "2") (pinfunction "2_2") (pintype "passive"))
      (node (ref "R96X") (pin "1") (pinfunction "1_1") (pintype "passive"))
      (node (ref "R97") (pin "2") (pinfunction "2_2") (pintype "passive"))
      (node (ref "R97-2") (pin "2") (pinfunction "2_2") (pintype "passive"))
      (node (ref "TP5X") (pin "TP") (pinfunction "TP_TP") (pintype "input"))
    )
    (net (code "347") (name "VCC_3V3_USB") (class "Default")
      (node (ref "FB5") (pin "1") (pinfunction "1_1") (pintype "passive"))
      (node (ref "FB5-2") (pin "1") (pinfunction "1_1") (pintype "passive"))
      (node (ref "FB7") (pin "1") (pinfunction "1_1") (pintype "passive"))
      (node (ref "FB7-2") (pin "1") (pinfunction "1_1") (pintype "passive"))
      (node (ref "L3") (pin "1") (pinfunction "1_1") (pintype "passive"))
      (node (ref "L3-2") (pin "1") (pinfunction "1_1") (pintype "passive"))
      (node (ref "R96X") (pin "2") (pinfunction "2_2") (pintype "passive"))
    )
    (net (code "348") (name "VCC_USB_DUAL") (class "Default")
      (node (ref "C23X") (pin "1") (pinfunction "1_1") (pintype "passive"))
      (node (ref "C99X") (pin "1") (pinfunction "1_1") (pintype "passive"))
      (node (ref "D1") (pin "C") (pinfunction "C_C") (pintype "passive"))
      (node (ref "D3") (pin "C") (pinfunction "C_C") (pintype "passive"))
      (node (ref "D4") (pin "C") (pinfunction "C_C") (pintype "passive"))
      (node (ref "D5") (pin "C") (pinfunction "C_C") (pintype "passive"))
      (node (ref "DS1") (pin "A") (pinfunction "A_A") (pintype "passive"))
      (node (ref "U12X") (pin "3") (pinfunction "VIN_3") (pintype "power_in"))
      (node (ref "U12X") (pin "5") (pinfunction "EN_5") (pintype "input"))
      (node (ref "U1X") (pin "3") (pinfunction "VIN_3") (pintype "power_in"))
      (node (ref "U1X") (pin "5") (pinfunction "EN_5") (pintype "input"))
    )
    (net (code "349") (name "VDD_IO1") (class "Default")
      (node (ref "C82") (pin "1") (pinfunction "1_1") (pintype "passive"))
      (node (ref "R119X") (pin "2") (pinfunction "2_2") (pintype "passive"))
      (node (ref "R13") (pin "2") (pinfunction "2_2") (pintype "passive"))
      (node (ref "R14") (pin "2") (pinfunction "2_2") (pintype "passive"))
      (node (ref "R16") (pin "2") (pinfunction "2_2") (pintype "passive"))
      (node (ref "R22") (pin "2") (pinfunction "2_2") (pintype "passive"))
      (node (ref "R25") (pin "2") (pinfunction "2_2") (pintype "passive"))
      (node (ref "R37") (pin "2") (pinfunction "2_2") (pintype "passive"))
      (node (ref "R41") (pin "2") (pinfunction "2_2") (pintype "passive"))
      (node (ref "R50") (pin "2") (pinfunction "2_2") (pintype "passive"))
      (node (ref "R51") (pin "2") (pinfunction "2_2") (pintype "passive"))
      (node (ref "R52") (pin "2") (pinfunction "2_2") (pintype "passive"))
      (node (ref "R72") (pin "2") (pinfunction "2_2") (pintype "passive"))
      (node (ref "R73") (pin "2") (pinfunction "2_2") (pintype "passive"))
      (node (ref "U4") (pin "C3") (pinfunction "DVDDRTC_C3") (pintype "power_in"))
    )
    (net (code "350") (name "VDD_IO1_CPU") (class "Default")
      (node (ref "C1") (pin "1") (pinfunction "1_1") (pintype "passive"))
      (node (ref "C28") (pin "1") (pinfunction "1_1") (pintype "passive"))
      (node (ref "C29") (pin "1") (pinfunction "1_1") (pintype "passive"))
      (node (ref "C30") (pin "1") (pinfunction "1_1") (pintype "passive"))
      (node (ref "C32") (pin "1") (pinfunction "1_1") (pintype "passive"))
      (node (ref "C45") (pin "1") (pinfunction "1_1") (pintype "passive"))
      (node (ref "C72") (pin "1") (pinfunction "1_1") (pintype "passive"))
      (node (ref "R97") (pin "1") (pinfunction "1_1") (pintype "passive"))
      (node (ref "U4") (pin "C6") (pinfunction "DVDDIO_C6") (pintype "power_in"))
      (node (ref "U4") (pin "L4") (pinfunction "DVDDIO_L4") (pintype "power_in"))
      (node (ref "U4") (pin "M3") (pinfunction "DVDDIO_M3") (pintype "power_in"))
      (node (ref "U4") (pin "M4") (pinfunction "DVDDIO_M4") (pintype "power_in"))
      (node (ref "U4") (pin "N11") (pinfunction "DVDDIO_N11") (pintype "power_in"))
      (node (ref "U4") (pin "N14") (pinfunction "DVDDIO_N14") (pintype "power_in"))
      (node (ref "U4") (pin "N8") (pinfunction "DVDDIO_N8") (pintype "power_in"))
    )
    (net (code "351") (name "VDD_IO2") (class "Default")
      (node (ref "C82-2") (pin "1") (pinfunction "1_1") (pintype "passive"))
      (node (ref "R13-2") (pin "2") (pinfunction "2_2") (pintype "passive"))
      (node (ref "R14-2") (pin "2") (pinfunction "2_2") (pintype "passive"))
      (node (ref "R15") (pin "2") (pinfunction "2_2") (pintype "passive"))
      (node (ref "R37-2") (pin "2") (pinfunction "2_2") (pintype "passive"))
      (node (ref "R41-2") (pin "2") (pinfunction "2_2") (pintype "passive"))
      (node (ref "R50-2") (pin "2") (pinfunction "2_2") (pintype "passive"))
      (node (ref "R51-2") (pin "2") (pinfunction "2_2") (pintype "passive"))
      (node (ref "R52-1") (pin "2") (pinfunction "2_2") (pintype "passive"))
      (node (ref "R52-2") (pin "2") (pinfunction "2_2") (pintype "passive"))
      (node (ref "R72-2") (pin "2") (pinfunction "2_2") (pintype "passive"))
      (node (ref "R73-2") (pin "2") (pinfunction "2_2") (pintype "passive"))
      (node (ref "U5") (pin "C3") (pinfunction "DVDDRTC_C3") (pintype "power_in"))
    )
    (net (code "352") (name "VDD_IO2_CPU") (class "Default")
      (node (ref "C1-2") (pin "1") (pinfunction "1_1") (pintype "passive"))
      (node (ref "C28-2") (pin "1") (pinfunction "1_1") (pintype "passive"))
      (node (ref "C29-2") (pin "1") (pinfunction "1_1") (pintype "passive"))
      (node (ref "C30-2") (pin "1") (pinfunction "1_1") (pintype "passive"))
      (node (ref "C32-2") (pin "1") (pinfunction "1_1") (pintype "passive"))
      (node (ref "C45-2") (pin "1") (pinfunction "1_1") (pintype "passive"))
      (node (ref "C72-2") (pin "1") (pinfunction "1_1") (pintype "passive"))
      (node (ref "R97-2") (pin "1") (pinfunction "1_1") (pintype "passive"))
      (node (ref "U5") (pin "C6") (pinfunction "DVDDIO_C6") (pintype "power_in"))
      (node (ref "U5") (pin "L4") (pinfunction "DVDDIO_L4") (pintype "power_in"))
      (node (ref "U5") (pin "M3") (pinfunction "DVDDIO_M3") (pintype "power_in"))
      (node (ref "U5") (pin "M4") (pinfunction "DVDDIO_M4") (pintype "power_in"))
      (node (ref "U5") (pin "N11") (pinfunction "DVDDIO_N11") (pintype "power_in"))
      (node (ref "U5") (pin "N14") (pinfunction "DVDDIO_N14") (pintype "power_in"))
      (node (ref "U5") (pin "N8") (pinfunction "DVDDIO_N8") (pintype "power_in"))
    )
    (net (code "353") (name "VPHY") (class "Default")
      (node (ref "C44") (pin "2") (pinfunction "2_2") (pintype "passive"))
      (node (ref "C47") (pin "2") (pinfunction "2_2") (pintype "passive"))
      (node (ref "L4") (pin "2") (pinfunction "2_2") (pintype "passive"))
      (node (ref "U6") (pin "4") (pinfunction "VPHY_4") (pintype "power_in"))
    )
    (net (code "354") (name "VPLL") (class "Default")
      (node (ref "C61") (pin "2") (pinfunction "2_2") (pintype "passive"))
      (node (ref "C76") (pin "2") (pinfunction "2_2") (pintype "passive"))
      (node (ref "L5") (pin "2") (pinfunction "2_2") (pintype "passive"))
      (node (ref "U6") (pin "9") (pinfunction "VPLL_9") (pintype "power_in"))
    )
    (net (code "355") (name "VSS1RTC") (class "Default")
      (node (ref "C90") (pin "1") (pinfunction "1_1") (pintype "passive"))
      (node (ref "C91") (pin "1") (pinfunction "1_1") (pintype "passive"))
      (node (ref "U4") (pin "C5") (pinfunction "VSSRTC_C5") (pintype "power_in"))
    )
    (net (code "356") (name "VSS2RTC") (class "Default")
      (node (ref "C90-2") (pin "1") (pinfunction "1_1") (pintype "passive"))
      (node (ref "C91-2") (pin "1") (pinfunction "1_1") (pintype "passive"))
      (node (ref "U5") (pin "C5") (pinfunction "VSSRTC_C5") (pintype "power_in"))
    )
    (net (code "357") (name "VUSB") (class "Default")
      (node (ref "C93") (pin "1") (pinfunction "1_1") (pintype "passive"))
      (node (ref "J2") (pin "VUSB") (pinfunction "VBUS_VUSB") (pintype "bidirectional"))
      (node (ref "L1") (pin "1") (pinfunction "1_1") (pintype "passive"))
      (node (ref "U7") (pin "1") (pinfunction "VCC_1") (pintype "power_in"))
    )
    (net (code "358") (name "WAKEUP") (class "Default")
      (node (ref "R59") (pin "2") (pinfunction "2_2") (pintype "passive"))
      (node (ref "U4") (pin "A5") (pinfunction "WAKEUP_A5") (pintype "bidirectional"))
    )
    (net (code "359") (name "WAKEUP2") (class "Default")
      (node (ref "R59-2") (pin "2") (pinfunction "2_2") (pintype "passive"))
      (node (ref "U5") (pin "A5") (pinfunction "WAKEUP_A5") (pintype "bidirectional"))
    )
    (net (code "360") (name "XF") (class "Default")
      (node (ref "R67") (pin "2") (pinfunction "2_2") (pintype "passive"))
      (node (ref "U4") (pin "J3") (pinfunction "XF_J3") (pintype "output"))
    )
    (net (code "361") (name "XF2") (class "Default")
      (node (ref "R105X") (pin "2") (pinfunction "2_2") (pintype "passive"))
      (node (ref "U5") (pin "J3") (pinfunction "XF_J3") (pintype "output"))
    )
    (net (code "362") (name "unconnected-(CF1-2-Pad2@2)") (class "Default")
      (node (ref "CF1") (pin "2@2") (pinfunction "2_2@2") (pintype "passive"))
    )
    (net (code "363") (name "unconnected-(D8-C1A2-Pad3)") (class "Default")
      (node (ref "D8") (pin "3") (pinfunction "C1A2_3") (pintype "passive"))
    )
    (net (code "364") (name "unconnected-(J1-2-PadID)") (class "Default")
      (node (ref "J1-2") (pin "ID") (pinfunction "ID_ID") (pintype "bidirectional"))
    )
    (net (code "365") (name "unconnected-(J1-PadID)") (class "Default")
      (node (ref "J1") (pin "ID") (pinfunction "ID_ID") (pintype "bidirectional"))
    )
    (net (code "366") (name "unconnected-(J4-RN-Pad5)") (class "Default")
      (node (ref "J4") (pin "5") (pinfunction "RN_5") (pintype "passive"))
    )
    (net (code "367") (name "unconnected-(J4-TN-Pad4)") (class "Default")
      (node (ref "J4") (pin "4") (pinfunction "TN_4") (pintype "passive"))
    )
    (net (code "368") (name "unconnected-(J6-Pad10)") (class "Default")
      (node (ref "J6") (pin "10") (pinfunction "10_10") (pintype "no_connect"))
    )
    (net (code "369") (name "unconnected-(J6-Pad12)") (class "Default")
      (node (ref "J6") (pin "12") (pinfunction "12_12") (pintype "no_connect"))
    )
    (net (code "370") (name "unconnected-(J6-Pad13)") (class "Default")
      (node (ref "J6") (pin "13") (pinfunction "13_13") (pintype "no_connect"))
    )
    (net (code "371") (name "unconnected-(J6-Pad14)") (class "Default")
      (node (ref "J6") (pin "14") (pinfunction "14_14") (pintype "no_connect"))
    )
    (net (code "372") (name "unconnected-(J9-PadSN)") (class "Default")
      (node (ref "J9") (pin "SN") (pinfunction "SN_SN") (pintype "passive"))
    )
    (net (code "373") (name "unconnected-(J9-PadTN)") (class "Default")
      (node (ref "J9") (pin "TN") (pinfunction "TN_TN") (pintype "passive"))
    )
    (net (code "374") (name "unconnected-(J10-PadSN)") (class "Default")
      (node (ref "J10") (pin "SN") (pinfunction "SN_SN") (pintype "passive"))
    )
    (net (code "375") (name "unconnected-(J10-PadTN)") (class "Default")
      (node (ref "J10") (pin "TN") (pinfunction "TN_TN") (pintype "passive"))
    )
    (net (code "376") (name "unconnected-(J11-Pad10)") (class "Default")
      (node (ref "J11") (pin "10") (pinfunction "10_10") (pintype "no_connect"))
    )
    (net (code "377") (name "unconnected-(J11-Pad12)") (class "Default")
      (node (ref "J11") (pin "12") (pinfunction "12_12") (pintype "no_connect"))
    )
    (net (code "378") (name "unconnected-(J11-Pad13)") (class "Default")
      (node (ref "J11") (pin "13") (pinfunction "13_13") (pintype "no_connect"))
    )
    (net (code "379") (name "unconnected-(J11-Pad14)") (class "Default")
      (node (ref "J11") (pin "14") (pinfunction "14_14") (pintype "no_connect"))
    )
    (net (code "380") (name "unconnected-(SW2A-O-Pad3)") (class "Default")
      (node (ref "SW2") (pin "3") (pinfunction "O_3") (pintype "passive"))
    )
    (net (code "381") (name "unconnected-(U2-DC-Pad7)") (class "Default")
      (node (ref "U2") (pin "7") (pinfunction "DC_7") (pintype "no_connect"))
    )
    (net (code "382") (name "unconnected-(U2-NC-Pad6)") (class "Default")
      (node (ref "U2") (pin "6") (pinfunction "NC_6") (pintype "no_connect"))
    )
    (net (code "383") (name "unconnected-(U3X-NC-Pad1)") (class "Default")
      (node (ref "U3X") (pin "1") (pinfunction "NC_1") (pintype "no_connect"))
    )
    (net (code "384") (name "unconnected-(U4B-RSV7-PadE1)") (class "Default")
      (node (ref "U4") (pin "E1") (pinfunction "RSV7_E1") (pintype "input"))
    )
    (net (code "385") (name "unconnected-(U4B-RSV8-PadF1)") (class "Default")
      (node (ref "U4") (pin "F1") (pinfunction "RSV8_F1") (pintype "input"))
    )
    (net (code "386") (name "unconnected-(U4B-RSV9-PadG1)") (class "Default")
      (node (ref "U4") (pin "G1") (pinfunction "RSV9_G1") (pintype "input"))
    )
    (net (code "387") (name "unconnected-(U4B-RSV10-PadH1)") (class "Default")
      (node (ref "U4") (pin "H1") (pinfunction "RSV10_H1") (pintype "input"))
    )
    (net (code "388") (name "unconnected-(U4B-RSV11-PadE2)") (class "Default")
      (node (ref "U4") (pin "E2") (pinfunction "RSV11_E2") (pintype "input"))
    )
    (net (code "389") (name "unconnected-(U4B-RSV12-PadG2)") (class "Default")
      (node (ref "U4") (pin "G2") (pinfunction "RSV12_G2") (pintype "input"))
    )
    (net (code "390") (name "unconnected-(U4B-USB_MXO-PadD14)") (class "Default")
      (node (ref "U4") (pin "D14") (pinfunction "USB_MXO_D14") (pintype "output"))
    )
    (net (code "391") (name "unconnected-(U5B-RSV7-PadE1)") (class "Default")
      (node (ref "U5") (pin "E1") (pinfunction "RSV7_E1") (pintype "input"))
    )
    (net (code "392") (name "unconnected-(U5B-RSV8-PadF1)") (class "Default")
      (node (ref "U5") (pin "F1") (pinfunction "RSV8_F1") (pintype "input"))
    )
    (net (code "393") (name "unconnected-(U5B-RSV9-PadG1)") (class "Default")
      (node (ref "U5") (pin "G1") (pinfunction "RSV9_G1") (pintype "input"))
    )
    (net (code "394") (name "unconnected-(U5B-RSV10-PadH1)") (class "Default")
      (node (ref "U5") (pin "H1") (pinfunction "RSV10_H1") (pintype "input"))
    )
    (net (code "395") (name "unconnected-(U5B-RSV11-PadE2)") (class "Default")
      (node (ref "U5") (pin "E2") (pinfunction "RSV11_E2") (pintype "input"))
    )
    (net (code "396") (name "unconnected-(U5B-RSV12-PadG2)") (class "Default")
      (node (ref "U5") (pin "G2") (pinfunction "RSV12_G2") (pintype "input"))
    )
    (net (code "397") (name "unconnected-(U5B-USB_MXO-PadD14)") (class "Default")
      (node (ref "U5") (pin "D14") (pinfunction "USB_MXO_D14") (pintype "output"))
    )
    (net (code "398") (name "unconnected-(U6-ACBUS6-Pad33)") (class "Default")
      (node (ref "U6") (pin "33") (pinfunction "ACBUS6_33") (pintype "bidirectional"))
    )
    (net (code "399") (name "unconnected-(U6-ACBUS7-Pad34)") (class "Default")
      (node (ref "U6") (pin "34") (pinfunction "ACBUS7_34") (pintype "bidirectional"))
    )
    (net (code "400") (name "unconnected-(U6-ADBUS5-Pad22)") (class "Default")
      (node (ref "U6") (pin "22") (pinfunction "ADBUS5_22") (pintype "bidirectional"))
    )
    (net (code "401") (name "unconnected-(U6-BCBUS0-Pad48)") (class "Default")
      (node (ref "U6") (pin "48") (pinfunction "BCBUS0_48") (pintype "bidirectional"))
    )
    (net (code "402") (name "unconnected-(U6-BCBUS1-Pad52)") (class "Default")
      (node (ref "U6") (pin "52") (pinfunction "BCBUS1_52") (pintype "bidirectional"))
    )
    (net (code "403") (name "unconnected-(U6-BCBUS2-Pad53)") (class "Default")
      (node (ref "U6") (pin "53") (pinfunction "BCBUS2_53") (pintype "bidirectional"))
    )
    (net (code "404") (name "unconnected-(U6-BCBUS3-Pad54)") (class "Default")
      (node (ref "U6") (pin "54") (pinfunction "BCBUS3_54") (pintype "bidirectional"))
    )
    (net (code "405") (name "unconnected-(U6-BCBUS4-Pad55)") (class "Default")
      (node (ref "U6") (pin "55") (pinfunction "BCBUS4_55") (pintype "bidirectional"))
    )
    (net (code "406") (name "unconnected-(U6-BCBUS5-Pad57)") (class "Default")
      (node (ref "U6") (pin "57") (pinfunction "BCBUS5_57") (pintype "bidirectional"))
    )
    (net (code "407") (name "unconnected-(U6-BCBUS6-Pad58)") (class "Default")
      (node (ref "U6") (pin "58") (pinfunction "BCBUS6_58") (pintype "bidirectional"))
    )
    (net (code "408") (name "unconnected-(U6-BCBUS7-Pad59)") (class "Default")
      (node (ref "U6") (pin "59") (pinfunction "BCBUS7_59") (pintype "bidirectional"))
    )
    (net (code "409") (name "unconnected-(U6-BDBUS4-Pad43)") (class "Default")
      (node (ref "U6") (pin "43") (pinfunction "BDBUS4_43") (pintype "output"))
    )
    (net (code "410") (name "unconnected-(U6-BDBUS5-Pad44)") (class "Default")
      (node (ref "U6") (pin "44") (pinfunction "BDBUS5_44") (pintype "input"))
    )
    (net (code "411") (name "unconnected-(U6-BDBUS6-Pad45)") (class "Default")
      (node (ref "U6") (pin "45") (pinfunction "BDBUS6_45") (pintype "input"))
    )
    (net (code "412") (name "unconnected-(U6-BDBUS7-Pad46)") (class "Default")
      (node (ref "U6") (pin "46") (pinfunction "BDBUS7_46") (pintype "input"))
    )
    (net (code "413") (name "unconnected-(U6-SUSPEND#-Pad36)") (class "Default")
      (node (ref "U6") (pin "36") (pinfunction "SUSPEND#_36") (pintype "output"))
    )
    (net (code "414") (name "unconnected-(U6-TEST-Pad13)") (class "Default")
      (node (ref "U6") (pin "13") (pinfunction "TEST_13") (pintype "input"))
    )
    (net (code "415") (name "unconnected-(U6-XTOUT-Pad3)") (class "Default")
      (node (ref "U6") (pin "3") (pinfunction "XTOUT_3") (pintype "output"))
    )
    (net (code "416") (name "unconnected-(U7-NC-Pad2)") (class "Default")
      (node (ref "U7") (pin "2") (pinfunction "NC_2") (pintype "no_connect"))
    )
    (net (code "417") (name "unconnected-(U9-2-NC-Pad3)") (class "Default")
      (node (ref "U9-2") (pin "3") (pinfunction "NC_3") (pintype "no_connect"))
    )
    (net (code "418") (name "unconnected-(U9-2-NC-Pad4)") (class "Default")
      (node (ref "U9-2") (pin "4") (pinfunction "NC_4") (pintype "no_connect"))
    )
    (net (code "419") (name "unconnected-(U9-2-NC-Pad5)") (class "Default")
      (node (ref "U9-2") (pin "5") (pinfunction "NC_5") (pintype "no_connect"))
    )
    (net (code "420") (name "unconnected-(U9-2-NC-Pad6)") (class "Default")
      (node (ref "U9-2") (pin "6") (pinfunction "NC_6") (pintype "no_connect"))
    )
    (net (code "421") (name "unconnected-(U9-2-NC-Pad11)") (class "Default")
      (node (ref "U9-2") (pin "11") (pinfunction "NC_11") (pintype "no_connect"))
    )
    (net (code "422") (name "unconnected-(U9-2-NC-Pad12)") (class "Default")
      (node (ref "U9-2") (pin "12") (pinfunction "NC_12") (pintype "no_connect"))
    )
    (net (code "423") (name "unconnected-(U9-2-NC-Pad13)") (class "Default")
      (node (ref "U9-2") (pin "13") (pinfunction "NC_13") (pintype "no_connect"))
    )
    (net (code "424") (name "unconnected-(U9-2-NC-Pad14)") (class "Default")
      (node (ref "U9-2") (pin "14") (pinfunction "NC_14") (pintype "no_connect"))
    )
    (net (code "425") (name "unconnected-(U9-NC-Pad3)") (class "Default")
      (node (ref "U9") (pin "3") (pinfunction "NC_3") (pintype "no_connect"))
    )
    (net (code "426") (name "unconnected-(U9-NC-Pad4)") (class "Default")
      (node (ref "U9") (pin "4") (pinfunction "NC_4") (pintype "no_connect"))
    )
    (net (code "427") (name "unconnected-(U9-NC-Pad5)") (class "Default")
      (node (ref "U9") (pin "5") (pinfunction "NC_5") (pintype "no_connect"))
    )
    (net (code "428") (name "unconnected-(U9-NC-Pad6)") (class "Default")
      (node (ref "U9") (pin "6") (pinfunction "NC_6") (pintype "no_connect"))
    )
    (net (code "429") (name "unconnected-(U9-NC-Pad11)") (class "Default")
      (node (ref "U9") (pin "11") (pinfunction "NC_11") (pintype "no_connect"))
    )
    (net (code "430") (name "unconnected-(U9-NC-Pad12)") (class "Default")
      (node (ref "U9") (pin "12") (pinfunction "NC_12") (pintype "no_connect"))
    )
    (net (code "431") (name "unconnected-(U9-NC-Pad13)") (class "Default")
      (node (ref "U9") (pin "13") (pinfunction "NC_13") (pintype "no_connect"))
    )
    (net (code "432") (name "unconnected-(U9-NC-Pad14)") (class "Default")
      (node (ref "U9") (pin "14") (pinfunction "NC_14") (pintype "no_connect"))
    )
    (net (code "433") (name "unconnected-(U17-GPIO{slash}MFP5_(32)-Pad32)") (class "Default")
      (node (ref "U17") (pin "32") (pinfunction "GPIO/MFP5_(32)_32") (pintype "input"))
    )
    (net (code "434") (name "unconnected-(U17-IN1_L-Pad13)") (class "Default")
      (node (ref "U17") (pin "13") (pinfunction "IN1_L_13") (pintype "input"))
    )
    (net (code "435") (name "unconnected-(U17-IN1_R-Pad14)") (class "Default")
      (node (ref "U17") (pin "14") (pinfunction "IN1_R_14") (pintype "input"))
    )
    (net (code "436") (name "unconnected-(U17-IN3_L-Pad20)") (class "Default")
      (node (ref "U17") (pin "20") (pinfunction "IN3_L_20") (pintype "input"))
    )
    (net (code "437") (name "unconnected-(U17-IN3_R-Pad21)") (class "Default")
      (node (ref "U17") (pin "21") (pinfunction "IN3_R_21") (pintype "input"))
    )
    (net (code "438") (name "unconnected-(U17-MISO{slash}MFP4-Pad11)") (class "Default")
      (node (ref "U17") (pin "11") (pinfunction "MISO/MFP4_11") (pintype "output"))
    )
    (net (code "439") (name "unconnected-(U17-SCLK{slash}MFP3-Pad8)") (class "Default")
      (node (ref "U17") (pin "8") (pinfunction "SCLK/MFP3_8") (pintype "input"))
    )
    (net (code "440") (name "unconnected-(U18-NC-Pad1)") (class "Default")
      (node (ref "U18") (pin "1") (pinfunction "NC_1") (pintype "no_connect"))
    )
  )
)
